# Liv_Flo_Sign_LED_V1_0.net
KiCad netlist of a schematic drawn in Altium Designer
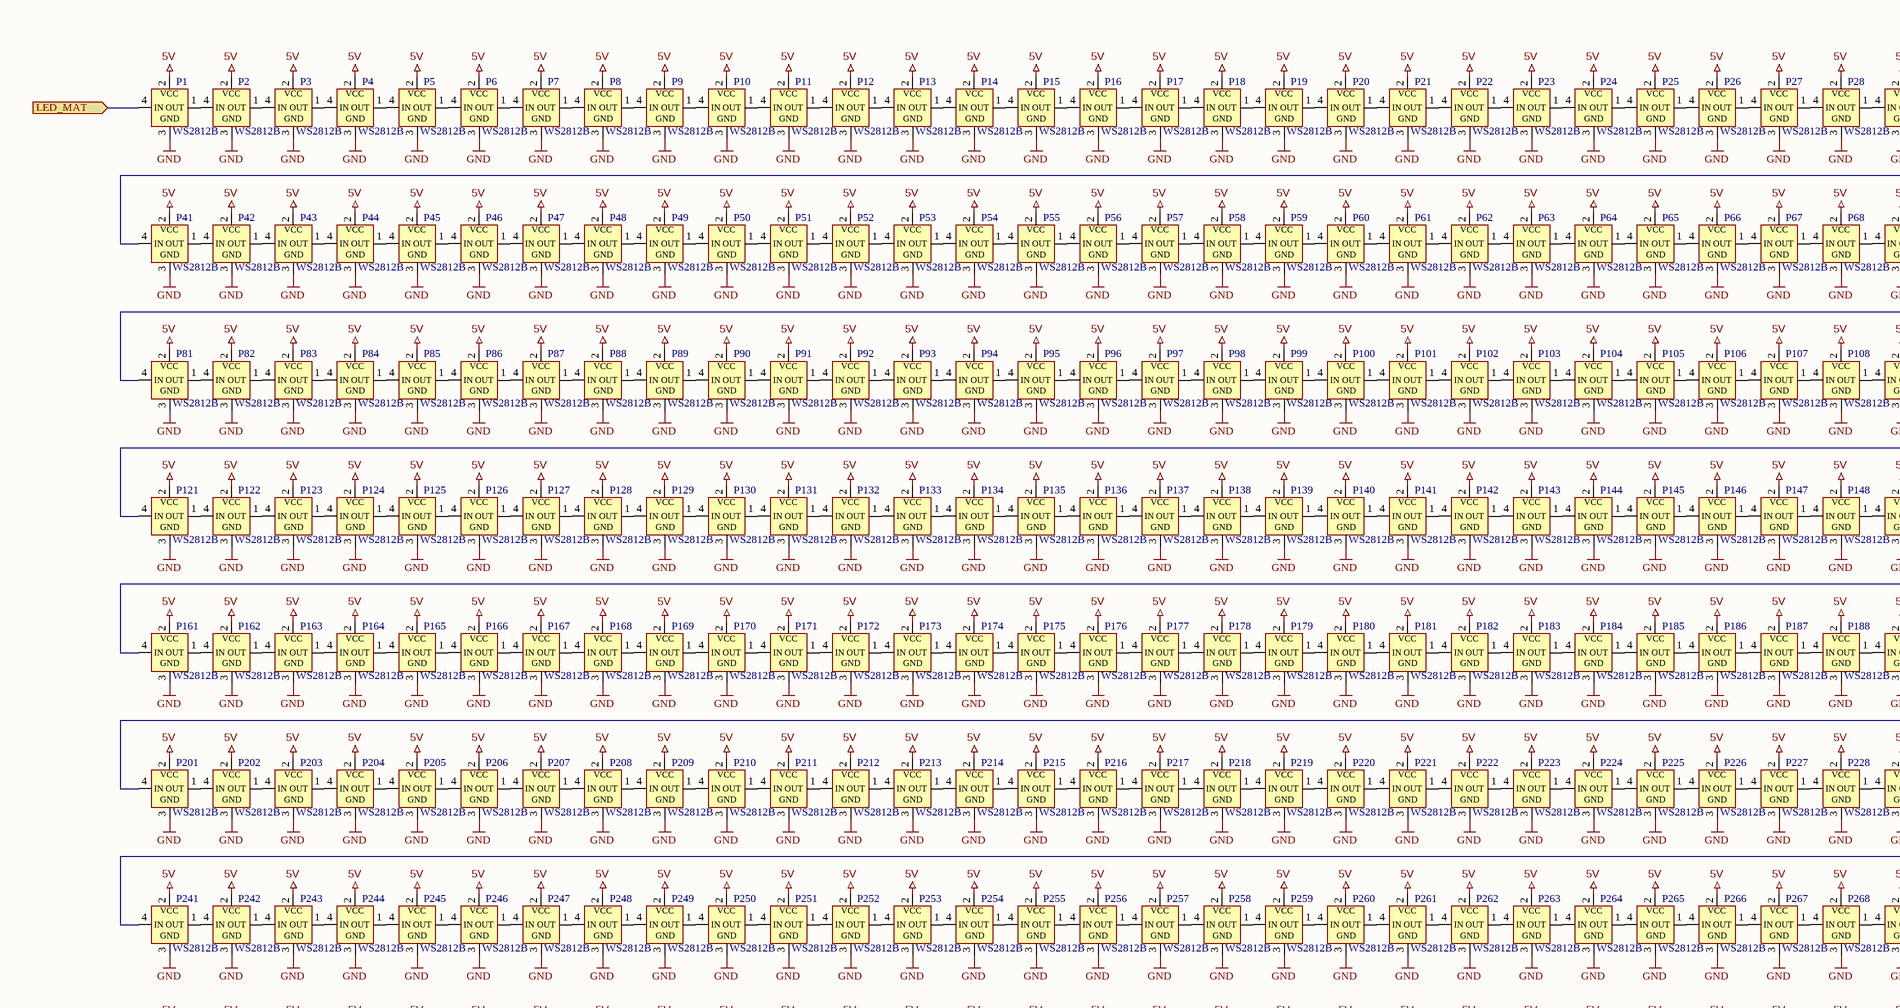
[diagram p0: Liv_Flo_Sign_LED_V1.0.SchDoc, top left]
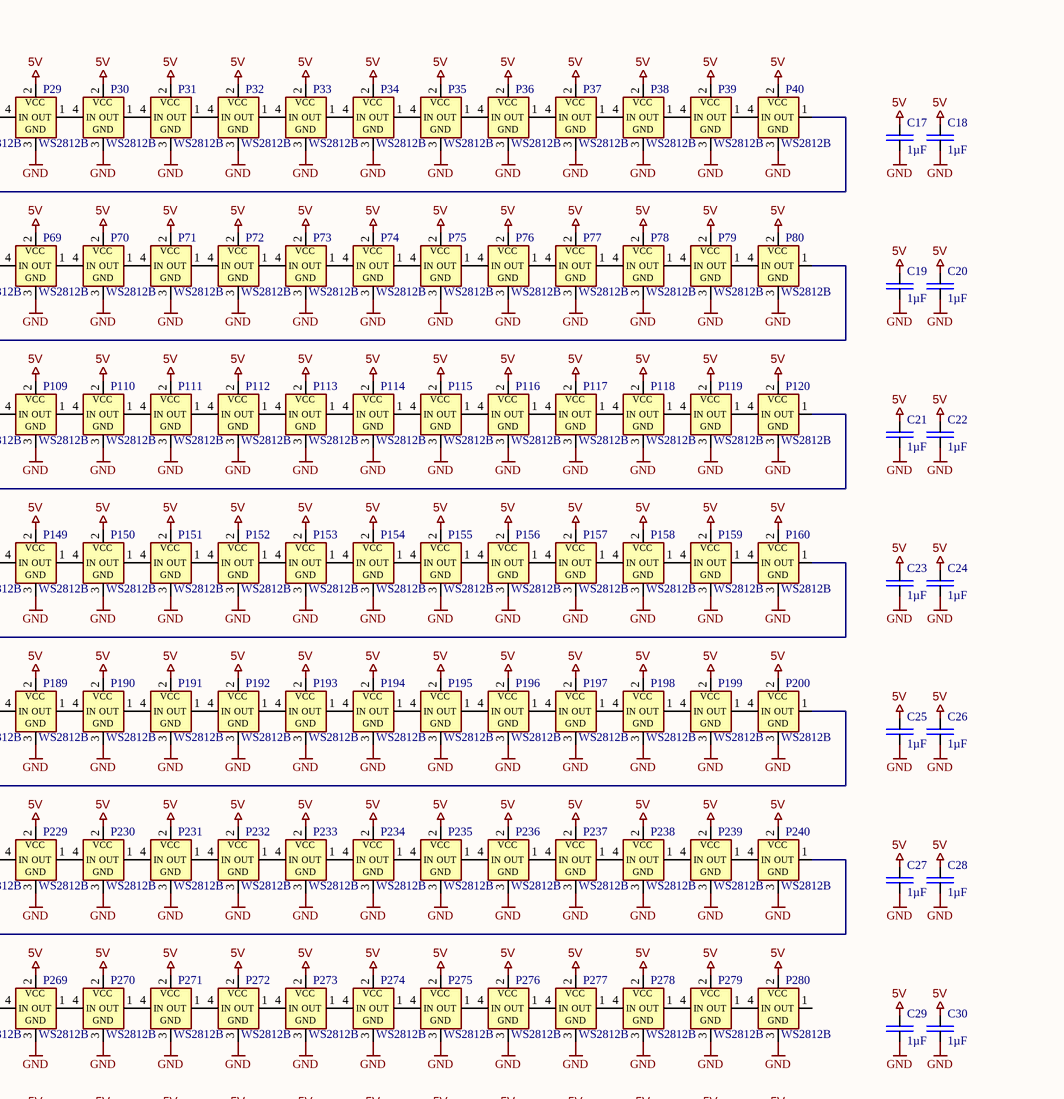
[diagram p1: Liv_Flo_Sign_LED_V1.0.SchDoc, top right]
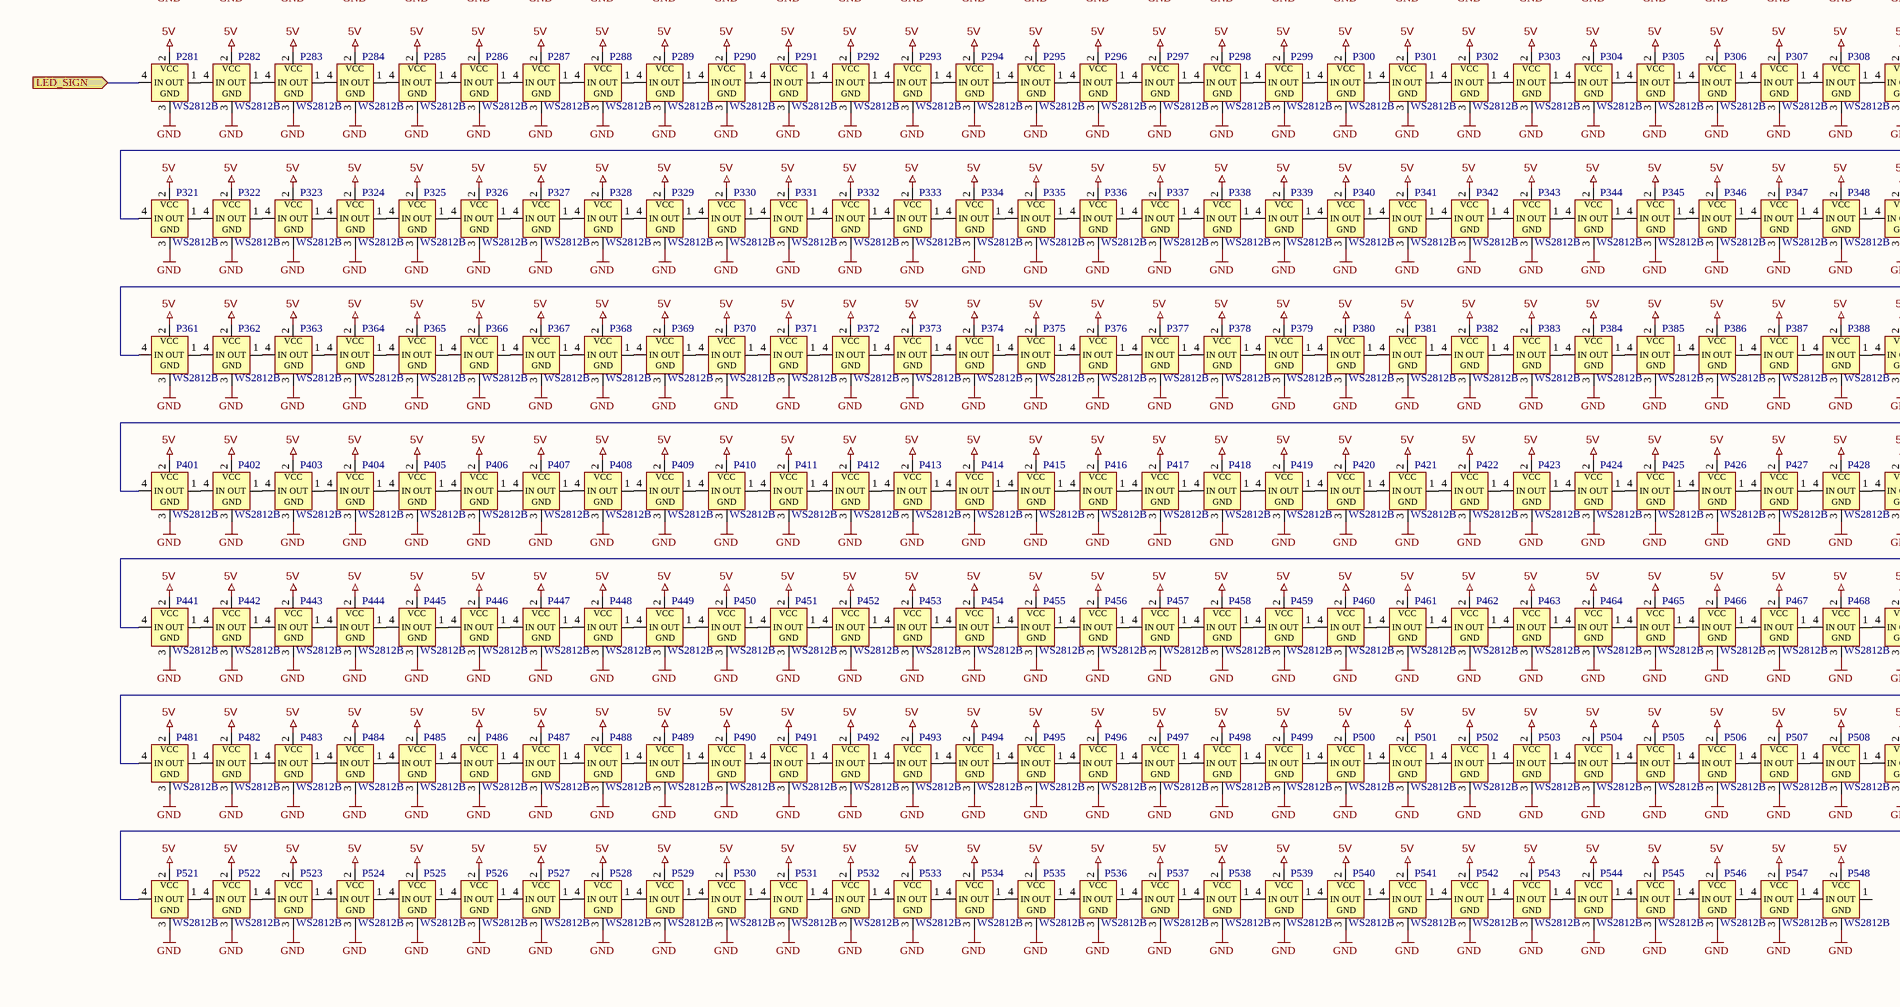
[diagram p2: Liv_Flo_Sign_LED_V1.0.SchDoc, bottom left]
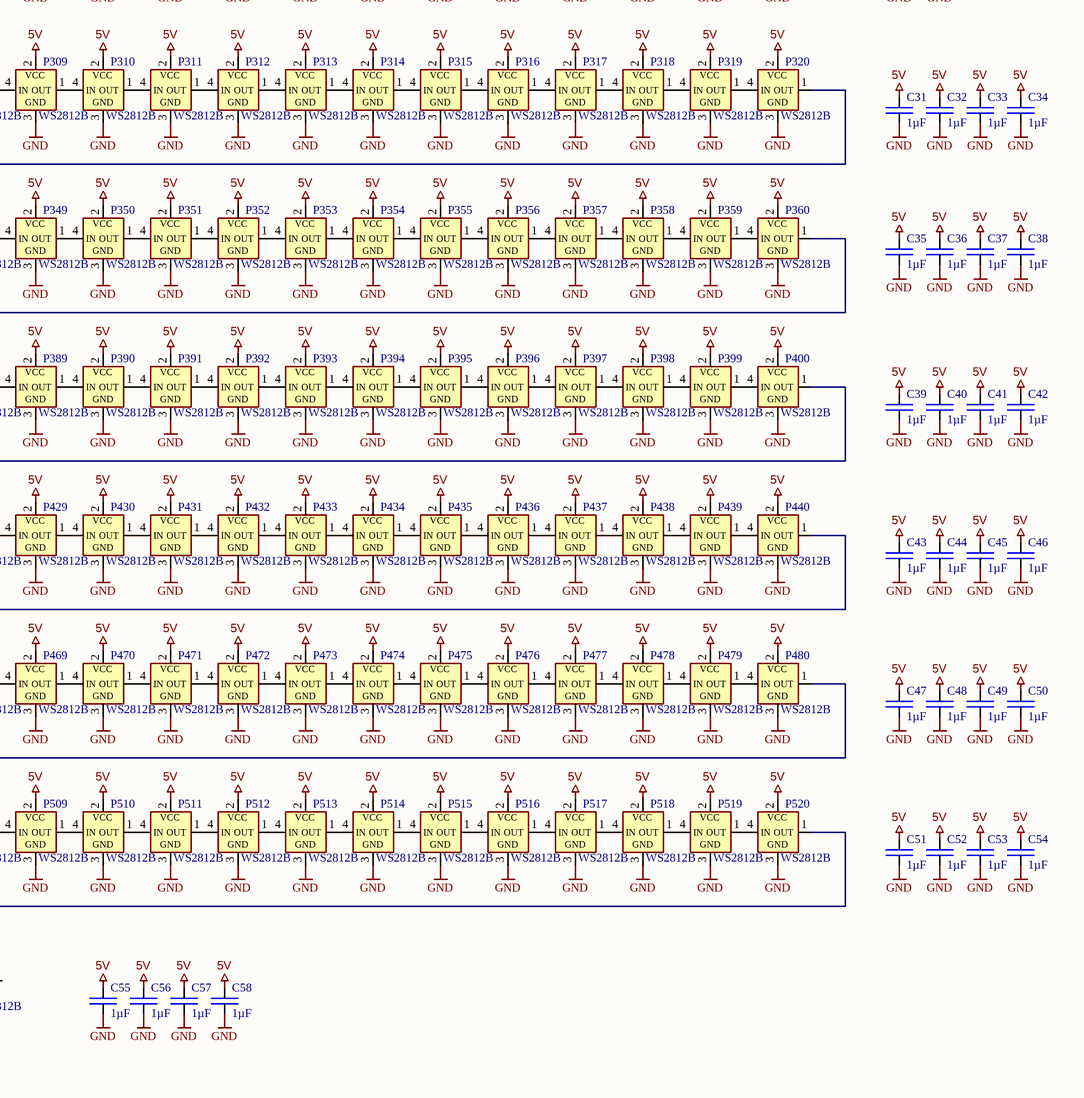
[diagram p3: Liv_Flo_Sign_LED_V1.0.SchDoc, bottom right]

(export (version "E")
  (design (tool "Eeschema 10.0.6"))
  (components
    (comp (ref "C17")
      (value "1µF")
      (footprint "SMD Keramikkondensator 0402")
      (description "SMD Ceramic Capacitor E6")
      (libsource (lib "Ceramic Capacitors-E6") (part "E6 - 4.7uF"))
    )
    (comp (ref "C18")
      (value "1µF")
      (footprint "SMD Keramikkondensator 0402")
      (description "SMD Ceramic Capacitor E6")
      (libsource (lib "Ceramic Capacitors-E6") (part "E6 - 4.7uF"))
    )
    (comp (ref "C19")
      (value "1µF")
      (footprint "SMD Keramikkondensator 0402")
      (description "SMD Ceramic Capacitor E6")
      (libsource (lib "Ceramic Capacitors-E6") (part "E6 - 4.7uF"))
    )
    (comp (ref "C20")
      (value "1µF")
      (footprint "SMD Keramikkondensator 0402")
      (description "SMD Ceramic Capacitor E6")
      (libsource (lib "Ceramic Capacitors-E6") (part "E6 - 4.7uF"))
    )
    (comp (ref "C21")
      (value "1µF")
      (footprint "SMD Keramikkondensator 0402")
      (description "SMD Ceramic Capacitor E6")
      (libsource (lib "Ceramic Capacitors-E6") (part "E6 - 4.7uF"))
    )
    (comp (ref "C22")
      (value "1µF")
      (footprint "SMD Keramikkondensator 0402")
      (description "SMD Ceramic Capacitor E6")
      (libsource (lib "Ceramic Capacitors-E6") (part "E6 - 4.7uF"))
    )
    (comp (ref "C23")
      (value "1µF")
      (footprint "SMD Keramikkondensator 0402")
      (description "SMD Ceramic Capacitor E6")
      (libsource (lib "Ceramic Capacitors-E6") (part "E6 - 4.7uF"))
    )
    (comp (ref "C24")
      (value "1µF")
      (footprint "SMD Keramikkondensator 0402")
      (description "SMD Ceramic Capacitor E6")
      (libsource (lib "Ceramic Capacitors-E6") (part "E6 - 4.7uF"))
    )
    (comp (ref "C25")
      (value "1µF")
      (footprint "SMD Keramikkondensator 0402")
      (description "SMD Ceramic Capacitor E6")
      (libsource (lib "Ceramic Capacitors-E6") (part "E6 - 4.7uF"))
    )
    (comp (ref "C26")
      (value "1µF")
      (footprint "SMD Keramikkondensator 0402")
      (description "SMD Ceramic Capacitor E6")
      (libsource (lib "Ceramic Capacitors-E6") (part "E6 - 4.7uF"))
    )
    (comp (ref "C27")
      (value "1µF")
      (footprint "SMD Keramikkondensator 0402")
      (description "SMD Ceramic Capacitor E6")
      (libsource (lib "Ceramic Capacitors-E6") (part "E6 - 4.7uF"))
    )
    (comp (ref "C28")
      (value "1µF")
      (footprint "SMD Keramikkondensator 0402")
      (description "SMD Ceramic Capacitor E6")
      (libsource (lib "Ceramic Capacitors-E6") (part "E6 - 4.7uF"))
    )
    (comp (ref "C29")
      (value "1µF")
      (footprint "SMD Keramikkondensator 0402")
      (description "SMD Ceramic Capacitor E6")
      (libsource (lib "Ceramic Capacitors-E6") (part "E6 - 4.7uF"))
    )
    (comp (ref "C30")
      (value "1µF")
      (footprint "SMD Keramikkondensator 0402")
      (description "SMD Ceramic Capacitor E6")
      (libsource (lib "Ceramic Capacitors-E6") (part "E6 - 4.7uF"))
    )
    (comp (ref "C31")
      (value "1µF")
      (footprint "SMD Keramikkondensator 0402")
      (description "SMD Ceramic Capacitor E6")
      (libsource (lib "Ceramic Capacitors-E6") (part "E6 - 4.7uF"))
    )
    (comp (ref "C32")
      (value "1µF")
      (footprint "SMD Keramikkondensator 0402")
      (description "SMD Ceramic Capacitor E6")
      (libsource (lib "Ceramic Capacitors-E6") (part "E6 - 4.7uF"))
    )
    (comp (ref "C33")
      (value "1µF")
      (footprint "SMD Keramikkondensator 0402")
      (description "SMD Ceramic Capacitor E6")
      (libsource (lib "Ceramic Capacitors-E6") (part "E6 - 4.7uF"))
    )
    (comp (ref "C34")
      (value "1µF")
      (footprint "SMD Keramikkondensator 0402")
      (description "SMD Ceramic Capacitor E6")
      (libsource (lib "Ceramic Capacitors-E6") (part "E6 - 4.7uF"))
    )
    (comp (ref "C35")
      (value "1µF")
      (footprint "SMD Keramikkondensator 0402")
      (description "SMD Ceramic Capacitor E6")
      (libsource (lib "Ceramic Capacitors-E6") (part "E6 - 4.7uF"))
    )
    (comp (ref "C36")
      (value "1µF")
      (footprint "SMD Keramikkondensator 0402")
      (description "SMD Ceramic Capacitor E6")
      (libsource (lib "Ceramic Capacitors-E6") (part "E6 - 4.7uF"))
    )
    (comp (ref "C37")
      (value "1µF")
      (footprint "SMD Keramikkondensator 0402")
      (description "SMD Ceramic Capacitor E6")
      (libsource (lib "Ceramic Capacitors-E6") (part "E6 - 4.7uF"))
    )
    (comp (ref "C38")
      (value "1µF")
      (footprint "SMD Keramikkondensator 0402")
      (description "SMD Ceramic Capacitor E6")
      (libsource (lib "Ceramic Capacitors-E6") (part "E6 - 4.7uF"))
    )
    (comp (ref "C39")
      (value "1µF")
      (footprint "SMD Keramikkondensator 0402")
      (description "SMD Ceramic Capacitor E6")
      (libsource (lib "Ceramic Capacitors-E6") (part "E6 - 4.7uF"))
    )
    (comp (ref "C40")
      (value "1µF")
      (footprint "SMD Keramikkondensator 0402")
      (description "SMD Ceramic Capacitor E6")
      (libsource (lib "Ceramic Capacitors-E6") (part "E6 - 4.7uF"))
    )
    (comp (ref "C41")
      (value "1µF")
      (footprint "SMD Keramikkondensator 0402")
      (description "SMD Ceramic Capacitor E6")
      (libsource (lib "Ceramic Capacitors-E6") (part "E6 - 4.7uF"))
    )
    (comp (ref "C42")
      (value "1µF")
      (footprint "SMD Keramikkondensator 0402")
      (description "SMD Ceramic Capacitor E6")
      (libsource (lib "Ceramic Capacitors-E6") (part "E6 - 4.7uF"))
    )
    (comp (ref "C43")
      (value "1µF")
      (footprint "SMD Keramikkondensator 0402")
      (description "SMD Ceramic Capacitor E6")
      (libsource (lib "Ceramic Capacitors-E6") (part "E6 - 4.7uF"))
    )
    (comp (ref "C44")
      (value "1µF")
      (footprint "SMD Keramikkondensator 0402")
      (description "SMD Ceramic Capacitor E6")
      (libsource (lib "Ceramic Capacitors-E6") (part "E6 - 4.7uF"))
    )
    (comp (ref "C45")
      (value "1µF")
      (footprint "SMD Keramikkondensator 0402")
      (description "SMD Ceramic Capacitor E6")
      (libsource (lib "Ceramic Capacitors-E6") (part "E6 - 4.7uF"))
    )
    (comp (ref "C46")
      (value "1µF")
      (footprint "SMD Keramikkondensator 0402")
      (description "SMD Ceramic Capacitor E6")
      (libsource (lib "Ceramic Capacitors-E6") (part "E6 - 4.7uF"))
    )
    (comp (ref "C47")
      (value "1µF")
      (footprint "SMD Keramikkondensator 0402")
      (description "SMD Ceramic Capacitor E6")
      (libsource (lib "Ceramic Capacitors-E6") (part "E6 - 4.7uF"))
    )
    (comp (ref "C48")
      (value "1µF")
      (footprint "SMD Keramikkondensator 0402")
      (description "SMD Ceramic Capacitor E6")
      (libsource (lib "Ceramic Capacitors-E6") (part "E6 - 4.7uF"))
    )
    (comp (ref "C49")
      (value "1µF")
      (footprint "SMD Keramikkondensator 0402")
      (description "SMD Ceramic Capacitor E6")
      (libsource (lib "Ceramic Capacitors-E6") (part "E6 - 4.7uF"))
    )
    (comp (ref "C50")
      (value "1µF")
      (footprint "SMD Keramikkondensator 0402")
      (description "SMD Ceramic Capacitor E6")
      (libsource (lib "Ceramic Capacitors-E6") (part "E6 - 4.7uF"))
    )
    (comp (ref "C51")
      (value "1µF")
      (footprint "SMD Keramikkondensator 0402")
      (description "SMD Ceramic Capacitor E6")
      (libsource (lib "Ceramic Capacitors-E6") (part "E6 - 4.7uF"))
    )
    (comp (ref "C52")
      (value "1µF")
      (footprint "SMD Keramikkondensator 0402")
      (description "SMD Ceramic Capacitor E6")
      (libsource (lib "Ceramic Capacitors-E6") (part "E6 - 4.7uF"))
    )
    (comp (ref "C53")
      (value "1µF")
      (footprint "SMD Keramikkondensator 0402")
      (description "SMD Ceramic Capacitor E6")
      (libsource (lib "Ceramic Capacitors-E6") (part "E6 - 4.7uF"))
    )
    (comp (ref "C54")
      (value "1µF")
      (footprint "SMD Keramikkondensator 0402")
      (description "SMD Ceramic Capacitor E6")
      (libsource (lib "Ceramic Capacitors-E6") (part "E6 - 4.7uF"))
    )
    (comp (ref "C55")
      (value "1µF")
      (footprint "SMD Keramikkondensator 0402")
      (description "SMD Ceramic Capacitor E6")
      (libsource (lib "Ceramic Capacitors-E6") (part "E6 - 4.7uF"))
    )
    (comp (ref "C56")
      (value "1µF")
      (footprint "SMD Keramikkondensator 0402")
      (description "SMD Ceramic Capacitor E6")
      (libsource (lib "Ceramic Capacitors-E6") (part "E6 - 4.7uF"))
    )
    (comp (ref "C57")
      (value "1µF")
      (footprint "SMD Keramikkondensator 0402")
      (description "SMD Ceramic Capacitor E6")
      (libsource (lib "Ceramic Capacitors-E6") (part "E6 - 4.7uF"))
    )
    (comp (ref "C58")
      (value "1µF")
      (footprint "SMD Keramikkondensator 0402")
      (description "SMD Ceramic Capacitor E6")
      (libsource (lib "Ceramic Capacitors-E6") (part "E6 - 4.7uF"))
    )
    (comp (ref "P1")
      (value "WS2812B")
      (footprint "SMD LED WS2812B-1010RGBC")
      (description "Smart RGB-LED")
      (libsource (lib "Liv_Flo_Sign") (part "P-XL-1010RGBC-WS2812B"))
    )
    (comp (ref "P2")
      (value "WS2812B")
      (footprint "SMD LED WS2812B-1010RGBC")
      (description "Smart RGB-LED")
      (libsource (lib "Liv_Flo_Sign") (part "P-XL-1010RGBC-WS2812B"))
    )
    (comp (ref "P3")
      (value "WS2812B")
      (footprint "SMD LED WS2812B-1010RGBC")
      (description "Smart RGB-LED")
      (libsource (lib "Liv_Flo_Sign") (part "P-XL-1010RGBC-WS2812B"))
    )
    (comp (ref "P4")
      (value "WS2812B")
      (footprint "SMD LED WS2812B-1010RGBC")
      (description "Smart RGB-LED")
      (libsource (lib "Liv_Flo_Sign") (part "P-XL-1010RGBC-WS2812B"))
    )
    (comp (ref "P5")
      (value "WS2812B")
      (footprint "SMD LED WS2812B-1010RGBC")
      (description "Smart RGB-LED")
      (libsource (lib "Liv_Flo_Sign") (part "P-XL-1010RGBC-WS2812B"))
    )
    (comp (ref "P6")
      (value "WS2812B")
      (footprint "SMD LED WS2812B-1010RGBC")
      (description "Smart RGB-LED")
      (libsource (lib "Liv_Flo_Sign") (part "P-XL-1010RGBC-WS2812B"))
    )
    (comp (ref "P7")
      (value "WS2812B")
      (footprint "SMD LED WS2812B-1010RGBC")
      (description "Smart RGB-LED")
      (libsource (lib "Liv_Flo_Sign") (part "P-XL-1010RGBC-WS2812B"))
    )
    (comp (ref "P8")
      (value "WS2812B")
      (footprint "SMD LED WS2812B-1010RGBC")
      (description "Smart RGB-LED")
      (libsource (lib "Liv_Flo_Sign") (part "P-XL-1010RGBC-WS2812B"))
    )
    (comp (ref "P9")
      (value "WS2812B")
      (footprint "SMD LED WS2812B-1010RGBC")
      (description "Smart RGB-LED")
      (libsource (lib "Liv_Flo_Sign") (part "P-XL-1010RGBC-WS2812B"))
    )
    (comp (ref "P10")
      (value "WS2812B")
      (footprint "SMD LED WS2812B-1010RGBC")
      (description "Smart RGB-LED")
      (libsource (lib "Liv_Flo_Sign") (part "P-XL-1010RGBC-WS2812B"))
    )
    (comp (ref "P11")
      (value "WS2812B")
      (footprint "SMD LED WS2812B-1010RGBC")
      (description "Smart RGB-LED")
      (libsource (lib "Liv_Flo_Sign") (part "P-XL-1010RGBC-WS2812B"))
    )
    (comp (ref "P12")
      (value "WS2812B")
      (footprint "SMD LED WS2812B-1010RGBC")
      (description "Smart RGB-LED")
      (libsource (lib "Liv_Flo_Sign") (part "P-XL-1010RGBC-WS2812B"))
    )
    (comp (ref "P13")
      (value "WS2812B")
      (footprint "SMD LED WS2812B-1010RGBC")
      (description "Smart RGB-LED")
      (libsource (lib "Liv_Flo_Sign") (part "P-XL-1010RGBC-WS2812B"))
    )
    (comp (ref "P14")
      (value "WS2812B")
      (footprint "SMD LED WS2812B-1010RGBC")
      (description "Smart RGB-LED")
      (libsource (lib "Liv_Flo_Sign") (part "P-XL-1010RGBC-WS2812B"))
    )
    (comp (ref "P15")
      (value "WS2812B")
      (footprint "SMD LED WS2812B-1010RGBC")
      (description "Smart RGB-LED")
      (libsource (lib "Liv_Flo_Sign") (part "P-XL-1010RGBC-WS2812B"))
    )
    (comp (ref "P16")
      (value "WS2812B")
      (footprint "SMD LED WS2812B-1010RGBC")
      (description "Smart RGB-LED")
      (libsource (lib "Liv_Flo_Sign") (part "P-XL-1010RGBC-WS2812B"))
    )
    (comp (ref "P17")
      (value "WS2812B")
      (footprint "SMD LED WS2812B-1010RGBC")
      (description "Smart RGB-LED")
      (libsource (lib "Liv_Flo_Sign") (part "P-XL-1010RGBC-WS2812B"))
    )
    (comp (ref "P18")
      (value "WS2812B")
      (footprint "SMD LED WS2812B-1010RGBC")
      (description "Smart RGB-LED")
      (libsource (lib "Liv_Flo_Sign") (part "P-XL-1010RGBC-WS2812B"))
    )
    (comp (ref "P19")
      (value "WS2812B")
      (footprint "SMD LED WS2812B-1010RGBC")
      (description "Smart RGB-LED")
      (libsource (lib "Liv_Flo_Sign") (part "P-XL-1010RGBC-WS2812B"))
    )
    (comp (ref "P20")
      (value "WS2812B")
      (footprint "SMD LED WS2812B-1010RGBC")
      (description "Smart RGB-LED")
      (libsource (lib "Liv_Flo_Sign") (part "P-XL-1010RGBC-WS2812B"))
    )
    (comp (ref "P21")
      (value "WS2812B")
      (footprint "SMD LED WS2812B-1010RGBC")
      (description "Smart RGB-LED")
      (libsource (lib "Liv_Flo_Sign") (part "P-XL-1010RGBC-WS2812B"))
    )
    (comp (ref "P22")
      (value "WS2812B")
      (footprint "SMD LED WS2812B-1010RGBC")
      (description "Smart RGB-LED")
      (libsource (lib "Liv_Flo_Sign") (part "P-XL-1010RGBC-WS2812B"))
    )
    (comp (ref "P23")
      (value "WS2812B")
      (footprint "SMD LED WS2812B-1010RGBC")
      (description "Smart RGB-LED")
      (libsource (lib "Liv_Flo_Sign") (part "P-XL-1010RGBC-WS2812B"))
    )
    (comp (ref "P24")
      (value "WS2812B")
      (footprint "SMD LED WS2812B-1010RGBC")
      (description "Smart RGB-LED")
      (libsource (lib "Liv_Flo_Sign") (part "P-XL-1010RGBC-WS2812B"))
    )
    (comp (ref "P25")
      (value "WS2812B")
      (footprint "SMD LED WS2812B-1010RGBC")
      (description "Smart RGB-LED")
      (libsource (lib "Liv_Flo_Sign") (part "P-XL-1010RGBC-WS2812B"))
    )
    (comp (ref "P26")
      (value "WS2812B")
      (footprint "SMD LED WS2812B-1010RGBC")
      (description "Smart RGB-LED")
      (libsource (lib "Liv_Flo_Sign") (part "P-XL-1010RGBC-WS2812B"))
    )
    (comp (ref "P27")
      (value "WS2812B")
      (footprint "SMD LED WS2812B-1010RGBC")
      (description "Smart RGB-LED")
      (libsource (lib "Liv_Flo_Sign") (part "P-XL-1010RGBC-WS2812B"))
    )
    (comp (ref "P28")
      (value "WS2812B")
      (footprint "SMD LED WS2812B-1010RGBC")
      (description "Smart RGB-LED")
      (libsource (lib "Liv_Flo_Sign") (part "P-XL-1010RGBC-WS2812B"))
    )
    (comp (ref "P29")
      (value "WS2812B")
      (footprint "SMD LED WS2812B-1010RGBC")
      (description "Smart RGB-LED")
      (libsource (lib "Liv_Flo_Sign") (part "P-XL-1010RGBC-WS2812B"))
    )
    (comp (ref "P30")
      (value "WS2812B")
      (footprint "SMD LED WS2812B-1010RGBC")
      (description "Smart RGB-LED")
      (libsource (lib "Liv_Flo_Sign") (part "P-XL-1010RGBC-WS2812B"))
    )
    (comp (ref "P31")
      (value "WS2812B")
      (footprint "SMD LED WS2812B-1010RGBC")
      (description "Smart RGB-LED")
      (libsource (lib "Liv_Flo_Sign") (part "P-XL-1010RGBC-WS2812B"))
    )
    (comp (ref "P32")
      (value "WS2812B")
      (footprint "SMD LED WS2812B-1010RGBC")
      (description "Smart RGB-LED")
      (libsource (lib "Liv_Flo_Sign") (part "P-XL-1010RGBC-WS2812B"))
    )
    (comp (ref "P33")
      (value "WS2812B")
      (footprint "SMD LED WS2812B-1010RGBC")
      (description "Smart RGB-LED")
      (libsource (lib "Liv_Flo_Sign") (part "P-XL-1010RGBC-WS2812B"))
    )
    (comp (ref "P34")
      (value "WS2812B")
      (footprint "SMD LED WS2812B-1010RGBC")
      (description "Smart RGB-LED")
      (libsource (lib "Liv_Flo_Sign") (part "P-XL-1010RGBC-WS2812B"))
    )
    (comp (ref "P35")
      (value "WS2812B")
      (footprint "SMD LED WS2812B-1010RGBC")
      (description "Smart RGB-LED")
      (libsource (lib "Liv_Flo_Sign") (part "P-XL-1010RGBC-WS2812B"))
    )
    (comp (ref "P36")
      (value "WS2812B")
      (footprint "SMD LED WS2812B-1010RGBC")
      (description "Smart RGB-LED")
      (libsource (lib "Liv_Flo_Sign") (part "P-XL-1010RGBC-WS2812B"))
    )
    (comp (ref "P37")
      (value "WS2812B")
      (footprint "SMD LED WS2812B-1010RGBC")
      (description "Smart RGB-LED")
      (libsource (lib "Liv_Flo_Sign") (part "P-XL-1010RGBC-WS2812B"))
    )
    (comp (ref "P38")
      (value "WS2812B")
      (footprint "SMD LED WS2812B-1010RGBC")
      (description "Smart RGB-LED")
      (libsource (lib "Liv_Flo_Sign") (part "P-XL-1010RGBC-WS2812B"))
    )
    (comp (ref "P39")
      (value "WS2812B")
      (footprint "SMD LED WS2812B-1010RGBC")
      (description "Smart RGB-LED")
      (libsource (lib "Liv_Flo_Sign") (part "P-XL-1010RGBC-WS2812B"))
    )
    (comp (ref "P40")
      (value "WS2812B")
      (footprint "SMD LED WS2812B-1010RGBC")
      (description "Smart RGB-LED")
      (libsource (lib "Liv_Flo_Sign") (part "P-XL-1010RGBC-WS2812B"))
    )
    (comp (ref "P41")
      (value "WS2812B")
      (footprint "SMD LED WS2812B-1010RGBC")
      (description "Smart RGB-LED")
      (libsource (lib "Liv_Flo_Sign") (part "P-XL-1010RGBC-WS2812B"))
    )
    (comp (ref "P42")
      (value "WS2812B")
      (footprint "SMD LED WS2812B-1010RGBC")
      (description "Smart RGB-LED")
      (libsource (lib "Liv_Flo_Sign") (part "P-XL-1010RGBC-WS2812B"))
    )
    (comp (ref "P43")
      (value "WS2812B")
      (footprint "SMD LED WS2812B-1010RGBC")
      (description "Smart RGB-LED")
      (libsource (lib "Liv_Flo_Sign") (part "P-XL-1010RGBC-WS2812B"))
    )
    (comp (ref "P44")
      (value "WS2812B")
      (footprint "SMD LED WS2812B-1010RGBC")
      (description "Smart RGB-LED")
      (libsource (lib "Liv_Flo_Sign") (part "P-XL-1010RGBC-WS2812B"))
    )
    (comp (ref "P45")
      (value "WS2812B")
      (footprint "SMD LED WS2812B-1010RGBC")
      (description "Smart RGB-LED")
      (libsource (lib "Liv_Flo_Sign") (part "P-XL-1010RGBC-WS2812B"))
    )
    (comp (ref "P46")
      (value "WS2812B")
      (footprint "SMD LED WS2812B-1010RGBC")
      (description "Smart RGB-LED")
      (libsource (lib "Liv_Flo_Sign") (part "P-XL-1010RGBC-WS2812B"))
    )
    (comp (ref "P47")
      (value "WS2812B")
      (footprint "SMD LED WS2812B-1010RGBC")
      (description "Smart RGB-LED")
      (libsource (lib "Liv_Flo_Sign") (part "P-XL-1010RGBC-WS2812B"))
    )
    (comp (ref "P48")
      (value "WS2812B")
      (footprint "SMD LED WS2812B-1010RGBC")
      (description "Smart RGB-LED")
      (libsource (lib "Liv_Flo_Sign") (part "P-XL-1010RGBC-WS2812B"))
    )
    (comp (ref "P49")
      (value "WS2812B")
      (footprint "SMD LED WS2812B-1010RGBC")
      (description "Smart RGB-LED")
      (libsource (lib "Liv_Flo_Sign") (part "P-XL-1010RGBC-WS2812B"))
    )
    (comp (ref "P50")
      (value "WS2812B")
      (footprint "SMD LED WS2812B-1010RGBC")
      (description "Smart RGB-LED")
      (libsource (lib "Liv_Flo_Sign") (part "P-XL-1010RGBC-WS2812B"))
    )
    (comp (ref "P51")
      (value "WS2812B")
      (footprint "SMD LED WS2812B-1010RGBC")
      (description "Smart RGB-LED")
      (libsource (lib "Liv_Flo_Sign") (part "P-XL-1010RGBC-WS2812B"))
    )
    (comp (ref "P52")
      (value "WS2812B")
      (footprint "SMD LED WS2812B-1010RGBC")
      (description "Smart RGB-LED")
      (libsource (lib "Liv_Flo_Sign") (part "P-XL-1010RGBC-WS2812B"))
    )
    (comp (ref "P53")
      (value "WS2812B")
      (footprint "SMD LED WS2812B-1010RGBC")
      (description "Smart RGB-LED")
      (libsource (lib "Liv_Flo_Sign") (part "P-XL-1010RGBC-WS2812B"))
    )
    (comp (ref "P54")
      (value "WS2812B")
      (footprint "SMD LED WS2812B-1010RGBC")
      (description "Smart RGB-LED")
      (libsource (lib "Liv_Flo_Sign") (part "P-XL-1010RGBC-WS2812B"))
    )
    (comp (ref "P55")
      (value "WS2812B")
      (footprint "SMD LED WS2812B-1010RGBC")
      (description "Smart RGB-LED")
      (libsource (lib "Liv_Flo_Sign") (part "P-XL-1010RGBC-WS2812B"))
    )
    (comp (ref "P56")
      (value "WS2812B")
      (footprint "SMD LED WS2812B-1010RGBC")
      (description "Smart RGB-LED")
      (libsource (lib "Liv_Flo_Sign") (part "P-XL-1010RGBC-WS2812B"))
    )
    (comp (ref "P57")
      (value "WS2812B")
      (footprint "SMD LED WS2812B-1010RGBC")
      (description "Smart RGB-LED")
      (libsource (lib "Liv_Flo_Sign") (part "P-XL-1010RGBC-WS2812B"))
    )
    (comp (ref "P58")
      (value "WS2812B")
      (footprint "SMD LED WS2812B-1010RGBC")
      (description "Smart RGB-LED")
      (libsource (lib "Liv_Flo_Sign") (part "P-XL-1010RGBC-WS2812B"))
    )
    (comp (ref "P59")
      (value "WS2812B")
      (footprint "SMD LED WS2812B-1010RGBC")
      (description "Smart RGB-LED")
      (libsource (lib "Liv_Flo_Sign") (part "P-XL-1010RGBC-WS2812B"))
    )
    (comp (ref "P60")
      (value "WS2812B")
      (footprint "SMD LED WS2812B-1010RGBC")
      (description "Smart RGB-LED")
      (libsource (lib "Liv_Flo_Sign") (part "P-XL-1010RGBC-WS2812B"))
    )
    (comp (ref "P61")
      (value "WS2812B")
      (footprint "SMD LED WS2812B-1010RGBC")
      (description "Smart RGB-LED")
      (libsource (lib "Liv_Flo_Sign") (part "P-XL-1010RGBC-WS2812B"))
    )
    (comp (ref "P62")
      (value "WS2812B")
      (footprint "SMD LED WS2812B-1010RGBC")
      (description "Smart RGB-LED")
      (libsource (lib "Liv_Flo_Sign") (part "P-XL-1010RGBC-WS2812B"))
    )
    (comp (ref "P63")
      (value "WS2812B")
      (footprint "SMD LED WS2812B-1010RGBC")
      (description "Smart RGB-LED")
      (libsource (lib "Liv_Flo_Sign") (part "P-XL-1010RGBC-WS2812B"))
    )
    (comp (ref "P64")
      (value "WS2812B")
      (footprint "SMD LED WS2812B-1010RGBC")
      (description "Smart RGB-LED")
      (libsource (lib "Liv_Flo_Sign") (part "P-XL-1010RGBC-WS2812B"))
    )
    (comp (ref "P65")
      (value "WS2812B")
      (footprint "SMD LED WS2812B-1010RGBC")
      (description "Smart RGB-LED")
      (libsource (lib "Liv_Flo_Sign") (part "P-XL-1010RGBC-WS2812B"))
    )
    (comp (ref "P66")
      (value "WS2812B")
      (footprint "SMD LED WS2812B-1010RGBC")
      (description "Smart RGB-LED")
      (libsource (lib "Liv_Flo_Sign") (part "P-XL-1010RGBC-WS2812B"))
    )
    (comp (ref "P67")
      (value "WS2812B")
      (footprint "SMD LED WS2812B-1010RGBC")
      (description "Smart RGB-LED")
      (libsource (lib "Liv_Flo_Sign") (part "P-XL-1010RGBC-WS2812B"))
    )
    (comp (ref "P68")
      (value "WS2812B")
      (footprint "SMD LED WS2812B-1010RGBC")
      (description "Smart RGB-LED")
      (libsource (lib "Liv_Flo_Sign") (part "P-XL-1010RGBC-WS2812B"))
    )
    (comp (ref "P69")
      (value "WS2812B")
      (footprint "SMD LED WS2812B-1010RGBC")
      (description "Smart RGB-LED")
      (libsource (lib "Liv_Flo_Sign") (part "P-XL-1010RGBC-WS2812B"))
    )
    (comp (ref "P70")
      (value "WS2812B")
      (footprint "SMD LED WS2812B-1010RGBC")
      (description "Smart RGB-LED")
      (libsource (lib "Liv_Flo_Sign") (part "P-XL-1010RGBC-WS2812B"))
    )
    (comp (ref "P71")
      (value "WS2812B")
      (footprint "SMD LED WS2812B-1010RGBC")
      (description "Smart RGB-LED")
      (libsource (lib "Liv_Flo_Sign") (part "P-XL-1010RGBC-WS2812B"))
    )
    (comp (ref "P72")
      (value "WS2812B")
      (footprint "SMD LED WS2812B-1010RGBC")
      (description "Smart RGB-LED")
      (libsource (lib "Liv_Flo_Sign") (part "P-XL-1010RGBC-WS2812B"))
    )
    (comp (ref "P73")
      (value "WS2812B")
      (footprint "SMD LED WS2812B-1010RGBC")
      (description "Smart RGB-LED")
      (libsource (lib "Liv_Flo_Sign") (part "P-XL-1010RGBC-WS2812B"))
    )
    (comp (ref "P74")
      (value "WS2812B")
      (footprint "SMD LED WS2812B-1010RGBC")
      (description "Smart RGB-LED")
      (libsource (lib "Liv_Flo_Sign") (part "P-XL-1010RGBC-WS2812B"))
    )
    (comp (ref "P75")
      (value "WS2812B")
      (footprint "SMD LED WS2812B-1010RGBC")
      (description "Smart RGB-LED")
      (libsource (lib "Liv_Flo_Sign") (part "P-XL-1010RGBC-WS2812B"))
    )
    (comp (ref "P76")
      (value "WS2812B")
      (footprint "SMD LED WS2812B-1010RGBC")
      (description "Smart RGB-LED")
      (libsource (lib "Liv_Flo_Sign") (part "P-XL-1010RGBC-WS2812B"))
    )
    (comp (ref "P77")
      (value "WS2812B")
      (footprint "SMD LED WS2812B-1010RGBC")
      (description "Smart RGB-LED")
      (libsource (lib "Liv_Flo_Sign") (part "P-XL-1010RGBC-WS2812B"))
    )
    (comp (ref "P78")
      (value "WS2812B")
      (footprint "SMD LED WS2812B-1010RGBC")
      (description "Smart RGB-LED")
      (libsource (lib "Liv_Flo_Sign") (part "P-XL-1010RGBC-WS2812B"))
    )
    (comp (ref "P79")
      (value "WS2812B")
      (footprint "SMD LED WS2812B-1010RGBC")
      (description "Smart RGB-LED")
      (libsource (lib "Liv_Flo_Sign") (part "P-XL-1010RGBC-WS2812B"))
    )
    (comp (ref "P80")
      (value "WS2812B")
      (footprint "SMD LED WS2812B-1010RGBC")
      (description "Smart RGB-LED")
      (libsource (lib "Liv_Flo_Sign") (part "P-XL-1010RGBC-WS2812B"))
    )
    (comp (ref "P81")
      (value "WS2812B")
      (footprint "SMD LED WS2812B-1010RGBC")
      (description "Smart RGB-LED")
      (libsource (lib "Liv_Flo_Sign") (part "P-XL-1010RGBC-WS2812B"))
    )
    (comp (ref "P82")
      (value "WS2812B")
      (footprint "SMD LED WS2812B-1010RGBC")
      (description "Smart RGB-LED")
      (libsource (lib "Liv_Flo_Sign") (part "P-XL-1010RGBC-WS2812B"))
    )
    (comp (ref "P83")
      (value "WS2812B")
      (footprint "SMD LED WS2812B-1010RGBC")
      (description "Smart RGB-LED")
      (libsource (lib "Liv_Flo_Sign") (part "P-XL-1010RGBC-WS2812B"))
    )
    (comp (ref "P84")
      (value "WS2812B")
      (footprint "SMD LED WS2812B-1010RGBC")
      (description "Smart RGB-LED")
      (libsource (lib "Liv_Flo_Sign") (part "P-XL-1010RGBC-WS2812B"))
    )
    (comp (ref "P85")
      (value "WS2812B")
      (footprint "SMD LED WS2812B-1010RGBC")
      (description "Smart RGB-LED")
      (libsource (lib "Liv_Flo_Sign") (part "P-XL-1010RGBC-WS2812B"))
    )
    (comp (ref "P86")
      (value "WS2812B")
      (footprint "SMD LED WS2812B-1010RGBC")
      (description "Smart RGB-LED")
      (libsource (lib "Liv_Flo_Sign") (part "P-XL-1010RGBC-WS2812B"))
    )
    (comp (ref "P87")
      (value "WS2812B")
      (footprint "SMD LED WS2812B-1010RGBC")
      (description "Smart RGB-LED")
      (libsource (lib "Liv_Flo_Sign") (part "P-XL-1010RGBC-WS2812B"))
    )
    (comp (ref "P88")
      (value "WS2812B")
      (footprint "SMD LED WS2812B-1010RGBC")
      (description "Smart RGB-LED")
      (libsource (lib "Liv_Flo_Sign") (part "P-XL-1010RGBC-WS2812B"))
    )
    (comp (ref "P89")
      (value "WS2812B")
      (footprint "SMD LED WS2812B-1010RGBC")
      (description "Smart RGB-LED")
      (libsource (lib "Liv_Flo_Sign") (part "P-XL-1010RGBC-WS2812B"))
    )
    (comp (ref "P90")
      (value "WS2812B")
      (footprint "SMD LED WS2812B-1010RGBC")
      (description "Smart RGB-LED")
      (libsource (lib "Liv_Flo_Sign") (part "P-XL-1010RGBC-WS2812B"))
    )
    (comp (ref "P91")
      (value "WS2812B")
      (footprint "SMD LED WS2812B-1010RGBC")
      (description "Smart RGB-LED")
      (libsource (lib "Liv_Flo_Sign") (part "P-XL-1010RGBC-WS2812B"))
    )
    (comp (ref "P92")
      (value "WS2812B")
      (footprint "SMD LED WS2812B-1010RGBC")
      (description "Smart RGB-LED")
      (libsource (lib "Liv_Flo_Sign") (part "P-XL-1010RGBC-WS2812B"))
    )
    (comp (ref "P93")
      (value "WS2812B")
      (footprint "SMD LED WS2812B-1010RGBC")
      (description "Smart RGB-LED")
      (libsource (lib "Liv_Flo_Sign") (part "P-XL-1010RGBC-WS2812B"))
    )
    (comp (ref "P94")
      (value "WS2812B")
      (footprint "SMD LED WS2812B-1010RGBC")
      (description "Smart RGB-LED")
      (libsource (lib "Liv_Flo_Sign") (part "P-XL-1010RGBC-WS2812B"))
    )
    (comp (ref "P95")
      (value "WS2812B")
      (footprint "SMD LED WS2812B-1010RGBC")
      (description "Smart RGB-LED")
      (libsource (lib "Liv_Flo_Sign") (part "P-XL-1010RGBC-WS2812B"))
    )
    (comp (ref "P96")
      (value "WS2812B")
      (footprint "SMD LED WS2812B-1010RGBC")
      (description "Smart RGB-LED")
      (libsource (lib "Liv_Flo_Sign") (part "P-XL-1010RGBC-WS2812B"))
    )
    (comp (ref "P97")
      (value "WS2812B")
      (footprint "SMD LED WS2812B-1010RGBC")
      (description "Smart RGB-LED")
      (libsource (lib "Liv_Flo_Sign") (part "P-XL-1010RGBC-WS2812B"))
    )
    (comp (ref "P98")
      (value "WS2812B")
      (footprint "SMD LED WS2812B-1010RGBC")
      (description "Smart RGB-LED")
      (libsource (lib "Liv_Flo_Sign") (part "P-XL-1010RGBC-WS2812B"))
    )
    (comp (ref "P99")
      (value "WS2812B")
      (footprint "SMD LED WS2812B-1010RGBC")
      (description "Smart RGB-LED")
      (libsource (lib "Liv_Flo_Sign") (part "P-XL-1010RGBC-WS2812B"))
    )
    (comp (ref "P100")
      (value "WS2812B")
      (footprint "SMD LED WS2812B-1010RGBC")
      (description "Smart RGB-LED")
      (libsource (lib "Liv_Flo_Sign") (part "P-XL-1010RGBC-WS2812B"))
    )
    (comp (ref "P101")
      (value "WS2812B")
      (footprint "SMD LED WS2812B-1010RGBC")
      (description "Smart RGB-LED")
      (libsource (lib "Liv_Flo_Sign") (part "P-XL-1010RGBC-WS2812B"))
    )
    (comp (ref "P102")
      (value "WS2812B")
      (footprint "SMD LED WS2812B-1010RGBC")
      (description "Smart RGB-LED")
      (libsource (lib "Liv_Flo_Sign") (part "P-XL-1010RGBC-WS2812B"))
    )
    (comp (ref "P103")
      (value "WS2812B")
      (footprint "SMD LED WS2812B-1010RGBC")
      (description "Smart RGB-LED")
      (libsource (lib "Liv_Flo_Sign") (part "P-XL-1010RGBC-WS2812B"))
    )
    (comp (ref "P104")
      (value "WS2812B")
      (footprint "SMD LED WS2812B-1010RGBC")
      (description "Smart RGB-LED")
      (libsource (lib "Liv_Flo_Sign") (part "P-XL-1010RGBC-WS2812B"))
    )
    (comp (ref "P105")
      (value "WS2812B")
      (footprint "SMD LED WS2812B-1010RGBC")
      (description "Smart RGB-LED")
      (libsource (lib "Liv_Flo_Sign") (part "P-XL-1010RGBC-WS2812B"))
    )
    (comp (ref "P106")
      (value "WS2812B")
      (footprint "SMD LED WS2812B-1010RGBC")
      (description "Smart RGB-LED")
      (libsource (lib "Liv_Flo_Sign") (part "P-XL-1010RGBC-WS2812B"))
    )
    (comp (ref "P107")
      (value "WS2812B")
      (footprint "SMD LED WS2812B-1010RGBC")
      (description "Smart RGB-LED")
      (libsource (lib "Liv_Flo_Sign") (part "P-XL-1010RGBC-WS2812B"))
    )
    (comp (ref "P108")
      (value "WS2812B")
      (footprint "SMD LED WS2812B-1010RGBC")
      (description "Smart RGB-LED")
      (libsource (lib "Liv_Flo_Sign") (part "P-XL-1010RGBC-WS2812B"))
    )
    (comp (ref "P109")
      (value "WS2812B")
      (footprint "SMD LED WS2812B-1010RGBC")
      (description "Smart RGB-LED")
      (libsource (lib "Liv_Flo_Sign") (part "P-XL-1010RGBC-WS2812B"))
    )
    (comp (ref "P110")
      (value "WS2812B")
      (footprint "SMD LED WS2812B-1010RGBC")
      (description "Smart RGB-LED")
      (libsource (lib "Liv_Flo_Sign") (part "P-XL-1010RGBC-WS2812B"))
    )
    (comp (ref "P111")
      (value "WS2812B")
      (footprint "SMD LED WS2812B-1010RGBC")
      (description "Smart RGB-LED")
      (libsource (lib "Liv_Flo_Sign") (part "P-XL-1010RGBC-WS2812B"))
    )
    (comp (ref "P112")
      (value "WS2812B")
      (footprint "SMD LED WS2812B-1010RGBC")
      (description "Smart RGB-LED")
      (libsource (lib "Liv_Flo_Sign") (part "P-XL-1010RGBC-WS2812B"))
    )
    (comp (ref "P113")
      (value "WS2812B")
      (footprint "SMD LED WS2812B-1010RGBC")
      (description "Smart RGB-LED")
      (libsource (lib "Liv_Flo_Sign") (part "P-XL-1010RGBC-WS2812B"))
    )
    (comp (ref "P114")
      (value "WS2812B")
      (footprint "SMD LED WS2812B-1010RGBC")
      (description "Smart RGB-LED")
      (libsource (lib "Liv_Flo_Sign") (part "P-XL-1010RGBC-WS2812B"))
    )
    (comp (ref "P115")
      (value "WS2812B")
      (footprint "SMD LED WS2812B-1010RGBC")
      (description "Smart RGB-LED")
      (libsource (lib "Liv_Flo_Sign") (part "P-XL-1010RGBC-WS2812B"))
    )
    (comp (ref "P116")
      (value "WS2812B")
      (footprint "SMD LED WS2812B-1010RGBC")
      (description "Smart RGB-LED")
      (libsource (lib "Liv_Flo_Sign") (part "P-XL-1010RGBC-WS2812B"))
    )
    (comp (ref "P117")
      (value "WS2812B")
      (footprint "SMD LED WS2812B-1010RGBC")
      (description "Smart RGB-LED")
      (libsource (lib "Liv_Flo_Sign") (part "P-XL-1010RGBC-WS2812B"))
    )
    (comp (ref "P118")
      (value "WS2812B")
      (footprint "SMD LED WS2812B-1010RGBC")
      (description "Smart RGB-LED")
      (libsource (lib "Liv_Flo_Sign") (part "P-XL-1010RGBC-WS2812B"))
    )
    (comp (ref "P119")
      (value "WS2812B")
      (footprint "SMD LED WS2812B-1010RGBC")
      (description "Smart RGB-LED")
      (libsource (lib "Liv_Flo_Sign") (part "P-XL-1010RGBC-WS2812B"))
    )
    (comp (ref "P120")
      (value "WS2812B")
      (footprint "SMD LED WS2812B-1010RGBC")
      (description "Smart RGB-LED")
      (libsource (lib "Liv_Flo_Sign") (part "P-XL-1010RGBC-WS2812B"))
    )
    (comp (ref "P121")
      (value "WS2812B")
      (footprint "SMD LED WS2812B-1010RGBC")
      (description "Smart RGB-LED")
      (libsource (lib "Liv_Flo_Sign") (part "P-XL-1010RGBC-WS2812B"))
    )
    (comp (ref "P122")
      (value "WS2812B")
      (footprint "SMD LED WS2812B-1010RGBC")
      (description "Smart RGB-LED")
      (libsource (lib "Liv_Flo_Sign") (part "P-XL-1010RGBC-WS2812B"))
    )
    (comp (ref "P123")
      (value "WS2812B")
      (footprint "SMD LED WS2812B-1010RGBC")
      (description "Smart RGB-LED")
      (libsource (lib "Liv_Flo_Sign") (part "P-XL-1010RGBC-WS2812B"))
    )
    (comp (ref "P124")
      (value "WS2812B")
      (footprint "SMD LED WS2812B-1010RGBC")
      (description "Smart RGB-LED")
      (libsource (lib "Liv_Flo_Sign") (part "P-XL-1010RGBC-WS2812B"))
    )
    (comp (ref "P125")
      (value "WS2812B")
      (footprint "SMD LED WS2812B-1010RGBC")
      (description "Smart RGB-LED")
      (libsource (lib "Liv_Flo_Sign") (part "P-XL-1010RGBC-WS2812B"))
    )
    (comp (ref "P126")
      (value "WS2812B")
      (footprint "SMD LED WS2812B-1010RGBC")
      (description "Smart RGB-LED")
      (libsource (lib "Liv_Flo_Sign") (part "P-XL-1010RGBC-WS2812B"))
    )
    (comp (ref "P127")
      (value "WS2812B")
      (footprint "SMD LED WS2812B-1010RGBC")
      (description "Smart RGB-LED")
      (libsource (lib "Liv_Flo_Sign") (part "P-XL-1010RGBC-WS2812B"))
    )
    (comp (ref "P128")
      (value "WS2812B")
      (footprint "SMD LED WS2812B-1010RGBC")
      (description "Smart RGB-LED")
      (libsource (lib "Liv_Flo_Sign") (part "P-XL-1010RGBC-WS2812B"))
    )
    (comp (ref "P129")
      (value "WS2812B")
      (footprint "SMD LED WS2812B-1010RGBC")
      (description "Smart RGB-LED")
      (libsource (lib "Liv_Flo_Sign") (part "P-XL-1010RGBC-WS2812B"))
    )
    (comp (ref "P130")
      (value "WS2812B")
      (footprint "SMD LED WS2812B-1010RGBC")
      (description "Smart RGB-LED")
      (libsource (lib "Liv_Flo_Sign") (part "P-XL-1010RGBC-WS2812B"))
    )
    (comp (ref "P131")
      (value "WS2812B")
      (footprint "SMD LED WS2812B-1010RGBC")
      (description "Smart RGB-LED")
      (libsource (lib "Liv_Flo_Sign") (part "P-XL-1010RGBC-WS2812B"))
    )
    (comp (ref "P132")
      (value "WS2812B")
      (footprint "SMD LED WS2812B-1010RGBC")
      (description "Smart RGB-LED")
      (libsource (lib "Liv_Flo_Sign") (part "P-XL-1010RGBC-WS2812B"))
    )
    (comp (ref "P133")
      (value "WS2812B")
      (footprint "SMD LED WS2812B-1010RGBC")
      (description "Smart RGB-LED")
      (libsource (lib "Liv_Flo_Sign") (part "P-XL-1010RGBC-WS2812B"))
    )
    (comp (ref "P134")
      (value "WS2812B")
      (footprint "SMD LED WS2812B-1010RGBC")
      (description "Smart RGB-LED")
      (libsource (lib "Liv_Flo_Sign") (part "P-XL-1010RGBC-WS2812B"))
    )
    (comp (ref "P135")
      (value "WS2812B")
      (footprint "SMD LED WS2812B-1010RGBC")
      (description "Smart RGB-LED")
      (libsource (lib "Liv_Flo_Sign") (part "P-XL-1010RGBC-WS2812B"))
    )
    (comp (ref "P136")
      (value "WS2812B")
      (footprint "SMD LED WS2812B-1010RGBC")
      (description "Smart RGB-LED")
      (libsource (lib "Liv_Flo_Sign") (part "P-XL-1010RGBC-WS2812B"))
    )
    (comp (ref "P137")
      (value "WS2812B")
      (footprint "SMD LED WS2812B-1010RGBC")
      (description "Smart RGB-LED")
      (libsource (lib "Liv_Flo_Sign") (part "P-XL-1010RGBC-WS2812B"))
    )
    (comp (ref "P138")
      (value "WS2812B")
      (footprint "SMD LED WS2812B-1010RGBC")
      (description "Smart RGB-LED")
      (libsource (lib "Liv_Flo_Sign") (part "P-XL-1010RGBC-WS2812B"))
    )
    (comp (ref "P139")
      (value "WS2812B")
      (footprint "SMD LED WS2812B-1010RGBC")
      (description "Smart RGB-LED")
      (libsource (lib "Liv_Flo_Sign") (part "P-XL-1010RGBC-WS2812B"))
    )
    (comp (ref "P140")
      (value "WS2812B")
      (footprint "SMD LED WS2812B-1010RGBC")
      (description "Smart RGB-LED")
      (libsource (lib "Liv_Flo_Sign") (part "P-XL-1010RGBC-WS2812B"))
    )
    (comp (ref "P141")
      (value "WS2812B")
      (footprint "SMD LED WS2812B-1010RGBC")
      (description "Smart RGB-LED")
      (libsource (lib "Liv_Flo_Sign") (part "P-XL-1010RGBC-WS2812B"))
    )
    (comp (ref "P142")
      (value "WS2812B")
      (footprint "SMD LED WS2812B-1010RGBC")
      (description "Smart RGB-LED")
      (libsource (lib "Liv_Flo_Sign") (part "P-XL-1010RGBC-WS2812B"))
    )
    (comp (ref "P143")
      (value "WS2812B")
      (footprint "SMD LED WS2812B-1010RGBC")
      (description "Smart RGB-LED")
      (libsource (lib "Liv_Flo_Sign") (part "P-XL-1010RGBC-WS2812B"))
    )
    (comp (ref "P144")
      (value "WS2812B")
      (footprint "SMD LED WS2812B-1010RGBC")
      (description "Smart RGB-LED")
      (libsource (lib "Liv_Flo_Sign") (part "P-XL-1010RGBC-WS2812B"))
    )
    (comp (ref "P145")
      (value "WS2812B")
      (footprint "SMD LED WS2812B-1010RGBC")
      (description "Smart RGB-LED")
      (libsource (lib "Liv_Flo_Sign") (part "P-XL-1010RGBC-WS2812B"))
    )
    (comp (ref "P146")
      (value "WS2812B")
      (footprint "SMD LED WS2812B-1010RGBC")
      (description "Smart RGB-LED")
      (libsource (lib "Liv_Flo_Sign") (part "P-XL-1010RGBC-WS2812B"))
    )
    (comp (ref "P147")
      (value "WS2812B")
      (footprint "SMD LED WS2812B-1010RGBC")
      (description "Smart RGB-LED")
      (libsource (lib "Liv_Flo_Sign") (part "P-XL-1010RGBC-WS2812B"))
    )
    (comp (ref "P148")
      (value "WS2812B")
      (footprint "SMD LED WS2812B-1010RGBC")
      (description "Smart RGB-LED")
      (libsource (lib "Liv_Flo_Sign") (part "P-XL-1010RGBC-WS2812B"))
    )
    (comp (ref "P149")
      (value "WS2812B")
      (footprint "SMD LED WS2812B-1010RGBC")
      (description "Smart RGB-LED")
      (libsource (lib "Liv_Flo_Sign") (part "P-XL-1010RGBC-WS2812B"))
    )
    (comp (ref "P150")
      (value "WS2812B")
      (footprint "SMD LED WS2812B-1010RGBC")
      (description "Smart RGB-LED")
      (libsource (lib "Liv_Flo_Sign") (part "P-XL-1010RGBC-WS2812B"))
    )
    (comp (ref "P151")
      (value "WS2812B")
      (footprint "SMD LED WS2812B-1010RGBC")
      (description "Smart RGB-LED")
      (libsource (lib "Liv_Flo_Sign") (part "P-XL-1010RGBC-WS2812B"))
    )
    (comp (ref "P152")
      (value "WS2812B")
      (footprint "SMD LED WS2812B-1010RGBC")
      (description "Smart RGB-LED")
      (libsource (lib "Liv_Flo_Sign") (part "P-XL-1010RGBC-WS2812B"))
    )
    (comp (ref "P153")
      (value "WS2812B")
      (footprint "SMD LED WS2812B-1010RGBC")
      (description "Smart RGB-LED")
      (libsource (lib "Liv_Flo_Sign") (part "P-XL-1010RGBC-WS2812B"))
    )
    (comp (ref "P154")
      (value "WS2812B")
      (footprint "SMD LED WS2812B-1010RGBC")
      (description "Smart RGB-LED")
      (libsource (lib "Liv_Flo_Sign") (part "P-XL-1010RGBC-WS2812B"))
    )
    (comp (ref "P155")
      (value "WS2812B")
      (footprint "SMD LED WS2812B-1010RGBC")
      (description "Smart RGB-LED")
      (libsource (lib "Liv_Flo_Sign") (part "P-XL-1010RGBC-WS2812B"))
    )
    (comp (ref "P156")
      (value "WS2812B")
      (footprint "SMD LED WS2812B-1010RGBC")
      (description "Smart RGB-LED")
      (libsource (lib "Liv_Flo_Sign") (part "P-XL-1010RGBC-WS2812B"))
    )
    (comp (ref "P157")
      (value "WS2812B")
      (footprint "SMD LED WS2812B-1010RGBC")
      (description "Smart RGB-LED")
      (libsource (lib "Liv_Flo_Sign") (part "P-XL-1010RGBC-WS2812B"))
    )
    (comp (ref "P158")
      (value "WS2812B")
      (footprint "SMD LED WS2812B-1010RGBC")
      (description "Smart RGB-LED")
      (libsource (lib "Liv_Flo_Sign") (part "P-XL-1010RGBC-WS2812B"))
    )
    (comp (ref "P159")
      (value "WS2812B")
      (footprint "SMD LED WS2812B-1010RGBC")
      (description "Smart RGB-LED")
      (libsource (lib "Liv_Flo_Sign") (part "P-XL-1010RGBC-WS2812B"))
    )
    (comp (ref "P160")
      (value "WS2812B")
      (footprint "SMD LED WS2812B-1010RGBC")
      (description "Smart RGB-LED")
      (libsource (lib "Liv_Flo_Sign") (part "P-XL-1010RGBC-WS2812B"))
    )
    (comp (ref "P161")
      (value "WS2812B")
      (footprint "SMD LED WS2812B-1010RGBC")
      (description "Smart RGB-LED")
      (libsource (lib "Liv_Flo_Sign") (part "P-XL-1010RGBC-WS2812B"))
    )
    (comp (ref "P162")
      (value "WS2812B")
      (footprint "SMD LED WS2812B-1010RGBC")
      (description "Smart RGB-LED")
      (libsource (lib "Liv_Flo_Sign") (part "P-XL-1010RGBC-WS2812B"))
    )
    (comp (ref "P163")
      (value "WS2812B")
      (footprint "SMD LED WS2812B-1010RGBC")
      (description "Smart RGB-LED")
      (libsource (lib "Liv_Flo_Sign") (part "P-XL-1010RGBC-WS2812B"))
    )
    (comp (ref "P164")
      (value "WS2812B")
      (footprint "SMD LED WS2812B-1010RGBC")
      (description "Smart RGB-LED")
      (libsource (lib "Liv_Flo_Sign") (part "P-XL-1010RGBC-WS2812B"))
    )
    (comp (ref "P165")
      (value "WS2812B")
      (footprint "SMD LED WS2812B-1010RGBC")
      (description "Smart RGB-LED")
      (libsource (lib "Liv_Flo_Sign") (part "P-XL-1010RGBC-WS2812B"))
    )
    (comp (ref "P166")
      (value "WS2812B")
      (footprint "SMD LED WS2812B-1010RGBC")
      (description "Smart RGB-LED")
      (libsource (lib "Liv_Flo_Sign") (part "P-XL-1010RGBC-WS2812B"))
    )
    (comp (ref "P167")
      (value "WS2812B")
      (footprint "SMD LED WS2812B-1010RGBC")
      (description "Smart RGB-LED")
      (libsource (lib "Liv_Flo_Sign") (part "P-XL-1010RGBC-WS2812B"))
    )
    (comp (ref "P168")
      (value "WS2812B")
      (footprint "SMD LED WS2812B-1010RGBC")
      (description "Smart RGB-LED")
      (libsource (lib "Liv_Flo_Sign") (part "P-XL-1010RGBC-WS2812B"))
    )
    (comp (ref "P169")
      (value "WS2812B")
      (footprint "SMD LED WS2812B-1010RGBC")
      (description "Smart RGB-LED")
      (libsource (lib "Liv_Flo_Sign") (part "P-XL-1010RGBC-WS2812B"))
    )
    (comp (ref "P170")
      (value "WS2812B")
      (footprint "SMD LED WS2812B-1010RGBC")
      (description "Smart RGB-LED")
      (libsource (lib "Liv_Flo_Sign") (part "P-XL-1010RGBC-WS2812B"))
    )
    (comp (ref "P171")
      (value "WS2812B")
      (footprint "SMD LED WS2812B-1010RGBC")
      (description "Smart RGB-LED")
      (libsource (lib "Liv_Flo_Sign") (part "P-XL-1010RGBC-WS2812B"))
    )
    (comp (ref "P172")
      (value "WS2812B")
      (footprint "SMD LED WS2812B-1010RGBC")
      (description "Smart RGB-LED")
      (libsource (lib "Liv_Flo_Sign") (part "P-XL-1010RGBC-WS2812B"))
    )
    (comp (ref "P173")
      (value "WS2812B")
      (footprint "SMD LED WS2812B-1010RGBC")
      (description "Smart RGB-LED")
      (libsource (lib "Liv_Flo_Sign") (part "P-XL-1010RGBC-WS2812B"))
    )
    (comp (ref "P174")
      (value "WS2812B")
      (footprint "SMD LED WS2812B-1010RGBC")
      (description "Smart RGB-LED")
      (libsource (lib "Liv_Flo_Sign") (part "P-XL-1010RGBC-WS2812B"))
    )
    (comp (ref "P175")
      (value "WS2812B")
      (footprint "SMD LED WS2812B-1010RGBC")
      (description "Smart RGB-LED")
      (libsource (lib "Liv_Flo_Sign") (part "P-XL-1010RGBC-WS2812B"))
    )
    (comp (ref "P176")
      (value "WS2812B")
      (footprint "SMD LED WS2812B-1010RGBC")
      (description "Smart RGB-LED")
      (libsource (lib "Liv_Flo_Sign") (part "P-XL-1010RGBC-WS2812B"))
    )
    (comp (ref "P177")
      (value "WS2812B")
      (footprint "SMD LED WS2812B-1010RGBC")
      (description "Smart RGB-LED")
      (libsource (lib "Liv_Flo_Sign") (part "P-XL-1010RGBC-WS2812B"))
    )
    (comp (ref "P178")
      (value "WS2812B")
      (footprint "SMD LED WS2812B-1010RGBC")
      (description "Smart RGB-LED")
      (libsource (lib "Liv_Flo_Sign") (part "P-XL-1010RGBC-WS2812B"))
    )
    (comp (ref "P179")
      (value "WS2812B")
      (footprint "SMD LED WS2812B-1010RGBC")
      (description "Smart RGB-LED")
      (libsource (lib "Liv_Flo_Sign") (part "P-XL-1010RGBC-WS2812B"))
    )
    (comp (ref "P180")
      (value "WS2812B")
      (footprint "SMD LED WS2812B-1010RGBC")
      (description "Smart RGB-LED")
      (libsource (lib "Liv_Flo_Sign") (part "P-XL-1010RGBC-WS2812B"))
    )
    (comp (ref "P181")
      (value "WS2812B")
      (footprint "SMD LED WS2812B-1010RGBC")
      (description "Smart RGB-LED")
      (libsource (lib "Liv_Flo_Sign") (part "P-XL-1010RGBC-WS2812B"))
    )
    (comp (ref "P182")
      (value "WS2812B")
      (footprint "SMD LED WS2812B-1010RGBC")
      (description "Smart RGB-LED")
      (libsource (lib "Liv_Flo_Sign") (part "P-XL-1010RGBC-WS2812B"))
    )
    (comp (ref "P183")
      (value "WS2812B")
      (footprint "SMD LED WS2812B-1010RGBC")
      (description "Smart RGB-LED")
      (libsource (lib "Liv_Flo_Sign") (part "P-XL-1010RGBC-WS2812B"))
    )
    (comp (ref "P184")
      (value "WS2812B")
      (footprint "SMD LED WS2812B-1010RGBC")
      (description "Smart RGB-LED")
      (libsource (lib "Liv_Flo_Sign") (part "P-XL-1010RGBC-WS2812B"))
    )
    (comp (ref "P185")
      (value "WS2812B")
      (footprint "SMD LED WS2812B-1010RGBC")
      (description "Smart RGB-LED")
      (libsource (lib "Liv_Flo_Sign") (part "P-XL-1010RGBC-WS2812B"))
    )
    (comp (ref "P186")
      (value "WS2812B")
      (footprint "SMD LED WS2812B-1010RGBC")
      (description "Smart RGB-LED")
      (libsource (lib "Liv_Flo_Sign") (part "P-XL-1010RGBC-WS2812B"))
    )
    (comp (ref "P187")
      (value "WS2812B")
      (footprint "SMD LED WS2812B-1010RGBC")
      (description "Smart RGB-LED")
      (libsource (lib "Liv_Flo_Sign") (part "P-XL-1010RGBC-WS2812B"))
    )
    (comp (ref "P188")
      (value "WS2812B")
      (footprint "SMD LED WS2812B-1010RGBC")
      (description "Smart RGB-LED")
      (libsource (lib "Liv_Flo_Sign") (part "P-XL-1010RGBC-WS2812B"))
    )
    (comp (ref "P189")
      (value "WS2812B")
      (footprint "SMD LED WS2812B-1010RGBC")
      (description "Smart RGB-LED")
      (libsource (lib "Liv_Flo_Sign") (part "P-XL-1010RGBC-WS2812B"))
    )
    (comp (ref "P190")
      (value "WS2812B")
      (footprint "SMD LED WS2812B-1010RGBC")
      (description "Smart RGB-LED")
      (libsource (lib "Liv_Flo_Sign") (part "P-XL-1010RGBC-WS2812B"))
    )
    (comp (ref "P191")
      (value "WS2812B")
      (footprint "SMD LED WS2812B-1010RGBC")
      (description "Smart RGB-LED")
      (libsource (lib "Liv_Flo_Sign") (part "P-XL-1010RGBC-WS2812B"))
    )
    (comp (ref "P192")
      (value "WS2812B")
      (footprint "SMD LED WS2812B-1010RGBC")
      (description "Smart RGB-LED")
      (libsource (lib "Liv_Flo_Sign") (part "P-XL-1010RGBC-WS2812B"))
    )
    (comp (ref "P193")
      (value "WS2812B")
      (footprint "SMD LED WS2812B-1010RGBC")
      (description "Smart RGB-LED")
      (libsource (lib "Liv_Flo_Sign") (part "P-XL-1010RGBC-WS2812B"))
    )
    (comp (ref "P194")
      (value "WS2812B")
      (footprint "SMD LED WS2812B-1010RGBC")
      (description "Smart RGB-LED")
      (libsource (lib "Liv_Flo_Sign") (part "P-XL-1010RGBC-WS2812B"))
    )
    (comp (ref "P195")
      (value "WS2812B")
      (footprint "SMD LED WS2812B-1010RGBC")
      (description "Smart RGB-LED")
      (libsource (lib "Liv_Flo_Sign") (part "P-XL-1010RGBC-WS2812B"))
    )
    (comp (ref "P196")
      (value "WS2812B")
      (footprint "SMD LED WS2812B-1010RGBC")
      (description "Smart RGB-LED")
      (libsource (lib "Liv_Flo_Sign") (part "P-XL-1010RGBC-WS2812B"))
    )
    (comp (ref "P197")
      (value "WS2812B")
      (footprint "SMD LED WS2812B-1010RGBC")
      (description "Smart RGB-LED")
      (libsource (lib "Liv_Flo_Sign") (part "P-XL-1010RGBC-WS2812B"))
    )
    (comp (ref "P198")
      (value "WS2812B")
      (footprint "SMD LED WS2812B-1010RGBC")
      (description "Smart RGB-LED")
      (libsource (lib "Liv_Flo_Sign") (part "P-XL-1010RGBC-WS2812B"))
    )
    (comp (ref "P199")
      (value "WS2812B")
      (footprint "SMD LED WS2812B-1010RGBC")
      (description "Smart RGB-LED")
      (libsource (lib "Liv_Flo_Sign") (part "P-XL-1010RGBC-WS2812B"))
    )
    (comp (ref "P200")
      (value "WS2812B")
      (footprint "SMD LED WS2812B-1010RGBC")
      (description "Smart RGB-LED")
      (libsource (lib "Liv_Flo_Sign") (part "P-XL-1010RGBC-WS2812B"))
    )
    (comp (ref "P201")
      (value "WS2812B")
      (footprint "SMD LED WS2812B-1010RGBC")
      (description "Smart RGB-LED")
      (libsource (lib "Liv_Flo_Sign") (part "P-XL-1010RGBC-WS2812B"))
    )
    (comp (ref "P202")
      (value "WS2812B")
      (footprint "SMD LED WS2812B-1010RGBC")
      (description "Smart RGB-LED")
      (libsource (lib "Liv_Flo_Sign") (part "P-XL-1010RGBC-WS2812B"))
    )
    (comp (ref "P203")
      (value "WS2812B")
      (footprint "SMD LED WS2812B-1010RGBC")
      (description "Smart RGB-LED")
      (libsource (lib "Liv_Flo_Sign") (part "P-XL-1010RGBC-WS2812B"))
    )
    (comp (ref "P204")
      (value "WS2812B")
      (footprint "SMD LED WS2812B-1010RGBC")
      (description "Smart RGB-LED")
      (libsource (lib "Liv_Flo_Sign") (part "P-XL-1010RGBC-WS2812B"))
    )
    (comp (ref "P205")
      (value "WS2812B")
      (footprint "SMD LED WS2812B-1010RGBC")
      (description "Smart RGB-LED")
      (libsource (lib "Liv_Flo_Sign") (part "P-XL-1010RGBC-WS2812B"))
    )
    (comp (ref "P206")
      (value "WS2812B")
      (footprint "SMD LED WS2812B-1010RGBC")
      (description "Smart RGB-LED")
      (libsource (lib "Liv_Flo_Sign") (part "P-XL-1010RGBC-WS2812B"))
    )
    (comp (ref "P207")
      (value "WS2812B")
      (footprint "SMD LED WS2812B-1010RGBC")
      (description "Smart RGB-LED")
      (libsource (lib "Liv_Flo_Sign") (part "P-XL-1010RGBC-WS2812B"))
    )
    (comp (ref "P208")
      (value "WS2812B")
      (footprint "SMD LED WS2812B-1010RGBC")
      (description "Smart RGB-LED")
      (libsource (lib "Liv_Flo_Sign") (part "P-XL-1010RGBC-WS2812B"))
    )
    (comp (ref "P209")
      (value "WS2812B")
      (footprint "SMD LED WS2812B-1010RGBC")
      (description "Smart RGB-LED")
      (libsource (lib "Liv_Flo_Sign") (part "P-XL-1010RGBC-WS2812B"))
    )
    (comp (ref "P210")
      (value "WS2812B")
      (footprint "SMD LED WS2812B-1010RGBC")
      (description "Smart RGB-LED")
      (libsource (lib "Liv_Flo_Sign") (part "P-XL-1010RGBC-WS2812B"))
    )
    (comp (ref "P211")
      (value "WS2812B")
      (footprint "SMD LED WS2812B-1010RGBC")
      (description "Smart RGB-LED")
      (libsource (lib "Liv_Flo_Sign") (part "P-XL-1010RGBC-WS2812B"))
    )
    (comp (ref "P212")
      (value "WS2812B")
      (footprint "SMD LED WS2812B-1010RGBC")
      (description "Smart RGB-LED")
      (libsource (lib "Liv_Flo_Sign") (part "P-XL-1010RGBC-WS2812B"))
    )
    (comp (ref "P213")
      (value "WS2812B")
      (footprint "SMD LED WS2812B-1010RGBC")
      (description "Smart RGB-LED")
      (libsource (lib "Liv_Flo_Sign") (part "P-XL-1010RGBC-WS2812B"))
    )
    (comp (ref "P214")
      (value "WS2812B")
      (footprint "SMD LED WS2812B-1010RGBC")
      (description "Smart RGB-LED")
      (libsource (lib "Liv_Flo_Sign") (part "P-XL-1010RGBC-WS2812B"))
    )
    (comp (ref "P215")
      (value "WS2812B")
      (footprint "SMD LED WS2812B-1010RGBC")
      (description "Smart RGB-LED")
      (libsource (lib "Liv_Flo_Sign") (part "P-XL-1010RGBC-WS2812B"))
    )
    (comp (ref "P216")
      (value "WS2812B")
      (footprint "SMD LED WS2812B-1010RGBC")
      (description "Smart RGB-LED")
      (libsource (lib "Liv_Flo_Sign") (part "P-XL-1010RGBC-WS2812B"))
    )
    (comp (ref "P217")
      (value "WS2812B")
      (footprint "SMD LED WS2812B-1010RGBC")
      (description "Smart RGB-LED")
      (libsource (lib "Liv_Flo_Sign") (part "P-XL-1010RGBC-WS2812B"))
    )
    (comp (ref "P218")
      (value "WS2812B")
      (footprint "SMD LED WS2812B-1010RGBC")
      (description "Smart RGB-LED")
      (libsource (lib "Liv_Flo_Sign") (part "P-XL-1010RGBC-WS2812B"))
    )
    (comp (ref "P219")
      (value "WS2812B")
      (footprint "SMD LED WS2812B-1010RGBC")
      (description "Smart RGB-LED")
      (libsource (lib "Liv_Flo_Sign") (part "P-XL-1010RGBC-WS2812B"))
    )
    (comp (ref "P220")
      (value "WS2812B")
      (footprint "SMD LED WS2812B-1010RGBC")
      (description "Smart RGB-LED")
      (libsource (lib "Liv_Flo_Sign") (part "P-XL-1010RGBC-WS2812B"))
    )
    (comp (ref "P221")
      (value "WS2812B")
      (footprint "SMD LED WS2812B-1010RGBC")
      (description "Smart RGB-LED")
      (libsource (lib "Liv_Flo_Sign") (part "P-XL-1010RGBC-WS2812B"))
    )
    (comp (ref "P222")
      (value "WS2812B")
      (footprint "SMD LED WS2812B-1010RGBC")
      (description "Smart RGB-LED")
      (libsource (lib "Liv_Flo_Sign") (part "P-XL-1010RGBC-WS2812B"))
    )
    (comp (ref "P223")
      (value "WS2812B")
      (footprint "SMD LED WS2812B-1010RGBC")
      (description "Smart RGB-LED")
      (libsource (lib "Liv_Flo_Sign") (part "P-XL-1010RGBC-WS2812B"))
    )
    (comp (ref "P224")
      (value "WS2812B")
      (footprint "SMD LED WS2812B-1010RGBC")
      (description "Smart RGB-LED")
      (libsource (lib "Liv_Flo_Sign") (part "P-XL-1010RGBC-WS2812B"))
    )
    (comp (ref "P225")
      (value "WS2812B")
      (footprint "SMD LED WS2812B-1010RGBC")
      (description "Smart RGB-LED")
      (libsource (lib "Liv_Flo_Sign") (part "P-XL-1010RGBC-WS2812B"))
    )
    (comp (ref "P226")
      (value "WS2812B")
      (footprint "SMD LED WS2812B-1010RGBC")
      (description "Smart RGB-LED")
      (libsource (lib "Liv_Flo_Sign") (part "P-XL-1010RGBC-WS2812B"))
    )
    (comp (ref "P227")
      (value "WS2812B")
      (footprint "SMD LED WS2812B-1010RGBC")
      (description "Smart RGB-LED")
      (libsource (lib "Liv_Flo_Sign") (part "P-XL-1010RGBC-WS2812B"))
    )
    (comp (ref "P228")
      (value "WS2812B")
      (footprint "SMD LED WS2812B-1010RGBC")
      (description "Smart RGB-LED")
      (libsource (lib "Liv_Flo_Sign") (part "P-XL-1010RGBC-WS2812B"))
    )
    (comp (ref "P229")
      (value "WS2812B")
      (footprint "SMD LED WS2812B-1010RGBC")
      (description "Smart RGB-LED")
      (libsource (lib "Liv_Flo_Sign") (part "P-XL-1010RGBC-WS2812B"))
    )
    (comp (ref "P230")
      (value "WS2812B")
      (footprint "SMD LED WS2812B-1010RGBC")
      (description "Smart RGB-LED")
      (libsource (lib "Liv_Flo_Sign") (part "P-XL-1010RGBC-WS2812B"))
    )
    (comp (ref "P231")
      (value "WS2812B")
      (footprint "SMD LED WS2812B-1010RGBC")
      (description "Smart RGB-LED")
      (libsource (lib "Liv_Flo_Sign") (part "P-XL-1010RGBC-WS2812B"))
    )
    (comp (ref "P232")
      (value "WS2812B")
      (footprint "SMD LED WS2812B-1010RGBC")
      (description "Smart RGB-LED")
      (libsource (lib "Liv_Flo_Sign") (part "P-XL-1010RGBC-WS2812B"))
    )
    (comp (ref "P233")
      (value "WS2812B")
      (footprint "SMD LED WS2812B-1010RGBC")
      (description "Smart RGB-LED")
      (libsource (lib "Liv_Flo_Sign") (part "P-XL-1010RGBC-WS2812B"))
    )
    (comp (ref "P234")
      (value "WS2812B")
      (footprint "SMD LED WS2812B-1010RGBC")
      (description "Smart RGB-LED")
      (libsource (lib "Liv_Flo_Sign") (part "P-XL-1010RGBC-WS2812B"))
    )
    (comp (ref "P235")
      (value "WS2812B")
      (footprint "SMD LED WS2812B-1010RGBC")
      (description "Smart RGB-LED")
      (libsource (lib "Liv_Flo_Sign") (part "P-XL-1010RGBC-WS2812B"))
    )
    (comp (ref "P236")
      (value "WS2812B")
      (footprint "SMD LED WS2812B-1010RGBC")
      (description "Smart RGB-LED")
      (libsource (lib "Liv_Flo_Sign") (part "P-XL-1010RGBC-WS2812B"))
    )
    (comp (ref "P237")
      (value "WS2812B")
      (footprint "SMD LED WS2812B-1010RGBC")
      (description "Smart RGB-LED")
      (libsource (lib "Liv_Flo_Sign") (part "P-XL-1010RGBC-WS2812B"))
    )
    (comp (ref "P238")
      (value "WS2812B")
      (footprint "SMD LED WS2812B-1010RGBC")
      (description "Smart RGB-LED")
      (libsource (lib "Liv_Flo_Sign") (part "P-XL-1010RGBC-WS2812B"))
    )
    (comp (ref "P239")
      (value "WS2812B")
      (footprint "SMD LED WS2812B-1010RGBC")
      (description "Smart RGB-LED")
      (libsource (lib "Liv_Flo_Sign") (part "P-XL-1010RGBC-WS2812B"))
    )
    (comp (ref "P240")
      (value "WS2812B")
      (footprint "SMD LED WS2812B-1010RGBC")
      (description "Smart RGB-LED")
      (libsource (lib "Liv_Flo_Sign") (part "P-XL-1010RGBC-WS2812B"))
    )
    (comp (ref "P241")
      (value "WS2812B")
      (footprint "SMD LED WS2812B-1010RGBC")
      (description "Smart RGB-LED")
      (libsource (lib "Liv_Flo_Sign") (part "P-XL-1010RGBC-WS2812B"))
    )
    (comp (ref "P242")
      (value "WS2812B")
      (footprint "SMD LED WS2812B-1010RGBC")
      (description "Smart RGB-LED")
      (libsource (lib "Liv_Flo_Sign") (part "P-XL-1010RGBC-WS2812B"))
    )
    (comp (ref "P243")
      (value "WS2812B")
      (footprint "SMD LED WS2812B-1010RGBC")
      (description "Smart RGB-LED")
      (libsource (lib "Liv_Flo_Sign") (part "P-XL-1010RGBC-WS2812B"))
    )
    (comp (ref "P244")
      (value "WS2812B")
      (footprint "SMD LED WS2812B-1010RGBC")
      (description "Smart RGB-LED")
      (libsource (lib "Liv_Flo_Sign") (part "P-XL-1010RGBC-WS2812B"))
    )
    (comp (ref "P245")
      (value "WS2812B")
      (footprint "SMD LED WS2812B-1010RGBC")
      (description "Smart RGB-LED")
      (libsource (lib "Liv_Flo_Sign") (part "P-XL-1010RGBC-WS2812B"))
    )
    (comp (ref "P246")
      (value "WS2812B")
      (footprint "SMD LED WS2812B-1010RGBC")
      (description "Smart RGB-LED")
      (libsource (lib "Liv_Flo_Sign") (part "P-XL-1010RGBC-WS2812B"))
    )
    (comp (ref "P247")
      (value "WS2812B")
      (footprint "SMD LED WS2812B-1010RGBC")
      (description "Smart RGB-LED")
      (libsource (lib "Liv_Flo_Sign") (part "P-XL-1010RGBC-WS2812B"))
    )
    (comp (ref "P248")
      (value "WS2812B")
      (footprint "SMD LED WS2812B-1010RGBC")
      (description "Smart RGB-LED")
      (libsource (lib "Liv_Flo_Sign") (part "P-XL-1010RGBC-WS2812B"))
    )
    (comp (ref "P249")
      (value "WS2812B")
      (footprint "SMD LED WS2812B-1010RGBC")
      (description "Smart RGB-LED")
      (libsource (lib "Liv_Flo_Sign") (part "P-XL-1010RGBC-WS2812B"))
    )
    (comp (ref "P250")
      (value "WS2812B")
      (footprint "SMD LED WS2812B-1010RGBC")
      (description "Smart RGB-LED")
      (libsource (lib "Liv_Flo_Sign") (part "P-XL-1010RGBC-WS2812B"))
    )
    (comp (ref "P251")
      (value "WS2812B")
      (footprint "SMD LED WS2812B-1010RGBC")
      (description "Smart RGB-LED")
      (libsource (lib "Liv_Flo_Sign") (part "P-XL-1010RGBC-WS2812B"))
    )
    (comp (ref "P252")
      (value "WS2812B")
      (footprint "SMD LED WS2812B-1010RGBC")
      (description "Smart RGB-LED")
      (libsource (lib "Liv_Flo_Sign") (part "P-XL-1010RGBC-WS2812B"))
    )
    (comp (ref "P253")
      (value "WS2812B")
      (footprint "SMD LED WS2812B-1010RGBC")
      (description "Smart RGB-LED")
      (libsource (lib "Liv_Flo_Sign") (part "P-XL-1010RGBC-WS2812B"))
    )
    (comp (ref "P254")
      (value "WS2812B")
      (footprint "SMD LED WS2812B-1010RGBC")
      (description "Smart RGB-LED")
      (libsource (lib "Liv_Flo_Sign") (part "P-XL-1010RGBC-WS2812B"))
    )
    (comp (ref "P255")
      (value "WS2812B")
      (footprint "SMD LED WS2812B-1010RGBC")
      (description "Smart RGB-LED")
      (libsource (lib "Liv_Flo_Sign") (part "P-XL-1010RGBC-WS2812B"))
    )
    (comp (ref "P256")
      (value "WS2812B")
      (footprint "SMD LED WS2812B-1010RGBC")
      (description "Smart RGB-LED")
      (libsource (lib "Liv_Flo_Sign") (part "P-XL-1010RGBC-WS2812B"))
    )
    (comp (ref "P257")
      (value "WS2812B")
      (footprint "SMD LED WS2812B-1010RGBC")
      (description "Smart RGB-LED")
      (libsource (lib "Liv_Flo_Sign") (part "P-XL-1010RGBC-WS2812B"))
    )
    (comp (ref "P258")
      (value "WS2812B")
      (footprint "SMD LED WS2812B-1010RGBC")
      (description "Smart RGB-LED")
      (libsource (lib "Liv_Flo_Sign") (part "P-XL-1010RGBC-WS2812B"))
    )
    (comp (ref "P259")
      (value "WS2812B")
      (footprint "SMD LED WS2812B-1010RGBC")
      (description "Smart RGB-LED")
      (libsource (lib "Liv_Flo_Sign") (part "P-XL-1010RGBC-WS2812B"))
    )
    (comp (ref "P260")
      (value "WS2812B")
      (footprint "SMD LED WS2812B-1010RGBC")
      (description "Smart RGB-LED")
      (libsource (lib "Liv_Flo_Sign") (part "P-XL-1010RGBC-WS2812B"))
    )
    (comp (ref "P261")
      (value "WS2812B")
      (footprint "SMD LED WS2812B-1010RGBC")
      (description "Smart RGB-LED")
      (libsource (lib "Liv_Flo_Sign") (part "P-XL-1010RGBC-WS2812B"))
    )
    (comp (ref "P262")
      (value "WS2812B")
      (footprint "SMD LED WS2812B-1010RGBC")
      (description "Smart RGB-LED")
      (libsource (lib "Liv_Flo_Sign") (part "P-XL-1010RGBC-WS2812B"))
    )
    (comp (ref "P263")
      (value "WS2812B")
      (footprint "SMD LED WS2812B-1010RGBC")
      (description "Smart RGB-LED")
      (libsource (lib "Liv_Flo_Sign") (part "P-XL-1010RGBC-WS2812B"))
    )
    (comp (ref "P264")
      (value "WS2812B")
      (footprint "SMD LED WS2812B-1010RGBC")
      (description "Smart RGB-LED")
      (libsource (lib "Liv_Flo_Sign") (part "P-XL-1010RGBC-WS2812B"))
    )
    (comp (ref "P265")
      (value "WS2812B")
      (footprint "SMD LED WS2812B-1010RGBC")
      (description "Smart RGB-LED")
      (libsource (lib "Liv_Flo_Sign") (part "P-XL-1010RGBC-WS2812B"))
    )
    (comp (ref "P266")
      (value "WS2812B")
      (footprint "SMD LED WS2812B-1010RGBC")
      (description "Smart RGB-LED")
      (libsource (lib "Liv_Flo_Sign") (part "P-XL-1010RGBC-WS2812B"))
    )
    (comp (ref "P267")
      (value "WS2812B")
      (footprint "SMD LED WS2812B-1010RGBC")
      (description "Smart RGB-LED")
      (libsource (lib "Liv_Flo_Sign") (part "P-XL-1010RGBC-WS2812B"))
    )
    (comp (ref "P268")
      (value "WS2812B")
      (footprint "SMD LED WS2812B-1010RGBC")
      (description "Smart RGB-LED")
      (libsource (lib "Liv_Flo_Sign") (part "P-XL-1010RGBC-WS2812B"))
    )
    (comp (ref "P269")
      (value "WS2812B")
      (footprint "SMD LED WS2812B-1010RGBC")
      (description "Smart RGB-LED")
      (libsource (lib "Liv_Flo_Sign") (part "P-XL-1010RGBC-WS2812B"))
    )
    (comp (ref "P270")
      (value "WS2812B")
      (footprint "SMD LED WS2812B-1010RGBC")
      (description "Smart RGB-LED")
      (libsource (lib "Liv_Flo_Sign") (part "P-XL-1010RGBC-WS2812B"))
    )
    (comp (ref "P271")
      (value "WS2812B")
      (footprint "SMD LED WS2812B-1010RGBC")
      (description "Smart RGB-LED")
      (libsource (lib "Liv_Flo_Sign") (part "P-XL-1010RGBC-WS2812B"))
    )
    (comp (ref "P272")
      (value "WS2812B")
      (footprint "SMD LED WS2812B-1010RGBC")
      (description "Smart RGB-LED")
      (libsource (lib "Liv_Flo_Sign") (part "P-XL-1010RGBC-WS2812B"))
    )
    (comp (ref "P273")
      (value "WS2812B")
      (footprint "SMD LED WS2812B-1010RGBC")
      (description "Smart RGB-LED")
      (libsource (lib "Liv_Flo_Sign") (part "P-XL-1010RGBC-WS2812B"))
    )
    (comp (ref "P274")
      (value "WS2812B")
      (footprint "SMD LED WS2812B-1010RGBC")
      (description "Smart RGB-LED")
      (libsource (lib "Liv_Flo_Sign") (part "P-XL-1010RGBC-WS2812B"))
    )
    (comp (ref "P275")
      (value "WS2812B")
      (footprint "SMD LED WS2812B-1010RGBC")
      (description "Smart RGB-LED")
      (libsource (lib "Liv_Flo_Sign") (part "P-XL-1010RGBC-WS2812B"))
    )
    (comp (ref "P276")
      (value "WS2812B")
      (footprint "SMD LED WS2812B-1010RGBC")
      (description "Smart RGB-LED")
      (libsource (lib "Liv_Flo_Sign") (part "P-XL-1010RGBC-WS2812B"))
    )
    (comp (ref "P277")
      (value "WS2812B")
      (footprint "SMD LED WS2812B-1010RGBC")
      (description "Smart RGB-LED")
      (libsource (lib "Liv_Flo_Sign") (part "P-XL-1010RGBC-WS2812B"))
    )
    (comp (ref "P278")
      (value "WS2812B")
      (footprint "SMD LED WS2812B-1010RGBC")
      (description "Smart RGB-LED")
      (libsource (lib "Liv_Flo_Sign") (part "P-XL-1010RGBC-WS2812B"))
    )
    (comp (ref "P279")
      (value "WS2812B")
      (footprint "SMD LED WS2812B-1010RGBC")
      (description "Smart RGB-LED")
      (libsource (lib "Liv_Flo_Sign") (part "P-XL-1010RGBC-WS2812B"))
    )
    (comp (ref "P280")
      (value "WS2812B")
      (footprint "SMD LED WS2812B-1010RGBC")
      (description "Smart RGB-LED")
      (libsource (lib "Liv_Flo_Sign") (part "P-XL-1010RGBC-WS2812B"))
    )
    (comp (ref "P281")
      (value "WS2812B")
      (footprint "SMD LED WS2812B-1010RGBC")
      (description "Smart RGB-LED")
      (libsource (lib "Liv_Flo_Sign") (part "P-XL-1010RGBC-WS2812B"))
    )
    (comp (ref "P282")
      (value "WS2812B")
      (footprint "SMD LED WS2812B-1010RGBC")
      (description "Smart RGB-LED")
      (libsource (lib "Liv_Flo_Sign") (part "P-XL-1010RGBC-WS2812B"))
    )
    (comp (ref "P283")
      (value "WS2812B")
      (footprint "SMD LED WS2812B-1010RGBC")
      (description "Smart RGB-LED")
      (libsource (lib "Liv_Flo_Sign") (part "P-XL-1010RGBC-WS2812B"))
    )
    (comp (ref "P284")
      (value "WS2812B")
      (footprint "SMD LED WS2812B-1010RGBC")
      (description "Smart RGB-LED")
      (libsource (lib "Liv_Flo_Sign") (part "P-XL-1010RGBC-WS2812B"))
    )
    (comp (ref "P285")
      (value "WS2812B")
      (footprint "SMD LED WS2812B-1010RGBC")
      (description "Smart RGB-LED")
      (libsource (lib "Liv_Flo_Sign") (part "P-XL-1010RGBC-WS2812B"))
    )
    (comp (ref "P286")
      (value "WS2812B")
      (footprint "SMD LED WS2812B-1010RGBC")
      (description "Smart RGB-LED")
      (libsource (lib "Liv_Flo_Sign") (part "P-XL-1010RGBC-WS2812B"))
    )
    (comp (ref "P287")
      (value "WS2812B")
      (footprint "SMD LED WS2812B-1010RGBC")
      (description "Smart RGB-LED")
      (libsource (lib "Liv_Flo_Sign") (part "P-XL-1010RGBC-WS2812B"))
    )
    (comp (ref "P288")
      (value "WS2812B")
      (footprint "SMD LED WS2812B-1010RGBC")
      (description "Smart RGB-LED")
      (libsource (lib "Liv_Flo_Sign") (part "P-XL-1010RGBC-WS2812B"))
    )
    (comp (ref "P289")
      (value "WS2812B")
      (footprint "SMD LED WS2812B-1010RGBC")
      (description "Smart RGB-LED")
      (libsource (lib "Liv_Flo_Sign") (part "P-XL-1010RGBC-WS2812B"))
    )
    (comp (ref "P290")
      (value "WS2812B")
      (footprint "SMD LED WS2812B-1010RGBC")
      (description "Smart RGB-LED")
      (libsource (lib "Liv_Flo_Sign") (part "P-XL-1010RGBC-WS2812B"))
    )
    (comp (ref "P291")
      (value "WS2812B")
      (footprint "SMD LED WS2812B-1010RGBC")
      (description "Smart RGB-LED")
      (libsource (lib "Liv_Flo_Sign") (part "P-XL-1010RGBC-WS2812B"))
    )
    (comp (ref "P292")
      (value "WS2812B")
      (footprint "SMD LED WS2812B-1010RGBC")
      (description "Smart RGB-LED")
      (libsource (lib "Liv_Flo_Sign") (part "P-XL-1010RGBC-WS2812B"))
    )
    (comp (ref "P293")
      (value "WS2812B")
      (footprint "SMD LED WS2812B-1010RGBC")
      (description "Smart RGB-LED")
      (libsource (lib "Liv_Flo_Sign") (part "P-XL-1010RGBC-WS2812B"))
    )
    (comp (ref "P294")
      (value "WS2812B")
      (footprint "SMD LED WS2812B-1010RGBC")
      (description "Smart RGB-LED")
      (libsource (lib "Liv_Flo_Sign") (part "P-XL-1010RGBC-WS2812B"))
    )
    (comp (ref "P295")
      (value "WS2812B")
      (footprint "SMD LED WS2812B-1010RGBC")
      (description "Smart RGB-LED")
      (libsource (lib "Liv_Flo_Sign") (part "P-XL-1010RGBC-WS2812B"))
    )
    (comp (ref "P296")
      (value "WS2812B")
      (footprint "SMD LED WS2812B-1010RGBC")
      (description "Smart RGB-LED")
      (libsource (lib "Liv_Flo_Sign") (part "P-XL-1010RGBC-WS2812B"))
    )
    (comp (ref "P297")
      (value "WS2812B")
      (footprint "SMD LED WS2812B-1010RGBC")
      (description "Smart RGB-LED")
      (libsource (lib "Liv_Flo_Sign") (part "P-XL-1010RGBC-WS2812B"))
    )
    (comp (ref "P298")
      (value "WS2812B")
      (footprint "SMD LED WS2812B-1010RGBC")
      (description "Smart RGB-LED")
      (libsource (lib "Liv_Flo_Sign") (part "P-XL-1010RGBC-WS2812B"))
    )
    (comp (ref "P299")
      (value "WS2812B")
      (footprint "SMD LED WS2812B-1010RGBC")
      (description "Smart RGB-LED")
      (libsource (lib "Liv_Flo_Sign") (part "P-XL-1010RGBC-WS2812B"))
    )
    (comp (ref "P300")
      (value "WS2812B")
      (footprint "SMD LED WS2812B-1010RGBC")
      (description "Smart RGB-LED")
      (libsource (lib "Liv_Flo_Sign") (part "P-XL-1010RGBC-WS2812B"))
    )
    (comp (ref "P301")
      (value "WS2812B")
      (footprint "SMD LED WS2812B-1010RGBC")
      (description "Smart RGB-LED")
      (libsource (lib "Liv_Flo_Sign") (part "P-XL-1010RGBC-WS2812B"))
    )
    (comp (ref "P302")
      (value "WS2812B")
      (footprint "SMD LED WS2812B-1010RGBC")
      (description "Smart RGB-LED")
      (libsource (lib "Liv_Flo_Sign") (part "P-XL-1010RGBC-WS2812B"))
    )
    (comp (ref "P303")
      (value "WS2812B")
      (footprint "SMD LED WS2812B-1010RGBC")
      (description "Smart RGB-LED")
      (libsource (lib "Liv_Flo_Sign") (part "P-XL-1010RGBC-WS2812B"))
    )
    (comp (ref "P304")
      (value "WS2812B")
      (footprint "SMD LED WS2812B-1010RGBC")
      (description "Smart RGB-LED")
      (libsource (lib "Liv_Flo_Sign") (part "P-XL-1010RGBC-WS2812B"))
    )
    (comp (ref "P305")
      (value "WS2812B")
      (footprint "SMD LED WS2812B-1010RGBC")
      (description "Smart RGB-LED")
      (libsource (lib "Liv_Flo_Sign") (part "P-XL-1010RGBC-WS2812B"))
    )
    (comp (ref "P306")
      (value "WS2812B")
      (footprint "SMD LED WS2812B-1010RGBC")
      (description "Smart RGB-LED")
      (libsource (lib "Liv_Flo_Sign") (part "P-XL-1010RGBC-WS2812B"))
    )
    (comp (ref "P307")
      (value "WS2812B")
      (footprint "SMD LED WS2812B-1010RGBC")
      (description "Smart RGB-LED")
      (libsource (lib "Liv_Flo_Sign") (part "P-XL-1010RGBC-WS2812B"))
    )
    (comp (ref "P308")
      (value "WS2812B")
      (footprint "SMD LED WS2812B-1010RGBC")
      (description "Smart RGB-LED")
      (libsource (lib "Liv_Flo_Sign") (part "P-XL-1010RGBC-WS2812B"))
    )
    (comp (ref "P309")
      (value "WS2812B")
      (footprint "SMD LED WS2812B-1010RGBC")
      (description "Smart RGB-LED")
      (libsource (lib "Liv_Flo_Sign") (part "P-XL-1010RGBC-WS2812B"))
    )
    (comp (ref "P310")
      (value "WS2812B")
      (footprint "SMD LED WS2812B-1010RGBC")
      (description "Smart RGB-LED")
      (libsource (lib "Liv_Flo_Sign") (part "P-XL-1010RGBC-WS2812B"))
    )
    (comp (ref "P311")
      (value "WS2812B")
      (footprint "SMD LED WS2812B-1010RGBC")
      (description "Smart RGB-LED")
      (libsource (lib "Liv_Flo_Sign") (part "P-XL-1010RGBC-WS2812B"))
    )
    (comp (ref "P312")
      (value "WS2812B")
      (footprint "SMD LED WS2812B-1010RGBC")
      (description "Smart RGB-LED")
      (libsource (lib "Liv_Flo_Sign") (part "P-XL-1010RGBC-WS2812B"))
    )
    (comp (ref "P313")
      (value "WS2812B")
      (footprint "SMD LED WS2812B-1010RGBC")
      (description "Smart RGB-LED")
      (libsource (lib "Liv_Flo_Sign") (part "P-XL-1010RGBC-WS2812B"))
    )
    (comp (ref "P314")
      (value "WS2812B")
      (footprint "SMD LED WS2812B-1010RGBC")
      (description "Smart RGB-LED")
      (libsource (lib "Liv_Flo_Sign") (part "P-XL-1010RGBC-WS2812B"))
    )
    (comp (ref "P315")
      (value "WS2812B")
      (footprint "SMD LED WS2812B-1010RGBC")
      (description "Smart RGB-LED")
      (libsource (lib "Liv_Flo_Sign") (part "P-XL-1010RGBC-WS2812B"))
    )
    (comp (ref "P316")
      (value "WS2812B")
      (footprint "SMD LED WS2812B-1010RGBC")
      (description "Smart RGB-LED")
      (libsource (lib "Liv_Flo_Sign") (part "P-XL-1010RGBC-WS2812B"))
    )
    (comp (ref "P317")
      (value "WS2812B")
      (footprint "SMD LED WS2812B-1010RGBC")
      (description "Smart RGB-LED")
      (libsource (lib "Liv_Flo_Sign") (part "P-XL-1010RGBC-WS2812B"))
    )
    (comp (ref "P318")
      (value "WS2812B")
      (footprint "SMD LED WS2812B-1010RGBC")
      (description "Smart RGB-LED")
      (libsource (lib "Liv_Flo_Sign") (part "P-XL-1010RGBC-WS2812B"))
    )
    (comp (ref "P319")
      (value "WS2812B")
      (footprint "SMD LED WS2812B-1010RGBC")
      (description "Smart RGB-LED")
      (libsource (lib "Liv_Flo_Sign") (part "P-XL-1010RGBC-WS2812B"))
    )
    (comp (ref "P320")
      (value "WS2812B")
      (footprint "SMD LED WS2812B-1010RGBC")
      (description "Smart RGB-LED")
      (libsource (lib "Liv_Flo_Sign") (part "P-XL-1010RGBC-WS2812B"))
    )
    (comp (ref "P321")
      (value "WS2812B")
      (footprint "SMD LED WS2812B-1010RGBC")
      (description "Smart RGB-LED")
      (libsource (lib "Liv_Flo_Sign") (part "P-XL-1010RGBC-WS2812B"))
    )
    (comp (ref "P322")
      (value "WS2812B")
      (footprint "SMD LED WS2812B-1010RGBC")
      (description "Smart RGB-LED")
      (libsource (lib "Liv_Flo_Sign") (part "P-XL-1010RGBC-WS2812B"))
    )
    (comp (ref "P323")
      (value "WS2812B")
      (footprint "SMD LED WS2812B-1010RGBC")
      (description "Smart RGB-LED")
      (libsource (lib "Liv_Flo_Sign") (part "P-XL-1010RGBC-WS2812B"))
    )
    (comp (ref "P324")
      (value "WS2812B")
      (footprint "SMD LED WS2812B-1010RGBC")
      (description "Smart RGB-LED")
      (libsource (lib "Liv_Flo_Sign") (part "P-XL-1010RGBC-WS2812B"))
    )
    (comp (ref "P325")
      (value "WS2812B")
      (footprint "SMD LED WS2812B-1010RGBC")
      (description "Smart RGB-LED")
      (libsource (lib "Liv_Flo_Sign") (part "P-XL-1010RGBC-WS2812B"))
    )
    (comp (ref "P326")
      (value "WS2812B")
      (footprint "SMD LED WS2812B-1010RGBC")
      (description "Smart RGB-LED")
      (libsource (lib "Liv_Flo_Sign") (part "P-XL-1010RGBC-WS2812B"))
    )
    (comp (ref "P327")
      (value "WS2812B")
      (footprint "SMD LED WS2812B-1010RGBC")
      (description "Smart RGB-LED")
      (libsource (lib "Liv_Flo_Sign") (part "P-XL-1010RGBC-WS2812B"))
    )
    (comp (ref "P328")
      (value "WS2812B")
      (footprint "SMD LED WS2812B-1010RGBC")
      (description "Smart RGB-LED")
      (libsource (lib "Liv_Flo_Sign") (part "P-XL-1010RGBC-WS2812B"))
    )
    (comp (ref "P329")
      (value "WS2812B")
      (footprint "SMD LED WS2812B-1010RGBC")
      (description "Smart RGB-LED")
      (libsource (lib "Liv_Flo_Sign") (part "P-XL-1010RGBC-WS2812B"))
    )
    (comp (ref "P330")
      (value "WS2812B")
      (footprint "SMD LED WS2812B-1010RGBC")
      (description "Smart RGB-LED")
      (libsource (lib "Liv_Flo_Sign") (part "P-XL-1010RGBC-WS2812B"))
    )
    (comp (ref "P331")
      (value "WS2812B")
      (footprint "SMD LED WS2812B-1010RGBC")
      (description "Smart RGB-LED")
      (libsource (lib "Liv_Flo_Sign") (part "P-XL-1010RGBC-WS2812B"))
    )
    (comp (ref "P332")
      (value "WS2812B")
      (footprint "SMD LED WS2812B-1010RGBC")
      (description "Smart RGB-LED")
      (libsource (lib "Liv_Flo_Sign") (part "P-XL-1010RGBC-WS2812B"))
    )
    (comp (ref "P333")
      (value "WS2812B")
      (footprint "SMD LED WS2812B-1010RGBC")
      (description "Smart RGB-LED")
      (libsource (lib "Liv_Flo_Sign") (part "P-XL-1010RGBC-WS2812B"))
    )
    (comp (ref "P334")
      (value "WS2812B")
      (footprint "SMD LED WS2812B-1010RGBC")
      (description "Smart RGB-LED")
      (libsource (lib "Liv_Flo_Sign") (part "P-XL-1010RGBC-WS2812B"))
    )
    (comp (ref "P335")
      (value "WS2812B")
      (footprint "SMD LED WS2812B-1010RGBC")
      (description "Smart RGB-LED")
      (libsource (lib "Liv_Flo_Sign") (part "P-XL-1010RGBC-WS2812B"))
    )
    (comp (ref "P336")
      (value "WS2812B")
      (footprint "SMD LED WS2812B-1010RGBC")
      (description "Smart RGB-LED")
      (libsource (lib "Liv_Flo_Sign") (part "P-XL-1010RGBC-WS2812B"))
    )
    (comp (ref "P337")
      (value "WS2812B")
      (footprint "SMD LED WS2812B-1010RGBC")
      (description "Smart RGB-LED")
      (libsource (lib "Liv_Flo_Sign") (part "P-XL-1010RGBC-WS2812B"))
    )
    (comp (ref "P338")
      (value "WS2812B")
      (footprint "SMD LED WS2812B-1010RGBC")
      (description "Smart RGB-LED")
      (libsource (lib "Liv_Flo_Sign") (part "P-XL-1010RGBC-WS2812B"))
    )
    (comp (ref "P339")
      (value "WS2812B")
      (footprint "SMD LED WS2812B-1010RGBC")
      (description "Smart RGB-LED")
      (libsource (lib "Liv_Flo_Sign") (part "P-XL-1010RGBC-WS2812B"))
    )
    (comp (ref "P340")
      (value "WS2812B")
      (footprint "SMD LED WS2812B-1010RGBC")
      (description "Smart RGB-LED")
      (libsource (lib "Liv_Flo_Sign") (part "P-XL-1010RGBC-WS2812B"))
    )
    (comp (ref "P341")
      (value "WS2812B")
      (footprint "SMD LED WS2812B-1010RGBC")
      (description "Smart RGB-LED")
      (libsource (lib "Liv_Flo_Sign") (part "P-XL-1010RGBC-WS2812B"))
    )
    (comp (ref "P342")
      (value "WS2812B")
      (footprint "SMD LED WS2812B-1010RGBC")
      (description "Smart RGB-LED")
      (libsource (lib "Liv_Flo_Sign") (part "P-XL-1010RGBC-WS2812B"))
    )
    (comp (ref "P343")
      (value "WS2812B")
      (footprint "SMD LED WS2812B-1010RGBC")
      (description "Smart RGB-LED")
      (libsource (lib "Liv_Flo_Sign") (part "P-XL-1010RGBC-WS2812B"))
    )
    (comp (ref "P344")
      (value "WS2812B")
      (footprint "SMD LED WS2812B-1010RGBC")
      (description "Smart RGB-LED")
      (libsource (lib "Liv_Flo_Sign") (part "P-XL-1010RGBC-WS2812B"))
    )
    (comp (ref "P345")
      (value "WS2812B")
      (footprint "SMD LED WS2812B-1010RGBC")
      (description "Smart RGB-LED")
      (libsource (lib "Liv_Flo_Sign") (part "P-XL-1010RGBC-WS2812B"))
    )
    (comp (ref "P346")
      (value "WS2812B")
      (footprint "SMD LED WS2812B-1010RGBC")
      (description "Smart RGB-LED")
      (libsource (lib "Liv_Flo_Sign") (part "P-XL-1010RGBC-WS2812B"))
    )
    (comp (ref "P347")
      (value "WS2812B")
      (footprint "SMD LED WS2812B-1010RGBC")
      (description "Smart RGB-LED")
      (libsource (lib "Liv_Flo_Sign") (part "P-XL-1010RGBC-WS2812B"))
    )
    (comp (ref "P348")
      (value "WS2812B")
      (footprint "SMD LED WS2812B-1010RGBC")
      (description "Smart RGB-LED")
      (libsource (lib "Liv_Flo_Sign") (part "P-XL-1010RGBC-WS2812B"))
    )
    (comp (ref "P349")
      (value "WS2812B")
      (footprint "SMD LED WS2812B-1010RGBC")
      (description "Smart RGB-LED")
      (libsource (lib "Liv_Flo_Sign") (part "P-XL-1010RGBC-WS2812B"))
    )
    (comp (ref "P350")
      (value "WS2812B")
      (footprint "SMD LED WS2812B-1010RGBC")
      (description "Smart RGB-LED")
      (libsource (lib "Liv_Flo_Sign") (part "P-XL-1010RGBC-WS2812B"))
    )
    (comp (ref "P351")
      (value "WS2812B")
      (footprint "SMD LED WS2812B-1010RGBC")
      (description "Smart RGB-LED")
      (libsource (lib "Liv_Flo_Sign") (part "P-XL-1010RGBC-WS2812B"))
    )
    (comp (ref "P352")
      (value "WS2812B")
      (footprint "SMD LED WS2812B-1010RGBC")
      (description "Smart RGB-LED")
      (libsource (lib "Liv_Flo_Sign") (part "P-XL-1010RGBC-WS2812B"))
    )
    (comp (ref "P353")
      (value "WS2812B")
      (footprint "SMD LED WS2812B-1010RGBC")
      (description "Smart RGB-LED")
      (libsource (lib "Liv_Flo_Sign") (part "P-XL-1010RGBC-WS2812B"))
    )
    (comp (ref "P354")
      (value "WS2812B")
      (footprint "SMD LED WS2812B-1010RGBC")
      (description "Smart RGB-LED")
      (libsource (lib "Liv_Flo_Sign") (part "P-XL-1010RGBC-WS2812B"))
    )
    (comp (ref "P355")
      (value "WS2812B")
      (footprint "SMD LED WS2812B-1010RGBC")
      (description "Smart RGB-LED")
      (libsource (lib "Liv_Flo_Sign") (part "P-XL-1010RGBC-WS2812B"))
    )
    (comp (ref "P356")
      (value "WS2812B")
      (footprint "SMD LED WS2812B-1010RGBC")
      (description "Smart RGB-LED")
      (libsource (lib "Liv_Flo_Sign") (part "P-XL-1010RGBC-WS2812B"))
    )
    (comp (ref "P357")
      (value "WS2812B")
      (footprint "SMD LED WS2812B-1010RGBC")
      (description "Smart RGB-LED")
      (libsource (lib "Liv_Flo_Sign") (part "P-XL-1010RGBC-WS2812B"))
    )
    (comp (ref "P358")
      (value "WS2812B")
      (footprint "SMD LED WS2812B-1010RGBC")
      (description "Smart RGB-LED")
      (libsource (lib "Liv_Flo_Sign") (part "P-XL-1010RGBC-WS2812B"))
    )
    (comp (ref "P359")
      (value "WS2812B")
      (footprint "SMD LED WS2812B-1010RGBC")
      (description "Smart RGB-LED")
      (libsource (lib "Liv_Flo_Sign") (part "P-XL-1010RGBC-WS2812B"))
    )
    (comp (ref "P360")
      (value "WS2812B")
      (footprint "SMD LED WS2812B-1010RGBC")
      (description "Smart RGB-LED")
      (libsource (lib "Liv_Flo_Sign") (part "P-XL-1010RGBC-WS2812B"))
    )
    (comp (ref "P361")
      (value "WS2812B")
      (footprint "SMD LED WS2812B-1010RGBC")
      (description "Smart RGB-LED")
      (libsource (lib "Liv_Flo_Sign") (part "P-XL-1010RGBC-WS2812B"))
    )
    (comp (ref "P362")
      (value "WS2812B")
      (footprint "SMD LED WS2812B-1010RGBC")
      (description "Smart RGB-LED")
      (libsource (lib "Liv_Flo_Sign") (part "P-XL-1010RGBC-WS2812B"))
    )
    (comp (ref "P363")
      (value "WS2812B")
      (footprint "SMD LED WS2812B-1010RGBC")
      (description "Smart RGB-LED")
      (libsource (lib "Liv_Flo_Sign") (part "P-XL-1010RGBC-WS2812B"))
    )
    (comp (ref "P364")
      (value "WS2812B")
      (footprint "SMD LED WS2812B-1010RGBC")
      (description "Smart RGB-LED")
      (libsource (lib "Liv_Flo_Sign") (part "P-XL-1010RGBC-WS2812B"))
    )
    (comp (ref "P365")
      (value "WS2812B")
      (footprint "SMD LED WS2812B-1010RGBC")
      (description "Smart RGB-LED")
      (libsource (lib "Liv_Flo_Sign") (part "P-XL-1010RGBC-WS2812B"))
    )
    (comp (ref "P366")
      (value "WS2812B")
      (footprint "SMD LED WS2812B-1010RGBC")
      (description "Smart RGB-LED")
      (libsource (lib "Liv_Flo_Sign") (part "P-XL-1010RGBC-WS2812B"))
    )
    (comp (ref "P367")
      (value "WS2812B")
      (footprint "SMD LED WS2812B-1010RGBC")
      (description "Smart RGB-LED")
      (libsource (lib "Liv_Flo_Sign") (part "P-XL-1010RGBC-WS2812B"))
    )
    (comp (ref "P368")
      (value "WS2812B")
      (footprint "SMD LED WS2812B-1010RGBC")
      (description "Smart RGB-LED")
      (libsource (lib "Liv_Flo_Sign") (part "P-XL-1010RGBC-WS2812B"))
    )
    (comp (ref "P369")
      (value "WS2812B")
      (footprint "SMD LED WS2812B-1010RGBC")
      (description "Smart RGB-LED")
      (libsource (lib "Liv_Flo_Sign") (part "P-XL-1010RGBC-WS2812B"))
    )
    (comp (ref "P370")
      (value "WS2812B")
      (footprint "SMD LED WS2812B-1010RGBC")
      (description "Smart RGB-LED")
      (libsource (lib "Liv_Flo_Sign") (part "P-XL-1010RGBC-WS2812B"))
    )
    (comp (ref "P371")
      (value "WS2812B")
      (footprint "SMD LED WS2812B-1010RGBC")
      (description "Smart RGB-LED")
      (libsource (lib "Liv_Flo_Sign") (part "P-XL-1010RGBC-WS2812B"))
    )
    (comp (ref "P372")
      (value "WS2812B")
      (footprint "SMD LED WS2812B-1010RGBC")
      (description "Smart RGB-LED")
      (libsource (lib "Liv_Flo_Sign") (part "P-XL-1010RGBC-WS2812B"))
    )
    (comp (ref "P373")
      (value "WS2812B")
      (footprint "SMD LED WS2812B-1010RGBC")
      (description "Smart RGB-LED")
      (libsource (lib "Liv_Flo_Sign") (part "P-XL-1010RGBC-WS2812B"))
    )
    (comp (ref "P374")
      (value "WS2812B")
      (footprint "SMD LED WS2812B-1010RGBC")
      (description "Smart RGB-LED")
      (libsource (lib "Liv_Flo_Sign") (part "P-XL-1010RGBC-WS2812B"))
    )
    (comp (ref "P375")
      (value "WS2812B")
      (footprint "SMD LED WS2812B-1010RGBC")
      (description "Smart RGB-LED")
      (libsource (lib "Liv_Flo_Sign") (part "P-XL-1010RGBC-WS2812B"))
    )
    (comp (ref "P376")
      (value "WS2812B")
      (footprint "SMD LED WS2812B-1010RGBC")
      (description "Smart RGB-LED")
      (libsource (lib "Liv_Flo_Sign") (part "P-XL-1010RGBC-WS2812B"))
    )
    (comp (ref "P377")
      (value "WS2812B")
      (footprint "SMD LED WS2812B-1010RGBC")
      (description "Smart RGB-LED")
      (libsource (lib "Liv_Flo_Sign") (part "P-XL-1010RGBC-WS2812B"))
    )
    (comp (ref "P378")
      (value "WS2812B")
      (footprint "SMD LED WS2812B-1010RGBC")
      (description "Smart RGB-LED")
      (libsource (lib "Liv_Flo_Sign") (part "P-XL-1010RGBC-WS2812B"))
    )
    (comp (ref "P379")
      (value "WS2812B")
      (footprint "SMD LED WS2812B-1010RGBC")
      (description "Smart RGB-LED")
      (libsource (lib "Liv_Flo_Sign") (part "P-XL-1010RGBC-WS2812B"))
    )
    (comp (ref "P380")
      (value "WS2812B")
      (footprint "SMD LED WS2812B-1010RGBC")
      (description "Smart RGB-LED")
      (libsource (lib "Liv_Flo_Sign") (part "P-XL-1010RGBC-WS2812B"))
    )
    (comp (ref "P381")
      (value "WS2812B")
      (footprint "SMD LED WS2812B-1010RGBC")
      (description "Smart RGB-LED")
      (libsource (lib "Liv_Flo_Sign") (part "P-XL-1010RGBC-WS2812B"))
    )
    (comp (ref "P382")
      (value "WS2812B")
      (footprint "SMD LED WS2812B-1010RGBC")
      (description "Smart RGB-LED")
      (libsource (lib "Liv_Flo_Sign") (part "P-XL-1010RGBC-WS2812B"))
    )
    (comp (ref "P383")
      (value "WS2812B")
      (footprint "SMD LED WS2812B-1010RGBC")
      (description "Smart RGB-LED")
      (libsource (lib "Liv_Flo_Sign") (part "P-XL-1010RGBC-WS2812B"))
    )
    (comp (ref "P384")
      (value "WS2812B")
      (footprint "SMD LED WS2812B-1010RGBC")
      (description "Smart RGB-LED")
      (libsource (lib "Liv_Flo_Sign") (part "P-XL-1010RGBC-WS2812B"))
    )
    (comp (ref "P385")
      (value "WS2812B")
      (footprint "SMD LED WS2812B-1010RGBC")
      (description "Smart RGB-LED")
      (libsource (lib "Liv_Flo_Sign") (part "P-XL-1010RGBC-WS2812B"))
    )
    (comp (ref "P386")
      (value "WS2812B")
      (footprint "SMD LED WS2812B-1010RGBC")
      (description "Smart RGB-LED")
      (libsource (lib "Liv_Flo_Sign") (part "P-XL-1010RGBC-WS2812B"))
    )
    (comp (ref "P387")
      (value "WS2812B")
      (footprint "SMD LED WS2812B-1010RGBC")
      (description "Smart RGB-LED")
      (libsource (lib "Liv_Flo_Sign") (part "P-XL-1010RGBC-WS2812B"))
    )
    (comp (ref "P388")
      (value "WS2812B")
      (footprint "SMD LED WS2812B-1010RGBC")
      (description "Smart RGB-LED")
      (libsource (lib "Liv_Flo_Sign") (part "P-XL-1010RGBC-WS2812B"))
    )
    (comp (ref "P389")
      (value "WS2812B")
      (footprint "SMD LED WS2812B-1010RGBC")
      (description "Smart RGB-LED")
      (libsource (lib "Liv_Flo_Sign") (part "P-XL-1010RGBC-WS2812B"))
    )
    (comp (ref "P390")
      (value "WS2812B")
      (footprint "SMD LED WS2812B-1010RGBC")
      (description "Smart RGB-LED")
      (libsource (lib "Liv_Flo_Sign") (part "P-XL-1010RGBC-WS2812B"))
    )
    (comp (ref "P391")
      (value "WS2812B")
      (footprint "SMD LED WS2812B-1010RGBC")
      (description "Smart RGB-LED")
      (libsource (lib "Liv_Flo_Sign") (part "P-XL-1010RGBC-WS2812B"))
    )
    (comp (ref "P392")
      (value "WS2812B")
      (footprint "SMD LED WS2812B-1010RGBC")
      (description "Smart RGB-LED")
      (libsource (lib "Liv_Flo_Sign") (part "P-XL-1010RGBC-WS2812B"))
    )
    (comp (ref "P393")
      (value "WS2812B")
      (footprint "SMD LED WS2812B-1010RGBC")
      (description "Smart RGB-LED")
      (libsource (lib "Liv_Flo_Sign") (part "P-XL-1010RGBC-WS2812B"))
    )
    (comp (ref "P394")
      (value "WS2812B")
      (footprint "SMD LED WS2812B-1010RGBC")
      (description "Smart RGB-LED")
      (libsource (lib "Liv_Flo_Sign") (part "P-XL-1010RGBC-WS2812B"))
    )
    (comp (ref "P395")
      (value "WS2812B")
      (footprint "SMD LED WS2812B-1010RGBC")
      (description "Smart RGB-LED")
      (libsource (lib "Liv_Flo_Sign") (part "P-XL-1010RGBC-WS2812B"))
    )
    (comp (ref "P396")
      (value "WS2812B")
      (footprint "SMD LED WS2812B-1010RGBC")
      (description "Smart RGB-LED")
      (libsource (lib "Liv_Flo_Sign") (part "P-XL-1010RGBC-WS2812B"))
    )
    (comp (ref "P397")
      (value "WS2812B")
      (footprint "SMD LED WS2812B-1010RGBC")
      (description "Smart RGB-LED")
      (libsource (lib "Liv_Flo_Sign") (part "P-XL-1010RGBC-WS2812B"))
    )
    (comp (ref "P398")
      (value "WS2812B")
      (footprint "SMD LED WS2812B-1010RGBC")
      (description "Smart RGB-LED")
      (libsource (lib "Liv_Flo_Sign") (part "P-XL-1010RGBC-WS2812B"))
    )
    (comp (ref "P399")
      (value "WS2812B")
      (footprint "SMD LED WS2812B-1010RGBC")
      (description "Smart RGB-LED")
      (libsource (lib "Liv_Flo_Sign") (part "P-XL-1010RGBC-WS2812B"))
    )
    (comp (ref "P400")
      (value "WS2812B")
      (footprint "SMD LED WS2812B-1010RGBC")
      (description "Smart RGB-LED")
      (libsource (lib "Liv_Flo_Sign") (part "P-XL-1010RGBC-WS2812B"))
    )
    (comp (ref "P401")
      (value "WS2812B")
      (footprint "SMD LED WS2812B-1010RGBC")
      (description "Smart RGB-LED")
      (libsource (lib "Liv_Flo_Sign") (part "P-XL-1010RGBC-WS2812B"))
    )
    (comp (ref "P402")
      (value "WS2812B")
      (footprint "SMD LED WS2812B-1010RGBC")
      (description "Smart RGB-LED")
      (libsource (lib "Liv_Flo_Sign") (part "P-XL-1010RGBC-WS2812B"))
    )
    (comp (ref "P403")
      (value "WS2812B")
      (footprint "SMD LED WS2812B-1010RGBC")
      (description "Smart RGB-LED")
      (libsource (lib "Liv_Flo_Sign") (part "P-XL-1010RGBC-WS2812B"))
    )
    (comp (ref "P404")
      (value "WS2812B")
      (footprint "SMD LED WS2812B-1010RGBC")
      (description "Smart RGB-LED")
      (libsource (lib "Liv_Flo_Sign") (part "P-XL-1010RGBC-WS2812B"))
    )
    (comp (ref "P405")
      (value "WS2812B")
      (footprint "SMD LED WS2812B-1010RGBC")
      (description "Smart RGB-LED")
      (libsource (lib "Liv_Flo_Sign") (part "P-XL-1010RGBC-WS2812B"))
    )
    (comp (ref "P406")
      (value "WS2812B")
      (footprint "SMD LED WS2812B-1010RGBC")
      (description "Smart RGB-LED")
      (libsource (lib "Liv_Flo_Sign") (part "P-XL-1010RGBC-WS2812B"))
    )
    (comp (ref "P407")
      (value "WS2812B")
      (footprint "SMD LED WS2812B-1010RGBC")
      (description "Smart RGB-LED")
      (libsource (lib "Liv_Flo_Sign") (part "P-XL-1010RGBC-WS2812B"))
    )
    (comp (ref "P408")
      (value "WS2812B")
      (footprint "SMD LED WS2812B-1010RGBC")
      (description "Smart RGB-LED")
      (libsource (lib "Liv_Flo_Sign") (part "P-XL-1010RGBC-WS2812B"))
    )
    (comp (ref "P409")
      (value "WS2812B")
      (footprint "SMD LED WS2812B-1010RGBC")
      (description "Smart RGB-LED")
      (libsource (lib "Liv_Flo_Sign") (part "P-XL-1010RGBC-WS2812B"))
    )
    (comp (ref "P410")
      (value "WS2812B")
      (footprint "SMD LED WS2812B-1010RGBC")
      (description "Smart RGB-LED")
      (libsource (lib "Liv_Flo_Sign") (part "P-XL-1010RGBC-WS2812B"))
    )
    (comp (ref "P411")
      (value "WS2812B")
      (footprint "SMD LED WS2812B-1010RGBC")
      (description "Smart RGB-LED")
      (libsource (lib "Liv_Flo_Sign") (part "P-XL-1010RGBC-WS2812B"))
    )
    (comp (ref "P412")
      (value "WS2812B")
      (footprint "SMD LED WS2812B-1010RGBC")
      (description "Smart RGB-LED")
      (libsource (lib "Liv_Flo_Sign") (part "P-XL-1010RGBC-WS2812B"))
    )
    (comp (ref "P413")
      (value "WS2812B")
      (footprint "SMD LED WS2812B-1010RGBC")
      (description "Smart RGB-LED")
      (libsource (lib "Liv_Flo_Sign") (part "P-XL-1010RGBC-WS2812B"))
    )
    (comp (ref "P414")
      (value "WS2812B")
      (footprint "SMD LED WS2812B-1010RGBC")
      (description "Smart RGB-LED")
      (libsource (lib "Liv_Flo_Sign") (part "P-XL-1010RGBC-WS2812B"))
    )
    (comp (ref "P415")
      (value "WS2812B")
      (footprint "SMD LED WS2812B-1010RGBC")
      (description "Smart RGB-LED")
      (libsource (lib "Liv_Flo_Sign") (part "P-XL-1010RGBC-WS2812B"))
    )
    (comp (ref "P416")
      (value "WS2812B")
      (footprint "SMD LED WS2812B-1010RGBC")
      (description "Smart RGB-LED")
      (libsource (lib "Liv_Flo_Sign") (part "P-XL-1010RGBC-WS2812B"))
    )
    (comp (ref "P417")
      (value "WS2812B")
      (footprint "SMD LED WS2812B-1010RGBC")
      (description "Smart RGB-LED")
      (libsource (lib "Liv_Flo_Sign") (part "P-XL-1010RGBC-WS2812B"))
    )
    (comp (ref "P418")
      (value "WS2812B")
      (footprint "SMD LED WS2812B-1010RGBC")
      (description "Smart RGB-LED")
      (libsource (lib "Liv_Flo_Sign") (part "P-XL-1010RGBC-WS2812B"))
    )
    (comp (ref "P419")
      (value "WS2812B")
      (footprint "SMD LED WS2812B-1010RGBC")
      (description "Smart RGB-LED")
      (libsource (lib "Liv_Flo_Sign") (part "P-XL-1010RGBC-WS2812B"))
    )
    (comp (ref "P420")
      (value "WS2812B")
      (footprint "SMD LED WS2812B-1010RGBC")
      (description "Smart RGB-LED")
      (libsource (lib "Liv_Flo_Sign") (part "P-XL-1010RGBC-WS2812B"))
    )
    (comp (ref "P421")
      (value "WS2812B")
      (footprint "SMD LED WS2812B-1010RGBC")
      (description "Smart RGB-LED")
      (libsource (lib "Liv_Flo_Sign") (part "P-XL-1010RGBC-WS2812B"))
    )
    (comp (ref "P422")
      (value "WS2812B")
      (footprint "SMD LED WS2812B-1010RGBC")
      (description "Smart RGB-LED")
      (libsource (lib "Liv_Flo_Sign") (part "P-XL-1010RGBC-WS2812B"))
    )
    (comp (ref "P423")
      (value "WS2812B")
      (footprint "SMD LED WS2812B-1010RGBC")
      (description "Smart RGB-LED")
      (libsource (lib "Liv_Flo_Sign") (part "P-XL-1010RGBC-WS2812B"))
    )
    (comp (ref "P424")
      (value "WS2812B")
      (footprint "SMD LED WS2812B-1010RGBC")
      (description "Smart RGB-LED")
      (libsource (lib "Liv_Flo_Sign") (part "P-XL-1010RGBC-WS2812B"))
    )
    (comp (ref "P425")
      (value "WS2812B")
      (footprint "SMD LED WS2812B-1010RGBC")
      (description "Smart RGB-LED")
      (libsource (lib "Liv_Flo_Sign") (part "P-XL-1010RGBC-WS2812B"))
    )
    (comp (ref "P426")
      (value "WS2812B")
      (footprint "SMD LED WS2812B-1010RGBC")
      (description "Smart RGB-LED")
      (libsource (lib "Liv_Flo_Sign") (part "P-XL-1010RGBC-WS2812B"))
    )
    (comp (ref "P427")
      (value "WS2812B")
      (footprint "SMD LED WS2812B-1010RGBC")
      (description "Smart RGB-LED")
      (libsource (lib "Liv_Flo_Sign") (part "P-XL-1010RGBC-WS2812B"))
    )
    (comp (ref "P428")
      (value "WS2812B")
      (footprint "SMD LED WS2812B-1010RGBC")
      (description "Smart RGB-LED")
      (libsource (lib "Liv_Flo_Sign") (part "P-XL-1010RGBC-WS2812B"))
    )
    (comp (ref "P429")
      (value "WS2812B")
      (footprint "SMD LED WS2812B-1010RGBC")
      (description "Smart RGB-LED")
      (libsource (lib "Liv_Flo_Sign") (part "P-XL-1010RGBC-WS2812B"))
    )
    (comp (ref "P430")
      (value "WS2812B")
      (footprint "SMD LED WS2812B-1010RGBC")
      (description "Smart RGB-LED")
      (libsource (lib "Liv_Flo_Sign") (part "P-XL-1010RGBC-WS2812B"))
    )
    (comp (ref "P431")
      (value "WS2812B")
      (footprint "SMD LED WS2812B-1010RGBC")
      (description "Smart RGB-LED")
      (libsource (lib "Liv_Flo_Sign") (part "P-XL-1010RGBC-WS2812B"))
    )
    (comp (ref "P432")
      (value "WS2812B")
      (footprint "SMD LED WS2812B-1010RGBC")
      (description "Smart RGB-LED")
      (libsource (lib "Liv_Flo_Sign") (part "P-XL-1010RGBC-WS2812B"))
    )
    (comp (ref "P433")
      (value "WS2812B")
      (footprint "SMD LED WS2812B-1010RGBC")
      (description "Smart RGB-LED")
      (libsource (lib "Liv_Flo_Sign") (part "P-XL-1010RGBC-WS2812B"))
    )
    (comp (ref "P434")
      (value "WS2812B")
      (footprint "SMD LED WS2812B-1010RGBC")
      (description "Smart RGB-LED")
      (libsource (lib "Liv_Flo_Sign") (part "P-XL-1010RGBC-WS2812B"))
    )
    (comp (ref "P435")
      (value "WS2812B")
      (footprint "SMD LED WS2812B-1010RGBC")
      (description "Smart RGB-LED")
      (libsource (lib "Liv_Flo_Sign") (part "P-XL-1010RGBC-WS2812B"))
    )
    (comp (ref "P436")
      (value "WS2812B")
      (footprint "SMD LED WS2812B-1010RGBC")
      (description "Smart RGB-LED")
      (libsource (lib "Liv_Flo_Sign") (part "P-XL-1010RGBC-WS2812B"))
    )
    (comp (ref "P437")
      (value "WS2812B")
      (footprint "SMD LED WS2812B-1010RGBC")
      (description "Smart RGB-LED")
      (libsource (lib "Liv_Flo_Sign") (part "P-XL-1010RGBC-WS2812B"))
    )
    (comp (ref "P438")
      (value "WS2812B")
      (footprint "SMD LED WS2812B-1010RGBC")
      (description "Smart RGB-LED")
      (libsource (lib "Liv_Flo_Sign") (part "P-XL-1010RGBC-WS2812B"))
    )
    (comp (ref "P439")
      (value "WS2812B")
      (footprint "SMD LED WS2812B-1010RGBC")
      (description "Smart RGB-LED")
      (libsource (lib "Liv_Flo_Sign") (part "P-XL-1010RGBC-WS2812B"))
    )
    (comp (ref "P440")
      (value "WS2812B")
      (footprint "SMD LED WS2812B-1010RGBC")
      (description "Smart RGB-LED")
      (libsource (lib "Liv_Flo_Sign") (part "P-XL-1010RGBC-WS2812B"))
    )
    (comp (ref "P441")
      (value "WS2812B")
      (footprint "SMD LED WS2812B-1010RGBC")
      (description "Smart RGB-LED")
      (libsource (lib "Liv_Flo_Sign") (part "P-XL-1010RGBC-WS2812B"))
    )
    (comp (ref "P442")
      (value "WS2812B")
      (footprint "SMD LED WS2812B-1010RGBC")
      (description "Smart RGB-LED")
      (libsource (lib "Liv_Flo_Sign") (part "P-XL-1010RGBC-WS2812B"))
    )
    (comp (ref "P443")
      (value "WS2812B")
      (footprint "SMD LED WS2812B-1010RGBC")
      (description "Smart RGB-LED")
      (libsource (lib "Liv_Flo_Sign") (part "P-XL-1010RGBC-WS2812B"))
    )
    (comp (ref "P444")
      (value "WS2812B")
      (footprint "SMD LED WS2812B-1010RGBC")
      (description "Smart RGB-LED")
      (libsource (lib "Liv_Flo_Sign") (part "P-XL-1010RGBC-WS2812B"))
    )
    (comp (ref "P445")
      (value "WS2812B")
      (footprint "SMD LED WS2812B-1010RGBC")
      (description "Smart RGB-LED")
      (libsource (lib "Liv_Flo_Sign") (part "P-XL-1010RGBC-WS2812B"))
    )
    (comp (ref "P446")
      (value "WS2812B")
      (footprint "SMD LED WS2812B-1010RGBC")
      (description "Smart RGB-LED")
      (libsource (lib "Liv_Flo_Sign") (part "P-XL-1010RGBC-WS2812B"))
    )
    (comp (ref "P447")
      (value "WS2812B")
      (footprint "SMD LED WS2812B-1010RGBC")
      (description "Smart RGB-LED")
      (libsource (lib "Liv_Flo_Sign") (part "P-XL-1010RGBC-WS2812B"))
    )
    (comp (ref "P448")
      (value "WS2812B")
      (footprint "SMD LED WS2812B-1010RGBC")
      (description "Smart RGB-LED")
      (libsource (lib "Liv_Flo_Sign") (part "P-XL-1010RGBC-WS2812B"))
    )
    (comp (ref "P449")
      (value "WS2812B")
      (footprint "SMD LED WS2812B-1010RGBC")
      (description "Smart RGB-LED")
      (libsource (lib "Liv_Flo_Sign") (part "P-XL-1010RGBC-WS2812B"))
    )
    (comp (ref "P450")
      (value "WS2812B")
      (footprint "SMD LED WS2812B-1010RGBC")
      (description "Smart RGB-LED")
      (libsource (lib "Liv_Flo_Sign") (part "P-XL-1010RGBC-WS2812B"))
    )
    (comp (ref "P451")
      (value "WS2812B")
      (footprint "SMD LED WS2812B-1010RGBC")
      (description "Smart RGB-LED")
      (libsource (lib "Liv_Flo_Sign") (part "P-XL-1010RGBC-WS2812B"))
    )
    (comp (ref "P452")
      (value "WS2812B")
      (footprint "SMD LED WS2812B-1010RGBC")
      (description "Smart RGB-LED")
      (libsource (lib "Liv_Flo_Sign") (part "P-XL-1010RGBC-WS2812B"))
    )
    (comp (ref "P453")
      (value "WS2812B")
      (footprint "SMD LED WS2812B-1010RGBC")
      (description "Smart RGB-LED")
      (libsource (lib "Liv_Flo_Sign") (part "P-XL-1010RGBC-WS2812B"))
    )
    (comp (ref "P454")
      (value "WS2812B")
      (footprint "SMD LED WS2812B-1010RGBC")
      (description "Smart RGB-LED")
      (libsource (lib "Liv_Flo_Sign") (part "P-XL-1010RGBC-WS2812B"))
    )
    (comp (ref "P455")
      (value "WS2812B")
      (footprint "SMD LED WS2812B-1010RGBC")
      (description "Smart RGB-LED")
      (libsource (lib "Liv_Flo_Sign") (part "P-XL-1010RGBC-WS2812B"))
    )
    (comp (ref "P456")
      (value "WS2812B")
      (footprint "SMD LED WS2812B-1010RGBC")
      (description "Smart RGB-LED")
      (libsource (lib "Liv_Flo_Sign") (part "P-XL-1010RGBC-WS2812B"))
    )
    (comp (ref "P457")
      (value "WS2812B")
      (footprint "SMD LED WS2812B-1010RGBC")
      (description "Smart RGB-LED")
      (libsource (lib "Liv_Flo_Sign") (part "P-XL-1010RGBC-WS2812B"))
    )
    (comp (ref "P458")
      (value "WS2812B")
      (footprint "SMD LED WS2812B-1010RGBC")
      (description "Smart RGB-LED")
      (libsource (lib "Liv_Flo_Sign") (part "P-XL-1010RGBC-WS2812B"))
    )
    (comp (ref "P459")
      (value "WS2812B")
      (footprint "SMD LED WS2812B-1010RGBC")
      (description "Smart RGB-LED")
      (libsource (lib "Liv_Flo_Sign") (part "P-XL-1010RGBC-WS2812B"))
    )
    (comp (ref "P460")
      (value "WS2812B")
      (footprint "SMD LED WS2812B-1010RGBC")
      (description "Smart RGB-LED")
      (libsource (lib "Liv_Flo_Sign") (part "P-XL-1010RGBC-WS2812B"))
    )
    (comp (ref "P461")
      (value "WS2812B")
      (footprint "SMD LED WS2812B-1010RGBC")
      (description "Smart RGB-LED")
      (libsource (lib "Liv_Flo_Sign") (part "P-XL-1010RGBC-WS2812B"))
    )
    (comp (ref "P462")
      (value "WS2812B")
      (footprint "SMD LED WS2812B-1010RGBC")
      (description "Smart RGB-LED")
      (libsource (lib "Liv_Flo_Sign") (part "P-XL-1010RGBC-WS2812B"))
    )
    (comp (ref "P463")
      (value "WS2812B")
      (footprint "SMD LED WS2812B-1010RGBC")
      (description "Smart RGB-LED")
      (libsource (lib "Liv_Flo_Sign") (part "P-XL-1010RGBC-WS2812B"))
    )
    (comp (ref "P464")
      (value "WS2812B")
      (footprint "SMD LED WS2812B-1010RGBC")
      (description "Smart RGB-LED")
      (libsource (lib "Liv_Flo_Sign") (part "P-XL-1010RGBC-WS2812B"))
    )
    (comp (ref "P465")
      (value "WS2812B")
      (footprint "SMD LED WS2812B-1010RGBC")
      (description "Smart RGB-LED")
      (libsource (lib "Liv_Flo_Sign") (part "P-XL-1010RGBC-WS2812B"))
    )
    (comp (ref "P466")
      (value "WS2812B")
      (footprint "SMD LED WS2812B-1010RGBC")
      (description "Smart RGB-LED")
      (libsource (lib "Liv_Flo_Sign") (part "P-XL-1010RGBC-WS2812B"))
    )
    (comp (ref "P467")
      (value "WS2812B")
      (footprint "SMD LED WS2812B-1010RGBC")
      (description "Smart RGB-LED")
      (libsource (lib "Liv_Flo_Sign") (part "P-XL-1010RGBC-WS2812B"))
    )
    (comp (ref "P468")
      (value "WS2812B")
      (footprint "SMD LED WS2812B-1010RGBC")
      (description "Smart RGB-LED")
      (libsource (lib "Liv_Flo_Sign") (part "P-XL-1010RGBC-WS2812B"))
    )
    (comp (ref "P469")
      (value "WS2812B")
      (footprint "SMD LED WS2812B-1010RGBC")
      (description "Smart RGB-LED")
      (libsource (lib "Liv_Flo_Sign") (part "P-XL-1010RGBC-WS2812B"))
    )
    (comp (ref "P470")
      (value "WS2812B")
      (footprint "SMD LED WS2812B-1010RGBC")
      (description "Smart RGB-LED")
      (libsource (lib "Liv_Flo_Sign") (part "P-XL-1010RGBC-WS2812B"))
    )
    (comp (ref "P471")
      (value "WS2812B")
      (footprint "SMD LED WS2812B-1010RGBC")
      (description "Smart RGB-LED")
      (libsource (lib "Liv_Flo_Sign") (part "P-XL-1010RGBC-WS2812B"))
    )
    (comp (ref "P472")
      (value "WS2812B")
      (footprint "SMD LED WS2812B-1010RGBC")
      (description "Smart RGB-LED")
      (libsource (lib "Liv_Flo_Sign") (part "P-XL-1010RGBC-WS2812B"))
    )
    (comp (ref "P473")
      (value "WS2812B")
      (footprint "SMD LED WS2812B-1010RGBC")
      (description "Smart RGB-LED")
      (libsource (lib "Liv_Flo_Sign") (part "P-XL-1010RGBC-WS2812B"))
    )
    (comp (ref "P474")
      (value "WS2812B")
      (footprint "SMD LED WS2812B-1010RGBC")
      (description "Smart RGB-LED")
      (libsource (lib "Liv_Flo_Sign") (part "P-XL-1010RGBC-WS2812B"))
    )
    (comp (ref "P475")
      (value "WS2812B")
      (footprint "SMD LED WS2812B-1010RGBC")
      (description "Smart RGB-LED")
      (libsource (lib "Liv_Flo_Sign") (part "P-XL-1010RGBC-WS2812B"))
    )
    (comp (ref "P476")
      (value "WS2812B")
      (footprint "SMD LED WS2812B-1010RGBC")
      (description "Smart RGB-LED")
      (libsource (lib "Liv_Flo_Sign") (part "P-XL-1010RGBC-WS2812B"))
    )
    (comp (ref "P477")
      (value "WS2812B")
      (footprint "SMD LED WS2812B-1010RGBC")
      (description "Smart RGB-LED")
      (libsource (lib "Liv_Flo_Sign") (part "P-XL-1010RGBC-WS2812B"))
    )
    (comp (ref "P478")
      (value "WS2812B")
      (footprint "SMD LED WS2812B-1010RGBC")
      (description "Smart RGB-LED")
      (libsource (lib "Liv_Flo_Sign") (part "P-XL-1010RGBC-WS2812B"))
    )
    (comp (ref "P479")
      (value "WS2812B")
      (footprint "SMD LED WS2812B-1010RGBC")
      (description "Smart RGB-LED")
      (libsource (lib "Liv_Flo_Sign") (part "P-XL-1010RGBC-WS2812B"))
    )
    (comp (ref "P480")
      (value "WS2812B")
      (footprint "SMD LED WS2812B-1010RGBC")
      (description "Smart RGB-LED")
      (libsource (lib "Liv_Flo_Sign") (part "P-XL-1010RGBC-WS2812B"))
    )
    (comp (ref "P481")
      (value "WS2812B")
      (footprint "SMD LED WS2812B-1010RGBC")
      (description "Smart RGB-LED")
      (libsource (lib "Liv_Flo_Sign") (part "P-XL-1010RGBC-WS2812B"))
    )
    (comp (ref "P482")
      (value "WS2812B")
      (footprint "SMD LED WS2812B-1010RGBC")
      (description "Smart RGB-LED")
      (libsource (lib "Liv_Flo_Sign") (part "P-XL-1010RGBC-WS2812B"))
    )
    (comp (ref "P483")
      (value "WS2812B")
      (footprint "SMD LED WS2812B-1010RGBC")
      (description "Smart RGB-LED")
      (libsource (lib "Liv_Flo_Sign") (part "P-XL-1010RGBC-WS2812B"))
    )
    (comp (ref "P484")
      (value "WS2812B")
      (footprint "SMD LED WS2812B-1010RGBC")
      (description "Smart RGB-LED")
      (libsource (lib "Liv_Flo_Sign") (part "P-XL-1010RGBC-WS2812B"))
    )
    (comp (ref "P485")
      (value "WS2812B")
      (footprint "SMD LED WS2812B-1010RGBC")
      (description "Smart RGB-LED")
      (libsource (lib "Liv_Flo_Sign") (part "P-XL-1010RGBC-WS2812B"))
    )
    (comp (ref "P486")
      (value "WS2812B")
      (footprint "SMD LED WS2812B-1010RGBC")
      (description "Smart RGB-LED")
      (libsource (lib "Liv_Flo_Sign") (part "P-XL-1010RGBC-WS2812B"))
    )
    (comp (ref "P487")
      (value "WS2812B")
      (footprint "SMD LED WS2812B-1010RGBC")
      (description "Smart RGB-LED")
      (libsource (lib "Liv_Flo_Sign") (part "P-XL-1010RGBC-WS2812B"))
    )
    (comp (ref "P488")
      (value "WS2812B")
      (footprint "SMD LED WS2812B-1010RGBC")
      (description "Smart RGB-LED")
      (libsource (lib "Liv_Flo_Sign") (part "P-XL-1010RGBC-WS2812B"))
    )
    (comp (ref "P489")
      (value "WS2812B")
      (footprint "SMD LED WS2812B-1010RGBC")
      (description "Smart RGB-LED")
      (libsource (lib "Liv_Flo_Sign") (part "P-XL-1010RGBC-WS2812B"))
    )
    (comp (ref "P490")
      (value "WS2812B")
      (footprint "SMD LED WS2812B-1010RGBC")
      (description "Smart RGB-LED")
      (libsource (lib "Liv_Flo_Sign") (part "P-XL-1010RGBC-WS2812B"))
    )
    (comp (ref "P491")
      (value "WS2812B")
      (footprint "SMD LED WS2812B-1010RGBC")
      (description "Smart RGB-LED")
      (libsource (lib "Liv_Flo_Sign") (part "P-XL-1010RGBC-WS2812B"))
    )
    (comp (ref "P492")
      (value "WS2812B")
      (footprint "SMD LED WS2812B-1010RGBC")
      (description "Smart RGB-LED")
      (libsource (lib "Liv_Flo_Sign") (part "P-XL-1010RGBC-WS2812B"))
    )
    (comp (ref "P493")
      (value "WS2812B")
      (footprint "SMD LED WS2812B-1010RGBC")
      (description "Smart RGB-LED")
      (libsource (lib "Liv_Flo_Sign") (part "P-XL-1010RGBC-WS2812B"))
    )
    (comp (ref "P494")
      (value "WS2812B")
      (footprint "SMD LED WS2812B-1010RGBC")
      (description "Smart RGB-LED")
      (libsource (lib "Liv_Flo_Sign") (part "P-XL-1010RGBC-WS2812B"))
    )
    (comp (ref "P495")
      (value "WS2812B")
      (footprint "SMD LED WS2812B-1010RGBC")
      (description "Smart RGB-LED")
      (libsource (lib "Liv_Flo_Sign") (part "P-XL-1010RGBC-WS2812B"))
    )
    (comp (ref "P496")
      (value "WS2812B")
      (footprint "SMD LED WS2812B-1010RGBC")
      (description "Smart RGB-LED")
      (libsource (lib "Liv_Flo_Sign") (part "P-XL-1010RGBC-WS2812B"))
    )
    (comp (ref "P497")
      (value "WS2812B")
      (footprint "SMD LED WS2812B-1010RGBC")
      (description "Smart RGB-LED")
      (libsource (lib "Liv_Flo_Sign") (part "P-XL-1010RGBC-WS2812B"))
    )
    (comp (ref "P498")
      (value "WS2812B")
      (footprint "SMD LED WS2812B-1010RGBC")
      (description "Smart RGB-LED")
      (libsource (lib "Liv_Flo_Sign") (part "P-XL-1010RGBC-WS2812B"))
    )
    (comp (ref "P499")
      (value "WS2812B")
      (footprint "SMD LED WS2812B-1010RGBC")
      (description "Smart RGB-LED")
      (libsource (lib "Liv_Flo_Sign") (part "P-XL-1010RGBC-WS2812B"))
    )
    (comp (ref "P500")
      (value "WS2812B")
      (footprint "SMD LED WS2812B-1010RGBC")
      (description "Smart RGB-LED")
      (libsource (lib "Liv_Flo_Sign") (part "P-XL-1010RGBC-WS2812B"))
    )
    (comp (ref "P501")
      (value "WS2812B")
      (footprint "SMD LED WS2812B-1010RGBC")
      (description "Smart RGB-LED")
      (libsource (lib "Liv_Flo_Sign") (part "P-XL-1010RGBC-WS2812B"))
    )
    (comp (ref "P502")
      (value "WS2812B")
      (footprint "SMD LED WS2812B-1010RGBC")
      (description "Smart RGB-LED")
      (libsource (lib "Liv_Flo_Sign") (part "P-XL-1010RGBC-WS2812B"))
    )
    (comp (ref "P503")
      (value "WS2812B")
      (footprint "SMD LED WS2812B-1010RGBC")
      (description "Smart RGB-LED")
      (libsource (lib "Liv_Flo_Sign") (part "P-XL-1010RGBC-WS2812B"))
    )
    (comp (ref "P504")
      (value "WS2812B")
      (footprint "SMD LED WS2812B-1010RGBC")
      (description "Smart RGB-LED")
      (libsource (lib "Liv_Flo_Sign") (part "P-XL-1010RGBC-WS2812B"))
    )
    (comp (ref "P505")
      (value "WS2812B")
      (footprint "SMD LED WS2812B-1010RGBC")
      (description "Smart RGB-LED")
      (libsource (lib "Liv_Flo_Sign") (part "P-XL-1010RGBC-WS2812B"))
    )
    (comp (ref "P506")
      (value "WS2812B")
      (footprint "SMD LED WS2812B-1010RGBC")
      (description "Smart RGB-LED")
      (libsource (lib "Liv_Flo_Sign") (part "P-XL-1010RGBC-WS2812B"))
    )
    (comp (ref "P507")
      (value "WS2812B")
      (footprint "SMD LED WS2812B-1010RGBC")
      (description "Smart RGB-LED")
      (libsource (lib "Liv_Flo_Sign") (part "P-XL-1010RGBC-WS2812B"))
    )
    (comp (ref "P508")
      (value "WS2812B")
      (footprint "SMD LED WS2812B-1010RGBC")
      (description "Smart RGB-LED")
      (libsource (lib "Liv_Flo_Sign") (part "P-XL-1010RGBC-WS2812B"))
    )
    (comp (ref "P509")
      (value "WS2812B")
      (footprint "SMD LED WS2812B-1010RGBC")
      (description "Smart RGB-LED")
      (libsource (lib "Liv_Flo_Sign") (part "P-XL-1010RGBC-WS2812B"))
    )
    (comp (ref "P510")
      (value "WS2812B")
      (footprint "SMD LED WS2812B-1010RGBC")
      (description "Smart RGB-LED")
      (libsource (lib "Liv_Flo_Sign") (part "P-XL-1010RGBC-WS2812B"))
    )
    (comp (ref "P511")
      (value "WS2812B")
      (footprint "SMD LED WS2812B-1010RGBC")
      (description "Smart RGB-LED")
      (libsource (lib "Liv_Flo_Sign") (part "P-XL-1010RGBC-WS2812B"))
    )
    (comp (ref "P512")
      (value "WS2812B")
      (footprint "SMD LED WS2812B-1010RGBC")
      (description "Smart RGB-LED")
      (libsource (lib "Liv_Flo_Sign") (part "P-XL-1010RGBC-WS2812B"))
    )
    (comp (ref "P513")
      (value "WS2812B")
      (footprint "SMD LED WS2812B-1010RGBC")
      (description "Smart RGB-LED")
      (libsource (lib "Liv_Flo_Sign") (part "P-XL-1010RGBC-WS2812B"))
    )
    (comp (ref "P514")
      (value "WS2812B")
      (footprint "SMD LED WS2812B-1010RGBC")
      (description "Smart RGB-LED")
      (libsource (lib "Liv_Flo_Sign") (part "P-XL-1010RGBC-WS2812B"))
    )
    (comp (ref "P515")
      (value "WS2812B")
      (footprint "SMD LED WS2812B-1010RGBC")
      (description "Smart RGB-LED")
      (libsource (lib "Liv_Flo_Sign") (part "P-XL-1010RGBC-WS2812B"))
    )
    (comp (ref "P516")
      (value "WS2812B")
      (footprint "SMD LED WS2812B-1010RGBC")
      (description "Smart RGB-LED")
      (libsource (lib "Liv_Flo_Sign") (part "P-XL-1010RGBC-WS2812B"))
    )
    (comp (ref "P517")
      (value "WS2812B")
      (footprint "SMD LED WS2812B-1010RGBC")
      (description "Smart RGB-LED")
      (libsource (lib "Liv_Flo_Sign") (part "P-XL-1010RGBC-WS2812B"))
    )
    (comp (ref "P518")
      (value "WS2812B")
      (footprint "SMD LED WS2812B-1010RGBC")
      (description "Smart RGB-LED")
      (libsource (lib "Liv_Flo_Sign") (part "P-XL-1010RGBC-WS2812B"))
    )
    (comp (ref "P519")
      (value "WS2812B")
      (footprint "SMD LED WS2812B-1010RGBC")
      (description "Smart RGB-LED")
      (libsource (lib "Liv_Flo_Sign") (part "P-XL-1010RGBC-WS2812B"))
    )
    (comp (ref "P520")
      (value "WS2812B")
      (footprint "SMD LED WS2812B-1010RGBC")
      (description "Smart RGB-LED")
      (libsource (lib "Liv_Flo_Sign") (part "P-XL-1010RGBC-WS2812B"))
    )
    (comp (ref "P521")
      (value "WS2812B")
      (footprint "SMD LED WS2812B-1010RGBC")
      (description "Smart RGB-LED")
      (libsource (lib "Liv_Flo_Sign") (part "P-XL-1010RGBC-WS2812B"))
    )
    (comp (ref "P522")
      (value "WS2812B")
      (footprint "SMD LED WS2812B-1010RGBC")
      (description "Smart RGB-LED")
      (libsource (lib "Liv_Flo_Sign") (part "P-XL-1010RGBC-WS2812B"))
    )
    (comp (ref "P523")
      (value "WS2812B")
      (footprint "SMD LED WS2812B-1010RGBC")
      (description "Smart RGB-LED")
      (libsource (lib "Liv_Flo_Sign") (part "P-XL-1010RGBC-WS2812B"))
    )
    (comp (ref "P524")
      (value "WS2812B")
      (footprint "SMD LED WS2812B-1010RGBC")
      (description "Smart RGB-LED")
      (libsource (lib "Liv_Flo_Sign") (part "P-XL-1010RGBC-WS2812B"))
    )
    (comp (ref "P525")
      (value "WS2812B")
      (footprint "SMD LED WS2812B-1010RGBC")
      (description "Smart RGB-LED")
      (libsource (lib "Liv_Flo_Sign") (part "P-XL-1010RGBC-WS2812B"))
    )
    (comp (ref "P526")
      (value "WS2812B")
      (footprint "SMD LED WS2812B-1010RGBC")
      (description "Smart RGB-LED")
      (libsource (lib "Liv_Flo_Sign") (part "P-XL-1010RGBC-WS2812B"))
    )
    (comp (ref "P527")
      (value "WS2812B")
      (footprint "SMD LED WS2812B-1010RGBC")
      (description "Smart RGB-LED")
      (libsource (lib "Liv_Flo_Sign") (part "P-XL-1010RGBC-WS2812B"))
    )
    (comp (ref "P528")
      (value "WS2812B")
      (footprint "SMD LED WS2812B-1010RGBC")
      (description "Smart RGB-LED")
      (libsource (lib "Liv_Flo_Sign") (part "P-XL-1010RGBC-WS2812B"))
    )
    (comp (ref "P529")
      (value "WS2812B")
      (footprint "SMD LED WS2812B-1010RGBC")
      (description "Smart RGB-LED")
      (libsource (lib "Liv_Flo_Sign") (part "P-XL-1010RGBC-WS2812B"))
    )
    (comp (ref "P530")
      (value "WS2812B")
      (footprint "SMD LED WS2812B-1010RGBC")
      (description "Smart RGB-LED")
      (libsource (lib "Liv_Flo_Sign") (part "P-XL-1010RGBC-WS2812B"))
    )
    (comp (ref "P531")
      (value "WS2812B")
      (footprint "SMD LED WS2812B-1010RGBC")
      (description "Smart RGB-LED")
      (libsource (lib "Liv_Flo_Sign") (part "P-XL-1010RGBC-WS2812B"))
    )
    (comp (ref "P532")
      (value "WS2812B")
      (footprint "SMD LED WS2812B-1010RGBC")
      (description "Smart RGB-LED")
      (libsource (lib "Liv_Flo_Sign") (part "P-XL-1010RGBC-WS2812B"))
    )
    (comp (ref "P533")
      (value "WS2812B")
      (footprint "SMD LED WS2812B-1010RGBC")
      (description "Smart RGB-LED")
      (libsource (lib "Liv_Flo_Sign") (part "P-XL-1010RGBC-WS2812B"))
    )
    (comp (ref "P534")
      (value "WS2812B")
      (footprint "SMD LED WS2812B-1010RGBC")
      (description "Smart RGB-LED")
      (libsource (lib "Liv_Flo_Sign") (part "P-XL-1010RGBC-WS2812B"))
    )
    (comp (ref "P535")
      (value "WS2812B")
      (footprint "SMD LED WS2812B-1010RGBC")
      (description "Smart RGB-LED")
      (libsource (lib "Liv_Flo_Sign") (part "P-XL-1010RGBC-WS2812B"))
    )
    (comp (ref "P536")
      (value "WS2812B")
      (footprint "SMD LED WS2812B-1010RGBC")
      (description "Smart RGB-LED")
      (libsource (lib "Liv_Flo_Sign") (part "P-XL-1010RGBC-WS2812B"))
    )
    (comp (ref "P537")
      (value "WS2812B")
      (footprint "SMD LED WS2812B-1010RGBC")
      (description "Smart RGB-LED")
      (libsource (lib "Liv_Flo_Sign") (part "P-XL-1010RGBC-WS2812B"))
    )
    (comp (ref "P538")
      (value "WS2812B")
      (footprint "SMD LED WS2812B-1010RGBC")
      (description "Smart RGB-LED")
      (libsource (lib "Liv_Flo_Sign") (part "P-XL-1010RGBC-WS2812B"))
    )
    (comp (ref "P539")
      (value "WS2812B")
      (footprint "SMD LED WS2812B-1010RGBC")
      (description "Smart RGB-LED")
      (libsource (lib "Liv_Flo_Sign") (part "P-XL-1010RGBC-WS2812B"))
    )
    (comp (ref "P540")
      (value "WS2812B")
      (footprint "SMD LED WS2812B-1010RGBC")
      (description "Smart RGB-LED")
      (libsource (lib "Liv_Flo_Sign") (part "P-XL-1010RGBC-WS2812B"))
    )
    (comp (ref "P541")
      (value "WS2812B")
      (footprint "SMD LED WS2812B-1010RGBC")
      (description "Smart RGB-LED")
      (libsource (lib "Liv_Flo_Sign") (part "P-XL-1010RGBC-WS2812B"))
    )
    (comp (ref "P542")
      (value "WS2812B")
      (footprint "SMD LED WS2812B-1010RGBC")
      (description "Smart RGB-LED")
      (libsource (lib "Liv_Flo_Sign") (part "P-XL-1010RGBC-WS2812B"))
    )
    (comp (ref "P543")
      (value "WS2812B")
      (footprint "SMD LED WS2812B-1010RGBC")
      (description "Smart RGB-LED")
      (libsource (lib "Liv_Flo_Sign") (part "P-XL-1010RGBC-WS2812B"))
    )
    (comp (ref "P544")
      (value "WS2812B")
      (footprint "SMD LED WS2812B-1010RGBC")
      (description "Smart RGB-LED")
      (libsource (lib "Liv_Flo_Sign") (part "P-XL-1010RGBC-WS2812B"))
    )
    (comp (ref "P545")
      (value "WS2812B")
      (footprint "SMD LED WS2812B-1010RGBC")
      (description "Smart RGB-LED")
      (libsource (lib "Liv_Flo_Sign") (part "P-XL-1010RGBC-WS2812B"))
    )
    (comp (ref "P546")
      (value "WS2812B")
      (footprint "SMD LED WS2812B-1010RGBC")
      (description "Smart RGB-LED")
      (libsource (lib "Liv_Flo_Sign") (part "P-XL-1010RGBC-WS2812B"))
    )
    (comp (ref "P547")
      (value "WS2812B")
      (footprint "SMD LED WS2812B-1010RGBC")
      (description "Smart RGB-LED")
      (libsource (lib "Liv_Flo_Sign") (part "P-XL-1010RGBC-WS2812B"))
    )
    (comp (ref "P548")
      (value "WS2812B")
      (footprint "SMD LED WS2812B-1010RGBC")
      (description "Smart RGB-LED")
      (libsource (lib "Liv_Flo_Sign") (part "P-XL-1010RGBC-WS2812B"))
    )
  )
  (nets
    (net (code "1") (name "/LED_MAT") (class "Default")
      (node (ref "P1") (pin "4") (pinfunction "IN_4") (pintype "passive"))
    )
    (net (code "2") (name "/LED_SIGN") (class "Default")
      (node (ref "P281") (pin "4") (pinfunction "IN_4") (pintype "passive"))
    )
    (net (code "3") (name "5V") (class "Default")
      (node (ref "C17") (pin "2") (pinfunction "2_2") (pintype "passive"))
      (node (ref "C18") (pin "2") (pinfunction "2_2") (pintype "passive"))
      (node (ref "C19") (pin "2") (pinfunction "2_2") (pintype "passive"))
      (node (ref "C20") (pin "2") (pinfunction "2_2") (pintype "passive"))
      (node (ref "C21") (pin "2") (pinfunction "2_2") (pintype "passive"))
      (node (ref "C22") (pin "2") (pinfunction "2_2") (pintype "passive"))
      (node (ref "C23") (pin "2") (pinfunction "2_2") (pintype "passive"))
      (node (ref "C24") (pin "2") (pinfunction "2_2") (pintype "passive"))
      (node (ref "C25") (pin "2") (pinfunction "2_2") (pintype "passive"))
      (node (ref "C26") (pin "2") (pinfunction "2_2") (pintype "passive"))
      (node (ref "C27") (pin "2") (pinfunction "2_2") (pintype "passive"))
      (node (ref "C28") (pin "2") (pinfunction "2_2") (pintype "passive"))
      (node (ref "C29") (pin "2") (pinfunction "2_2") (pintype "passive"))
      (node (ref "C30") (pin "2") (pinfunction "2_2") (pintype "passive"))
      (node (ref "C31") (pin "2") (pinfunction "2_2") (pintype "passive"))
      (node (ref "C32") (pin "2") (pinfunction "2_2") (pintype "passive"))
      (node (ref "C33") (pin "2") (pinfunction "2_2") (pintype "passive"))
      (node (ref "C34") (pin "2") (pinfunction "2_2") (pintype "passive"))
      (node (ref "C35") (pin "2") (pinfunction "2_2") (pintype "passive"))
      (node (ref "C36") (pin "2") (pinfunction "2_2") (pintype "passive"))
      (node (ref "C37") (pin "2") (pinfunction "2_2") (pintype "passive"))
      (node (ref "C38") (pin "2") (pinfunction "2_2") (pintype "passive"))
      (node (ref "C39") (pin "2") (pinfunction "2_2") (pintype "passive"))
      (node (ref "C40") (pin "2") (pinfunction "2_2") (pintype "passive"))
      (node (ref "C41") (pin "2") (pinfunction "2_2") (pintype "passive"))
      (node (ref "C42") (pin "2") (pinfunction "2_2") (pintype "passive"))
      (node (ref "C43") (pin "2") (pinfunction "2_2") (pintype "passive"))
      (node (ref "C44") (pin "2") (pinfunction "2_2") (pintype "passive"))
      (node (ref "C45") (pin "2") (pinfunction "2_2") (pintype "passive"))
      (node (ref "C46") (pin "2") (pinfunction "2_2") (pintype "passive"))
      (node (ref "C47") (pin "2") (pinfunction "2_2") (pintype "passive"))
      (node (ref "C48") (pin "2") (pinfunction "2_2") (pintype "passive"))
      (node (ref "C49") (pin "2") (pinfunction "2_2") (pintype "passive"))
      (node (ref "C50") (pin "2") (pinfunction "2_2") (pintype "passive"))
      (node (ref "C51") (pin "2") (pinfunction "2_2") (pintype "passive"))
      (node (ref "C52") (pin "2") (pinfunction "2_2") (pintype "passive"))
      (node (ref "C53") (pin "2") (pinfunction "2_2") (pintype "passive"))
      (node (ref "C54") (pin "2") (pinfunction "2_2") (pintype "passive"))
      (node (ref "C55") (pin "2") (pinfunction "2_2") (pintype "passive"))
      (node (ref "C56") (pin "2") (pinfunction "2_2") (pintype "passive"))
      (node (ref "C57") (pin "2") (pinfunction "2_2") (pintype "passive"))
      (node (ref "C58") (pin "2") (pinfunction "2_2") (pintype "passive"))
      (node (ref "P1") (pin "2") (pinfunction "VCC_2") (pintype "power_in"))
      (node (ref "P10") (pin "2") (pinfunction "VCC_2") (pintype "power_in"))
      (node (ref "P100") (pin "2") (pinfunction "VCC_2") (pintype "power_in"))
      (node (ref "P101") (pin "2") (pinfunction "VCC_2") (pintype "power_in"))
      (node (ref "P102") (pin "2") (pinfunction "VCC_2") (pintype "power_in"))
      (node (ref "P103") (pin "2") (pinfunction "VCC_2") (pintype "power_in"))
      (node (ref "P104") (pin "2") (pinfunction "VCC_2") (pintype "power_in"))
      (node (ref "P105") (pin "2") (pinfunction "VCC_2") (pintype "power_in"))
      (node (ref "P106") (pin "2") (pinfunction "VCC_2") (pintype "power_in"))
      (node (ref "P107") (pin "2") (pinfunction "VCC_2") (pintype "power_in"))
      (node (ref "P108") (pin "2") (pinfunction "VCC_2") (pintype "power_in"))
      (node (ref "P109") (pin "2") (pinfunction "VCC_2") (pintype "power_in"))
      (node (ref "P11") (pin "2") (pinfunction "VCC_2") (pintype "power_in"))
      (node (ref "P110") (pin "2") (pinfunction "VCC_2") (pintype "power_in"))
      (node (ref "P111") (pin "2") (pinfunction "VCC_2") (pintype "power_in"))
      (node (ref "P112") (pin "2") (pinfunction "VCC_2") (pintype "power_in"))
      (node (ref "P113") (pin "2") (pinfunction "VCC_2") (pintype "power_in"))
      (node (ref "P114") (pin "2") (pinfunction "VCC_2") (pintype "power_in"))
      (node (ref "P115") (pin "2") (pinfunction "VCC_2") (pintype "power_in"))
      (node (ref "P116") (pin "2") (pinfunction "VCC_2") (pintype "power_in"))
      (node (ref "P117") (pin "2") (pinfunction "VCC_2") (pintype "power_in"))
      (node (ref "P118") (pin "2") (pinfunction "VCC_2") (pintype "power_in"))
      (node (ref "P119") (pin "2") (pinfunction "VCC_2") (pintype "power_in"))
      (node (ref "P12") (pin "2") (pinfunction "VCC_2") (pintype "power_in"))
      (node (ref "P120") (pin "2") (pinfunction "VCC_2") (pintype "power_in"))
      (node (ref "P121") (pin "2") (pinfunction "VCC_2") (pintype "power_in"))
      (node (ref "P122") (pin "2") (pinfunction "VCC_2") (pintype "power_in"))
      (node (ref "P123") (pin "2") (pinfunction "VCC_2") (pintype "power_in"))
      (node (ref "P124") (pin "2") (pinfunction "VCC_2") (pintype "power_in"))
      (node (ref "P125") (pin "2") (pinfunction "VCC_2") (pintype "power_in"))
      (node (ref "P126") (pin "2") (pinfunction "VCC_2") (pintype "power_in"))
      (node (ref "P127") (pin "2") (pinfunction "VCC_2") (pintype "power_in"))
      (node (ref "P128") (pin "2") (pinfunction "VCC_2") (pintype "power_in"))
      (node (ref "P129") (pin "2") (pinfunction "VCC_2") (pintype "power_in"))
      (node (ref "P13") (pin "2") (pinfunction "VCC_2") (pintype "power_in"))
      (node (ref "P130") (pin "2") (pinfunction "VCC_2") (pintype "power_in"))
      (node (ref "P131") (pin "2") (pinfunction "VCC_2") (pintype "power_in"))
      (node (ref "P132") (pin "2") (pinfunction "VCC_2") (pintype "power_in"))
      (node (ref "P133") (pin "2") (pinfunction "VCC_2") (pintype "power_in"))
      (node (ref "P134") (pin "2") (pinfunction "VCC_2") (pintype "power_in"))
      (node (ref "P135") (pin "2") (pinfunction "VCC_2") (pintype "power_in"))
      (node (ref "P136") (pin "2") (pinfunction "VCC_2") (pintype "power_in"))
      (node (ref "P137") (pin "2") (pinfunction "VCC_2") (pintype "power_in"))
      (node (ref "P138") (pin "2") (pinfunction "VCC_2") (pintype "power_in"))
      (node (ref "P139") (pin "2") (pinfunction "VCC_2") (pintype "power_in"))
      (node (ref "P14") (pin "2") (pinfunction "VCC_2") (pintype "power_in"))
      (node (ref "P140") (pin "2") (pinfunction "VCC_2") (pintype "power_in"))
      (node (ref "P141") (pin "2") (pinfunction "VCC_2") (pintype "power_in"))
      (node (ref "P142") (pin "2") (pinfunction "VCC_2") (pintype "power_in"))
      (node (ref "P143") (pin "2") (pinfunction "VCC_2") (pintype "power_in"))
      (node (ref "P144") (pin "2") (pinfunction "VCC_2") (pintype "power_in"))
      (node (ref "P145") (pin "2") (pinfunction "VCC_2") (pintype "power_in"))
      (node (ref "P146") (pin "2") (pinfunction "VCC_2") (pintype "power_in"))
      (node (ref "P147") (pin "2") (pinfunction "VCC_2") (pintype "power_in"))
      (node (ref "P148") (pin "2") (pinfunction "VCC_2") (pintype "power_in"))
      (node (ref "P149") (pin "2") (pinfunction "VCC_2") (pintype "power_in"))
      (node (ref "P15") (pin "2") (pinfunction "VCC_2") (pintype "power_in"))
      (node (ref "P150") (pin "2") (pinfunction "VCC_2") (pintype "power_in"))
      (node (ref "P151") (pin "2") (pinfunction "VCC_2") (pintype "power_in"))
      (node (ref "P152") (pin "2") (pinfunction "VCC_2") (pintype "power_in"))
      (node (ref "P153") (pin "2") (pinfunction "VCC_2") (pintype "power_in"))
      (node (ref "P154") (pin "2") (pinfunction "VCC_2") (pintype "power_in"))
      (node (ref "P155") (pin "2") (pinfunction "VCC_2") (pintype "power_in"))
      (node (ref "P156") (pin "2") (pinfunction "VCC_2") (pintype "power_in"))
      (node (ref "P157") (pin "2") (pinfunction "VCC_2") (pintype "power_in"))
      (node (ref "P158") (pin "2") (pinfunction "VCC_2") (pintype "power_in"))
      (node (ref "P159") (pin "2") (pinfunction "VCC_2") (pintype "power_in"))
      (node (ref "P16") (pin "2") (pinfunction "VCC_2") (pintype "power_in"))
      (node (ref "P160") (pin "2") (pinfunction "VCC_2") (pintype "power_in"))
      (node (ref "P161") (pin "2") (pinfunction "VCC_2") (pintype "power_in"))
      (node (ref "P162") (pin "2") (pinfunction "VCC_2") (pintype "power_in"))
      (node (ref "P163") (pin "2") (pinfunction "VCC_2") (pintype "power_in"))
      (node (ref "P164") (pin "2") (pinfunction "VCC_2") (pintype "power_in"))
      (node (ref "P165") (pin "2") (pinfunction "VCC_2") (pintype "power_in"))
      (node (ref "P166") (pin "2") (pinfunction "VCC_2") (pintype "power_in"))
      (node (ref "P167") (pin "2") (pinfunction "VCC_2") (pintype "power_in"))
      (node (ref "P168") (pin "2") (pinfunction "VCC_2") (pintype "power_in"))
      (node (ref "P169") (pin "2") (pinfunction "VCC_2") (pintype "power_in"))
      (node (ref "P17") (pin "2") (pinfunction "VCC_2") (pintype "power_in"))
      (node (ref "P170") (pin "2") (pinfunction "VCC_2") (pintype "power_in"))
      (node (ref "P171") (pin "2") (pinfunction "VCC_2") (pintype "power_in"))
      (node (ref "P172") (pin "2") (pinfunction "VCC_2") (pintype "power_in"))
      (node (ref "P173") (pin "2") (pinfunction "VCC_2") (pintype "power_in"))
      (node (ref "P174") (pin "2") (pinfunction "VCC_2") (pintype "power_in"))
      (node (ref "P175") (pin "2") (pinfunction "VCC_2") (pintype "power_in"))
      (node (ref "P176") (pin "2") (pinfunction "VCC_2") (pintype "power_in"))
      (node (ref "P177") (pin "2") (pinfunction "VCC_2") (pintype "power_in"))
      (node (ref "P178") (pin "2") (pinfunction "VCC_2") (pintype "power_in"))
      (node (ref "P179") (pin "2") (pinfunction "VCC_2") (pintype "power_in"))
      (node (ref "P18") (pin "2") (pinfunction "VCC_2") (pintype "power_in"))
      (node (ref "P180") (pin "2") (pinfunction "VCC_2") (pintype "power_in"))
      (node (ref "P181") (pin "2") (pinfunction "VCC_2") (pintype "power_in"))
      (node (ref "P182") (pin "2") (pinfunction "VCC_2") (pintype "power_in"))
      (node (ref "P183") (pin "2") (pinfunction "VCC_2") (pintype "power_in"))
      (node (ref "P184") (pin "2") (pinfunction "VCC_2") (pintype "power_in"))
      (node (ref "P185") (pin "2") (pinfunction "VCC_2") (pintype "power_in"))
      (node (ref "P186") (pin "2") (pinfunction "VCC_2") (pintype "power_in"))
      (node (ref "P187") (pin "2") (pinfunction "VCC_2") (pintype "power_in"))
      (node (ref "P188") (pin "2") (pinfunction "VCC_2") (pintype "power_in"))
      (node (ref "P189") (pin "2") (pinfunction "VCC_2") (pintype "power_in"))
      (node (ref "P19") (pin "2") (pinfunction "VCC_2") (pintype "power_in"))
      (node (ref "P190") (pin "2") (pinfunction "VCC_2") (pintype "power_in"))
      (node (ref "P191") (pin "2") (pinfunction "VCC_2") (pintype "power_in"))
      (node (ref "P192") (pin "2") (pinfunction "VCC_2") (pintype "power_in"))
      (node (ref "P193") (pin "2") (pinfunction "VCC_2") (pintype "power_in"))
      (node (ref "P194") (pin "2") (pinfunction "VCC_2") (pintype "power_in"))
      (node (ref "P195") (pin "2") (pinfunction "VCC_2") (pintype "power_in"))
      (node (ref "P196") (pin "2") (pinfunction "VCC_2") (pintype "power_in"))
      (node (ref "P197") (pin "2") (pinfunction "VCC_2") (pintype "power_in"))
      (node (ref "P198") (pin "2") (pinfunction "VCC_2") (pintype "power_in"))
      (node (ref "P199") (pin "2") (pinfunction "VCC_2") (pintype "power_in"))
      (node (ref "P2") (pin "2") (pinfunction "VCC_2") (pintype "power_in"))
      (node (ref "P20") (pin "2") (pinfunction "VCC_2") (pintype "power_in"))
      (node (ref "P200") (pin "2") (pinfunction "VCC_2") (pintype "power_in"))
      (node (ref "P201") (pin "2") (pinfunction "VCC_2") (pintype "power_in"))
      (node (ref "P202") (pin "2") (pinfunction "VCC_2") (pintype "power_in"))
      (node (ref "P203") (pin "2") (pinfunction "VCC_2") (pintype "power_in"))
      (node (ref "P204") (pin "2") (pinfunction "VCC_2") (pintype "power_in"))
      (node (ref "P205") (pin "2") (pinfunction "VCC_2") (pintype "power_in"))
      (node (ref "P206") (pin "2") (pinfunction "VCC_2") (pintype "power_in"))
      (node (ref "P207") (pin "2") (pinfunction "VCC_2") (pintype "power_in"))
      (node (ref "P208") (pin "2") (pinfunction "VCC_2") (pintype "power_in"))
      (node (ref "P209") (pin "2") (pinfunction "VCC_2") (pintype "power_in"))
      (node (ref "P21") (pin "2") (pinfunction "VCC_2") (pintype "power_in"))
      (node (ref "P210") (pin "2") (pinfunction "VCC_2") (pintype "power_in"))
      (node (ref "P211") (pin "2") (pinfunction "VCC_2") (pintype "power_in"))
      (node (ref "P212") (pin "2") (pinfunction "VCC_2") (pintype "power_in"))
      (node (ref "P213") (pin "2") (pinfunction "VCC_2") (pintype "power_in"))
      (node (ref "P214") (pin "2") (pinfunction "VCC_2") (pintype "power_in"))
      (node (ref "P215") (pin "2") (pinfunction "VCC_2") (pintype "power_in"))
      (node (ref "P216") (pin "2") (pinfunction "VCC_2") (pintype "power_in"))
      (node (ref "P217") (pin "2") (pinfunction "VCC_2") (pintype "power_in"))
      (node (ref "P218") (pin "2") (pinfunction "VCC_2") (pintype "power_in"))
      (node (ref "P219") (pin "2") (pinfunction "VCC_2") (pintype "power_in"))
      (node (ref "P22") (pin "2") (pinfunction "VCC_2") (pintype "power_in"))
      (node (ref "P220") (pin "2") (pinfunction "VCC_2") (pintype "power_in"))
      (node (ref "P221") (pin "2") (pinfunction "VCC_2") (pintype "power_in"))
      (node (ref "P222") (pin "2") (pinfunction "VCC_2") (pintype "power_in"))
      (node (ref "P223") (pin "2") (pinfunction "VCC_2") (pintype "power_in"))
      (node (ref "P224") (pin "2") (pinfunction "VCC_2") (pintype "power_in"))
      (node (ref "P225") (pin "2") (pinfunction "VCC_2") (pintype "power_in"))
      (node (ref "P226") (pin "2") (pinfunction "VCC_2") (pintype "power_in"))
      (node (ref "P227") (pin "2") (pinfunction "VCC_2") (pintype "power_in"))
      (node (ref "P228") (pin "2") (pinfunction "VCC_2") (pintype "power_in"))
      (node (ref "P229") (pin "2") (pinfunction "VCC_2") (pintype "power_in"))
      (node (ref "P23") (pin "2") (pinfunction "VCC_2") (pintype "power_in"))
      (node (ref "P230") (pin "2") (pinfunction "VCC_2") (pintype "power_in"))
      (node (ref "P231") (pin "2") (pinfunction "VCC_2") (pintype "power_in"))
      (node (ref "P232") (pin "2") (pinfunction "VCC_2") (pintype "power_in"))
      (node (ref "P233") (pin "2") (pinfunction "VCC_2") (pintype "power_in"))
      (node (ref "P234") (pin "2") (pinfunction "VCC_2") (pintype "power_in"))
      (node (ref "P235") (pin "2") (pinfunction "VCC_2") (pintype "power_in"))
      (node (ref "P236") (pin "2") (pinfunction "VCC_2") (pintype "power_in"))
      (node (ref "P237") (pin "2") (pinfunction "VCC_2") (pintype "power_in"))
      (node (ref "P238") (pin "2") (pinfunction "VCC_2") (pintype "power_in"))
      (node (ref "P239") (pin "2") (pinfunction "VCC_2") (pintype "power_in"))
      (node (ref "P24") (pin "2") (pinfunction "VCC_2") (pintype "power_in"))
      (node (ref "P240") (pin "2") (pinfunction "VCC_2") (pintype "power_in"))
      (node (ref "P241") (pin "2") (pinfunction "VCC_2") (pintype "power_in"))
      (node (ref "P242") (pin "2") (pinfunction "VCC_2") (pintype "power_in"))
      (node (ref "P243") (pin "2") (pinfunction "VCC_2") (pintype "power_in"))
      (node (ref "P244") (pin "2") (pinfunction "VCC_2") (pintype "power_in"))
      (node (ref "P245") (pin "2") (pinfunction "VCC_2") (pintype "power_in"))
      (node (ref "P246") (pin "2") (pinfunction "VCC_2") (pintype "power_in"))
      (node (ref "P247") (pin "2") (pinfunction "VCC_2") (pintype "power_in"))
      (node (ref "P248") (pin "2") (pinfunction "VCC_2") (pintype "power_in"))
      (node (ref "P249") (pin "2") (pinfunction "VCC_2") (pintype "power_in"))
      (node (ref "P25") (pin "2") (pinfunction "VCC_2") (pintype "power_in"))
      (node (ref "P250") (pin "2") (pinfunction "VCC_2") (pintype "power_in"))
      (node (ref "P251") (pin "2") (pinfunction "VCC_2") (pintype "power_in"))
      (node (ref "P252") (pin "2") (pinfunction "VCC_2") (pintype "power_in"))
      (node (ref "P253") (pin "2") (pinfunction "VCC_2") (pintype "power_in"))
      (node (ref "P254") (pin "2") (pinfunction "VCC_2") (pintype "power_in"))
      (node (ref "P255") (pin "2") (pinfunction "VCC_2") (pintype "power_in"))
      (node (ref "P256") (pin "2") (pinfunction "VCC_2") (pintype "power_in"))
      (node (ref "P257") (pin "2") (pinfunction "VCC_2") (pintype "power_in"))
      (node (ref "P258") (pin "2") (pinfunction "VCC_2") (pintype "power_in"))
      (node (ref "P259") (pin "2") (pinfunction "VCC_2") (pintype "power_in"))
      (node (ref "P26") (pin "2") (pinfunction "VCC_2") (pintype "power_in"))
      (node (ref "P260") (pin "2") (pinfunction "VCC_2") (pintype "power_in"))
      (node (ref "P261") (pin "2") (pinfunction "VCC_2") (pintype "power_in"))
      (node (ref "P262") (pin "2") (pinfunction "VCC_2") (pintype "power_in"))
      (node (ref "P263") (pin "2") (pinfunction "VCC_2") (pintype "power_in"))
      (node (ref "P264") (pin "2") (pinfunction "VCC_2") (pintype "power_in"))
      (node (ref "P265") (pin "2") (pinfunction "VCC_2") (pintype "power_in"))
      (node (ref "P266") (pin "2") (pinfunction "VCC_2") (pintype "power_in"))
      (node (ref "P267") (pin "2") (pinfunction "VCC_2") (pintype "power_in"))
      (node (ref "P268") (pin "2") (pinfunction "VCC_2") (pintype "power_in"))
      (node (ref "P269") (pin "2") (pinfunction "VCC_2") (pintype "power_in"))
      (node (ref "P27") (pin "2") (pinfunction "VCC_2") (pintype "power_in"))
      (node (ref "P270") (pin "2") (pinfunction "VCC_2") (pintype "power_in"))
      (node (ref "P271") (pin "2") (pinfunction "VCC_2") (pintype "power_in"))
      (node (ref "P272") (pin "2") (pinfunction "VCC_2") (pintype "power_in"))
      (node (ref "P273") (pin "2") (pinfunction "VCC_2") (pintype "power_in"))
      (node (ref "P274") (pin "2") (pinfunction "VCC_2") (pintype "power_in"))
      (node (ref "P275") (pin "2") (pinfunction "VCC_2") (pintype "power_in"))
      (node (ref "P276") (pin "2") (pinfunction "VCC_2") (pintype "power_in"))
      (node (ref "P277") (pin "2") (pinfunction "VCC_2") (pintype "power_in"))
      (node (ref "P278") (pin "2") (pinfunction "VCC_2") (pintype "power_in"))
      (node (ref "P279") (pin "2") (pinfunction "VCC_2") (pintype "power_in"))
      (node (ref "P28") (pin "2") (pinfunction "VCC_2") (pintype "power_in"))
      (node (ref "P280") (pin "2") (pinfunction "VCC_2") (pintype "power_in"))
      (node (ref "P281") (pin "2") (pinfunction "VCC_2") (pintype "power_in"))
      (node (ref "P282") (pin "2") (pinfunction "VCC_2") (pintype "power_in"))
      (node (ref "P283") (pin "2") (pinfunction "VCC_2") (pintype "power_in"))
      (node (ref "P284") (pin "2") (pinfunction "VCC_2") (pintype "power_in"))
      (node (ref "P285") (pin "2") (pinfunction "VCC_2") (pintype "power_in"))
      (node (ref "P286") (pin "2") (pinfunction "VCC_2") (pintype "power_in"))
      (node (ref "P287") (pin "2") (pinfunction "VCC_2") (pintype "power_in"))
      (node (ref "P288") (pin "2") (pinfunction "VCC_2") (pintype "power_in"))
      (node (ref "P289") (pin "2") (pinfunction "VCC_2") (pintype "power_in"))
      (node (ref "P29") (pin "2") (pinfunction "VCC_2") (pintype "power_in"))
      (node (ref "P290") (pin "2") (pinfunction "VCC_2") (pintype "power_in"))
      (node (ref "P291") (pin "2") (pinfunction "VCC_2") (pintype "power_in"))
      (node (ref "P292") (pin "2") (pinfunction "VCC_2") (pintype "power_in"))
      (node (ref "P293") (pin "2") (pinfunction "VCC_2") (pintype "power_in"))
      (node (ref "P294") (pin "2") (pinfunction "VCC_2") (pintype "power_in"))
      (node (ref "P295") (pin "2") (pinfunction "VCC_2") (pintype "power_in"))
      (node (ref "P296") (pin "2") (pinfunction "VCC_2") (pintype "power_in"))
      (node (ref "P297") (pin "2") (pinfunction "VCC_2") (pintype "power_in"))
      (node (ref "P298") (pin "2") (pinfunction "VCC_2") (pintype "power_in"))
      (node (ref "P299") (pin "2") (pinfunction "VCC_2") (pintype "power_in"))
      (node (ref "P3") (pin "2") (pinfunction "VCC_2") (pintype "power_in"))
      (node (ref "P30") (pin "2") (pinfunction "VCC_2") (pintype "power_in"))
      (node (ref "P300") (pin "2") (pinfunction "VCC_2") (pintype "power_in"))
      (node (ref "P301") (pin "2") (pinfunction "VCC_2") (pintype "power_in"))
      (node (ref "P302") (pin "2") (pinfunction "VCC_2") (pintype "power_in"))
      (node (ref "P303") (pin "2") (pinfunction "VCC_2") (pintype "power_in"))
      (node (ref "P304") (pin "2") (pinfunction "VCC_2") (pintype "power_in"))
      (node (ref "P305") (pin "2") (pinfunction "VCC_2") (pintype "power_in"))
      (node (ref "P306") (pin "2") (pinfunction "VCC_2") (pintype "power_in"))
      (node (ref "P307") (pin "2") (pinfunction "VCC_2") (pintype "power_in"))
      (node (ref "P308") (pin "2") (pinfunction "VCC_2") (pintype "power_in"))
      (node (ref "P309") (pin "2") (pinfunction "VCC_2") (pintype "power_in"))
      (node (ref "P31") (pin "2") (pinfunction "VCC_2") (pintype "power_in"))
      (node (ref "P310") (pin "2") (pinfunction "VCC_2") (pintype "power_in"))
      (node (ref "P311") (pin "2") (pinfunction "VCC_2") (pintype "power_in"))
      (node (ref "P312") (pin "2") (pinfunction "VCC_2") (pintype "power_in"))
      (node (ref "P313") (pin "2") (pinfunction "VCC_2") (pintype "power_in"))
      (node (ref "P314") (pin "2") (pinfunction "VCC_2") (pintype "power_in"))
      (node (ref "P315") (pin "2") (pinfunction "VCC_2") (pintype "power_in"))
      (node (ref "P316") (pin "2") (pinfunction "VCC_2") (pintype "power_in"))
      (node (ref "P317") (pin "2") (pinfunction "VCC_2") (pintype "power_in"))
      (node (ref "P318") (pin "2") (pinfunction "VCC_2") (pintype "power_in"))
      (node (ref "P319") (pin "2") (pinfunction "VCC_2") (pintype "power_in"))
      (node (ref "P32") (pin "2") (pinfunction "VCC_2") (pintype "power_in"))
      (node (ref "P320") (pin "2") (pinfunction "VCC_2") (pintype "power_in"))
      (node (ref "P321") (pin "2") (pinfunction "VCC_2") (pintype "power_in"))
      (node (ref "P322") (pin "2") (pinfunction "VCC_2") (pintype "power_in"))
      (node (ref "P323") (pin "2") (pinfunction "VCC_2") (pintype "power_in"))
      (node (ref "P324") (pin "2") (pinfunction "VCC_2") (pintype "power_in"))
      (node (ref "P325") (pin "2") (pinfunction "VCC_2") (pintype "power_in"))
      (node (ref "P326") (pin "2") (pinfunction "VCC_2") (pintype "power_in"))
      (node (ref "P327") (pin "2") (pinfunction "VCC_2") (pintype "power_in"))
      (node (ref "P328") (pin "2") (pinfunction "VCC_2") (pintype "power_in"))
      (node (ref "P329") (pin "2") (pinfunction "VCC_2") (pintype "power_in"))
      (node (ref "P33") (pin "2") (pinfunction "VCC_2") (pintype "power_in"))
      (node (ref "P330") (pin "2") (pinfunction "VCC_2") (pintype "power_in"))
      (node (ref "P331") (pin "2") (pinfunction "VCC_2") (pintype "power_in"))
      (node (ref "P332") (pin "2") (pinfunction "VCC_2") (pintype "power_in"))
      (node (ref "P333") (pin "2") (pinfunction "VCC_2") (pintype "power_in"))
      (node (ref "P334") (pin "2") (pinfunction "VCC_2") (pintype "power_in"))
      (node (ref "P335") (pin "2") (pinfunction "VCC_2") (pintype "power_in"))
      (node (ref "P336") (pin "2") (pinfunction "VCC_2") (pintype "power_in"))
      (node (ref "P337") (pin "2") (pinfunction "VCC_2") (pintype "power_in"))
      (node (ref "P338") (pin "2") (pinfunction "VCC_2") (pintype "power_in"))
      (node (ref "P339") (pin "2") (pinfunction "VCC_2") (pintype "power_in"))
      (node (ref "P34") (pin "2") (pinfunction "VCC_2") (pintype "power_in"))
      (node (ref "P340") (pin "2") (pinfunction "VCC_2") (pintype "power_in"))
      (node (ref "P341") (pin "2") (pinfunction "VCC_2") (pintype "power_in"))
      (node (ref "P342") (pin "2") (pinfunction "VCC_2") (pintype "power_in"))
      (node (ref "P343") (pin "2") (pinfunction "VCC_2") (pintype "power_in"))
      (node (ref "P344") (pin "2") (pinfunction "VCC_2") (pintype "power_in"))
      (node (ref "P345") (pin "2") (pinfunction "VCC_2") (pintype "power_in"))
      (node (ref "P346") (pin "2") (pinfunction "VCC_2") (pintype "power_in"))
      (node (ref "P347") (pin "2") (pinfunction "VCC_2") (pintype "power_in"))
      (node (ref "P348") (pin "2") (pinfunction "VCC_2") (pintype "power_in"))
      (node (ref "P349") (pin "2") (pinfunction "VCC_2") (pintype "power_in"))
      (node (ref "P35") (pin "2") (pinfunction "VCC_2") (pintype "power_in"))
      (node (ref "P350") (pin "2") (pinfunction "VCC_2") (pintype "power_in"))
      (node (ref "P351") (pin "2") (pinfunction "VCC_2") (pintype "power_in"))
      (node (ref "P352") (pin "2") (pinfunction "VCC_2") (pintype "power_in"))
      (node (ref "P353") (pin "2") (pinfunction "VCC_2") (pintype "power_in"))
      (node (ref "P354") (pin "2") (pinfunction "VCC_2") (pintype "power_in"))
      (node (ref "P355") (pin "2") (pinfunction "VCC_2") (pintype "power_in"))
      (node (ref "P356") (pin "2") (pinfunction "VCC_2") (pintype "power_in"))
      (node (ref "P357") (pin "2") (pinfunction "VCC_2") (pintype "power_in"))
      (node (ref "P358") (pin "2") (pinfunction "VCC_2") (pintype "power_in"))
      (node (ref "P359") (pin "2") (pinfunction "VCC_2") (pintype "power_in"))
      (node (ref "P36") (pin "2") (pinfunction "VCC_2") (pintype "power_in"))
      (node (ref "P360") (pin "2") (pinfunction "VCC_2") (pintype "power_in"))
      (node (ref "P361") (pin "2") (pinfunction "VCC_2") (pintype "power_in"))
      (node (ref "P362") (pin "2") (pinfunction "VCC_2") (pintype "power_in"))
      (node (ref "P363") (pin "2") (pinfunction "VCC_2") (pintype "power_in"))
      (node (ref "P364") (pin "2") (pinfunction "VCC_2") (pintype "power_in"))
      (node (ref "P365") (pin "2") (pinfunction "VCC_2") (pintype "power_in"))
      (node (ref "P366") (pin "2") (pinfunction "VCC_2") (pintype "power_in"))
      (node (ref "P367") (pin "2") (pinfunction "VCC_2") (pintype "power_in"))
      (node (ref "P368") (pin "2") (pinfunction "VCC_2") (pintype "power_in"))
      (node (ref "P369") (pin "2") (pinfunction "VCC_2") (pintype "power_in"))
      (node (ref "P37") (pin "2") (pinfunction "VCC_2") (pintype "power_in"))
      (node (ref "P370") (pin "2") (pinfunction "VCC_2") (pintype "power_in"))
      (node (ref "P371") (pin "2") (pinfunction "VCC_2") (pintype "power_in"))
      (node (ref "P372") (pin "2") (pinfunction "VCC_2") (pintype "power_in"))
      (node (ref "P373") (pin "2") (pinfunction "VCC_2") (pintype "power_in"))
      (node (ref "P374") (pin "2") (pinfunction "VCC_2") (pintype "power_in"))
      (node (ref "P375") (pin "2") (pinfunction "VCC_2") (pintype "power_in"))
      (node (ref "P376") (pin "2") (pinfunction "VCC_2") (pintype "power_in"))
      (node (ref "P377") (pin "2") (pinfunction "VCC_2") (pintype "power_in"))
      (node (ref "P378") (pin "2") (pinfunction "VCC_2") (pintype "power_in"))
      (node (ref "P379") (pin "2") (pinfunction "VCC_2") (pintype "power_in"))
      (node (ref "P38") (pin "2") (pinfunction "VCC_2") (pintype "power_in"))
      (node (ref "P380") (pin "2") (pinfunction "VCC_2") (pintype "power_in"))
      (node (ref "P381") (pin "2") (pinfunction "VCC_2") (pintype "power_in"))
      (node (ref "P382") (pin "2") (pinfunction "VCC_2") (pintype "power_in"))
      (node (ref "P383") (pin "2") (pinfunction "VCC_2") (pintype "power_in"))
      (node (ref "P384") (pin "2") (pinfunction "VCC_2") (pintype "power_in"))
      (node (ref "P385") (pin "2") (pinfunction "VCC_2") (pintype "power_in"))
      (node (ref "P386") (pin "2") (pinfunction "VCC_2") (pintype "power_in"))
      (node (ref "P387") (pin "2") (pinfunction "VCC_2") (pintype "power_in"))
      (node (ref "P388") (pin "2") (pinfunction "VCC_2") (pintype "power_in"))
      (node (ref "P389") (pin "2") (pinfunction "VCC_2") (pintype "power_in"))
      (node (ref "P39") (pin "2") (pinfunction "VCC_2") (pintype "power_in"))
      (node (ref "P390") (pin "2") (pinfunction "VCC_2") (pintype "power_in"))
      (node (ref "P391") (pin "2") (pinfunction "VCC_2") (pintype "power_in"))
      (node (ref "P392") (pin "2") (pinfunction "VCC_2") (pintype "power_in"))
      (node (ref "P393") (pin "2") (pinfunction "VCC_2") (pintype "power_in"))
      (node (ref "P394") (pin "2") (pinfunction "VCC_2") (pintype "power_in"))
      (node (ref "P395") (pin "2") (pinfunction "VCC_2") (pintype "power_in"))
      (node (ref "P396") (pin "2") (pinfunction "VCC_2") (pintype "power_in"))
      (node (ref "P397") (pin "2") (pinfunction "VCC_2") (pintype "power_in"))
      (node (ref "P398") (pin "2") (pinfunction "VCC_2") (pintype "power_in"))
      (node (ref "P399") (pin "2") (pinfunction "VCC_2") (pintype "power_in"))
      (node (ref "P4") (pin "2") (pinfunction "VCC_2") (pintype "power_in"))
      (node (ref "P40") (pin "2") (pinfunction "VCC_2") (pintype "power_in"))
      (node (ref "P400") (pin "2") (pinfunction "VCC_2") (pintype "power_in"))
      (node (ref "P401") (pin "2") (pinfunction "VCC_2") (pintype "power_in"))
      (node (ref "P402") (pin "2") (pinfunction "VCC_2") (pintype "power_in"))
      (node (ref "P403") (pin "2") (pinfunction "VCC_2") (pintype "power_in"))
      (node (ref "P404") (pin "2") (pinfunction "VCC_2") (pintype "power_in"))
      (node (ref "P405") (pin "2") (pinfunction "VCC_2") (pintype "power_in"))
      (node (ref "P406") (pin "2") (pinfunction "VCC_2") (pintype "power_in"))
      (node (ref "P407") (pin "2") (pinfunction "VCC_2") (pintype "power_in"))
      (node (ref "P408") (pin "2") (pinfunction "VCC_2") (pintype "power_in"))
      (node (ref "P409") (pin "2") (pinfunction "VCC_2") (pintype "power_in"))
      (node (ref "P41") (pin "2") (pinfunction "VCC_2") (pintype "power_in"))
      (node (ref "P410") (pin "2") (pinfunction "VCC_2") (pintype "power_in"))
      (node (ref "P411") (pin "2") (pinfunction "VCC_2") (pintype "power_in"))
      (node (ref "P412") (pin "2") (pinfunction "VCC_2") (pintype "power_in"))
      (node (ref "P413") (pin "2") (pinfunction "VCC_2") (pintype "power_in"))
      (node (ref "P414") (pin "2") (pinfunction "VCC_2") (pintype "power_in"))
      (node (ref "P415") (pin "2") (pinfunction "VCC_2") (pintype "power_in"))
      (node (ref "P416") (pin "2") (pinfunction "VCC_2") (pintype "power_in"))
      (node (ref "P417") (pin "2") (pinfunction "VCC_2") (pintype "power_in"))
      (node (ref "P418") (pin "2") (pinfunction "VCC_2") (pintype "power_in"))
      (node (ref "P419") (pin "2") (pinfunction "VCC_2") (pintype "power_in"))
      (node (ref "P42") (pin "2") (pinfunction "VCC_2") (pintype "power_in"))
      (node (ref "P420") (pin "2") (pinfunction "VCC_2") (pintype "power_in"))
      (node (ref "P421") (pin "2") (pinfunction "VCC_2") (pintype "power_in"))
      (node (ref "P422") (pin "2") (pinfunction "VCC_2") (pintype "power_in"))
      (node (ref "P423") (pin "2") (pinfunction "VCC_2") (pintype "power_in"))
      (node (ref "P424") (pin "2") (pinfunction "VCC_2") (pintype "power_in"))
      (node (ref "P425") (pin "2") (pinfunction "VCC_2") (pintype "power_in"))
      (node (ref "P426") (pin "2") (pinfunction "VCC_2") (pintype "power_in"))
      (node (ref "P427") (pin "2") (pinfunction "VCC_2") (pintype "power_in"))
      (node (ref "P428") (pin "2") (pinfunction "VCC_2") (pintype "power_in"))
      (node (ref "P429") (pin "2") (pinfunction "VCC_2") (pintype "power_in"))
      (node (ref "P43") (pin "2") (pinfunction "VCC_2") (pintype "power_in"))
      (node (ref "P430") (pin "2") (pinfunction "VCC_2") (pintype "power_in"))
      (node (ref "P431") (pin "2") (pinfunction "VCC_2") (pintype "power_in"))
      (node (ref "P432") (pin "2") (pinfunction "VCC_2") (pintype "power_in"))
      (node (ref "P433") (pin "2") (pinfunction "VCC_2") (pintype "power_in"))
      (node (ref "P434") (pin "2") (pinfunction "VCC_2") (pintype "power_in"))
      (node (ref "P435") (pin "2") (pinfunction "VCC_2") (pintype "power_in"))
      (node (ref "P436") (pin "2") (pinfunction "VCC_2") (pintype "power_in"))
      (node (ref "P437") (pin "2") (pinfunction "VCC_2") (pintype "power_in"))
      (node (ref "P438") (pin "2") (pinfunction "VCC_2") (pintype "power_in"))
      (node (ref "P439") (pin "2") (pinfunction "VCC_2") (pintype "power_in"))
      (node (ref "P44") (pin "2") (pinfunction "VCC_2") (pintype "power_in"))
      (node (ref "P440") (pin "2") (pinfunction "VCC_2") (pintype "power_in"))
      (node (ref "P441") (pin "2") (pinfunction "VCC_2") (pintype "power_in"))
      (node (ref "P442") (pin "2") (pinfunction "VCC_2") (pintype "power_in"))
      (node (ref "P443") (pin "2") (pinfunction "VCC_2") (pintype "power_in"))
      (node (ref "P444") (pin "2") (pinfunction "VCC_2") (pintype "power_in"))
      (node (ref "P445") (pin "2") (pinfunction "VCC_2") (pintype "power_in"))
      (node (ref "P446") (pin "2") (pinfunction "VCC_2") (pintype "power_in"))
      (node (ref "P447") (pin "2") (pinfunction "VCC_2") (pintype "power_in"))
      (node (ref "P448") (pin "2") (pinfunction "VCC_2") (pintype "power_in"))
      (node (ref "P449") (pin "2") (pinfunction "VCC_2") (pintype "power_in"))
      (node (ref "P45") (pin "2") (pinfunction "VCC_2") (pintype "power_in"))
      (node (ref "P450") (pin "2") (pinfunction "VCC_2") (pintype "power_in"))
      (node (ref "P451") (pin "2") (pinfunction "VCC_2") (pintype "power_in"))
      (node (ref "P452") (pin "2") (pinfunction "VCC_2") (pintype "power_in"))
      (node (ref "P453") (pin "2") (pinfunction "VCC_2") (pintype "power_in"))
      (node (ref "P454") (pin "2") (pinfunction "VCC_2") (pintype "power_in"))
      (node (ref "P455") (pin "2") (pinfunction "VCC_2") (pintype "power_in"))
      (node (ref "P456") (pin "2") (pinfunction "VCC_2") (pintype "power_in"))
      (node (ref "P457") (pin "2") (pinfunction "VCC_2") (pintype "power_in"))
      (node (ref "P458") (pin "2") (pinfunction "VCC_2") (pintype "power_in"))
      (node (ref "P459") (pin "2") (pinfunction "VCC_2") (pintype "power_in"))
      (node (ref "P46") (pin "2") (pinfunction "VCC_2") (pintype "power_in"))
      (node (ref "P460") (pin "2") (pinfunction "VCC_2") (pintype "power_in"))
      (node (ref "P461") (pin "2") (pinfunction "VCC_2") (pintype "power_in"))
      (node (ref "P462") (pin "2") (pinfunction "VCC_2") (pintype "power_in"))
      (node (ref "P463") (pin "2") (pinfunction "VCC_2") (pintype "power_in"))
      (node (ref "P464") (pin "2") (pinfunction "VCC_2") (pintype "power_in"))
      (node (ref "P465") (pin "2") (pinfunction "VCC_2") (pintype "power_in"))
      (node (ref "P466") (pin "2") (pinfunction "VCC_2") (pintype "power_in"))
      (node (ref "P467") (pin "2") (pinfunction "VCC_2") (pintype "power_in"))
      (node (ref "P468") (pin "2") (pinfunction "VCC_2") (pintype "power_in"))
      (node (ref "P469") (pin "2") (pinfunction "VCC_2") (pintype "power_in"))
      (node (ref "P47") (pin "2") (pinfunction "VCC_2") (pintype "power_in"))
      (node (ref "P470") (pin "2") (pinfunction "VCC_2") (pintype "power_in"))
      (node (ref "P471") (pin "2") (pinfunction "VCC_2") (pintype "power_in"))
      (node (ref "P472") (pin "2") (pinfunction "VCC_2") (pintype "power_in"))
      (node (ref "P473") (pin "2") (pinfunction "VCC_2") (pintype "power_in"))
      (node (ref "P474") (pin "2") (pinfunction "VCC_2") (pintype "power_in"))
      (node (ref "P475") (pin "2") (pinfunction "VCC_2") (pintype "power_in"))
      (node (ref "P476") (pin "2") (pinfunction "VCC_2") (pintype "power_in"))
      (node (ref "P477") (pin "2") (pinfunction "VCC_2") (pintype "power_in"))
      (node (ref "P478") (pin "2") (pinfunction "VCC_2") (pintype "power_in"))
      (node (ref "P479") (pin "2") (pinfunction "VCC_2") (pintype "power_in"))
      (node (ref "P48") (pin "2") (pinfunction "VCC_2") (pintype "power_in"))
      (node (ref "P480") (pin "2") (pinfunction "VCC_2") (pintype "power_in"))
      (node (ref "P481") (pin "2") (pinfunction "VCC_2") (pintype "power_in"))
      (node (ref "P482") (pin "2") (pinfunction "VCC_2") (pintype "power_in"))
      (node (ref "P483") (pin "2") (pinfunction "VCC_2") (pintype "power_in"))
      (node (ref "P484") (pin "2") (pinfunction "VCC_2") (pintype "power_in"))
      (node (ref "P485") (pin "2") (pinfunction "VCC_2") (pintype "power_in"))
      (node (ref "P486") (pin "2") (pinfunction "VCC_2") (pintype "power_in"))
      (node (ref "P487") (pin "2") (pinfunction "VCC_2") (pintype "power_in"))
      (node (ref "P488") (pin "2") (pinfunction "VCC_2") (pintype "power_in"))
      (node (ref "P489") (pin "2") (pinfunction "VCC_2") (pintype "power_in"))
      (node (ref "P49") (pin "2") (pinfunction "VCC_2") (pintype "power_in"))
      (node (ref "P490") (pin "2") (pinfunction "VCC_2") (pintype "power_in"))
      (node (ref "P491") (pin "2") (pinfunction "VCC_2") (pintype "power_in"))
      (node (ref "P492") (pin "2") (pinfunction "VCC_2") (pintype "power_in"))
      (node (ref "P493") (pin "2") (pinfunction "VCC_2") (pintype "power_in"))
      (node (ref "P494") (pin "2") (pinfunction "VCC_2") (pintype "power_in"))
      (node (ref "P495") (pin "2") (pinfunction "VCC_2") (pintype "power_in"))
      (node (ref "P496") (pin "2") (pinfunction "VCC_2") (pintype "power_in"))
      (node (ref "P497") (pin "2") (pinfunction "VCC_2") (pintype "power_in"))
      (node (ref "P498") (pin "2") (pinfunction "VCC_2") (pintype "power_in"))
      (node (ref "P499") (pin "2") (pinfunction "VCC_2") (pintype "power_in"))
      (node (ref "P5") (pin "2") (pinfunction "VCC_2") (pintype "power_in"))
      (node (ref "P50") (pin "2") (pinfunction "VCC_2") (pintype "power_in"))
      (node (ref "P500") (pin "2") (pinfunction "VCC_2") (pintype "power_in"))
      (node (ref "P501") (pin "2") (pinfunction "VCC_2") (pintype "power_in"))
      (node (ref "P502") (pin "2") (pinfunction "VCC_2") (pintype "power_in"))
      (node (ref "P503") (pin "2") (pinfunction "VCC_2") (pintype "power_in"))
      (node (ref "P504") (pin "2") (pinfunction "VCC_2") (pintype "power_in"))
      (node (ref "P505") (pin "2") (pinfunction "VCC_2") (pintype "power_in"))
      (node (ref "P506") (pin "2") (pinfunction "VCC_2") (pintype "power_in"))
      (node (ref "P507") (pin "2") (pinfunction "VCC_2") (pintype "power_in"))
      (node (ref "P508") (pin "2") (pinfunction "VCC_2") (pintype "power_in"))
      (node (ref "P509") (pin "2") (pinfunction "VCC_2") (pintype "power_in"))
      (node (ref "P51") (pin "2") (pinfunction "VCC_2") (pintype "power_in"))
      (node (ref "P510") (pin "2") (pinfunction "VCC_2") (pintype "power_in"))
      (node (ref "P511") (pin "2") (pinfunction "VCC_2") (pintype "power_in"))
      (node (ref "P512") (pin "2") (pinfunction "VCC_2") (pintype "power_in"))
      (node (ref "P513") (pin "2") (pinfunction "VCC_2") (pintype "power_in"))
      (node (ref "P514") (pin "2") (pinfunction "VCC_2") (pintype "power_in"))
      (node (ref "P515") (pin "2") (pinfunction "VCC_2") (pintype "power_in"))
      (node (ref "P516") (pin "2") (pinfunction "VCC_2") (pintype "power_in"))
      (node (ref "P517") (pin "2") (pinfunction "VCC_2") (pintype "power_in"))
      (node (ref "P518") (pin "2") (pinfunction "VCC_2") (pintype "power_in"))
      (node (ref "P519") (pin "2") (pinfunction "VCC_2") (pintype "power_in"))
      (node (ref "P52") (pin "2") (pinfunction "VCC_2") (pintype "power_in"))
      (node (ref "P520") (pin "2") (pinfunction "VCC_2") (pintype "power_in"))
      (node (ref "P521") (pin "2") (pinfunction "VCC_2") (pintype "power_in"))
      (node (ref "P522") (pin "2") (pinfunction "VCC_2") (pintype "power_in"))
      (node (ref "P523") (pin "2") (pinfunction "VCC_2") (pintype "power_in"))
      (node (ref "P524") (pin "2") (pinfunction "VCC_2") (pintype "power_in"))
      (node (ref "P525") (pin "2") (pinfunction "VCC_2") (pintype "power_in"))
      (node (ref "P526") (pin "2") (pinfunction "VCC_2") (pintype "power_in"))
      (node (ref "P527") (pin "2") (pinfunction "VCC_2") (pintype "power_in"))
      (node (ref "P528") (pin "2") (pinfunction "VCC_2") (pintype "power_in"))
      (node (ref "P529") (pin "2") (pinfunction "VCC_2") (pintype "power_in"))
      (node (ref "P53") (pin "2") (pinfunction "VCC_2") (pintype "power_in"))
      (node (ref "P530") (pin "2") (pinfunction "VCC_2") (pintype "power_in"))
      (node (ref "P531") (pin "2") (pinfunction "VCC_2") (pintype "power_in"))
      (node (ref "P532") (pin "2") (pinfunction "VCC_2") (pintype "power_in"))
      (node (ref "P533") (pin "2") (pinfunction "VCC_2") (pintype "power_in"))
      (node (ref "P534") (pin "2") (pinfunction "VCC_2") (pintype "power_in"))
      (node (ref "P535") (pin "2") (pinfunction "VCC_2") (pintype "power_in"))
      (node (ref "P536") (pin "2") (pinfunction "VCC_2") (pintype "power_in"))
      (node (ref "P537") (pin "2") (pinfunction "VCC_2") (pintype "power_in"))
      (node (ref "P538") (pin "2") (pinfunction "VCC_2") (pintype "power_in"))
      (node (ref "P539") (pin "2") (pinfunction "VCC_2") (pintype "power_in"))
      (node (ref "P54") (pin "2") (pinfunction "VCC_2") (pintype "power_in"))
      (node (ref "P540") (pin "2") (pinfunction "VCC_2") (pintype "power_in"))
      (node (ref "P541") (pin "2") (pinfunction "VCC_2") (pintype "power_in"))
      (node (ref "P542") (pin "2") (pinfunction "VCC_2") (pintype "power_in"))
      (node (ref "P543") (pin "2") (pinfunction "VCC_2") (pintype "power_in"))
      (node (ref "P544") (pin "2") (pinfunction "VCC_2") (pintype "power_in"))
      (node (ref "P545") (pin "2") (pinfunction "VCC_2") (pintype "power_in"))
      (node (ref "P546") (pin "2") (pinfunction "VCC_2") (pintype "power_in"))
      (node (ref "P547") (pin "2") (pinfunction "VCC_2") (pintype "power_in"))
      (node (ref "P548") (pin "2") (pinfunction "VCC_2") (pintype "power_in"))
      (node (ref "P55") (pin "2") (pinfunction "VCC_2") (pintype "power_in"))
      (node (ref "P56") (pin "2") (pinfunction "VCC_2") (pintype "power_in"))
      (node (ref "P57") (pin "2") (pinfunction "VCC_2") (pintype "power_in"))
      (node (ref "P58") (pin "2") (pinfunction "VCC_2") (pintype "power_in"))
      (node (ref "P59") (pin "2") (pinfunction "VCC_2") (pintype "power_in"))
      (node (ref "P6") (pin "2") (pinfunction "VCC_2") (pintype "power_in"))
      (node (ref "P60") (pin "2") (pinfunction "VCC_2") (pintype "power_in"))
      (node (ref "P61") (pin "2") (pinfunction "VCC_2") (pintype "power_in"))
      (node (ref "P62") (pin "2") (pinfunction "VCC_2") (pintype "power_in"))
      (node (ref "P63") (pin "2") (pinfunction "VCC_2") (pintype "power_in"))
      (node (ref "P64") (pin "2") (pinfunction "VCC_2") (pintype "power_in"))
      (node (ref "P65") (pin "2") (pinfunction "VCC_2") (pintype "power_in"))
      (node (ref "P66") (pin "2") (pinfunction "VCC_2") (pintype "power_in"))
      (node (ref "P67") (pin "2") (pinfunction "VCC_2") (pintype "power_in"))
      (node (ref "P68") (pin "2") (pinfunction "VCC_2") (pintype "power_in"))
      (node (ref "P69") (pin "2") (pinfunction "VCC_2") (pintype "power_in"))
      (node (ref "P7") (pin "2") (pinfunction "VCC_2") (pintype "power_in"))
      (node (ref "P70") (pin "2") (pinfunction "VCC_2") (pintype "power_in"))
      (node (ref "P71") (pin "2") (pinfunction "VCC_2") (pintype "power_in"))
      (node (ref "P72") (pin "2") (pinfunction "VCC_2") (pintype "power_in"))
      (node (ref "P73") (pin "2") (pinfunction "VCC_2") (pintype "power_in"))
      (node (ref "P74") (pin "2") (pinfunction "VCC_2") (pintype "power_in"))
      (node (ref "P75") (pin "2") (pinfunction "VCC_2") (pintype "power_in"))
      (node (ref "P76") (pin "2") (pinfunction "VCC_2") (pintype "power_in"))
      (node (ref "P77") (pin "2") (pinfunction "VCC_2") (pintype "power_in"))
      (node (ref "P78") (pin "2") (pinfunction "VCC_2") (pintype "power_in"))
      (node (ref "P79") (pin "2") (pinfunction "VCC_2") (pintype "power_in"))
      (node (ref "P8") (pin "2") (pinfunction "VCC_2") (pintype "power_in"))
      (node (ref "P80") (pin "2") (pinfunction "VCC_2") (pintype "power_in"))
      (node (ref "P81") (pin "2") (pinfunction "VCC_2") (pintype "power_in"))
      (node (ref "P82") (pin "2") (pinfunction "VCC_2") (pintype "power_in"))
      (node (ref "P83") (pin "2") (pinfunction "VCC_2") (pintype "power_in"))
      (node (ref "P84") (pin "2") (pinfunction "VCC_2") (pintype "power_in"))
      (node (ref "P85") (pin "2") (pinfunction "VCC_2") (pintype "power_in"))
      (node (ref "P86") (pin "2") (pinfunction "VCC_2") (pintype "power_in"))
      (node (ref "P87") (pin "2") (pinfunction "VCC_2") (pintype "power_in"))
      (node (ref "P88") (pin "2") (pinfunction "VCC_2") (pintype "power_in"))
      (node (ref "P89") (pin "2") (pinfunction "VCC_2") (pintype "power_in"))
      (node (ref "P9") (pin "2") (pinfunction "VCC_2") (pintype "power_in"))
      (node (ref "P90") (pin "2") (pinfunction "VCC_2") (pintype "power_in"))
      (node (ref "P91") (pin "2") (pinfunction "VCC_2") (pintype "power_in"))
      (node (ref "P92") (pin "2") (pinfunction "VCC_2") (pintype "power_in"))
      (node (ref "P93") (pin "2") (pinfunction "VCC_2") (pintype "power_in"))
      (node (ref "P94") (pin "2") (pinfunction "VCC_2") (pintype "power_in"))
      (node (ref "P95") (pin "2") (pinfunction "VCC_2") (pintype "power_in"))
      (node (ref "P96") (pin "2") (pinfunction "VCC_2") (pintype "power_in"))
      (node (ref "P97") (pin "2") (pinfunction "VCC_2") (pintype "power_in"))
      (node (ref "P98") (pin "2") (pinfunction "VCC_2") (pintype "power_in"))
      (node (ref "P99") (pin "2") (pinfunction "VCC_2") (pintype "power_in"))
    )
    (net (code "4") (name "GND") (class "Default")
      (node (ref "C17") (pin "1") (pinfunction "1_1") (pintype "passive"))
      (node (ref "C18") (pin "1") (pinfunction "1_1") (pintype "passive"))
      (node (ref "C19") (pin "1") (pinfunction "1_1") (pintype "passive"))
      (node (ref "C20") (pin "1") (pinfunction "1_1") (pintype "passive"))
      (node (ref "C21") (pin "1") (pinfunction "1_1") (pintype "passive"))
      (node (ref "C22") (pin "1") (pinfunction "1_1") (pintype "passive"))
      (node (ref "C23") (pin "1") (pinfunction "1_1") (pintype "passive"))
      (node (ref "C24") (pin "1") (pinfunction "1_1") (pintype "passive"))
      (node (ref "C25") (pin "1") (pinfunction "1_1") (pintype "passive"))
      (node (ref "C26") (pin "1") (pinfunction "1_1") (pintype "passive"))
      (node (ref "C27") (pin "1") (pinfunction "1_1") (pintype "passive"))
      (node (ref "C28") (pin "1") (pinfunction "1_1") (pintype "passive"))
      (node (ref "C29") (pin "1") (pinfunction "1_1") (pintype "passive"))
      (node (ref "C30") (pin "1") (pinfunction "1_1") (pintype "passive"))
      (node (ref "C31") (pin "1") (pinfunction "1_1") (pintype "passive"))
      (node (ref "C32") (pin "1") (pinfunction "1_1") (pintype "passive"))
      (node (ref "C33") (pin "1") (pinfunction "1_1") (pintype "passive"))
      (node (ref "C34") (pin "1") (pinfunction "1_1") (pintype "passive"))
      (node (ref "C35") (pin "1") (pinfunction "1_1") (pintype "passive"))
      (node (ref "C36") (pin "1") (pinfunction "1_1") (pintype "passive"))
      (node (ref "C37") (pin "1") (pinfunction "1_1") (pintype "passive"))
      (node (ref "C38") (pin "1") (pinfunction "1_1") (pintype "passive"))
      (node (ref "C39") (pin "1") (pinfunction "1_1") (pintype "passive"))
      (node (ref "C40") (pin "1") (pinfunction "1_1") (pintype "passive"))
      (node (ref "C41") (pin "1") (pinfunction "1_1") (pintype "passive"))
      (node (ref "C42") (pin "1") (pinfunction "1_1") (pintype "passive"))
      (node (ref "C43") (pin "1") (pinfunction "1_1") (pintype "passive"))
      (node (ref "C44") (pin "1") (pinfunction "1_1") (pintype "passive"))
      (node (ref "C45") (pin "1") (pinfunction "1_1") (pintype "passive"))
      (node (ref "C46") (pin "1") (pinfunction "1_1") (pintype "passive"))
      (node (ref "C47") (pin "1") (pinfunction "1_1") (pintype "passive"))
      (node (ref "C48") (pin "1") (pinfunction "1_1") (pintype "passive"))
      (node (ref "C49") (pin "1") (pinfunction "1_1") (pintype "passive"))
      (node (ref "C50") (pin "1") (pinfunction "1_1") (pintype "passive"))
      (node (ref "C51") (pin "1") (pinfunction "1_1") (pintype "passive"))
      (node (ref "C52") (pin "1") (pinfunction "1_1") (pintype "passive"))
      (node (ref "C53") (pin "1") (pinfunction "1_1") (pintype "passive"))
      (node (ref "C54") (pin "1") (pinfunction "1_1") (pintype "passive"))
      (node (ref "C55") (pin "1") (pinfunction "1_1") (pintype "passive"))
      (node (ref "C56") (pin "1") (pinfunction "1_1") (pintype "passive"))
      (node (ref "C57") (pin "1") (pinfunction "1_1") (pintype "passive"))
      (node (ref "C58") (pin "1") (pinfunction "1_1") (pintype "passive"))
      (node (ref "P1") (pin "3") (pinfunction "GND_3") (pintype "power_in"))
      (node (ref "P10") (pin "3") (pinfunction "GND_3") (pintype "power_in"))
      (node (ref "P100") (pin "3") (pinfunction "GND_3") (pintype "power_in"))
      (node (ref "P101") (pin "3") (pinfunction "GND_3") (pintype "power_in"))
      (node (ref "P102") (pin "3") (pinfunction "GND_3") (pintype "power_in"))
      (node (ref "P103") (pin "3") (pinfunction "GND_3") (pintype "power_in"))
      (node (ref "P104") (pin "3") (pinfunction "GND_3") (pintype "power_in"))
      (node (ref "P105") (pin "3") (pinfunction "GND_3") (pintype "power_in"))
      (node (ref "P106") (pin "3") (pinfunction "GND_3") (pintype "power_in"))
      (node (ref "P107") (pin "3") (pinfunction "GND_3") (pintype "power_in"))
      (node (ref "P108") (pin "3") (pinfunction "GND_3") (pintype "power_in"))
      (node (ref "P109") (pin "3") (pinfunction "GND_3") (pintype "power_in"))
      (node (ref "P11") (pin "3") (pinfunction "GND_3") (pintype "power_in"))
      (node (ref "P110") (pin "3") (pinfunction "GND_3") (pintype "power_in"))
      (node (ref "P111") (pin "3") (pinfunction "GND_3") (pintype "power_in"))
      (node (ref "P112") (pin "3") (pinfunction "GND_3") (pintype "power_in"))
      (node (ref "P113") (pin "3") (pinfunction "GND_3") (pintype "power_in"))
      (node (ref "P114") (pin "3") (pinfunction "GND_3") (pintype "power_in"))
      (node (ref "P115") (pin "3") (pinfunction "GND_3") (pintype "power_in"))
      (node (ref "P116") (pin "3") (pinfunction "GND_3") (pintype "power_in"))
      (node (ref "P117") (pin "3") (pinfunction "GND_3") (pintype "power_in"))
      (node (ref "P118") (pin "3") (pinfunction "GND_3") (pintype "power_in"))
      (node (ref "P119") (pin "3") (pinfunction "GND_3") (pintype "power_in"))
      (node (ref "P12") (pin "3") (pinfunction "GND_3") (pintype "power_in"))
      (node (ref "P120") (pin "3") (pinfunction "GND_3") (pintype "power_in"))
      (node (ref "P121") (pin "3") (pinfunction "GND_3") (pintype "power_in"))
      (node (ref "P122") (pin "3") (pinfunction "GND_3") (pintype "power_in"))
      (node (ref "P123") (pin "3") (pinfunction "GND_3") (pintype "power_in"))
      (node (ref "P124") (pin "3") (pinfunction "GND_3") (pintype "power_in"))
      (node (ref "P125") (pin "3") (pinfunction "GND_3") (pintype "power_in"))
      (node (ref "P126") (pin "3") (pinfunction "GND_3") (pintype "power_in"))
      (node (ref "P127") (pin "3") (pinfunction "GND_3") (pintype "power_in"))
      (node (ref "P128") (pin "3") (pinfunction "GND_3") (pintype "power_in"))
      (node (ref "P129") (pin "3") (pinfunction "GND_3") (pintype "power_in"))
      (node (ref "P13") (pin "3") (pinfunction "GND_3") (pintype "power_in"))
      (node (ref "P130") (pin "3") (pinfunction "GND_3") (pintype "power_in"))
      (node (ref "P131") (pin "3") (pinfunction "GND_3") (pintype "power_in"))
      (node (ref "P132") (pin "3") (pinfunction "GND_3") (pintype "power_in"))
      (node (ref "P133") (pin "3") (pinfunction "GND_3") (pintype "power_in"))
      (node (ref "P134") (pin "3") (pinfunction "GND_3") (pintype "power_in"))
      (node (ref "P135") (pin "3") (pinfunction "GND_3") (pintype "power_in"))
      (node (ref "P136") (pin "3") (pinfunction "GND_3") (pintype "power_in"))
      (node (ref "P137") (pin "3") (pinfunction "GND_3") (pintype "power_in"))
      (node (ref "P138") (pin "3") (pinfunction "GND_3") (pintype "power_in"))
      (node (ref "P139") (pin "3") (pinfunction "GND_3") (pintype "power_in"))
      (node (ref "P14") (pin "3") (pinfunction "GND_3") (pintype "power_in"))
      (node (ref "P140") (pin "3") (pinfunction "GND_3") (pintype "power_in"))
      (node (ref "P141") (pin "3") (pinfunction "GND_3") (pintype "power_in"))
      (node (ref "P142") (pin "3") (pinfunction "GND_3") (pintype "power_in"))
      (node (ref "P143") (pin "3") (pinfunction "GND_3") (pintype "power_in"))
      (node (ref "P144") (pin "3") (pinfunction "GND_3") (pintype "power_in"))
      (node (ref "P145") (pin "3") (pinfunction "GND_3") (pintype "power_in"))
      (node (ref "P146") (pin "3") (pinfunction "GND_3") (pintype "power_in"))
      (node (ref "P147") (pin "3") (pinfunction "GND_3") (pintype "power_in"))
      (node (ref "P148") (pin "3") (pinfunction "GND_3") (pintype "power_in"))
      (node (ref "P149") (pin "3") (pinfunction "GND_3") (pintype "power_in"))
      (node (ref "P15") (pin "3") (pinfunction "GND_3") (pintype "power_in"))
      (node (ref "P150") (pin "3") (pinfunction "GND_3") (pintype "power_in"))
      (node (ref "P151") (pin "3") (pinfunction "GND_3") (pintype "power_in"))
      (node (ref "P152") (pin "3") (pinfunction "GND_3") (pintype "power_in"))
      (node (ref "P153") (pin "3") (pinfunction "GND_3") (pintype "power_in"))
      (node (ref "P154") (pin "3") (pinfunction "GND_3") (pintype "power_in"))
      (node (ref "P155") (pin "3") (pinfunction "GND_3") (pintype "power_in"))
      (node (ref "P156") (pin "3") (pinfunction "GND_3") (pintype "power_in"))
      (node (ref "P157") (pin "3") (pinfunction "GND_3") (pintype "power_in"))
      (node (ref "P158") (pin "3") (pinfunction "GND_3") (pintype "power_in"))
      (node (ref "P159") (pin "3") (pinfunction "GND_3") (pintype "power_in"))
      (node (ref "P16") (pin "3") (pinfunction "GND_3") (pintype "power_in"))
      (node (ref "P160") (pin "3") (pinfunction "GND_3") (pintype "power_in"))
      (node (ref "P161") (pin "3") (pinfunction "GND_3") (pintype "power_in"))
      (node (ref "P162") (pin "3") (pinfunction "GND_3") (pintype "power_in"))
      (node (ref "P163") (pin "3") (pinfunction "GND_3") (pintype "power_in"))
      (node (ref "P164") (pin "3") (pinfunction "GND_3") (pintype "power_in"))
      (node (ref "P165") (pin "3") (pinfunction "GND_3") (pintype "power_in"))
      (node (ref "P166") (pin "3") (pinfunction "GND_3") (pintype "power_in"))
      (node (ref "P167") (pin "3") (pinfunction "GND_3") (pintype "power_in"))
      (node (ref "P168") (pin "3") (pinfunction "GND_3") (pintype "power_in"))
      (node (ref "P169") (pin "3") (pinfunction "GND_3") (pintype "power_in"))
      (node (ref "P17") (pin "3") (pinfunction "GND_3") (pintype "power_in"))
      (node (ref "P170") (pin "3") (pinfunction "GND_3") (pintype "power_in"))
      (node (ref "P171") (pin "3") (pinfunction "GND_3") (pintype "power_in"))
      (node (ref "P172") (pin "3") (pinfunction "GND_3") (pintype "power_in"))
      (node (ref "P173") (pin "3") (pinfunction "GND_3") (pintype "power_in"))
      (node (ref "P174") (pin "3") (pinfunction "GND_3") (pintype "power_in"))
      (node (ref "P175") (pin "3") (pinfunction "GND_3") (pintype "power_in"))
      (node (ref "P176") (pin "3") (pinfunction "GND_3") (pintype "power_in"))
      (node (ref "P177") (pin "3") (pinfunction "GND_3") (pintype "power_in"))
      (node (ref "P178") (pin "3") (pinfunction "GND_3") (pintype "power_in"))
      (node (ref "P179") (pin "3") (pinfunction "GND_3") (pintype "power_in"))
      (node (ref "P18") (pin "3") (pinfunction "GND_3") (pintype "power_in"))
      (node (ref "P180") (pin "3") (pinfunction "GND_3") (pintype "power_in"))
      (node (ref "P181") (pin "3") (pinfunction "GND_3") (pintype "power_in"))
      (node (ref "P182") (pin "3") (pinfunction "GND_3") (pintype "power_in"))
      (node (ref "P183") (pin "3") (pinfunction "GND_3") (pintype "power_in"))
      (node (ref "P184") (pin "3") (pinfunction "GND_3") (pintype "power_in"))
      (node (ref "P185") (pin "3") (pinfunction "GND_3") (pintype "power_in"))
      (node (ref "P186") (pin "3") (pinfunction "GND_3") (pintype "power_in"))
      (node (ref "P187") (pin "3") (pinfunction "GND_3") (pintype "power_in"))
      (node (ref "P188") (pin "3") (pinfunction "GND_3") (pintype "power_in"))
      (node (ref "P189") (pin "3") (pinfunction "GND_3") (pintype "power_in"))
      (node (ref "P19") (pin "3") (pinfunction "GND_3") (pintype "power_in"))
      (node (ref "P190") (pin "3") (pinfunction "GND_3") (pintype "power_in"))
      (node (ref "P191") (pin "3") (pinfunction "GND_3") (pintype "power_in"))
      (node (ref "P192") (pin "3") (pinfunction "GND_3") (pintype "power_in"))
      (node (ref "P193") (pin "3") (pinfunction "GND_3") (pintype "power_in"))
      (node (ref "P194") (pin "3") (pinfunction "GND_3") (pintype "power_in"))
      (node (ref "P195") (pin "3") (pinfunction "GND_3") (pintype "power_in"))
      (node (ref "P196") (pin "3") (pinfunction "GND_3") (pintype "power_in"))
      (node (ref "P197") (pin "3") (pinfunction "GND_3") (pintype "power_in"))
      (node (ref "P198") (pin "3") (pinfunction "GND_3") (pintype "power_in"))
      (node (ref "P199") (pin "3") (pinfunction "GND_3") (pintype "power_in"))
      (node (ref "P2") (pin "3") (pinfunction "GND_3") (pintype "power_in"))
      (node (ref "P20") (pin "3") (pinfunction "GND_3") (pintype "power_in"))
      (node (ref "P200") (pin "3") (pinfunction "GND_3") (pintype "power_in"))
      (node (ref "P201") (pin "3") (pinfunction "GND_3") (pintype "power_in"))
      (node (ref "P202") (pin "3") (pinfunction "GND_3") (pintype "power_in"))
      (node (ref "P203") (pin "3") (pinfunction "GND_3") (pintype "power_in"))
      (node (ref "P204") (pin "3") (pinfunction "GND_3") (pintype "power_in"))
      (node (ref "P205") (pin "3") (pinfunction "GND_3") (pintype "power_in"))
      (node (ref "P206") (pin "3") (pinfunction "GND_3") (pintype "power_in"))
      (node (ref "P207") (pin "3") (pinfunction "GND_3") (pintype "power_in"))
      (node (ref "P208") (pin "3") (pinfunction "GND_3") (pintype "power_in"))
      (node (ref "P209") (pin "3") (pinfunction "GND_3") (pintype "power_in"))
      (node (ref "P21") (pin "3") (pinfunction "GND_3") (pintype "power_in"))
      (node (ref "P210") (pin "3") (pinfunction "GND_3") (pintype "power_in"))
      (node (ref "P211") (pin "3") (pinfunction "GND_3") (pintype "power_in"))
      (node (ref "P212") (pin "3") (pinfunction "GND_3") (pintype "power_in"))
      (node (ref "P213") (pin "3") (pinfunction "GND_3") (pintype "power_in"))
      (node (ref "P214") (pin "3") (pinfunction "GND_3") (pintype "power_in"))
      (node (ref "P215") (pin "3") (pinfunction "GND_3") (pintype "power_in"))
      (node (ref "P216") (pin "3") (pinfunction "GND_3") (pintype "power_in"))
      (node (ref "P217") (pin "3") (pinfunction "GND_3") (pintype "power_in"))
      (node (ref "P218") (pin "3") (pinfunction "GND_3") (pintype "power_in"))
      (node (ref "P219") (pin "3") (pinfunction "GND_3") (pintype "power_in"))
      (node (ref "P22") (pin "3") (pinfunction "GND_3") (pintype "power_in"))
      (node (ref "P220") (pin "3") (pinfunction "GND_3") (pintype "power_in"))
      (node (ref "P221") (pin "3") (pinfunction "GND_3") (pintype "power_in"))
      (node (ref "P222") (pin "3") (pinfunction "GND_3") (pintype "power_in"))
      (node (ref "P223") (pin "3") (pinfunction "GND_3") (pintype "power_in"))
      (node (ref "P224") (pin "3") (pinfunction "GND_3") (pintype "power_in"))
      (node (ref "P225") (pin "3") (pinfunction "GND_3") (pintype "power_in"))
      (node (ref "P226") (pin "3") (pinfunction "GND_3") (pintype "power_in"))
      (node (ref "P227") (pin "3") (pinfunction "GND_3") (pintype "power_in"))
      (node (ref "P228") (pin "3") (pinfunction "GND_3") (pintype "power_in"))
      (node (ref "P229") (pin "3") (pinfunction "GND_3") (pintype "power_in"))
      (node (ref "P23") (pin "3") (pinfunction "GND_3") (pintype "power_in"))
      (node (ref "P230") (pin "3") (pinfunction "GND_3") (pintype "power_in"))
      (node (ref "P231") (pin "3") (pinfunction "GND_3") (pintype "power_in"))
      (node (ref "P232") (pin "3") (pinfunction "GND_3") (pintype "power_in"))
      (node (ref "P233") (pin "3") (pinfunction "GND_3") (pintype "power_in"))
      (node (ref "P234") (pin "3") (pinfunction "GND_3") (pintype "power_in"))
      (node (ref "P235") (pin "3") (pinfunction "GND_3") (pintype "power_in"))
      (node (ref "P236") (pin "3") (pinfunction "GND_3") (pintype "power_in"))
      (node (ref "P237") (pin "3") (pinfunction "GND_3") (pintype "power_in"))
      (node (ref "P238") (pin "3") (pinfunction "GND_3") (pintype "power_in"))
      (node (ref "P239") (pin "3") (pinfunction "GND_3") (pintype "power_in"))
      (node (ref "P24") (pin "3") (pinfunction "GND_3") (pintype "power_in"))
      (node (ref "P240") (pin "3") (pinfunction "GND_3") (pintype "power_in"))
      (node (ref "P241") (pin "3") (pinfunction "GND_3") (pintype "power_in"))
      (node (ref "P242") (pin "3") (pinfunction "GND_3") (pintype "power_in"))
      (node (ref "P243") (pin "3") (pinfunction "GND_3") (pintype "power_in"))
      (node (ref "P244") (pin "3") (pinfunction "GND_3") (pintype "power_in"))
      (node (ref "P245") (pin "3") (pinfunction "GND_3") (pintype "power_in"))
      (node (ref "P246") (pin "3") (pinfunction "GND_3") (pintype "power_in"))
      (node (ref "P247") (pin "3") (pinfunction "GND_3") (pintype "power_in"))
      (node (ref "P248") (pin "3") (pinfunction "GND_3") (pintype "power_in"))
      (node (ref "P249") (pin "3") (pinfunction "GND_3") (pintype "power_in"))
      (node (ref "P25") (pin "3") (pinfunction "GND_3") (pintype "power_in"))
      (node (ref "P250") (pin "3") (pinfunction "GND_3") (pintype "power_in"))
      (node (ref "P251") (pin "3") (pinfunction "GND_3") (pintype "power_in"))
      (node (ref "P252") (pin "3") (pinfunction "GND_3") (pintype "power_in"))
      (node (ref "P253") (pin "3") (pinfunction "GND_3") (pintype "power_in"))
      (node (ref "P254") (pin "3") (pinfunction "GND_3") (pintype "power_in"))
      (node (ref "P255") (pin "3") (pinfunction "GND_3") (pintype "power_in"))
      (node (ref "P256") (pin "3") (pinfunction "GND_3") (pintype "power_in"))
      (node (ref "P257") (pin "3") (pinfunction "GND_3") (pintype "power_in"))
      (node (ref "P258") (pin "3") (pinfunction "GND_3") (pintype "power_in"))
      (node (ref "P259") (pin "3") (pinfunction "GND_3") (pintype "power_in"))
      (node (ref "P26") (pin "3") (pinfunction "GND_3") (pintype "power_in"))
      (node (ref "P260") (pin "3") (pinfunction "GND_3") (pintype "power_in"))
      (node (ref "P261") (pin "3") (pinfunction "GND_3") (pintype "power_in"))
      (node (ref "P262") (pin "3") (pinfunction "GND_3") (pintype "power_in"))
      (node (ref "P263") (pin "3") (pinfunction "GND_3") (pintype "power_in"))
      (node (ref "P264") (pin "3") (pinfunction "GND_3") (pintype "power_in"))
      (node (ref "P265") (pin "3") (pinfunction "GND_3") (pintype "power_in"))
      (node (ref "P266") (pin "3") (pinfunction "GND_3") (pintype "power_in"))
      (node (ref "P267") (pin "3") (pinfunction "GND_3") (pintype "power_in"))
      (node (ref "P268") (pin "3") (pinfunction "GND_3") (pintype "power_in"))
      (node (ref "P269") (pin "3") (pinfunction "GND_3") (pintype "power_in"))
      (node (ref "P27") (pin "3") (pinfunction "GND_3") (pintype "power_in"))
      (node (ref "P270") (pin "3") (pinfunction "GND_3") (pintype "power_in"))
      (node (ref "P271") (pin "3") (pinfunction "GND_3") (pintype "power_in"))
      (node (ref "P272") (pin "3") (pinfunction "GND_3") (pintype "power_in"))
      (node (ref "P273") (pin "3") (pinfunction "GND_3") (pintype "power_in"))
      (node (ref "P274") (pin "3") (pinfunction "GND_3") (pintype "power_in"))
      (node (ref "P275") (pin "3") (pinfunction "GND_3") (pintype "power_in"))
      (node (ref "P276") (pin "3") (pinfunction "GND_3") (pintype "power_in"))
      (node (ref "P277") (pin "3") (pinfunction "GND_3") (pintype "power_in"))
      (node (ref "P278") (pin "3") (pinfunction "GND_3") (pintype "power_in"))
      (node (ref "P279") (pin "3") (pinfunction "GND_3") (pintype "power_in"))
      (node (ref "P28") (pin "3") (pinfunction "GND_3") (pintype "power_in"))
      (node (ref "P280") (pin "3") (pinfunction "GND_3") (pintype "power_in"))
      (node (ref "P281") (pin "3") (pinfunction "GND_3") (pintype "power_in"))
      (node (ref "P282") (pin "3") (pinfunction "GND_3") (pintype "power_in"))
      (node (ref "P283") (pin "3") (pinfunction "GND_3") (pintype "power_in"))
      (node (ref "P284") (pin "3") (pinfunction "GND_3") (pintype "power_in"))
      (node (ref "P285") (pin "3") (pinfunction "GND_3") (pintype "power_in"))
      (node (ref "P286") (pin "3") (pinfunction "GND_3") (pintype "power_in"))
      (node (ref "P287") (pin "3") (pinfunction "GND_3") (pintype "power_in"))
      (node (ref "P288") (pin "3") (pinfunction "GND_3") (pintype "power_in"))
      (node (ref "P289") (pin "3") (pinfunction "GND_3") (pintype "power_in"))
      (node (ref "P29") (pin "3") (pinfunction "GND_3") (pintype "power_in"))
      (node (ref "P290") (pin "3") (pinfunction "GND_3") (pintype "power_in"))
      (node (ref "P291") (pin "3") (pinfunction "GND_3") (pintype "power_in"))
      (node (ref "P292") (pin "3") (pinfunction "GND_3") (pintype "power_in"))
      (node (ref "P293") (pin "3") (pinfunction "GND_3") (pintype "power_in"))
      (node (ref "P294") (pin "3") (pinfunction "GND_3") (pintype "power_in"))
      (node (ref "P295") (pin "3") (pinfunction "GND_3") (pintype "power_in"))
      (node (ref "P296") (pin "3") (pinfunction "GND_3") (pintype "power_in"))
      (node (ref "P297") (pin "3") (pinfunction "GND_3") (pintype "power_in"))
      (node (ref "P298") (pin "3") (pinfunction "GND_3") (pintype "power_in"))
      (node (ref "P299") (pin "3") (pinfunction "GND_3") (pintype "power_in"))
      (node (ref "P3") (pin "3") (pinfunction "GND_3") (pintype "power_in"))
      (node (ref "P30") (pin "3") (pinfunction "GND_3") (pintype "power_in"))
      (node (ref "P300") (pin "3") (pinfunction "GND_3") (pintype "power_in"))
      (node (ref "P301") (pin "3") (pinfunction "GND_3") (pintype "power_in"))
      (node (ref "P302") (pin "3") (pinfunction "GND_3") (pintype "power_in"))
      (node (ref "P303") (pin "3") (pinfunction "GND_3") (pintype "power_in"))
      (node (ref "P304") (pin "3") (pinfunction "GND_3") (pintype "power_in"))
      (node (ref "P305") (pin "3") (pinfunction "GND_3") (pintype "power_in"))
      (node (ref "P306") (pin "3") (pinfunction "GND_3") (pintype "power_in"))
      (node (ref "P307") (pin "3") (pinfunction "GND_3") (pintype "power_in"))
      (node (ref "P308") (pin "3") (pinfunction "GND_3") (pintype "power_in"))
      (node (ref "P309") (pin "3") (pinfunction "GND_3") (pintype "power_in"))
      (node (ref "P31") (pin "3") (pinfunction "GND_3") (pintype "power_in"))
      (node (ref "P310") (pin "3") (pinfunction "GND_3") (pintype "power_in"))
      (node (ref "P311") (pin "3") (pinfunction "GND_3") (pintype "power_in"))
      (node (ref "P312") (pin "3") (pinfunction "GND_3") (pintype "power_in"))
      (node (ref "P313") (pin "3") (pinfunction "GND_3") (pintype "power_in"))
      (node (ref "P314") (pin "3") (pinfunction "GND_3") (pintype "power_in"))
      (node (ref "P315") (pin "3") (pinfunction "GND_3") (pintype "power_in"))
      (node (ref "P316") (pin "3") (pinfunction "GND_3") (pintype "power_in"))
      (node (ref "P317") (pin "3") (pinfunction "GND_3") (pintype "power_in"))
      (node (ref "P318") (pin "3") (pinfunction "GND_3") (pintype "power_in"))
      (node (ref "P319") (pin "3") (pinfunction "GND_3") (pintype "power_in"))
      (node (ref "P32") (pin "3") (pinfunction "GND_3") (pintype "power_in"))
      (node (ref "P320") (pin "3") (pinfunction "GND_3") (pintype "power_in"))
      (node (ref "P321") (pin "3") (pinfunction "GND_3") (pintype "power_in"))
      (node (ref "P322") (pin "3") (pinfunction "GND_3") (pintype "power_in"))
      (node (ref "P323") (pin "3") (pinfunction "GND_3") (pintype "power_in"))
      (node (ref "P324") (pin "3") (pinfunction "GND_3") (pintype "power_in"))
      (node (ref "P325") (pin "3") (pinfunction "GND_3") (pintype "power_in"))
      (node (ref "P326") (pin "3") (pinfunction "GND_3") (pintype "power_in"))
      (node (ref "P327") (pin "3") (pinfunction "GND_3") (pintype "power_in"))
      (node (ref "P328") (pin "3") (pinfunction "GND_3") (pintype "power_in"))
      (node (ref "P329") (pin "3") (pinfunction "GND_3") (pintype "power_in"))
      (node (ref "P33") (pin "3") (pinfunction "GND_3") (pintype "power_in"))
      (node (ref "P330") (pin "3") (pinfunction "GND_3") (pintype "power_in"))
      (node (ref "P331") (pin "3") (pinfunction "GND_3") (pintype "power_in"))
      (node (ref "P332") (pin "3") (pinfunction "GND_3") (pintype "power_in"))
      (node (ref "P333") (pin "3") (pinfunction "GND_3") (pintype "power_in"))
      (node (ref "P334") (pin "3") (pinfunction "GND_3") (pintype "power_in"))
      (node (ref "P335") (pin "3") (pinfunction "GND_3") (pintype "power_in"))
      (node (ref "P336") (pin "3") (pinfunction "GND_3") (pintype "power_in"))
      (node (ref "P337") (pin "3") (pinfunction "GND_3") (pintype "power_in"))
      (node (ref "P338") (pin "3") (pinfunction "GND_3") (pintype "power_in"))
      (node (ref "P339") (pin "3") (pinfunction "GND_3") (pintype "power_in"))
      (node (ref "P34") (pin "3") (pinfunction "GND_3") (pintype "power_in"))
      (node (ref "P340") (pin "3") (pinfunction "GND_3") (pintype "power_in"))
      (node (ref "P341") (pin "3") (pinfunction "GND_3") (pintype "power_in"))
      (node (ref "P342") (pin "3") (pinfunction "GND_3") (pintype "power_in"))
      (node (ref "P343") (pin "3") (pinfunction "GND_3") (pintype "power_in"))
      (node (ref "P344") (pin "3") (pinfunction "GND_3") (pintype "power_in"))
      (node (ref "P345") (pin "3") (pinfunction "GND_3") (pintype "power_in"))
      (node (ref "P346") (pin "3") (pinfunction "GND_3") (pintype "power_in"))
      (node (ref "P347") (pin "3") (pinfunction "GND_3") (pintype "power_in"))
      (node (ref "P348") (pin "3") (pinfunction "GND_3") (pintype "power_in"))
      (node (ref "P349") (pin "3") (pinfunction "GND_3") (pintype "power_in"))
      (node (ref "P35") (pin "3") (pinfunction "GND_3") (pintype "power_in"))
      (node (ref "P350") (pin "3") (pinfunction "GND_3") (pintype "power_in"))
      (node (ref "P351") (pin "3") (pinfunction "GND_3") (pintype "power_in"))
      (node (ref "P352") (pin "3") (pinfunction "GND_3") (pintype "power_in"))
      (node (ref "P353") (pin "3") (pinfunction "GND_3") (pintype "power_in"))
      (node (ref "P354") (pin "3") (pinfunction "GND_3") (pintype "power_in"))
      (node (ref "P355") (pin "3") (pinfunction "GND_3") (pintype "power_in"))
      (node (ref "P356") (pin "3") (pinfunction "GND_3") (pintype "power_in"))
      (node (ref "P357") (pin "3") (pinfunction "GND_3") (pintype "power_in"))
      (node (ref "P358") (pin "3") (pinfunction "GND_3") (pintype "power_in"))
      (node (ref "P359") (pin "3") (pinfunction "GND_3") (pintype "power_in"))
      (node (ref "P36") (pin "3") (pinfunction "GND_3") (pintype "power_in"))
      (node (ref "P360") (pin "3") (pinfunction "GND_3") (pintype "power_in"))
      (node (ref "P361") (pin "3") (pinfunction "GND_3") (pintype "power_in"))
      (node (ref "P362") (pin "3") (pinfunction "GND_3") (pintype "power_in"))
      (node (ref "P363") (pin "3") (pinfunction "GND_3") (pintype "power_in"))
      (node (ref "P364") (pin "3") (pinfunction "GND_3") (pintype "power_in"))
      (node (ref "P365") (pin "3") (pinfunction "GND_3") (pintype "power_in"))
      (node (ref "P366") (pin "3") (pinfunction "GND_3") (pintype "power_in"))
      (node (ref "P367") (pin "3") (pinfunction "GND_3") (pintype "power_in"))
      (node (ref "P368") (pin "3") (pinfunction "GND_3") (pintype "power_in"))
      (node (ref "P369") (pin "3") (pinfunction "GND_3") (pintype "power_in"))
      (node (ref "P37") (pin "3") (pinfunction "GND_3") (pintype "power_in"))
      (node (ref "P370") (pin "3") (pinfunction "GND_3") (pintype "power_in"))
      (node (ref "P371") (pin "3") (pinfunction "GND_3") (pintype "power_in"))
      (node (ref "P372") (pin "3") (pinfunction "GND_3") (pintype "power_in"))
      (node (ref "P373") (pin "3") (pinfunction "GND_3") (pintype "power_in"))
      (node (ref "P374") (pin "3") (pinfunction "GND_3") (pintype "power_in"))
      (node (ref "P375") (pin "3") (pinfunction "GND_3") (pintype "power_in"))
      (node (ref "P376") (pin "3") (pinfunction "GND_3") (pintype "power_in"))
      (node (ref "P377") (pin "3") (pinfunction "GND_3") (pintype "power_in"))
      (node (ref "P378") (pin "3") (pinfunction "GND_3") (pintype "power_in"))
      (node (ref "P379") (pin "3") (pinfunction "GND_3") (pintype "power_in"))
      (node (ref "P38") (pin "3") (pinfunction "GND_3") (pintype "power_in"))
      (node (ref "P380") (pin "3") (pinfunction "GND_3") (pintype "power_in"))
      (node (ref "P381") (pin "3") (pinfunction "GND_3") (pintype "power_in"))
      (node (ref "P382") (pin "3") (pinfunction "GND_3") (pintype "power_in"))
      (node (ref "P383") (pin "3") (pinfunction "GND_3") (pintype "power_in"))
      (node (ref "P384") (pin "3") (pinfunction "GND_3") (pintype "power_in"))
      (node (ref "P385") (pin "3") (pinfunction "GND_3") (pintype "power_in"))
      (node (ref "P386") (pin "3") (pinfunction "GND_3") (pintype "power_in"))
      (node (ref "P387") (pin "3") (pinfunction "GND_3") (pintype "power_in"))
      (node (ref "P388") (pin "3") (pinfunction "GND_3") (pintype "power_in"))
      (node (ref "P389") (pin "3") (pinfunction "GND_3") (pintype "power_in"))
      (node (ref "P39") (pin "3") (pinfunction "GND_3") (pintype "power_in"))
      (node (ref "P390") (pin "3") (pinfunction "GND_3") (pintype "power_in"))
      (node (ref "P391") (pin "3") (pinfunction "GND_3") (pintype "power_in"))
      (node (ref "P392") (pin "3") (pinfunction "GND_3") (pintype "power_in"))
      (node (ref "P393") (pin "3") (pinfunction "GND_3") (pintype "power_in"))
      (node (ref "P394") (pin "3") (pinfunction "GND_3") (pintype "power_in"))
      (node (ref "P395") (pin "3") (pinfunction "GND_3") (pintype "power_in"))
      (node (ref "P396") (pin "3") (pinfunction "GND_3") (pintype "power_in"))
      (node (ref "P397") (pin "3") (pinfunction "GND_3") (pintype "power_in"))
      (node (ref "P398") (pin "3") (pinfunction "GND_3") (pintype "power_in"))
      (node (ref "P399") (pin "3") (pinfunction "GND_3") (pintype "power_in"))
      (node (ref "P4") (pin "3") (pinfunction "GND_3") (pintype "power_in"))
      (node (ref "P40") (pin "3") (pinfunction "GND_3") (pintype "power_in"))
      (node (ref "P400") (pin "3") (pinfunction "GND_3") (pintype "power_in"))
      (node (ref "P401") (pin "3") (pinfunction "GND_3") (pintype "power_in"))
      (node (ref "P402") (pin "3") (pinfunction "GND_3") (pintype "power_in"))
      (node (ref "P403") (pin "3") (pinfunction "GND_3") (pintype "power_in"))
      (node (ref "P404") (pin "3") (pinfunction "GND_3") (pintype "power_in"))
      (node (ref "P405") (pin "3") (pinfunction "GND_3") (pintype "power_in"))
      (node (ref "P406") (pin "3") (pinfunction "GND_3") (pintype "power_in"))
      (node (ref "P407") (pin "3") (pinfunction "GND_3") (pintype "power_in"))
      (node (ref "P408") (pin "3") (pinfunction "GND_3") (pintype "power_in"))
      (node (ref "P409") (pin "3") (pinfunction "GND_3") (pintype "power_in"))
      (node (ref "P41") (pin "3") (pinfunction "GND_3") (pintype "power_in"))
      (node (ref "P410") (pin "3") (pinfunction "GND_3") (pintype "power_in"))
      (node (ref "P411") (pin "3") (pinfunction "GND_3") (pintype "power_in"))
      (node (ref "P412") (pin "3") (pinfunction "GND_3") (pintype "power_in"))
      (node (ref "P413") (pin "3") (pinfunction "GND_3") (pintype "power_in"))
      (node (ref "P414") (pin "3") (pinfunction "GND_3") (pintype "power_in"))
      (node (ref "P415") (pin "3") (pinfunction "GND_3") (pintype "power_in"))
      (node (ref "P416") (pin "3") (pinfunction "GND_3") (pintype "power_in"))
      (node (ref "P417") (pin "3") (pinfunction "GND_3") (pintype "power_in"))
      (node (ref "P418") (pin "3") (pinfunction "GND_3") (pintype "power_in"))
      (node (ref "P419") (pin "3") (pinfunction "GND_3") (pintype "power_in"))
      (node (ref "P42") (pin "3") (pinfunction "GND_3") (pintype "power_in"))
      (node (ref "P420") (pin "3") (pinfunction "GND_3") (pintype "power_in"))
      (node (ref "P421") (pin "3") (pinfunction "GND_3") (pintype "power_in"))
      (node (ref "P422") (pin "3") (pinfunction "GND_3") (pintype "power_in"))
      (node (ref "P423") (pin "3") (pinfunction "GND_3") (pintype "power_in"))
      (node (ref "P424") (pin "3") (pinfunction "GND_3") (pintype "power_in"))
      (node (ref "P425") (pin "3") (pinfunction "GND_3") (pintype "power_in"))
      (node (ref "P426") (pin "3") (pinfunction "GND_3") (pintype "power_in"))
      (node (ref "P427") (pin "3") (pinfunction "GND_3") (pintype "power_in"))
      (node (ref "P428") (pin "3") (pinfunction "GND_3") (pintype "power_in"))
      (node (ref "P429") (pin "3") (pinfunction "GND_3") (pintype "power_in"))
      (node (ref "P43") (pin "3") (pinfunction "GND_3") (pintype "power_in"))
      (node (ref "P430") (pin "3") (pinfunction "GND_3") (pintype "power_in"))
      (node (ref "P431") (pin "3") (pinfunction "GND_3") (pintype "power_in"))
      (node (ref "P432") (pin "3") (pinfunction "GND_3") (pintype "power_in"))
      (node (ref "P433") (pin "3") (pinfunction "GND_3") (pintype "power_in"))
      (node (ref "P434") (pin "3") (pinfunction "GND_3") (pintype "power_in"))
      (node (ref "P435") (pin "3") (pinfunction "GND_3") (pintype "power_in"))
      (node (ref "P436") (pin "3") (pinfunction "GND_3") (pintype "power_in"))
      (node (ref "P437") (pin "3") (pinfunction "GND_3") (pintype "power_in"))
      (node (ref "P438") (pin "3") (pinfunction "GND_3") (pintype "power_in"))
      (node (ref "P439") (pin "3") (pinfunction "GND_3") (pintype "power_in"))
      (node (ref "P44") (pin "3") (pinfunction "GND_3") (pintype "power_in"))
      (node (ref "P440") (pin "3") (pinfunction "GND_3") (pintype "power_in"))
      (node (ref "P441") (pin "3") (pinfunction "GND_3") (pintype "power_in"))
      (node (ref "P442") (pin "3") (pinfunction "GND_3") (pintype "power_in"))
      (node (ref "P443") (pin "3") (pinfunction "GND_3") (pintype "power_in"))
      (node (ref "P444") (pin "3") (pinfunction "GND_3") (pintype "power_in"))
      (node (ref "P445") (pin "3") (pinfunction "GND_3") (pintype "power_in"))
      (node (ref "P446") (pin "3") (pinfunction "GND_3") (pintype "power_in"))
      (node (ref "P447") (pin "3") (pinfunction "GND_3") (pintype "power_in"))
      (node (ref "P448") (pin "3") (pinfunction "GND_3") (pintype "power_in"))
      (node (ref "P449") (pin "3") (pinfunction "GND_3") (pintype "power_in"))
      (node (ref "P45") (pin "3") (pinfunction "GND_3") (pintype "power_in"))
      (node (ref "P450") (pin "3") (pinfunction "GND_3") (pintype "power_in"))
      (node (ref "P451") (pin "3") (pinfunction "GND_3") (pintype "power_in"))
      (node (ref "P452") (pin "3") (pinfunction "GND_3") (pintype "power_in"))
      (node (ref "P453") (pin "3") (pinfunction "GND_3") (pintype "power_in"))
      (node (ref "P454") (pin "3") (pinfunction "GND_3") (pintype "power_in"))
      (node (ref "P455") (pin "3") (pinfunction "GND_3") (pintype "power_in"))
      (node (ref "P456") (pin "3") (pinfunction "GND_3") (pintype "power_in"))
      (node (ref "P457") (pin "3") (pinfunction "GND_3") (pintype "power_in"))
      (node (ref "P458") (pin "3") (pinfunction "GND_3") (pintype "power_in"))
      (node (ref "P459") (pin "3") (pinfunction "GND_3") (pintype "power_in"))
      (node (ref "P46") (pin "3") (pinfunction "GND_3") (pintype "power_in"))
      (node (ref "P460") (pin "3") (pinfunction "GND_3") (pintype "power_in"))
      (node (ref "P461") (pin "3") (pinfunction "GND_3") (pintype "power_in"))
      (node (ref "P462") (pin "3") (pinfunction "GND_3") (pintype "power_in"))
      (node (ref "P463") (pin "3") (pinfunction "GND_3") (pintype "power_in"))
      (node (ref "P464") (pin "3") (pinfunction "GND_3") (pintype "power_in"))
      (node (ref "P465") (pin "3") (pinfunction "GND_3") (pintype "power_in"))
      (node (ref "P466") (pin "3") (pinfunction "GND_3") (pintype "power_in"))
      (node (ref "P467") (pin "3") (pinfunction "GND_3") (pintype "power_in"))
      (node (ref "P468") (pin "3") (pinfunction "GND_3") (pintype "power_in"))
      (node (ref "P469") (pin "3") (pinfunction "GND_3") (pintype "power_in"))
      (node (ref "P47") (pin "3") (pinfunction "GND_3") (pintype "power_in"))
      (node (ref "P470") (pin "3") (pinfunction "GND_3") (pintype "power_in"))
      (node (ref "P471") (pin "3") (pinfunction "GND_3") (pintype "power_in"))
      (node (ref "P472") (pin "3") (pinfunction "GND_3") (pintype "power_in"))
      (node (ref "P473") (pin "3") (pinfunction "GND_3") (pintype "power_in"))
      (node (ref "P474") (pin "3") (pinfunction "GND_3") (pintype "power_in"))
      (node (ref "P475") (pin "3") (pinfunction "GND_3") (pintype "power_in"))
      (node (ref "P476") (pin "3") (pinfunction "GND_3") (pintype "power_in"))
      (node (ref "P477") (pin "3") (pinfunction "GND_3") (pintype "power_in"))
      (node (ref "P478") (pin "3") (pinfunction "GND_3") (pintype "power_in"))
      (node (ref "P479") (pin "3") (pinfunction "GND_3") (pintype "power_in"))
      (node (ref "P48") (pin "3") (pinfunction "GND_3") (pintype "power_in"))
      (node (ref "P480") (pin "3") (pinfunction "GND_3") (pintype "power_in"))
      (node (ref "P481") (pin "3") (pinfunction "GND_3") (pintype "power_in"))
      (node (ref "P482") (pin "3") (pinfunction "GND_3") (pintype "power_in"))
      (node (ref "P483") (pin "3") (pinfunction "GND_3") (pintype "power_in"))
      (node (ref "P484") (pin "3") (pinfunction "GND_3") (pintype "power_in"))
      (node (ref "P485") (pin "3") (pinfunction "GND_3") (pintype "power_in"))
      (node (ref "P486") (pin "3") (pinfunction "GND_3") (pintype "power_in"))
      (node (ref "P487") (pin "3") (pinfunction "GND_3") (pintype "power_in"))
      (node (ref "P488") (pin "3") (pinfunction "GND_3") (pintype "power_in"))
      (node (ref "P489") (pin "3") (pinfunction "GND_3") (pintype "power_in"))
      (node (ref "P49") (pin "3") (pinfunction "GND_3") (pintype "power_in"))
      (node (ref "P490") (pin "3") (pinfunction "GND_3") (pintype "power_in"))
      (node (ref "P491") (pin "3") (pinfunction "GND_3") (pintype "power_in"))
      (node (ref "P492") (pin "3") (pinfunction "GND_3") (pintype "power_in"))
      (node (ref "P493") (pin "3") (pinfunction "GND_3") (pintype "power_in"))
      (node (ref "P494") (pin "3") (pinfunction "GND_3") (pintype "power_in"))
      (node (ref "P495") (pin "3") (pinfunction "GND_3") (pintype "power_in"))
      (node (ref "P496") (pin "3") (pinfunction "GND_3") (pintype "power_in"))
      (node (ref "P497") (pin "3") (pinfunction "GND_3") (pintype "power_in"))
      (node (ref "P498") (pin "3") (pinfunction "GND_3") (pintype "power_in"))
      (node (ref "P499") (pin "3") (pinfunction "GND_3") (pintype "power_in"))
      (node (ref "P5") (pin "3") (pinfunction "GND_3") (pintype "power_in"))
      (node (ref "P50") (pin "3") (pinfunction "GND_3") (pintype "power_in"))
      (node (ref "P500") (pin "3") (pinfunction "GND_3") (pintype "power_in"))
      (node (ref "P501") (pin "3") (pinfunction "GND_3") (pintype "power_in"))
      (node (ref "P502") (pin "3") (pinfunction "GND_3") (pintype "power_in"))
      (node (ref "P503") (pin "3") (pinfunction "GND_3") (pintype "power_in"))
      (node (ref "P504") (pin "3") (pinfunction "GND_3") (pintype "power_in"))
      (node (ref "P505") (pin "3") (pinfunction "GND_3") (pintype "power_in"))
      (node (ref "P506") (pin "3") (pinfunction "GND_3") (pintype "power_in"))
      (node (ref "P507") (pin "3") (pinfunction "GND_3") (pintype "power_in"))
      (node (ref "P508") (pin "3") (pinfunction "GND_3") (pintype "power_in"))
      (node (ref "P509") (pin "3") (pinfunction "GND_3") (pintype "power_in"))
      (node (ref "P51") (pin "3") (pinfunction "GND_3") (pintype "power_in"))
      (node (ref "P510") (pin "3") (pinfunction "GND_3") (pintype "power_in"))
      (node (ref "P511") (pin "3") (pinfunction "GND_3") (pintype "power_in"))
      (node (ref "P512") (pin "3") (pinfunction "GND_3") (pintype "power_in"))
      (node (ref "P513") (pin "3") (pinfunction "GND_3") (pintype "power_in"))
      (node (ref "P514") (pin "3") (pinfunction "GND_3") (pintype "power_in"))
      (node (ref "P515") (pin "3") (pinfunction "GND_3") (pintype "power_in"))
      (node (ref "P516") (pin "3") (pinfunction "GND_3") (pintype "power_in"))
      (node (ref "P517") (pin "3") (pinfunction "GND_3") (pintype "power_in"))
      (node (ref "P518") (pin "3") (pinfunction "GND_3") (pintype "power_in"))
      (node (ref "P519") (pin "3") (pinfunction "GND_3") (pintype "power_in"))
      (node (ref "P52") (pin "3") (pinfunction "GND_3") (pintype "power_in"))
      (node (ref "P520") (pin "3") (pinfunction "GND_3") (pintype "power_in"))
      (node (ref "P521") (pin "3") (pinfunction "GND_3") (pintype "power_in"))
      (node (ref "P522") (pin "3") (pinfunction "GND_3") (pintype "power_in"))
      (node (ref "P523") (pin "3") (pinfunction "GND_3") (pintype "power_in"))
      (node (ref "P524") (pin "3") (pinfunction "GND_3") (pintype "power_in"))
      (node (ref "P525") (pin "3") (pinfunction "GND_3") (pintype "power_in"))
      (node (ref "P526") (pin "3") (pinfunction "GND_3") (pintype "power_in"))
      (node (ref "P527") (pin "3") (pinfunction "GND_3") (pintype "power_in"))
      (node (ref "P528") (pin "3") (pinfunction "GND_3") (pintype "power_in"))
      (node (ref "P529") (pin "3") (pinfunction "GND_3") (pintype "power_in"))
      (node (ref "P53") (pin "3") (pinfunction "GND_3") (pintype "power_in"))
      (node (ref "P530") (pin "3") (pinfunction "GND_3") (pintype "power_in"))
      (node (ref "P531") (pin "3") (pinfunction "GND_3") (pintype "power_in"))
      (node (ref "P532") (pin "3") (pinfunction "GND_3") (pintype "power_in"))
      (node (ref "P533") (pin "3") (pinfunction "GND_3") (pintype "power_in"))
      (node (ref "P534") (pin "3") (pinfunction "GND_3") (pintype "power_in"))
      (node (ref "P535") (pin "3") (pinfunction "GND_3") (pintype "power_in"))
      (node (ref "P536") (pin "3") (pinfunction "GND_3") (pintype "power_in"))
      (node (ref "P537") (pin "3") (pinfunction "GND_3") (pintype "power_in"))
      (node (ref "P538") (pin "3") (pinfunction "GND_3") (pintype "power_in"))
      (node (ref "P539") (pin "3") (pinfunction "GND_3") (pintype "power_in"))
      (node (ref "P54") (pin "3") (pinfunction "GND_3") (pintype "power_in"))
      (node (ref "P540") (pin "3") (pinfunction "GND_3") (pintype "power_in"))
      (node (ref "P541") (pin "3") (pinfunction "GND_3") (pintype "power_in"))
      (node (ref "P542") (pin "3") (pinfunction "GND_3") (pintype "power_in"))
      (node (ref "P543") (pin "3") (pinfunction "GND_3") (pintype "power_in"))
      (node (ref "P544") (pin "3") (pinfunction "GND_3") (pintype "power_in"))
      (node (ref "P545") (pin "3") (pinfunction "GND_3") (pintype "power_in"))
      (node (ref "P546") (pin "3") (pinfunction "GND_3") (pintype "power_in"))
      (node (ref "P547") (pin "3") (pinfunction "GND_3") (pintype "power_in"))
      (node (ref "P548") (pin "3") (pinfunction "GND_3") (pintype "power_in"))
      (node (ref "P55") (pin "3") (pinfunction "GND_3") (pintype "power_in"))
      (node (ref "P56") (pin "3") (pinfunction "GND_3") (pintype "power_in"))
      (node (ref "P57") (pin "3") (pinfunction "GND_3") (pintype "power_in"))
      (node (ref "P58") (pin "3") (pinfunction "GND_3") (pintype "power_in"))
      (node (ref "P59") (pin "3") (pinfunction "GND_3") (pintype "power_in"))
      (node (ref "P6") (pin "3") (pinfunction "GND_3") (pintype "power_in"))
      (node (ref "P60") (pin "3") (pinfunction "GND_3") (pintype "power_in"))
      (node (ref "P61") (pin "3") (pinfunction "GND_3") (pintype "power_in"))
      (node (ref "P62") (pin "3") (pinfunction "GND_3") (pintype "power_in"))
      (node (ref "P63") (pin "3") (pinfunction "GND_3") (pintype "power_in"))
      (node (ref "P64") (pin "3") (pinfunction "GND_3") (pintype "power_in"))
      (node (ref "P65") (pin "3") (pinfunction "GND_3") (pintype "power_in"))
      (node (ref "P66") (pin "3") (pinfunction "GND_3") (pintype "power_in"))
      (node (ref "P67") (pin "3") (pinfunction "GND_3") (pintype "power_in"))
      (node (ref "P68") (pin "3") (pinfunction "GND_3") (pintype "power_in"))
      (node (ref "P69") (pin "3") (pinfunction "GND_3") (pintype "power_in"))
      (node (ref "P7") (pin "3") (pinfunction "GND_3") (pintype "power_in"))
      (node (ref "P70") (pin "3") (pinfunction "GND_3") (pintype "power_in"))
      (node (ref "P71") (pin "3") (pinfunction "GND_3") (pintype "power_in"))
      (node (ref "P72") (pin "3") (pinfunction "GND_3") (pintype "power_in"))
      (node (ref "P73") (pin "3") (pinfunction "GND_3") (pintype "power_in"))
      (node (ref "P74") (pin "3") (pinfunction "GND_3") (pintype "power_in"))
      (node (ref "P75") (pin "3") (pinfunction "GND_3") (pintype "power_in"))
      (node (ref "P76") (pin "3") (pinfunction "GND_3") (pintype "power_in"))
      (node (ref "P77") (pin "3") (pinfunction "GND_3") (pintype "power_in"))
      (node (ref "P78") (pin "3") (pinfunction "GND_3") (pintype "power_in"))
      (node (ref "P79") (pin "3") (pinfunction "GND_3") (pintype "power_in"))
      (node (ref "P8") (pin "3") (pinfunction "GND_3") (pintype "power_in"))
      (node (ref "P80") (pin "3") (pinfunction "GND_3") (pintype "power_in"))
      (node (ref "P81") (pin "3") (pinfunction "GND_3") (pintype "power_in"))
      (node (ref "P82") (pin "3") (pinfunction "GND_3") (pintype "power_in"))
      (node (ref "P83") (pin "3") (pinfunction "GND_3") (pintype "power_in"))
      (node (ref "P84") (pin "3") (pinfunction "GND_3") (pintype "power_in"))
      (node (ref "P85") (pin "3") (pinfunction "GND_3") (pintype "power_in"))
      (node (ref "P86") (pin "3") (pinfunction "GND_3") (pintype "power_in"))
      (node (ref "P87") (pin "3") (pinfunction "GND_3") (pintype "power_in"))
      (node (ref "P88") (pin "3") (pinfunction "GND_3") (pintype "power_in"))
      (node (ref "P89") (pin "3") (pinfunction "GND_3") (pintype "power_in"))
      (node (ref "P9") (pin "3") (pinfunction "GND_3") (pintype "power_in"))
      (node (ref "P90") (pin "3") (pinfunction "GND_3") (pintype "power_in"))
      (node (ref "P91") (pin "3") (pinfunction "GND_3") (pintype "power_in"))
      (node (ref "P92") (pin "3") (pinfunction "GND_3") (pintype "power_in"))
      (node (ref "P93") (pin "3") (pinfunction "GND_3") (pintype "power_in"))
      (node (ref "P94") (pin "3") (pinfunction "GND_3") (pintype "power_in"))
      (node (ref "P95") (pin "3") (pinfunction "GND_3") (pintype "power_in"))
      (node (ref "P96") (pin "3") (pinfunction "GND_3") (pintype "power_in"))
      (node (ref "P97") (pin "3") (pinfunction "GND_3") (pintype "power_in"))
      (node (ref "P98") (pin "3") (pinfunction "GND_3") (pintype "power_in"))
      (node (ref "P99") (pin "3") (pinfunction "GND_3") (pintype "power_in"))
    )
    (net (code "5") (name "Net-(P1-OUT)") (class "Default")
      (node (ref "P1") (pin "1") (pinfunction "OUT_1") (pintype "passive"))
      (node (ref "P2") (pin "4") (pinfunction "IN_4") (pintype "passive"))
    )
    (net (code "6") (name "Net-(P2-OUT)") (class "Default")
      (node (ref "P2") (pin "1") (pinfunction "OUT_1") (pintype "passive"))
      (node (ref "P3") (pin "4") (pinfunction "IN_4") (pintype "passive"))
    )
    (net (code "7") (name "Net-(P3-OUT)") (class "Default")
      (node (ref "P3") (pin "1") (pinfunction "OUT_1") (pintype "passive"))
      (node (ref "P4") (pin "4") (pinfunction "IN_4") (pintype "passive"))
    )
    (net (code "8") (name "Net-(P4-OUT)") (class "Default")
      (node (ref "P4") (pin "1") (pinfunction "OUT_1") (pintype "passive"))
      (node (ref "P5") (pin "4") (pinfunction "IN_4") (pintype "passive"))
    )
    (net (code "9") (name "Net-(P5-OUT)") (class "Default")
      (node (ref "P5") (pin "1") (pinfunction "OUT_1") (pintype "passive"))
      (node (ref "P6") (pin "4") (pinfunction "IN_4") (pintype "passive"))
    )
    (net (code "10") (name "Net-(P6-OUT)") (class "Default")
      (node (ref "P6") (pin "1") (pinfunction "OUT_1") (pintype "passive"))
      (node (ref "P7") (pin "4") (pinfunction "IN_4") (pintype "passive"))
    )
    (net (code "11") (name "Net-(P7-OUT)") (class "Default")
      (node (ref "P7") (pin "1") (pinfunction "OUT_1") (pintype "passive"))
      (node (ref "P8") (pin "4") (pinfunction "IN_4") (pintype "passive"))
    )
    (net (code "12") (name "Net-(P8-OUT)") (class "Default")
      (node (ref "P8") (pin "1") (pinfunction "OUT_1") (pintype "passive"))
      (node (ref "P9") (pin "4") (pinfunction "IN_4") (pintype "passive"))
    )
    (net (code "13") (name "Net-(P10-IN)") (class "Default")
      (node (ref "P10") (pin "4") (pinfunction "IN_4") (pintype "passive"))
      (node (ref "P9") (pin "1") (pinfunction "OUT_1") (pintype "passive"))
    )
    (net (code "14") (name "Net-(P10-OUT)") (class "Default")
      (node (ref "P10") (pin "1") (pinfunction "OUT_1") (pintype "passive"))
      (node (ref "P11") (pin "4") (pinfunction "IN_4") (pintype "passive"))
    )
    (net (code "15") (name "Net-(P11-OUT)") (class "Default")
      (node (ref "P11") (pin "1") (pinfunction "OUT_1") (pintype "passive"))
      (node (ref "P12") (pin "4") (pinfunction "IN_4") (pintype "passive"))
    )
    (net (code "16") (name "Net-(P12-OUT)") (class "Default")
      (node (ref "P12") (pin "1") (pinfunction "OUT_1") (pintype "passive"))
      (node (ref "P13") (pin "4") (pinfunction "IN_4") (pintype "passive"))
    )
    (net (code "17") (name "Net-(P13-OUT)") (class "Default")
      (node (ref "P13") (pin "1") (pinfunction "OUT_1") (pintype "passive"))
      (node (ref "P14") (pin "4") (pinfunction "IN_4") (pintype "passive"))
    )
    (net (code "18") (name "Net-(P14-OUT)") (class "Default")
      (node (ref "P14") (pin "1") (pinfunction "OUT_1") (pintype "passive"))
      (node (ref "P15") (pin "4") (pinfunction "IN_4") (pintype "passive"))
    )
    (net (code "19") (name "Net-(P15-OUT)") (class "Default")
      (node (ref "P15") (pin "1") (pinfunction "OUT_1") (pintype "passive"))
      (node (ref "P16") (pin "4") (pinfunction "IN_4") (pintype "passive"))
    )
    (net (code "20") (name "Net-(P16-OUT)") (class "Default")
      (node (ref "P16") (pin "1") (pinfunction "OUT_1") (pintype "passive"))
      (node (ref "P17") (pin "4") (pinfunction "IN_4") (pintype "passive"))
    )
    (net (code "21") (name "Net-(P17-OUT)") (class "Default")
      (node (ref "P17") (pin "1") (pinfunction "OUT_1") (pintype "passive"))
      (node (ref "P18") (pin "4") (pinfunction "IN_4") (pintype "passive"))
    )
    (net (code "22") (name "Net-(P18-OUT)") (class "Default")
      (node (ref "P18") (pin "1") (pinfunction "OUT_1") (pintype "passive"))
      (node (ref "P19") (pin "4") (pinfunction "IN_4") (pintype "passive"))
    )
    (net (code "23") (name "Net-(P19-OUT)") (class "Default")
      (node (ref "P19") (pin "1") (pinfunction "OUT_1") (pintype "passive"))
      (node (ref "P20") (pin "4") (pinfunction "IN_4") (pintype "passive"))
    )
    (net (code "24") (name "Net-(P20-OUT)") (class "Default")
      (node (ref "P20") (pin "1") (pinfunction "OUT_1") (pintype "passive"))
      (node (ref "P21") (pin "4") (pinfunction "IN_4") (pintype "passive"))
    )
    (net (code "25") (name "Net-(P21-OUT)") (class "Default")
      (node (ref "P21") (pin "1") (pinfunction "OUT_1") (pintype "passive"))
      (node (ref "P22") (pin "4") (pinfunction "IN_4") (pintype "passive"))
    )
    (net (code "26") (name "Net-(P22-OUT)") (class "Default")
      (node (ref "P22") (pin "1") (pinfunction "OUT_1") (pintype "passive"))
      (node (ref "P23") (pin "4") (pinfunction "IN_4") (pintype "passive"))
    )
    (net (code "27") (name "Net-(P23-OUT)") (class "Default")
      (node (ref "P23") (pin "1") (pinfunction "OUT_1") (pintype "passive"))
      (node (ref "P24") (pin "4") (pinfunction "IN_4") (pintype "passive"))
    )
    (net (code "28") (name "Net-(P24-OUT)") (class "Default")
      (node (ref "P24") (pin "1") (pinfunction "OUT_1") (pintype "passive"))
      (node (ref "P25") (pin "4") (pinfunction "IN_4") (pintype "passive"))
    )
    (net (code "29") (name "Net-(P25-OUT)") (class "Default")
      (node (ref "P25") (pin "1") (pinfunction "OUT_1") (pintype "passive"))
      (node (ref "P26") (pin "4") (pinfunction "IN_4") (pintype "passive"))
    )
    (net (code "30") (name "Net-(P26-OUT)") (class "Default")
      (node (ref "P26") (pin "1") (pinfunction "OUT_1") (pintype "passive"))
      (node (ref "P27") (pin "4") (pinfunction "IN_4") (pintype "passive"))
    )
    (net (code "31") (name "Net-(P27-OUT)") (class "Default")
      (node (ref "P27") (pin "1") (pinfunction "OUT_1") (pintype "passive"))
      (node (ref "P28") (pin "4") (pinfunction "IN_4") (pintype "passive"))
    )
    (net (code "32") (name "Net-(P28-OUT)") (class "Default")
      (node (ref "P28") (pin "1") (pinfunction "OUT_1") (pintype "passive"))
      (node (ref "P29") (pin "4") (pinfunction "IN_4") (pintype "passive"))
    )
    (net (code "33") (name "Net-(P29-OUT)") (class "Default")
      (node (ref "P29") (pin "1") (pinfunction "OUT_1") (pintype "passive"))
      (node (ref "P30") (pin "4") (pinfunction "IN_4") (pintype "passive"))
    )
    (net (code "34") (name "Net-(P30-OUT)") (class "Default")
      (node (ref "P30") (pin "1") (pinfunction "OUT_1") (pintype "passive"))
      (node (ref "P31") (pin "4") (pinfunction "IN_4") (pintype "passive"))
    )
    (net (code "35") (name "Net-(P31-OUT)") (class "Default")
      (node (ref "P31") (pin "1") (pinfunction "OUT_1") (pintype "passive"))
      (node (ref "P32") (pin "4") (pinfunction "IN_4") (pintype "passive"))
    )
    (net (code "36") (name "Net-(P32-OUT)") (class "Default")
      (node (ref "P32") (pin "1") (pinfunction "OUT_1") (pintype "passive"))
      (node (ref "P33") (pin "4") (pinfunction "IN_4") (pintype "passive"))
    )
    (net (code "37") (name "Net-(P33-OUT)") (class "Default")
      (node (ref "P33") (pin "1") (pinfunction "OUT_1") (pintype "passive"))
      (node (ref "P34") (pin "4") (pinfunction "IN_4") (pintype "passive"))
    )
    (net (code "38") (name "Net-(P34-OUT)") (class "Default")
      (node (ref "P34") (pin "1") (pinfunction "OUT_1") (pintype "passive"))
      (node (ref "P35") (pin "4") (pinfunction "IN_4") (pintype "passive"))
    )
    (net (code "39") (name "Net-(P35-OUT)") (class "Default")
      (node (ref "P35") (pin "1") (pinfunction "OUT_1") (pintype "passive"))
      (node (ref "P36") (pin "4") (pinfunction "IN_4") (pintype "passive"))
    )
    (net (code "40") (name "Net-(P36-OUT)") (class "Default")
      (node (ref "P36") (pin "1") (pinfunction "OUT_1") (pintype "passive"))
      (node (ref "P37") (pin "4") (pinfunction "IN_4") (pintype "passive"))
    )
    (net (code "41") (name "Net-(P37-OUT)") (class "Default")
      (node (ref "P37") (pin "1") (pinfunction "OUT_1") (pintype "passive"))
      (node (ref "P38") (pin "4") (pinfunction "IN_4") (pintype "passive"))
    )
    (net (code "42") (name "Net-(P38-OUT)") (class "Default")
      (node (ref "P38") (pin "1") (pinfunction "OUT_1") (pintype "passive"))
      (node (ref "P39") (pin "4") (pinfunction "IN_4") (pintype "passive"))
    )
    (net (code "43") (name "Net-(P39-OUT)") (class "Default")
      (node (ref "P39") (pin "1") (pinfunction "OUT_1") (pintype "passive"))
      (node (ref "P40") (pin "4") (pinfunction "IN_4") (pintype "passive"))
    )
    (net (code "44") (name "Net-(P40-OUT)") (class "Default")
      (node (ref "P40") (pin "1") (pinfunction "OUT_1") (pintype "passive"))
      (node (ref "P41") (pin "4") (pinfunction "IN_4") (pintype "passive"))
    )
    (net (code "45") (name "Net-(P41-OUT)") (class "Default")
      (node (ref "P41") (pin "1") (pinfunction "OUT_1") (pintype "passive"))
      (node (ref "P42") (pin "4") (pinfunction "IN_4") (pintype "passive"))
    )
    (net (code "46") (name "Net-(P42-OUT)") (class "Default")
      (node (ref "P42") (pin "1") (pinfunction "OUT_1") (pintype "passive"))
      (node (ref "P43") (pin "4") (pinfunction "IN_4") (pintype "passive"))
    )
    (net (code "47") (name "Net-(P43-OUT)") (class "Default")
      (node (ref "P43") (pin "1") (pinfunction "OUT_1") (pintype "passive"))
      (node (ref "P44") (pin "4") (pinfunction "IN_4") (pintype "passive"))
    )
    (net (code "48") (name "Net-(P44-OUT)") (class "Default")
      (node (ref "P44") (pin "1") (pinfunction "OUT_1") (pintype "passive"))
      (node (ref "P45") (pin "4") (pinfunction "IN_4") (pintype "passive"))
    )
    (net (code "49") (name "Net-(P45-OUT)") (class "Default")
      (node (ref "P45") (pin "1") (pinfunction "OUT_1") (pintype "passive"))
      (node (ref "P46") (pin "4") (pinfunction "IN_4") (pintype "passive"))
    )
    (net (code "50") (name "Net-(P46-OUT)") (class "Default")
      (node (ref "P46") (pin "1") (pinfunction "OUT_1") (pintype "passive"))
      (node (ref "P47") (pin "4") (pinfunction "IN_4") (pintype "passive"))
    )
    (net (code "51") (name "Net-(P47-OUT)") (class "Default")
      (node (ref "P47") (pin "1") (pinfunction "OUT_1") (pintype "passive"))
      (node (ref "P48") (pin "4") (pinfunction "IN_4") (pintype "passive"))
    )
    (net (code "52") (name "Net-(P48-OUT)") (class "Default")
      (node (ref "P48") (pin "1") (pinfunction "OUT_1") (pintype "passive"))
      (node (ref "P49") (pin "4") (pinfunction "IN_4") (pintype "passive"))
    )
    (net (code "53") (name "Net-(P49-OUT)") (class "Default")
      (node (ref "P49") (pin "1") (pinfunction "OUT_1") (pintype "passive"))
      (node (ref "P50") (pin "4") (pinfunction "IN_4") (pintype "passive"))
    )
    (net (code "54") (name "Net-(P50-OUT)") (class "Default")
      (node (ref "P50") (pin "1") (pinfunction "OUT_1") (pintype "passive"))
      (node (ref "P51") (pin "4") (pinfunction "IN_4") (pintype "passive"))
    )
    (net (code "55") (name "Net-(P51-OUT)") (class "Default")
      (node (ref "P51") (pin "1") (pinfunction "OUT_1") (pintype "passive"))
      (node (ref "P52") (pin "4") (pinfunction "IN_4") (pintype "passive"))
    )
    (net (code "56") (name "Net-(P52-OUT)") (class "Default")
      (node (ref "P52") (pin "1") (pinfunction "OUT_1") (pintype "passive"))
      (node (ref "P53") (pin "4") (pinfunction "IN_4") (pintype "passive"))
    )
    (net (code "57") (name "Net-(P53-OUT)") (class "Default")
      (node (ref "P53") (pin "1") (pinfunction "OUT_1") (pintype "passive"))
      (node (ref "P54") (pin "4") (pinfunction "IN_4") (pintype "passive"))
    )
    (net (code "58") (name "Net-(P54-OUT)") (class "Default")
      (node (ref "P54") (pin "1") (pinfunction "OUT_1") (pintype "passive"))
      (node (ref "P55") (pin "4") (pinfunction "IN_4") (pintype "passive"))
    )
    (net (code "59") (name "Net-(P55-OUT)") (class "Default")
      (node (ref "P55") (pin "1") (pinfunction "OUT_1") (pintype "passive"))
      (node (ref "P56") (pin "4") (pinfunction "IN_4") (pintype "passive"))
    )
    (net (code "60") (name "Net-(P56-OUT)") (class "Default")
      (node (ref "P56") (pin "1") (pinfunction "OUT_1") (pintype "passive"))
      (node (ref "P57") (pin "4") (pinfunction "IN_4") (pintype "passive"))
    )
    (net (code "61") (name "Net-(P57-OUT)") (class "Default")
      (node (ref "P57") (pin "1") (pinfunction "OUT_1") (pintype "passive"))
      (node (ref "P58") (pin "4") (pinfunction "IN_4") (pintype "passive"))
    )
    (net (code "62") (name "Net-(P58-OUT)") (class "Default")
      (node (ref "P58") (pin "1") (pinfunction "OUT_1") (pintype "passive"))
      (node (ref "P59") (pin "4") (pinfunction "IN_4") (pintype "passive"))
    )
    (net (code "63") (name "Net-(P59-OUT)") (class "Default")
      (node (ref "P59") (pin "1") (pinfunction "OUT_1") (pintype "passive"))
      (node (ref "P60") (pin "4") (pinfunction "IN_4") (pintype "passive"))
    )
    (net (code "64") (name "Net-(P60-OUT)") (class "Default")
      (node (ref "P60") (pin "1") (pinfunction "OUT_1") (pintype "passive"))
      (node (ref "P61") (pin "4") (pinfunction "IN_4") (pintype "passive"))
    )
    (net (code "65") (name "Net-(P61-OUT)") (class "Default")
      (node (ref "P61") (pin "1") (pinfunction "OUT_1") (pintype "passive"))
      (node (ref "P62") (pin "4") (pinfunction "IN_4") (pintype "passive"))
    )
    (net (code "66") (name "Net-(P62-OUT)") (class "Default")
      (node (ref "P62") (pin "1") (pinfunction "OUT_1") (pintype "passive"))
      (node (ref "P63") (pin "4") (pinfunction "IN_4") (pintype "passive"))
    )
    (net (code "67") (name "Net-(P63-OUT)") (class "Default")
      (node (ref "P63") (pin "1") (pinfunction "OUT_1") (pintype "passive"))
      (node (ref "P64") (pin "4") (pinfunction "IN_4") (pintype "passive"))
    )
    (net (code "68") (name "Net-(P64-OUT)") (class "Default")
      (node (ref "P64") (pin "1") (pinfunction "OUT_1") (pintype "passive"))
      (node (ref "P65") (pin "4") (pinfunction "IN_4") (pintype "passive"))
    )
    (net (code "69") (name "Net-(P65-OUT)") (class "Default")
      (node (ref "P65") (pin "1") (pinfunction "OUT_1") (pintype "passive"))
      (node (ref "P66") (pin "4") (pinfunction "IN_4") (pintype "passive"))
    )
    (net (code "70") (name "Net-(P66-OUT)") (class "Default")
      (node (ref "P66") (pin "1") (pinfunction "OUT_1") (pintype "passive"))
      (node (ref "P67") (pin "4") (pinfunction "IN_4") (pintype "passive"))
    )
    (net (code "71") (name "Net-(P67-OUT)") (class "Default")
      (node (ref "P67") (pin "1") (pinfunction "OUT_1") (pintype "passive"))
      (node (ref "P68") (pin "4") (pinfunction "IN_4") (pintype "passive"))
    )
    (net (code "72") (name "Net-(P68-OUT)") (class "Default")
      (node (ref "P68") (pin "1") (pinfunction "OUT_1") (pintype "passive"))
      (node (ref "P69") (pin "4") (pinfunction "IN_4") (pintype "passive"))
    )
    (net (code "73") (name "Net-(P69-OUT)") (class "Default")
      (node (ref "P69") (pin "1") (pinfunction "OUT_1") (pintype "passive"))
      (node (ref "P70") (pin "4") (pinfunction "IN_4") (pintype "passive"))
    )
    (net (code "74") (name "Net-(P70-OUT)") (class "Default")
      (node (ref "P70") (pin "1") (pinfunction "OUT_1") (pintype "passive"))
      (node (ref "P71") (pin "4") (pinfunction "IN_4") (pintype "passive"))
    )
    (net (code "75") (name "Net-(P71-OUT)") (class "Default")
      (node (ref "P71") (pin "1") (pinfunction "OUT_1") (pintype "passive"))
      (node (ref "P72") (pin "4") (pinfunction "IN_4") (pintype "passive"))
    )
    (net (code "76") (name "Net-(P72-OUT)") (class "Default")
      (node (ref "P72") (pin "1") (pinfunction "OUT_1") (pintype "passive"))
      (node (ref "P73") (pin "4") (pinfunction "IN_4") (pintype "passive"))
    )
    (net (code "77") (name "Net-(P73-OUT)") (class "Default")
      (node (ref "P73") (pin "1") (pinfunction "OUT_1") (pintype "passive"))
      (node (ref "P74") (pin "4") (pinfunction "IN_4") (pintype "passive"))
    )
    (net (code "78") (name "Net-(P74-OUT)") (class "Default")
      (node (ref "P74") (pin "1") (pinfunction "OUT_1") (pintype "passive"))
      (node (ref "P75") (pin "4") (pinfunction "IN_4") (pintype "passive"))
    )
    (net (code "79") (name "Net-(P75-OUT)") (class "Default")
      (node (ref "P75") (pin "1") (pinfunction "OUT_1") (pintype "passive"))
      (node (ref "P76") (pin "4") (pinfunction "IN_4") (pintype "passive"))
    )
    (net (code "80") (name "Net-(P76-OUT)") (class "Default")
      (node (ref "P76") (pin "1") (pinfunction "OUT_1") (pintype "passive"))
      (node (ref "P77") (pin "4") (pinfunction "IN_4") (pintype "passive"))
    )
    (net (code "81") (name "Net-(P77-OUT)") (class "Default")
      (node (ref "P77") (pin "1") (pinfunction "OUT_1") (pintype "passive"))
      (node (ref "P78") (pin "4") (pinfunction "IN_4") (pintype "passive"))
    )
    (net (code "82") (name "Net-(P78-OUT)") (class "Default")
      (node (ref "P78") (pin "1") (pinfunction "OUT_1") (pintype "passive"))
      (node (ref "P79") (pin "4") (pinfunction "IN_4") (pintype "passive"))
    )
    (net (code "83") (name "Net-(P79-OUT)") (class "Default")
      (node (ref "P79") (pin "1") (pinfunction "OUT_1") (pintype "passive"))
      (node (ref "P80") (pin "4") (pinfunction "IN_4") (pintype "passive"))
    )
    (net (code "84") (name "Net-(P80-OUT)") (class "Default")
      (node (ref "P80") (pin "1") (pinfunction "OUT_1") (pintype "passive"))
      (node (ref "P81") (pin "4") (pinfunction "IN_4") (pintype "passive"))
    )
    (net (code "85") (name "Net-(P81-OUT)") (class "Default")
      (node (ref "P81") (pin "1") (pinfunction "OUT_1") (pintype "passive"))
      (node (ref "P82") (pin "4") (pinfunction "IN_4") (pintype "passive"))
    )
    (net (code "86") (name "Net-(P82-OUT)") (class "Default")
      (node (ref "P82") (pin "1") (pinfunction "OUT_1") (pintype "passive"))
      (node (ref "P83") (pin "4") (pinfunction "IN_4") (pintype "passive"))
    )
    (net (code "87") (name "Net-(P83-OUT)") (class "Default")
      (node (ref "P83") (pin "1") (pinfunction "OUT_1") (pintype "passive"))
      (node (ref "P84") (pin "4") (pinfunction "IN_4") (pintype "passive"))
    )
    (net (code "88") (name "Net-(P84-OUT)") (class "Default")
      (node (ref "P84") (pin "1") (pinfunction "OUT_1") (pintype "passive"))
      (node (ref "P85") (pin "4") (pinfunction "IN_4") (pintype "passive"))
    )
    (net (code "89") (name "Net-(P85-OUT)") (class "Default")
      (node (ref "P85") (pin "1") (pinfunction "OUT_1") (pintype "passive"))
      (node (ref "P86") (pin "4") (pinfunction "IN_4") (pintype "passive"))
    )
    (net (code "90") (name "Net-(P86-OUT)") (class "Default")
      (node (ref "P86") (pin "1") (pinfunction "OUT_1") (pintype "passive"))
      (node (ref "P87") (pin "4") (pinfunction "IN_4") (pintype "passive"))
    )
    (net (code "91") (name "Net-(P87-OUT)") (class "Default")
      (node (ref "P87") (pin "1") (pinfunction "OUT_1") (pintype "passive"))
      (node (ref "P88") (pin "4") (pinfunction "IN_4") (pintype "passive"))
    )
    (net (code "92") (name "Net-(P88-OUT)") (class "Default")
      (node (ref "P88") (pin "1") (pinfunction "OUT_1") (pintype "passive"))
      (node (ref "P89") (pin "4") (pinfunction "IN_4") (pintype "passive"))
    )
    (net (code "93") (name "Net-(P89-OUT)") (class "Default")
      (node (ref "P89") (pin "1") (pinfunction "OUT_1") (pintype "passive"))
      (node (ref "P90") (pin "4") (pinfunction "IN_4") (pintype "passive"))
    )
    (net (code "94") (name "Net-(P90-OUT)") (class "Default")
      (node (ref "P90") (pin "1") (pinfunction "OUT_1") (pintype "passive"))
      (node (ref "P91") (pin "4") (pinfunction "IN_4") (pintype "passive"))
    )
    (net (code "95") (name "Net-(P91-OUT)") (class "Default")
      (node (ref "P91") (pin "1") (pinfunction "OUT_1") (pintype "passive"))
      (node (ref "P92") (pin "4") (pinfunction "IN_4") (pintype "passive"))
    )
    (net (code "96") (name "Net-(P92-OUT)") (class "Default")
      (node (ref "P92") (pin "1") (pinfunction "OUT_1") (pintype "passive"))
      (node (ref "P93") (pin "4") (pinfunction "IN_4") (pintype "passive"))
    )
    (net (code "97") (name "Net-(P93-OUT)") (class "Default")
      (node (ref "P93") (pin "1") (pinfunction "OUT_1") (pintype "passive"))
      (node (ref "P94") (pin "4") (pinfunction "IN_4") (pintype "passive"))
    )
    (net (code "98") (name "Net-(P94-OUT)") (class "Default")
      (node (ref "P94") (pin "1") (pinfunction "OUT_1") (pintype "passive"))
      (node (ref "P95") (pin "4") (pinfunction "IN_4") (pintype "passive"))
    )
    (net (code "99") (name "Net-(P95-OUT)") (class "Default")
      (node (ref "P95") (pin "1") (pinfunction "OUT_1") (pintype "passive"))
      (node (ref "P96") (pin "4") (pinfunction "IN_4") (pintype "passive"))
    )
    (net (code "100") (name "Net-(P96-OUT)") (class "Default")
      (node (ref "P96") (pin "1") (pinfunction "OUT_1") (pintype "passive"))
      (node (ref "P97") (pin "4") (pinfunction "IN_4") (pintype "passive"))
    )
    (net (code "101") (name "Net-(P97-OUT)") (class "Default")
      (node (ref "P97") (pin "1") (pinfunction "OUT_1") (pintype "passive"))
      (node (ref "P98") (pin "4") (pinfunction "IN_4") (pintype "passive"))
    )
    (net (code "102") (name "Net-(P98-OUT)") (class "Default")
      (node (ref "P98") (pin "1") (pinfunction "OUT_1") (pintype "passive"))
      (node (ref "P99") (pin "4") (pinfunction "IN_4") (pintype "passive"))
    )
    (net (code "103") (name "Net-(P100-IN)") (class "Default")
      (node (ref "P100") (pin "4") (pinfunction "IN_4") (pintype "passive"))
      (node (ref "P99") (pin "1") (pinfunction "OUT_1") (pintype "passive"))
    )
    (net (code "104") (name "Net-(P100-OUT)") (class "Default")
      (node (ref "P100") (pin "1") (pinfunction "OUT_1") (pintype "passive"))
      (node (ref "P101") (pin "4") (pinfunction "IN_4") (pintype "passive"))
    )
    (net (code "105") (name "Net-(P101-OUT)") (class "Default")
      (node (ref "P101") (pin "1") (pinfunction "OUT_1") (pintype "passive"))
      (node (ref "P102") (pin "4") (pinfunction "IN_4") (pintype "passive"))
    )
    (net (code "106") (name "Net-(P102-OUT)") (class "Default")
      (node (ref "P102") (pin "1") (pinfunction "OUT_1") (pintype "passive"))
      (node (ref "P103") (pin "4") (pinfunction "IN_4") (pintype "passive"))
    )
    (net (code "107") (name "Net-(P103-OUT)") (class "Default")
      (node (ref "P103") (pin "1") (pinfunction "OUT_1") (pintype "passive"))
      (node (ref "P104") (pin "4") (pinfunction "IN_4") (pintype "passive"))
    )
    (net (code "108") (name "Net-(P104-OUT)") (class "Default")
      (node (ref "P104") (pin "1") (pinfunction "OUT_1") (pintype "passive"))
      (node (ref "P105") (pin "4") (pinfunction "IN_4") (pintype "passive"))
    )
    (net (code "109") (name "Net-(P105-OUT)") (class "Default")
      (node (ref "P105") (pin "1") (pinfunction "OUT_1") (pintype "passive"))
      (node (ref "P106") (pin "4") (pinfunction "IN_4") (pintype "passive"))
    )
    (net (code "110") (name "Net-(P106-OUT)") (class "Default")
      (node (ref "P106") (pin "1") (pinfunction "OUT_1") (pintype "passive"))
      (node (ref "P107") (pin "4") (pinfunction "IN_4") (pintype "passive"))
    )
    (net (code "111") (name "Net-(P107-OUT)") (class "Default")
      (node (ref "P107") (pin "1") (pinfunction "OUT_1") (pintype "passive"))
      (node (ref "P108") (pin "4") (pinfunction "IN_4") (pintype "passive"))
    )
    (net (code "112") (name "Net-(P108-OUT)") (class "Default")
      (node (ref "P108") (pin "1") (pinfunction "OUT_1") (pintype "passive"))
      (node (ref "P109") (pin "4") (pinfunction "IN_4") (pintype "passive"))
    )
    (net (code "113") (name "Net-(P109-OUT)") (class "Default")
      (node (ref "P109") (pin "1") (pinfunction "OUT_1") (pintype "passive"))
      (node (ref "P110") (pin "4") (pinfunction "IN_4") (pintype "passive"))
    )
    (net (code "114") (name "Net-(P110-OUT)") (class "Default")
      (node (ref "P110") (pin "1") (pinfunction "OUT_1") (pintype "passive"))
      (node (ref "P111") (pin "4") (pinfunction "IN_4") (pintype "passive"))
    )
    (net (code "115") (name "Net-(P111-OUT)") (class "Default")
      (node (ref "P111") (pin "1") (pinfunction "OUT_1") (pintype "passive"))
      (node (ref "P112") (pin "4") (pinfunction "IN_4") (pintype "passive"))
    )
    (net (code "116") (name "Net-(P112-OUT)") (class "Default")
      (node (ref "P112") (pin "1") (pinfunction "OUT_1") (pintype "passive"))
      (node (ref "P113") (pin "4") (pinfunction "IN_4") (pintype "passive"))
    )
    (net (code "117") (name "Net-(P113-OUT)") (class "Default")
      (node (ref "P113") (pin "1") (pinfunction "OUT_1") (pintype "passive"))
      (node (ref "P114") (pin "4") (pinfunction "IN_4") (pintype "passive"))
    )
    (net (code "118") (name "Net-(P114-OUT)") (class "Default")
      (node (ref "P114") (pin "1") (pinfunction "OUT_1") (pintype "passive"))
      (node (ref "P115") (pin "4") (pinfunction "IN_4") (pintype "passive"))
    )
    (net (code "119") (name "Net-(P115-OUT)") (class "Default")
      (node (ref "P115") (pin "1") (pinfunction "OUT_1") (pintype "passive"))
      (node (ref "P116") (pin "4") (pinfunction "IN_4") (pintype "passive"))
    )
    (net (code "120") (name "Net-(P116-OUT)") (class "Default")
      (node (ref "P116") (pin "1") (pinfunction "OUT_1") (pintype "passive"))
      (node (ref "P117") (pin "4") (pinfunction "IN_4") (pintype "passive"))
    )
    (net (code "121") (name "Net-(P117-OUT)") (class "Default")
      (node (ref "P117") (pin "1") (pinfunction "OUT_1") (pintype "passive"))
      (node (ref "P118") (pin "4") (pinfunction "IN_4") (pintype "passive"))
    )
    (net (code "122") (name "Net-(P118-OUT)") (class "Default")
      (node (ref "P118") (pin "1") (pinfunction "OUT_1") (pintype "passive"))
      (node (ref "P119") (pin "4") (pinfunction "IN_4") (pintype "passive"))
    )
    (net (code "123") (name "Net-(P119-OUT)") (class "Default")
      (node (ref "P119") (pin "1") (pinfunction "OUT_1") (pintype "passive"))
      (node (ref "P120") (pin "4") (pinfunction "IN_4") (pintype "passive"))
    )
    (net (code "124") (name "Net-(P120-OUT)") (class "Default")
      (node (ref "P120") (pin "1") (pinfunction "OUT_1") (pintype "passive"))
      (node (ref "P121") (pin "4") (pinfunction "IN_4") (pintype "passive"))
    )
    (net (code "125") (name "Net-(P121-OUT)") (class "Default")
      (node (ref "P121") (pin "1") (pinfunction "OUT_1") (pintype "passive"))
      (node (ref "P122") (pin "4") (pinfunction "IN_4") (pintype "passive"))
    )
    (net (code "126") (name "Net-(P122-OUT)") (class "Default")
      (node (ref "P122") (pin "1") (pinfunction "OUT_1") (pintype "passive"))
      (node (ref "P123") (pin "4") (pinfunction "IN_4") (pintype "passive"))
    )
    (net (code "127") (name "Net-(P123-OUT)") (class "Default")
      (node (ref "P123") (pin "1") (pinfunction "OUT_1") (pintype "passive"))
      (node (ref "P124") (pin "4") (pinfunction "IN_4") (pintype "passive"))
    )
    (net (code "128") (name "Net-(P124-OUT)") (class "Default")
      (node (ref "P124") (pin "1") (pinfunction "OUT_1") (pintype "passive"))
      (node (ref "P125") (pin "4") (pinfunction "IN_4") (pintype "passive"))
    )
    (net (code "129") (name "Net-(P125-OUT)") (class "Default")
      (node (ref "P125") (pin "1") (pinfunction "OUT_1") (pintype "passive"))
      (node (ref "P126") (pin "4") (pinfunction "IN_4") (pintype "passive"))
    )
    (net (code "130") (name "Net-(P126-OUT)") (class "Default")
      (node (ref "P126") (pin "1") (pinfunction "OUT_1") (pintype "passive"))
      (node (ref "P127") (pin "4") (pinfunction "IN_4") (pintype "passive"))
    )
    (net (code "131") (name "Net-(P127-OUT)") (class "Default")
      (node (ref "P127") (pin "1") (pinfunction "OUT_1") (pintype "passive"))
      (node (ref "P128") (pin "4") (pinfunction "IN_4") (pintype "passive"))
    )
    (net (code "132") (name "Net-(P128-OUT)") (class "Default")
      (node (ref "P128") (pin "1") (pinfunction "OUT_1") (pintype "passive"))
      (node (ref "P129") (pin "4") (pinfunction "IN_4") (pintype "passive"))
    )
    (net (code "133") (name "Net-(P129-OUT)") (class "Default")
      (node (ref "P129") (pin "1") (pinfunction "OUT_1") (pintype "passive"))
      (node (ref "P130") (pin "4") (pinfunction "IN_4") (pintype "passive"))
    )
    (net (code "134") (name "Net-(P130-OUT)") (class "Default")
      (node (ref "P130") (pin "1") (pinfunction "OUT_1") (pintype "passive"))
      (node (ref "P131") (pin "4") (pinfunction "IN_4") (pintype "passive"))
    )
    (net (code "135") (name "Net-(P131-OUT)") (class "Default")
      (node (ref "P131") (pin "1") (pinfunction "OUT_1") (pintype "passive"))
      (node (ref "P132") (pin "4") (pinfunction "IN_4") (pintype "passive"))
    )
    (net (code "136") (name "Net-(P132-OUT)") (class "Default")
      (node (ref "P132") (pin "1") (pinfunction "OUT_1") (pintype "passive"))
      (node (ref "P133") (pin "4") (pinfunction "IN_4") (pintype "passive"))
    )
    (net (code "137") (name "Net-(P133-OUT)") (class "Default")
      (node (ref "P133") (pin "1") (pinfunction "OUT_1") (pintype "passive"))
      (node (ref "P134") (pin "4") (pinfunction "IN_4") (pintype "passive"))
    )
    (net (code "138") (name "Net-(P134-OUT)") (class "Default")
      (node (ref "P134") (pin "1") (pinfunction "OUT_1") (pintype "passive"))
      (node (ref "P135") (pin "4") (pinfunction "IN_4") (pintype "passive"))
    )
    (net (code "139") (name "Net-(P135-OUT)") (class "Default")
      (node (ref "P135") (pin "1") (pinfunction "OUT_1") (pintype "passive"))
      (node (ref "P136") (pin "4") (pinfunction "IN_4") (pintype "passive"))
    )
    (net (code "140") (name "Net-(P136-OUT)") (class "Default")
      (node (ref "P136") (pin "1") (pinfunction "OUT_1") (pintype "passive"))
      (node (ref "P137") (pin "4") (pinfunction "IN_4") (pintype "passive"))
    )
    (net (code "141") (name "Net-(P137-OUT)") (class "Default")
      (node (ref "P137") (pin "1") (pinfunction "OUT_1") (pintype "passive"))
      (node (ref "P138") (pin "4") (pinfunction "IN_4") (pintype "passive"))
    )
    (net (code "142") (name "Net-(P138-OUT)") (class "Default")
      (node (ref "P138") (pin "1") (pinfunction "OUT_1") (pintype "passive"))
      (node (ref "P139") (pin "4") (pinfunction "IN_4") (pintype "passive"))
    )
    (net (code "143") (name "Net-(P139-OUT)") (class "Default")
      (node (ref "P139") (pin "1") (pinfunction "OUT_1") (pintype "passive"))
      (node (ref "P140") (pin "4") (pinfunction "IN_4") (pintype "passive"))
    )
    (net (code "144") (name "Net-(P140-OUT)") (class "Default")
      (node (ref "P140") (pin "1") (pinfunction "OUT_1") (pintype "passive"))
      (node (ref "P141") (pin "4") (pinfunction "IN_4") (pintype "passive"))
    )
    (net (code "145") (name "Net-(P141-OUT)") (class "Default")
      (node (ref "P141") (pin "1") (pinfunction "OUT_1") (pintype "passive"))
      (node (ref "P142") (pin "4") (pinfunction "IN_4") (pintype "passive"))
    )
    (net (code "146") (name "Net-(P142-OUT)") (class "Default")
      (node (ref "P142") (pin "1") (pinfunction "OUT_1") (pintype "passive"))
      (node (ref "P143") (pin "4") (pinfunction "IN_4") (pintype "passive"))
    )
    (net (code "147") (name "Net-(P143-OUT)") (class "Default")
      (node (ref "P143") (pin "1") (pinfunction "OUT_1") (pintype "passive"))
      (node (ref "P144") (pin "4") (pinfunction "IN_4") (pintype "passive"))
    )
    (net (code "148") (name "Net-(P144-OUT)") (class "Default")
      (node (ref "P144") (pin "1") (pinfunction "OUT_1") (pintype "passive"))
      (node (ref "P145") (pin "4") (pinfunction "IN_4") (pintype "passive"))
    )
    (net (code "149") (name "Net-(P145-OUT)") (class "Default")
      (node (ref "P145") (pin "1") (pinfunction "OUT_1") (pintype "passive"))
      (node (ref "P146") (pin "4") (pinfunction "IN_4") (pintype "passive"))
    )
    (net (code "150") (name "Net-(P146-OUT)") (class "Default")
      (node (ref "P146") (pin "1") (pinfunction "OUT_1") (pintype "passive"))
      (node (ref "P147") (pin "4") (pinfunction "IN_4") (pintype "passive"))
    )
    (net (code "151") (name "Net-(P147-OUT)") (class "Default")
      (node (ref "P147") (pin "1") (pinfunction "OUT_1") (pintype "passive"))
      (node (ref "P148") (pin "4") (pinfunction "IN_4") (pintype "passive"))
    )
    (net (code "152") (name "Net-(P148-OUT)") (class "Default")
      (node (ref "P148") (pin "1") (pinfunction "OUT_1") (pintype "passive"))
      (node (ref "P149") (pin "4") (pinfunction "IN_4") (pintype "passive"))
    )
    (net (code "153") (name "Net-(P149-OUT)") (class "Default")
      (node (ref "P149") (pin "1") (pinfunction "OUT_1") (pintype "passive"))
      (node (ref "P150") (pin "4") (pinfunction "IN_4") (pintype "passive"))
    )
    (net (code "154") (name "Net-(P150-OUT)") (class "Default")
      (node (ref "P150") (pin "1") (pinfunction "OUT_1") (pintype "passive"))
      (node (ref "P151") (pin "4") (pinfunction "IN_4") (pintype "passive"))
    )
    (net (code "155") (name "Net-(P151-OUT)") (class "Default")
      (node (ref "P151") (pin "1") (pinfunction "OUT_1") (pintype "passive"))
      (node (ref "P152") (pin "4") (pinfunction "IN_4") (pintype "passive"))
    )
    (net (code "156") (name "Net-(P152-OUT)") (class "Default")
      (node (ref "P152") (pin "1") (pinfunction "OUT_1") (pintype "passive"))
      (node (ref "P153") (pin "4") (pinfunction "IN_4") (pintype "passive"))
    )
    (net (code "157") (name "Net-(P153-OUT)") (class "Default")
      (node (ref "P153") (pin "1") (pinfunction "OUT_1") (pintype "passive"))
      (node (ref "P154") (pin "4") (pinfunction "IN_4") (pintype "passive"))
    )
    (net (code "158") (name "Net-(P154-OUT)") (class "Default")
      (node (ref "P154") (pin "1") (pinfunction "OUT_1") (pintype "passive"))
      (node (ref "P155") (pin "4") (pinfunction "IN_4") (pintype "passive"))
    )
    (net (code "159") (name "Net-(P155-OUT)") (class "Default")
      (node (ref "P155") (pin "1") (pinfunction "OUT_1") (pintype "passive"))
      (node (ref "P156") (pin "4") (pinfunction "IN_4") (pintype "passive"))
    )
    (net (code "160") (name "Net-(P156-OUT)") (class "Default")
      (node (ref "P156") (pin "1") (pinfunction "OUT_1") (pintype "passive"))
      (node (ref "P157") (pin "4") (pinfunction "IN_4") (pintype "passive"))
    )
    (net (code "161") (name "Net-(P157-OUT)") (class "Default")
      (node (ref "P157") (pin "1") (pinfunction "OUT_1") (pintype "passive"))
      (node (ref "P158") (pin "4") (pinfunction "IN_4") (pintype "passive"))
    )
    (net (code "162") (name "Net-(P158-OUT)") (class "Default")
      (node (ref "P158") (pin "1") (pinfunction "OUT_1") (pintype "passive"))
      (node (ref "P159") (pin "4") (pinfunction "IN_4") (pintype "passive"))
    )
    (net (code "163") (name "Net-(P159-OUT)") (class "Default")
      (node (ref "P159") (pin "1") (pinfunction "OUT_1") (pintype "passive"))
      (node (ref "P160") (pin "4") (pinfunction "IN_4") (pintype "passive"))
    )
    (net (code "164") (name "Net-(P160-OUT)") (class "Default")
      (node (ref "P160") (pin "1") (pinfunction "OUT_1") (pintype "passive"))
      (node (ref "P161") (pin "4") (pinfunction "IN_4") (pintype "passive"))
    )
    (net (code "165") (name "Net-(P161-OUT)") (class "Default")
      (node (ref "P161") (pin "1") (pinfunction "OUT_1") (pintype "passive"))
      (node (ref "P162") (pin "4") (pinfunction "IN_4") (pintype "passive"))
    )
    (net (code "166") (name "Net-(P162-OUT)") (class "Default")
      (node (ref "P162") (pin "1") (pinfunction "OUT_1") (pintype "passive"))
      (node (ref "P163") (pin "4") (pinfunction "IN_4") (pintype "passive"))
    )
    (net (code "167") (name "Net-(P163-OUT)") (class "Default")
      (node (ref "P163") (pin "1") (pinfunction "OUT_1") (pintype "passive"))
      (node (ref "P164") (pin "4") (pinfunction "IN_4") (pintype "passive"))
    )
    (net (code "168") (name "Net-(P164-OUT)") (class "Default")
      (node (ref "P164") (pin "1") (pinfunction "OUT_1") (pintype "passive"))
      (node (ref "P165") (pin "4") (pinfunction "IN_4") (pintype "passive"))
    )
    (net (code "169") (name "Net-(P165-OUT)") (class "Default")
      (node (ref "P165") (pin "1") (pinfunction "OUT_1") (pintype "passive"))
      (node (ref "P166") (pin "4") (pinfunction "IN_4") (pintype "passive"))
    )
    (net (code "170") (name "Net-(P166-OUT)") (class "Default")
      (node (ref "P166") (pin "1") (pinfunction "OUT_1") (pintype "passive"))
      (node (ref "P167") (pin "4") (pinfunction "IN_4") (pintype "passive"))
    )
    (net (code "171") (name "Net-(P167-OUT)") (class "Default")
      (node (ref "P167") (pin "1") (pinfunction "OUT_1") (pintype "passive"))
      (node (ref "P168") (pin "4") (pinfunction "IN_4") (pintype "passive"))
    )
    (net (code "172") (name "Net-(P168-OUT)") (class "Default")
      (node (ref "P168") (pin "1") (pinfunction "OUT_1") (pintype "passive"))
      (node (ref "P169") (pin "4") (pinfunction "IN_4") (pintype "passive"))
    )
    (net (code "173") (name "Net-(P169-OUT)") (class "Default")
      (node (ref "P169") (pin "1") (pinfunction "OUT_1") (pintype "passive"))
      (node (ref "P170") (pin "4") (pinfunction "IN_4") (pintype "passive"))
    )
    (net (code "174") (name "Net-(P170-OUT)") (class "Default")
      (node (ref "P170") (pin "1") (pinfunction "OUT_1") (pintype "passive"))
      (node (ref "P171") (pin "4") (pinfunction "IN_4") (pintype "passive"))
    )
    (net (code "175") (name "Net-(P171-OUT)") (class "Default")
      (node (ref "P171") (pin "1") (pinfunction "OUT_1") (pintype "passive"))
      (node (ref "P172") (pin "4") (pinfunction "IN_4") (pintype "passive"))
    )
    (net (code "176") (name "Net-(P172-OUT)") (class "Default")
      (node (ref "P172") (pin "1") (pinfunction "OUT_1") (pintype "passive"))
      (node (ref "P173") (pin "4") (pinfunction "IN_4") (pintype "passive"))
    )
    (net (code "177") (name "Net-(P173-OUT)") (class "Default")
      (node (ref "P173") (pin "1") (pinfunction "OUT_1") (pintype "passive"))
      (node (ref "P174") (pin "4") (pinfunction "IN_4") (pintype "passive"))
    )
    (net (code "178") (name "Net-(P174-OUT)") (class "Default")
      (node (ref "P174") (pin "1") (pinfunction "OUT_1") (pintype "passive"))
      (node (ref "P175") (pin "4") (pinfunction "IN_4") (pintype "passive"))
    )
    (net (code "179") (name "Net-(P175-OUT)") (class "Default")
      (node (ref "P175") (pin "1") (pinfunction "OUT_1") (pintype "passive"))
      (node (ref "P176") (pin "4") (pinfunction "IN_4") (pintype "passive"))
    )
    (net (code "180") (name "Net-(P176-OUT)") (class "Default")
      (node (ref "P176") (pin "1") (pinfunction "OUT_1") (pintype "passive"))
      (node (ref "P177") (pin "4") (pinfunction "IN_4") (pintype "passive"))
    )
    (net (code "181") (name "Net-(P177-OUT)") (class "Default")
      (node (ref "P177") (pin "1") (pinfunction "OUT_1") (pintype "passive"))
      (node (ref "P178") (pin "4") (pinfunction "IN_4") (pintype "passive"))
    )
    (net (code "182") (name "Net-(P178-OUT)") (class "Default")
      (node (ref "P178") (pin "1") (pinfunction "OUT_1") (pintype "passive"))
      (node (ref "P179") (pin "4") (pinfunction "IN_4") (pintype "passive"))
    )
    (net (code "183") (name "Net-(P179-OUT)") (class "Default")
      (node (ref "P179") (pin "1") (pinfunction "OUT_1") (pintype "passive"))
      (node (ref "P180") (pin "4") (pinfunction "IN_4") (pintype "passive"))
    )
    (net (code "184") (name "Net-(P180-OUT)") (class "Default")
      (node (ref "P180") (pin "1") (pinfunction "OUT_1") (pintype "passive"))
      (node (ref "P181") (pin "4") (pinfunction "IN_4") (pintype "passive"))
    )
    (net (code "185") (name "Net-(P181-OUT)") (class "Default")
      (node (ref "P181") (pin "1") (pinfunction "OUT_1") (pintype "passive"))
      (node (ref "P182") (pin "4") (pinfunction "IN_4") (pintype "passive"))
    )
    (net (code "186") (name "Net-(P182-OUT)") (class "Default")
      (node (ref "P182") (pin "1") (pinfunction "OUT_1") (pintype "passive"))
      (node (ref "P183") (pin "4") (pinfunction "IN_4") (pintype "passive"))
    )
    (net (code "187") (name "Net-(P183-OUT)") (class "Default")
      (node (ref "P183") (pin "1") (pinfunction "OUT_1") (pintype "passive"))
      (node (ref "P184") (pin "4") (pinfunction "IN_4") (pintype "passive"))
    )
    (net (code "188") (name "Net-(P184-OUT)") (class "Default")
      (node (ref "P184") (pin "1") (pinfunction "OUT_1") (pintype "passive"))
      (node (ref "P185") (pin "4") (pinfunction "IN_4") (pintype "passive"))
    )
    (net (code "189") (name "Net-(P185-OUT)") (class "Default")
      (node (ref "P185") (pin "1") (pinfunction "OUT_1") (pintype "passive"))
      (node (ref "P186") (pin "4") (pinfunction "IN_4") (pintype "passive"))
    )
    (net (code "190") (name "Net-(P186-OUT)") (class "Default")
      (node (ref "P186") (pin "1") (pinfunction "OUT_1") (pintype "passive"))
      (node (ref "P187") (pin "4") (pinfunction "IN_4") (pintype "passive"))
    )
    (net (code "191") (name "Net-(P187-OUT)") (class "Default")
      (node (ref "P187") (pin "1") (pinfunction "OUT_1") (pintype "passive"))
      (node (ref "P188") (pin "4") (pinfunction "IN_4") (pintype "passive"))
    )
    (net (code "192") (name "Net-(P188-OUT)") (class "Default")
      (node (ref "P188") (pin "1") (pinfunction "OUT_1") (pintype "passive"))
      (node (ref "P189") (pin "4") (pinfunction "IN_4") (pintype "passive"))
    )
    (net (code "193") (name "Net-(P189-OUT)") (class "Default")
      (node (ref "P189") (pin "1") (pinfunction "OUT_1") (pintype "passive"))
      (node (ref "P190") (pin "4") (pinfunction "IN_4") (pintype "passive"))
    )
    (net (code "194") (name "Net-(P190-OUT)") (class "Default")
      (node (ref "P190") (pin "1") (pinfunction "OUT_1") (pintype "passive"))
      (node (ref "P191") (pin "4") (pinfunction "IN_4") (pintype "passive"))
    )
    (net (code "195") (name "Net-(P191-OUT)") (class "Default")
      (node (ref "P191") (pin "1") (pinfunction "OUT_1") (pintype "passive"))
      (node (ref "P192") (pin "4") (pinfunction "IN_4") (pintype "passive"))
    )
    (net (code "196") (name "Net-(P192-OUT)") (class "Default")
      (node (ref "P192") (pin "1") (pinfunction "OUT_1") (pintype "passive"))
      (node (ref "P193") (pin "4") (pinfunction "IN_4") (pintype "passive"))
    )
    (net (code "197") (name "Net-(P193-OUT)") (class "Default")
      (node (ref "P193") (pin "1") (pinfunction "OUT_1") (pintype "passive"))
      (node (ref "P194") (pin "4") (pinfunction "IN_4") (pintype "passive"))
    )
    (net (code "198") (name "Net-(P194-OUT)") (class "Default")
      (node (ref "P194") (pin "1") (pinfunction "OUT_1") (pintype "passive"))
      (node (ref "P195") (pin "4") (pinfunction "IN_4") (pintype "passive"))
    )
    (net (code "199") (name "Net-(P195-OUT)") (class "Default")
      (node (ref "P195") (pin "1") (pinfunction "OUT_1") (pintype "passive"))
      (node (ref "P196") (pin "4") (pinfunction "IN_4") (pintype "passive"))
    )
    (net (code "200") (name "Net-(P196-OUT)") (class "Default")
      (node (ref "P196") (pin "1") (pinfunction "OUT_1") (pintype "passive"))
      (node (ref "P197") (pin "4") (pinfunction "IN_4") (pintype "passive"))
    )
    (net (code "201") (name "Net-(P197-OUT)") (class "Default")
      (node (ref "P197") (pin "1") (pinfunction "OUT_1") (pintype "passive"))
      (node (ref "P198") (pin "4") (pinfunction "IN_4") (pintype "passive"))
    )
    (net (code "202") (name "Net-(P198-OUT)") (class "Default")
      (node (ref "P198") (pin "1") (pinfunction "OUT_1") (pintype "passive"))
      (node (ref "P199") (pin "4") (pinfunction "IN_4") (pintype "passive"))
    )
    (net (code "203") (name "Net-(P199-OUT)") (class "Default")
      (node (ref "P199") (pin "1") (pinfunction "OUT_1") (pintype "passive"))
      (node (ref "P200") (pin "4") (pinfunction "IN_4") (pintype "passive"))
    )
    (net (code "204") (name "Net-(P200-OUT)") (class "Default")
      (node (ref "P200") (pin "1") (pinfunction "OUT_1") (pintype "passive"))
      (node (ref "P201") (pin "4") (pinfunction "IN_4") (pintype "passive"))
    )
    (net (code "205") (name "Net-(P201-OUT)") (class "Default")
      (node (ref "P201") (pin "1") (pinfunction "OUT_1") (pintype "passive"))
      (node (ref "P202") (pin "4") (pinfunction "IN_4") (pintype "passive"))
    )
    (net (code "206") (name "Net-(P202-OUT)") (class "Default")
      (node (ref "P202") (pin "1") (pinfunction "OUT_1") (pintype "passive"))
      (node (ref "P203") (pin "4") (pinfunction "IN_4") (pintype "passive"))
    )
    (net (code "207") (name "Net-(P203-OUT)") (class "Default")
      (node (ref "P203") (pin "1") (pinfunction "OUT_1") (pintype "passive"))
      (node (ref "P204") (pin "4") (pinfunction "IN_4") (pintype "passive"))
    )
    (net (code "208") (name "Net-(P204-OUT)") (class "Default")
      (node (ref "P204") (pin "1") (pinfunction "OUT_1") (pintype "passive"))
      (node (ref "P205") (pin "4") (pinfunction "IN_4") (pintype "passive"))
    )
    (net (code "209") (name "Net-(P205-OUT)") (class "Default")
      (node (ref "P205") (pin "1") (pinfunction "OUT_1") (pintype "passive"))
      (node (ref "P206") (pin "4") (pinfunction "IN_4") (pintype "passive"))
    )
    (net (code "210") (name "Net-(P206-OUT)") (class "Default")
      (node (ref "P206") (pin "1") (pinfunction "OUT_1") (pintype "passive"))
      (node (ref "P207") (pin "4") (pinfunction "IN_4") (pintype "passive"))
    )
    (net (code "211") (name "Net-(P207-OUT)") (class "Default")
      (node (ref "P207") (pin "1") (pinfunction "OUT_1") (pintype "passive"))
      (node (ref "P208") (pin "4") (pinfunction "IN_4") (pintype "passive"))
    )
    (net (code "212") (name "Net-(P208-OUT)") (class "Default")
      (node (ref "P208") (pin "1") (pinfunction "OUT_1") (pintype "passive"))
      (node (ref "P209") (pin "4") (pinfunction "IN_4") (pintype "passive"))
    )
    (net (code "213") (name "Net-(P209-OUT)") (class "Default")
      (node (ref "P209") (pin "1") (pinfunction "OUT_1") (pintype "passive"))
      (node (ref "P210") (pin "4") (pinfunction "IN_4") (pintype "passive"))
    )
    (net (code "214") (name "Net-(P210-OUT)") (class "Default")
      (node (ref "P210") (pin "1") (pinfunction "OUT_1") (pintype "passive"))
      (node (ref "P211") (pin "4") (pinfunction "IN_4") (pintype "passive"))
    )
    (net (code "215") (name "Net-(P211-OUT)") (class "Default")
      (node (ref "P211") (pin "1") (pinfunction "OUT_1") (pintype "passive"))
      (node (ref "P212") (pin "4") (pinfunction "IN_4") (pintype "passive"))
    )
    (net (code "216") (name "Net-(P212-OUT)") (class "Default")
      (node (ref "P212") (pin "1") (pinfunction "OUT_1") (pintype "passive"))
      (node (ref "P213") (pin "4") (pinfunction "IN_4") (pintype "passive"))
    )
    (net (code "217") (name "Net-(P213-OUT)") (class "Default")
      (node (ref "P213") (pin "1") (pinfunction "OUT_1") (pintype "passive"))
      (node (ref "P214") (pin "4") (pinfunction "IN_4") (pintype "passive"))
    )
    (net (code "218") (name "Net-(P214-OUT)") (class "Default")
      (node (ref "P214") (pin "1") (pinfunction "OUT_1") (pintype "passive"))
      (node (ref "P215") (pin "4") (pinfunction "IN_4") (pintype "passive"))
    )
    (net (code "219") (name "Net-(P215-OUT)") (class "Default")
      (node (ref "P215") (pin "1") (pinfunction "OUT_1") (pintype "passive"))
      (node (ref "P216") (pin "4") (pinfunction "IN_4") (pintype "passive"))
    )
    (net (code "220") (name "Net-(P216-OUT)") (class "Default")
      (node (ref "P216") (pin "1") (pinfunction "OUT_1") (pintype "passive"))
      (node (ref "P217") (pin "4") (pinfunction "IN_4") (pintype "passive"))
    )
    (net (code "221") (name "Net-(P217-OUT)") (class "Default")
      (node (ref "P217") (pin "1") (pinfunction "OUT_1") (pintype "passive"))
      (node (ref "P218") (pin "4") (pinfunction "IN_4") (pintype "passive"))
    )
    (net (code "222") (name "Net-(P218-OUT)") (class "Default")
      (node (ref "P218") (pin "1") (pinfunction "OUT_1") (pintype "passive"))
      (node (ref "P219") (pin "4") (pinfunction "IN_4") (pintype "passive"))
    )
    (net (code "223") (name "Net-(P219-OUT)") (class "Default")
      (node (ref "P219") (pin "1") (pinfunction "OUT_1") (pintype "passive"))
      (node (ref "P220") (pin "4") (pinfunction "IN_4") (pintype "passive"))
    )
    (net (code "224") (name "Net-(P220-OUT)") (class "Default")
      (node (ref "P220") (pin "1") (pinfunction "OUT_1") (pintype "passive"))
      (node (ref "P221") (pin "4") (pinfunction "IN_4") (pintype "passive"))
    )
    (net (code "225") (name "Net-(P221-OUT)") (class "Default")
      (node (ref "P221") (pin "1") (pinfunction "OUT_1") (pintype "passive"))
      (node (ref "P222") (pin "4") (pinfunction "IN_4") (pintype "passive"))
    )
    (net (code "226") (name "Net-(P222-OUT)") (class "Default")
      (node (ref "P222") (pin "1") (pinfunction "OUT_1") (pintype "passive"))
      (node (ref "P223") (pin "4") (pinfunction "IN_4") (pintype "passive"))
    )
    (net (code "227") (name "Net-(P223-OUT)") (class "Default")
      (node (ref "P223") (pin "1") (pinfunction "OUT_1") (pintype "passive"))
      (node (ref "P224") (pin "4") (pinfunction "IN_4") (pintype "passive"))
    )
    (net (code "228") (name "Net-(P224-OUT)") (class "Default")
      (node (ref "P224") (pin "1") (pinfunction "OUT_1") (pintype "passive"))
      (node (ref "P225") (pin "4") (pinfunction "IN_4") (pintype "passive"))
    )
    (net (code "229") (name "Net-(P225-OUT)") (class "Default")
      (node (ref "P225") (pin "1") (pinfunction "OUT_1") (pintype "passive"))
      (node (ref "P226") (pin "4") (pinfunction "IN_4") (pintype "passive"))
    )
    (net (code "230") (name "Net-(P226-OUT)") (class "Default")
      (node (ref "P226") (pin "1") (pinfunction "OUT_1") (pintype "passive"))
      (node (ref "P227") (pin "4") (pinfunction "IN_4") (pintype "passive"))
    )
    (net (code "231") (name "Net-(P227-OUT)") (class "Default")
      (node (ref "P227") (pin "1") (pinfunction "OUT_1") (pintype "passive"))
      (node (ref "P228") (pin "4") (pinfunction "IN_4") (pintype "passive"))
    )
    (net (code "232") (name "Net-(P228-OUT)") (class "Default")
      (node (ref "P228") (pin "1") (pinfunction "OUT_1") (pintype "passive"))
      (node (ref "P229") (pin "4") (pinfunction "IN_4") (pintype "passive"))
    )
    (net (code "233") (name "Net-(P229-OUT)") (class "Default")
      (node (ref "P229") (pin "1") (pinfunction "OUT_1") (pintype "passive"))
      (node (ref "P230") (pin "4") (pinfunction "IN_4") (pintype "passive"))
    )
    (net (code "234") (name "Net-(P230-OUT)") (class "Default")
      (node (ref "P230") (pin "1") (pinfunction "OUT_1") (pintype "passive"))
      (node (ref "P231") (pin "4") (pinfunction "IN_4") (pintype "passive"))
    )
    (net (code "235") (name "Net-(P231-OUT)") (class "Default")
      (node (ref "P231") (pin "1") (pinfunction "OUT_1") (pintype "passive"))
      (node (ref "P232") (pin "4") (pinfunction "IN_4") (pintype "passive"))
    )
    (net (code "236") (name "Net-(P232-OUT)") (class "Default")
      (node (ref "P232") (pin "1") (pinfunction "OUT_1") (pintype "passive"))
      (node (ref "P233") (pin "4") (pinfunction "IN_4") (pintype "passive"))
    )
    (net (code "237") (name "Net-(P233-OUT)") (class "Default")
      (node (ref "P233") (pin "1") (pinfunction "OUT_1") (pintype "passive"))
      (node (ref "P234") (pin "4") (pinfunction "IN_4") (pintype "passive"))
    )
    (net (code "238") (name "Net-(P234-OUT)") (class "Default")
      (node (ref "P234") (pin "1") (pinfunction "OUT_1") (pintype "passive"))
      (node (ref "P235") (pin "4") (pinfunction "IN_4") (pintype "passive"))
    )
    (net (code "239") (name "Net-(P235-OUT)") (class "Default")
      (node (ref "P235") (pin "1") (pinfunction "OUT_1") (pintype "passive"))
      (node (ref "P236") (pin "4") (pinfunction "IN_4") (pintype "passive"))
    )
    (net (code "240") (name "Net-(P236-OUT)") (class "Default")
      (node (ref "P236") (pin "1") (pinfunction "OUT_1") (pintype "passive"))
      (node (ref "P237") (pin "4") (pinfunction "IN_4") (pintype "passive"))
    )
    (net (code "241") (name "Net-(P237-OUT)") (class "Default")
      (node (ref "P237") (pin "1") (pinfunction "OUT_1") (pintype "passive"))
      (node (ref "P238") (pin "4") (pinfunction "IN_4") (pintype "passive"))
    )
    (net (code "242") (name "Net-(P238-OUT)") (class "Default")
      (node (ref "P238") (pin "1") (pinfunction "OUT_1") (pintype "passive"))
      (node (ref "P239") (pin "4") (pinfunction "IN_4") (pintype "passive"))
    )
    (net (code "243") (name "Net-(P239-OUT)") (class "Default")
      (node (ref "P239") (pin "1") (pinfunction "OUT_1") (pintype "passive"))
      (node (ref "P240") (pin "4") (pinfunction "IN_4") (pintype "passive"))
    )
    (net (code "244") (name "Net-(P240-OUT)") (class "Default")
      (node (ref "P240") (pin "1") (pinfunction "OUT_1") (pintype "passive"))
      (node (ref "P241") (pin "4") (pinfunction "IN_4") (pintype "passive"))
    )
    (net (code "245") (name "Net-(P241-OUT)") (class "Default")
      (node (ref "P241") (pin "1") (pinfunction "OUT_1") (pintype "passive"))
      (node (ref "P242") (pin "4") (pinfunction "IN_4") (pintype "passive"))
    )
    (net (code "246") (name "Net-(P242-OUT)") (class "Default")
      (node (ref "P242") (pin "1") (pinfunction "OUT_1") (pintype "passive"))
      (node (ref "P243") (pin "4") (pinfunction "IN_4") (pintype "passive"))
    )
    (net (code "247") (name "Net-(P243-OUT)") (class "Default")
      (node (ref "P243") (pin "1") (pinfunction "OUT_1") (pintype "passive"))
      (node (ref "P244") (pin "4") (pinfunction "IN_4") (pintype "passive"))
    )
    (net (code "248") (name "Net-(P244-OUT)") (class "Default")
      (node (ref "P244") (pin "1") (pinfunction "OUT_1") (pintype "passive"))
      (node (ref "P245") (pin "4") (pinfunction "IN_4") (pintype "passive"))
    )
    (net (code "249") (name "Net-(P245-OUT)") (class "Default")
      (node (ref "P245") (pin "1") (pinfunction "OUT_1") (pintype "passive"))
      (node (ref "P246") (pin "4") (pinfunction "IN_4") (pintype "passive"))
    )
    (net (code "250") (name "Net-(P246-OUT)") (class "Default")
      (node (ref "P246") (pin "1") (pinfunction "OUT_1") (pintype "passive"))
      (node (ref "P247") (pin "4") (pinfunction "IN_4") (pintype "passive"))
    )
    (net (code "251") (name "Net-(P247-OUT)") (class "Default")
      (node (ref "P247") (pin "1") (pinfunction "OUT_1") (pintype "passive"))
      (node (ref "P248") (pin "4") (pinfunction "IN_4") (pintype "passive"))
    )
    (net (code "252") (name "Net-(P248-OUT)") (class "Default")
      (node (ref "P248") (pin "1") (pinfunction "OUT_1") (pintype "passive"))
      (node (ref "P249") (pin "4") (pinfunction "IN_4") (pintype "passive"))
    )
    (net (code "253") (name "Net-(P249-OUT)") (class "Default")
      (node (ref "P249") (pin "1") (pinfunction "OUT_1") (pintype "passive"))
      (node (ref "P250") (pin "4") (pinfunction "IN_4") (pintype "passive"))
    )
    (net (code "254") (name "Net-(P250-OUT)") (class "Default")
      (node (ref "P250") (pin "1") (pinfunction "OUT_1") (pintype "passive"))
      (node (ref "P251") (pin "4") (pinfunction "IN_4") (pintype "passive"))
    )
    (net (code "255") (name "Net-(P251-OUT)") (class "Default")
      (node (ref "P251") (pin "1") (pinfunction "OUT_1") (pintype "passive"))
      (node (ref "P252") (pin "4") (pinfunction "IN_4") (pintype "passive"))
    )
    (net (code "256") (name "Net-(P252-OUT)") (class "Default")
      (node (ref "P252") (pin "1") (pinfunction "OUT_1") (pintype "passive"))
      (node (ref "P253") (pin "4") (pinfunction "IN_4") (pintype "passive"))
    )
    (net (code "257") (name "Net-(P253-OUT)") (class "Default")
      (node (ref "P253") (pin "1") (pinfunction "OUT_1") (pintype "passive"))
      (node (ref "P254") (pin "4") (pinfunction "IN_4") (pintype "passive"))
    )
    (net (code "258") (name "Net-(P254-OUT)") (class "Default")
      (node (ref "P254") (pin "1") (pinfunction "OUT_1") (pintype "passive"))
      (node (ref "P255") (pin "4") (pinfunction "IN_4") (pintype "passive"))
    )
    (net (code "259") (name "Net-(P255-OUT)") (class "Default")
      (node (ref "P255") (pin "1") (pinfunction "OUT_1") (pintype "passive"))
      (node (ref "P256") (pin "4") (pinfunction "IN_4") (pintype "passive"))
    )
    (net (code "260") (name "Net-(P256-OUT)") (class "Default")
      (node (ref "P256") (pin "1") (pinfunction "OUT_1") (pintype "passive"))
      (node (ref "P257") (pin "4") (pinfunction "IN_4") (pintype "passive"))
    )
    (net (code "261") (name "Net-(P257-OUT)") (class "Default")
      (node (ref "P257") (pin "1") (pinfunction "OUT_1") (pintype "passive"))
      (node (ref "P258") (pin "4") (pinfunction "IN_4") (pintype "passive"))
    )
    (net (code "262") (name "Net-(P258-OUT)") (class "Default")
      (node (ref "P258") (pin "1") (pinfunction "OUT_1") (pintype "passive"))
      (node (ref "P259") (pin "4") (pinfunction "IN_4") (pintype "passive"))
    )
    (net (code "263") (name "Net-(P259-OUT)") (class "Default")
      (node (ref "P259") (pin "1") (pinfunction "OUT_1") (pintype "passive"))
      (node (ref "P260") (pin "4") (pinfunction "IN_4") (pintype "passive"))
    )
    (net (code "264") (name "Net-(P260-OUT)") (class "Default")
      (node (ref "P260") (pin "1") (pinfunction "OUT_1") (pintype "passive"))
      (node (ref "P261") (pin "4") (pinfunction "IN_4") (pintype "passive"))
    )
    (net (code "265") (name "Net-(P261-OUT)") (class "Default")
      (node (ref "P261") (pin "1") (pinfunction "OUT_1") (pintype "passive"))
      (node (ref "P262") (pin "4") (pinfunction "IN_4") (pintype "passive"))
    )
    (net (code "266") (name "Net-(P262-OUT)") (class "Default")
      (node (ref "P262") (pin "1") (pinfunction "OUT_1") (pintype "passive"))
      (node (ref "P263") (pin "4") (pinfunction "IN_4") (pintype "passive"))
    )
    (net (code "267") (name "Net-(P263-OUT)") (class "Default")
      (node (ref "P263") (pin "1") (pinfunction "OUT_1") (pintype "passive"))
      (node (ref "P264") (pin "4") (pinfunction "IN_4") (pintype "passive"))
    )
    (net (code "268") (name "Net-(P264-OUT)") (class "Default")
      (node (ref "P264") (pin "1") (pinfunction "OUT_1") (pintype "passive"))
      (node (ref "P265") (pin "4") (pinfunction "IN_4") (pintype "passive"))
    )
    (net (code "269") (name "Net-(P265-OUT)") (class "Default")
      (node (ref "P265") (pin "1") (pinfunction "OUT_1") (pintype "passive"))
      (node (ref "P266") (pin "4") (pinfunction "IN_4") (pintype "passive"))
    )
    (net (code "270") (name "Net-(P266-OUT)") (class "Default")
      (node (ref "P266") (pin "1") (pinfunction "OUT_1") (pintype "passive"))
      (node (ref "P267") (pin "4") (pinfunction "IN_4") (pintype "passive"))
    )
    (net (code "271") (name "Net-(P267-OUT)") (class "Default")
      (node (ref "P267") (pin "1") (pinfunction "OUT_1") (pintype "passive"))
      (node (ref "P268") (pin "4") (pinfunction "IN_4") (pintype "passive"))
    )
    (net (code "272") (name "Net-(P268-OUT)") (class "Default")
      (node (ref "P268") (pin "1") (pinfunction "OUT_1") (pintype "passive"))
      (node (ref "P269") (pin "4") (pinfunction "IN_4") (pintype "passive"))
    )
    (net (code "273") (name "Net-(P269-OUT)") (class "Default")
      (node (ref "P269") (pin "1") (pinfunction "OUT_1") (pintype "passive"))
      (node (ref "P270") (pin "4") (pinfunction "IN_4") (pintype "passive"))
    )
    (net (code "274") (name "Net-(P270-OUT)") (class "Default")
      (node (ref "P270") (pin "1") (pinfunction "OUT_1") (pintype "passive"))
      (node (ref "P271") (pin "4") (pinfunction "IN_4") (pintype "passive"))
    )
    (net (code "275") (name "Net-(P271-OUT)") (class "Default")
      (node (ref "P271") (pin "1") (pinfunction "OUT_1") (pintype "passive"))
      (node (ref "P272") (pin "4") (pinfunction "IN_4") (pintype "passive"))
    )
    (net (code "276") (name "Net-(P272-OUT)") (class "Default")
      (node (ref "P272") (pin "1") (pinfunction "OUT_1") (pintype "passive"))
      (node (ref "P273") (pin "4") (pinfunction "IN_4") (pintype "passive"))
    )
    (net (code "277") (name "Net-(P273-OUT)") (class "Default")
      (node (ref "P273") (pin "1") (pinfunction "OUT_1") (pintype "passive"))
      (node (ref "P274") (pin "4") (pinfunction "IN_4") (pintype "passive"))
    )
    (net (code "278") (name "Net-(P274-OUT)") (class "Default")
      (node (ref "P274") (pin "1") (pinfunction "OUT_1") (pintype "passive"))
      (node (ref "P275") (pin "4") (pinfunction "IN_4") (pintype "passive"))
    )
    (net (code "279") (name "Net-(P275-OUT)") (class "Default")
      (node (ref "P275") (pin "1") (pinfunction "OUT_1") (pintype "passive"))
      (node (ref "P276") (pin "4") (pinfunction "IN_4") (pintype "passive"))
    )
    (net (code "280") (name "Net-(P276-OUT)") (class "Default")
      (node (ref "P276") (pin "1") (pinfunction "OUT_1") (pintype "passive"))
      (node (ref "P277") (pin "4") (pinfunction "IN_4") (pintype "passive"))
    )
    (net (code "281") (name "Net-(P277-OUT)") (class "Default")
      (node (ref "P277") (pin "1") (pinfunction "OUT_1") (pintype "passive"))
      (node (ref "P278") (pin "4") (pinfunction "IN_4") (pintype "passive"))
    )
    (net (code "282") (name "Net-(P278-OUT)") (class "Default")
      (node (ref "P278") (pin "1") (pinfunction "OUT_1") (pintype "passive"))
      (node (ref "P279") (pin "4") (pinfunction "IN_4") (pintype "passive"))
    )
    (net (code "283") (name "Net-(P279-OUT)") (class "Default")
      (node (ref "P279") (pin "1") (pinfunction "OUT_1") (pintype "passive"))
      (node (ref "P280") (pin "4") (pinfunction "IN_4") (pintype "passive"))
    )
    (net (code "284") (name "Net-(P281-OUT)") (class "Default")
      (node (ref "P281") (pin "1") (pinfunction "OUT_1") (pintype "passive"))
      (node (ref "P282") (pin "4") (pinfunction "IN_4") (pintype "passive"))
    )
    (net (code "285") (name "Net-(P282-OUT)") (class "Default")
      (node (ref "P282") (pin "1") (pinfunction "OUT_1") (pintype "passive"))
      (node (ref "P283") (pin "4") (pinfunction "IN_4") (pintype "passive"))
    )
    (net (code "286") (name "Net-(P283-OUT)") (class "Default")
      (node (ref "P283") (pin "1") (pinfunction "OUT_1") (pintype "passive"))
      (node (ref "P284") (pin "4") (pinfunction "IN_4") (pintype "passive"))
    )
    (net (code "287") (name "Net-(P284-OUT)") (class "Default")
      (node (ref "P284") (pin "1") (pinfunction "OUT_1") (pintype "passive"))
      (node (ref "P285") (pin "4") (pinfunction "IN_4") (pintype "passive"))
    )
    (net (code "288") (name "Net-(P285-OUT)") (class "Default")
      (node (ref "P285") (pin "1") (pinfunction "OUT_1") (pintype "passive"))
      (node (ref "P286") (pin "4") (pinfunction "IN_4") (pintype "passive"))
    )
    (net (code "289") (name "Net-(P286-OUT)") (class "Default")
      (node (ref "P286") (pin "1") (pinfunction "OUT_1") (pintype "passive"))
      (node (ref "P287") (pin "4") (pinfunction "IN_4") (pintype "passive"))
    )
    (net (code "290") (name "Net-(P287-OUT)") (class "Default")
      (node (ref "P287") (pin "1") (pinfunction "OUT_1") (pintype "passive"))
      (node (ref "P288") (pin "4") (pinfunction "IN_4") (pintype "passive"))
    )
    (net (code "291") (name "Net-(P288-OUT)") (class "Default")
      (node (ref "P288") (pin "1") (pinfunction "OUT_1") (pintype "passive"))
      (node (ref "P289") (pin "4") (pinfunction "IN_4") (pintype "passive"))
    )
    (net (code "292") (name "Net-(P289-OUT)") (class "Default")
      (node (ref "P289") (pin "1") (pinfunction "OUT_1") (pintype "passive"))
      (node (ref "P290") (pin "4") (pinfunction "IN_4") (pintype "passive"))
    )
    (net (code "293") (name "Net-(P290-OUT)") (class "Default")
      (node (ref "P290") (pin "1") (pinfunction "OUT_1") (pintype "passive"))
      (node (ref "P291") (pin "4") (pinfunction "IN_4") (pintype "passive"))
    )
    (net (code "294") (name "Net-(P291-OUT)") (class "Default")
      (node (ref "P291") (pin "1") (pinfunction "OUT_1") (pintype "passive"))
      (node (ref "P292") (pin "4") (pinfunction "IN_4") (pintype "passive"))
    )
    (net (code "295") (name "Net-(P292-OUT)") (class "Default")
      (node (ref "P292") (pin "1") (pinfunction "OUT_1") (pintype "passive"))
      (node (ref "P293") (pin "4") (pinfunction "IN_4") (pintype "passive"))
    )
    (net (code "296") (name "Net-(P293-OUT)") (class "Default")
      (node (ref "P293") (pin "1") (pinfunction "OUT_1") (pintype "passive"))
      (node (ref "P294") (pin "4") (pinfunction "IN_4") (pintype "passive"))
    )
    (net (code "297") (name "Net-(P294-OUT)") (class "Default")
      (node (ref "P294") (pin "1") (pinfunction "OUT_1") (pintype "passive"))
      (node (ref "P295") (pin "4") (pinfunction "IN_4") (pintype "passive"))
    )
    (net (code "298") (name "Net-(P295-OUT)") (class "Default")
      (node (ref "P295") (pin "1") (pinfunction "OUT_1") (pintype "passive"))
      (node (ref "P296") (pin "4") (pinfunction "IN_4") (pintype "passive"))
    )
    (net (code "299") (name "Net-(P296-OUT)") (class "Default")
      (node (ref "P296") (pin "1") (pinfunction "OUT_1") (pintype "passive"))
      (node (ref "P297") (pin "4") (pinfunction "IN_4") (pintype "passive"))
    )
    (net (code "300") (name "Net-(P297-OUT)") (class "Default")
      (node (ref "P297") (pin "1") (pinfunction "OUT_1") (pintype "passive"))
      (node (ref "P298") (pin "4") (pinfunction "IN_4") (pintype "passive"))
    )
    (net (code "301") (name "Net-(P298-OUT)") (class "Default")
      (node (ref "P298") (pin "1") (pinfunction "OUT_1") (pintype "passive"))
      (node (ref "P299") (pin "4") (pinfunction "IN_4") (pintype "passive"))
    )
    (net (code "302") (name "Net-(P299-OUT)") (class "Default")
      (node (ref "P299") (pin "1") (pinfunction "OUT_1") (pintype "passive"))
      (node (ref "P300") (pin "4") (pinfunction "IN_4") (pintype "passive"))
    )
    (net (code "303") (name "Net-(P300-OUT)") (class "Default")
      (node (ref "P300") (pin "1") (pinfunction "OUT_1") (pintype "passive"))
      (node (ref "P301") (pin "4") (pinfunction "IN_4") (pintype "passive"))
    )
    (net (code "304") (name "Net-(P301-OUT)") (class "Default")
      (node (ref "P301") (pin "1") (pinfunction "OUT_1") (pintype "passive"))
      (node (ref "P302") (pin "4") (pinfunction "IN_4") (pintype "passive"))
    )
    (net (code "305") (name "Net-(P302-OUT)") (class "Default")
      (node (ref "P302") (pin "1") (pinfunction "OUT_1") (pintype "passive"))
      (node (ref "P303") (pin "4") (pinfunction "IN_4") (pintype "passive"))
    )
    (net (code "306") (name "Net-(P303-OUT)") (class "Default")
      (node (ref "P303") (pin "1") (pinfunction "OUT_1") (pintype "passive"))
      (node (ref "P304") (pin "4") (pinfunction "IN_4") (pintype "passive"))
    )
    (net (code "307") (name "Net-(P304-OUT)") (class "Default")
      (node (ref "P304") (pin "1") (pinfunction "OUT_1") (pintype "passive"))
      (node (ref "P305") (pin "4") (pinfunction "IN_4") (pintype "passive"))
    )
    (net (code "308") (name "Net-(P305-OUT)") (class "Default")
      (node (ref "P305") (pin "1") (pinfunction "OUT_1") (pintype "passive"))
      (node (ref "P306") (pin "4") (pinfunction "IN_4") (pintype "passive"))
    )
    (net (code "309") (name "Net-(P306-OUT)") (class "Default")
      (node (ref "P306") (pin "1") (pinfunction "OUT_1") (pintype "passive"))
      (node (ref "P307") (pin "4") (pinfunction "IN_4") (pintype "passive"))
    )
    (net (code "310") (name "Net-(P307-OUT)") (class "Default")
      (node (ref "P307") (pin "1") (pinfunction "OUT_1") (pintype "passive"))
      (node (ref "P308") (pin "4") (pinfunction "IN_4") (pintype "passive"))
    )
    (net (code "311") (name "Net-(P308-OUT)") (class "Default")
      (node (ref "P308") (pin "1") (pinfunction "OUT_1") (pintype "passive"))
      (node (ref "P309") (pin "4") (pinfunction "IN_4") (pintype "passive"))
    )
    (net (code "312") (name "Net-(P309-OUT)") (class "Default")
      (node (ref "P309") (pin "1") (pinfunction "OUT_1") (pintype "passive"))
      (node (ref "P310") (pin "4") (pinfunction "IN_4") (pintype "passive"))
    )
    (net (code "313") (name "Net-(P310-OUT)") (class "Default")
      (node (ref "P310") (pin "1") (pinfunction "OUT_1") (pintype "passive"))
      (node (ref "P311") (pin "4") (pinfunction "IN_4") (pintype "passive"))
    )
    (net (code "314") (name "Net-(P311-OUT)") (class "Default")
      (node (ref "P311") (pin "1") (pinfunction "OUT_1") (pintype "passive"))
      (node (ref "P312") (pin "4") (pinfunction "IN_4") (pintype "passive"))
    )
    (net (code "315") (name "Net-(P312-OUT)") (class "Default")
      (node (ref "P312") (pin "1") (pinfunction "OUT_1") (pintype "passive"))
      (node (ref "P313") (pin "4") (pinfunction "IN_4") (pintype "passive"))
    )
    (net (code "316") (name "Net-(P313-OUT)") (class "Default")
      (node (ref "P313") (pin "1") (pinfunction "OUT_1") (pintype "passive"))
      (node (ref "P314") (pin "4") (pinfunction "IN_4") (pintype "passive"))
    )
    (net (code "317") (name "Net-(P314-OUT)") (class "Default")
      (node (ref "P314") (pin "1") (pinfunction "OUT_1") (pintype "passive"))
      (node (ref "P315") (pin "4") (pinfunction "IN_4") (pintype "passive"))
    )
    (net (code "318") (name "Net-(P315-OUT)") (class "Default")
      (node (ref "P315") (pin "1") (pinfunction "OUT_1") (pintype "passive"))
      (node (ref "P316") (pin "4") (pinfunction "IN_4") (pintype "passive"))
    )
    (net (code "319") (name "Net-(P316-OUT)") (class "Default")
      (node (ref "P316") (pin "1") (pinfunction "OUT_1") (pintype "passive"))
      (node (ref "P317") (pin "4") (pinfunction "IN_4") (pintype "passive"))
    )
    (net (code "320") (name "Net-(P317-OUT)") (class "Default")
      (node (ref "P317") (pin "1") (pinfunction "OUT_1") (pintype "passive"))
      (node (ref "P318") (pin "4") (pinfunction "IN_4") (pintype "passive"))
    )
    (net (code "321") (name "Net-(P318-OUT)") (class "Default")
      (node (ref "P318") (pin "1") (pinfunction "OUT_1") (pintype "passive"))
      (node (ref "P319") (pin "4") (pinfunction "IN_4") (pintype "passive"))
    )
    (net (code "322") (name "Net-(P319-OUT)") (class "Default")
      (node (ref "P319") (pin "1") (pinfunction "OUT_1") (pintype "passive"))
      (node (ref "P320") (pin "4") (pinfunction "IN_4") (pintype "passive"))
    )
    (net (code "323") (name "Net-(P320-OUT)") (class "Default")
      (node (ref "P320") (pin "1") (pinfunction "OUT_1") (pintype "passive"))
      (node (ref "P321") (pin "4") (pinfunction "IN_4") (pintype "passive"))
    )
    (net (code "324") (name "Net-(P321-OUT)") (class "Default")
      (node (ref "P321") (pin "1") (pinfunction "OUT_1") (pintype "passive"))
      (node (ref "P322") (pin "4") (pinfunction "IN_4") (pintype "passive"))
    )
    (net (code "325") (name "Net-(P322-OUT)") (class "Default")
      (node (ref "P322") (pin "1") (pinfunction "OUT_1") (pintype "passive"))
      (node (ref "P323") (pin "4") (pinfunction "IN_4") (pintype "passive"))
    )
    (net (code "326") (name "Net-(P323-OUT)") (class "Default")
      (node (ref "P323") (pin "1") (pinfunction "OUT_1") (pintype "passive"))
      (node (ref "P324") (pin "4") (pinfunction "IN_4") (pintype "passive"))
    )
    (net (code "327") (name "Net-(P324-OUT)") (class "Default")
      (node (ref "P324") (pin "1") (pinfunction "OUT_1") (pintype "passive"))
      (node (ref "P325") (pin "4") (pinfunction "IN_4") (pintype "passive"))
    )
    (net (code "328") (name "Net-(P325-OUT)") (class "Default")
      (node (ref "P325") (pin "1") (pinfunction "OUT_1") (pintype "passive"))
      (node (ref "P326") (pin "4") (pinfunction "IN_4") (pintype "passive"))
    )
    (net (code "329") (name "Net-(P326-OUT)") (class "Default")
      (node (ref "P326") (pin "1") (pinfunction "OUT_1") (pintype "passive"))
      (node (ref "P327") (pin "4") (pinfunction "IN_4") (pintype "passive"))
    )
    (net (code "330") (name "Net-(P327-OUT)") (class "Default")
      (node (ref "P327") (pin "1") (pinfunction "OUT_1") (pintype "passive"))
      (node (ref "P328") (pin "4") (pinfunction "IN_4") (pintype "passive"))
    )
    (net (code "331") (name "Net-(P328-OUT)") (class "Default")
      (node (ref "P328") (pin "1") (pinfunction "OUT_1") (pintype "passive"))
      (node (ref "P329") (pin "4") (pinfunction "IN_4") (pintype "passive"))
    )
    (net (code "332") (name "Net-(P329-OUT)") (class "Default")
      (node (ref "P329") (pin "1") (pinfunction "OUT_1") (pintype "passive"))
      (node (ref "P330") (pin "4") (pinfunction "IN_4") (pintype "passive"))
    )
    (net (code "333") (name "Net-(P330-OUT)") (class "Default")
      (node (ref "P330") (pin "1") (pinfunction "OUT_1") (pintype "passive"))
      (node (ref "P331") (pin "4") (pinfunction "IN_4") (pintype "passive"))
    )
    (net (code "334") (name "Net-(P331-OUT)") (class "Default")
      (node (ref "P331") (pin "1") (pinfunction "OUT_1") (pintype "passive"))
      (node (ref "P332") (pin "4") (pinfunction "IN_4") (pintype "passive"))
    )
    (net (code "335") (name "Net-(P332-OUT)") (class "Default")
      (node (ref "P332") (pin "1") (pinfunction "OUT_1") (pintype "passive"))
      (node (ref "P333") (pin "4") (pinfunction "IN_4") (pintype "passive"))
    )
    (net (code "336") (name "Net-(P333-OUT)") (class "Default")
      (node (ref "P333") (pin "1") (pinfunction "OUT_1") (pintype "passive"))
      (node (ref "P334") (pin "4") (pinfunction "IN_4") (pintype "passive"))
    )
    (net (code "337") (name "Net-(P334-OUT)") (class "Default")
      (node (ref "P334") (pin "1") (pinfunction "OUT_1") (pintype "passive"))
      (node (ref "P335") (pin "4") (pinfunction "IN_4") (pintype "passive"))
    )
    (net (code "338") (name "Net-(P335-OUT)") (class "Default")
      (node (ref "P335") (pin "1") (pinfunction "OUT_1") (pintype "passive"))
      (node (ref "P336") (pin "4") (pinfunction "IN_4") (pintype "passive"))
    )
    (net (code "339") (name "Net-(P336-OUT)") (class "Default")
      (node (ref "P336") (pin "1") (pinfunction "OUT_1") (pintype "passive"))
      (node (ref "P337") (pin "4") (pinfunction "IN_4") (pintype "passive"))
    )
    (net (code "340") (name "Net-(P337-OUT)") (class "Default")
      (node (ref "P337") (pin "1") (pinfunction "OUT_1") (pintype "passive"))
      (node (ref "P338") (pin "4") (pinfunction "IN_4") (pintype "passive"))
    )
    (net (code "341") (name "Net-(P338-OUT)") (class "Default")
      (node (ref "P338") (pin "1") (pinfunction "OUT_1") (pintype "passive"))
      (node (ref "P339") (pin "4") (pinfunction "IN_4") (pintype "passive"))
    )
    (net (code "342") (name "Net-(P339-OUT)") (class "Default")
      (node (ref "P339") (pin "1") (pinfunction "OUT_1") (pintype "passive"))
      (node (ref "P340") (pin "4") (pinfunction "IN_4") (pintype "passive"))
    )
    (net (code "343") (name "Net-(P340-OUT)") (class "Default")
      (node (ref "P340") (pin "1") (pinfunction "OUT_1") (pintype "passive"))
      (node (ref "P341") (pin "4") (pinfunction "IN_4") (pintype "passive"))
    )
    (net (code "344") (name "Net-(P341-OUT)") (class "Default")
      (node (ref "P341") (pin "1") (pinfunction "OUT_1") (pintype "passive"))
      (node (ref "P342") (pin "4") (pinfunction "IN_4") (pintype "passive"))
    )
    (net (code "345") (name "Net-(P342-OUT)") (class "Default")
      (node (ref "P342") (pin "1") (pinfunction "OUT_1") (pintype "passive"))
      (node (ref "P343") (pin "4") (pinfunction "IN_4") (pintype "passive"))
    )
    (net (code "346") (name "Net-(P343-OUT)") (class "Default")
      (node (ref "P343") (pin "1") (pinfunction "OUT_1") (pintype "passive"))
      (node (ref "P344") (pin "4") (pinfunction "IN_4") (pintype "passive"))
    )
    (net (code "347") (name "Net-(P344-OUT)") (class "Default")
      (node (ref "P344") (pin "1") (pinfunction "OUT_1") (pintype "passive"))
      (node (ref "P345") (pin "4") (pinfunction "IN_4") (pintype "passive"))
    )
    (net (code "348") (name "Net-(P345-OUT)") (class "Default")
      (node (ref "P345") (pin "1") (pinfunction "OUT_1") (pintype "passive"))
      (node (ref "P346") (pin "4") (pinfunction "IN_4") (pintype "passive"))
    )
    (net (code "349") (name "Net-(P346-OUT)") (class "Default")
      (node (ref "P346") (pin "1") (pinfunction "OUT_1") (pintype "passive"))
      (node (ref "P347") (pin "4") (pinfunction "IN_4") (pintype "passive"))
    )
    (net (code "350") (name "Net-(P347-OUT)") (class "Default")
      (node (ref "P347") (pin "1") (pinfunction "OUT_1") (pintype "passive"))
      (node (ref "P348") (pin "4") (pinfunction "IN_4") (pintype "passive"))
    )
    (net (code "351") (name "Net-(P348-OUT)") (class "Default")
      (node (ref "P348") (pin "1") (pinfunction "OUT_1") (pintype "passive"))
      (node (ref "P349") (pin "4") (pinfunction "IN_4") (pintype "passive"))
    )
    (net (code "352") (name "Net-(P349-OUT)") (class "Default")
      (node (ref "P349") (pin "1") (pinfunction "OUT_1") (pintype "passive"))
      (node (ref "P350") (pin "4") (pinfunction "IN_4") (pintype "passive"))
    )
    (net (code "353") (name "Net-(P350-OUT)") (class "Default")
      (node (ref "P350") (pin "1") (pinfunction "OUT_1") (pintype "passive"))
      (node (ref "P351") (pin "4") (pinfunction "IN_4") (pintype "passive"))
    )
    (net (code "354") (name "Net-(P351-OUT)") (class "Default")
      (node (ref "P351") (pin "1") (pinfunction "OUT_1") (pintype "passive"))
      (node (ref "P352") (pin "4") (pinfunction "IN_4") (pintype "passive"))
    )
    (net (code "355") (name "Net-(P352-OUT)") (class "Default")
      (node (ref "P352") (pin "1") (pinfunction "OUT_1") (pintype "passive"))
      (node (ref "P353") (pin "4") (pinfunction "IN_4") (pintype "passive"))
    )
    (net (code "356") (name "Net-(P353-OUT)") (class "Default")
      (node (ref "P353") (pin "1") (pinfunction "OUT_1") (pintype "passive"))
      (node (ref "P354") (pin "4") (pinfunction "IN_4") (pintype "passive"))
    )
    (net (code "357") (name "Net-(P354-OUT)") (class "Default")
      (node (ref "P354") (pin "1") (pinfunction "OUT_1") (pintype "passive"))
      (node (ref "P355") (pin "4") (pinfunction "IN_4") (pintype "passive"))
    )
    (net (code "358") (name "Net-(P355-OUT)") (class "Default")
      (node (ref "P355") (pin "1") (pinfunction "OUT_1") (pintype "passive"))
      (node (ref "P356") (pin "4") (pinfunction "IN_4") (pintype "passive"))
    )
    (net (code "359") (name "Net-(P356-OUT)") (class "Default")
      (node (ref "P356") (pin "1") (pinfunction "OUT_1") (pintype "passive"))
      (node (ref "P357") (pin "4") (pinfunction "IN_4") (pintype "passive"))
    )
    (net (code "360") (name "Net-(P357-OUT)") (class "Default")
      (node (ref "P357") (pin "1") (pinfunction "OUT_1") (pintype "passive"))
      (node (ref "P358") (pin "4") (pinfunction "IN_4") (pintype "passive"))
    )
    (net (code "361") (name "Net-(P358-OUT)") (class "Default")
      (node (ref "P358") (pin "1") (pinfunction "OUT_1") (pintype "passive"))
      (node (ref "P359") (pin "4") (pinfunction "IN_4") (pintype "passive"))
    )
    (net (code "362") (name "Net-(P359-OUT)") (class "Default")
      (node (ref "P359") (pin "1") (pinfunction "OUT_1") (pintype "passive"))
      (node (ref "P360") (pin "4") (pinfunction "IN_4") (pintype "passive"))
    )
    (net (code "363") (name "Net-(P360-OUT)") (class "Default")
      (node (ref "P360") (pin "1") (pinfunction "OUT_1") (pintype "passive"))
      (node (ref "P361") (pin "4") (pinfunction "IN_4") (pintype "passive"))
    )
    (net (code "364") (name "Net-(P361-OUT)") (class "Default")
      (node (ref "P361") (pin "1") (pinfunction "OUT_1") (pintype "passive"))
      (node (ref "P362") (pin "4") (pinfunction "IN_4") (pintype "passive"))
    )
    (net (code "365") (name "Net-(P362-OUT)") (class "Default")
      (node (ref "P362") (pin "1") (pinfunction "OUT_1") (pintype "passive"))
      (node (ref "P363") (pin "4") (pinfunction "IN_4") (pintype "passive"))
    )
    (net (code "366") (name "Net-(P363-OUT)") (class "Default")
      (node (ref "P363") (pin "1") (pinfunction "OUT_1") (pintype "passive"))
      (node (ref "P364") (pin "4") (pinfunction "IN_4") (pintype "passive"))
    )
    (net (code "367") (name "Net-(P364-OUT)") (class "Default")
      (node (ref "P364") (pin "1") (pinfunction "OUT_1") (pintype "passive"))
      (node (ref "P365") (pin "4") (pinfunction "IN_4") (pintype "passive"))
    )
    (net (code "368") (name "Net-(P365-OUT)") (class "Default")
      (node (ref "P365") (pin "1") (pinfunction "OUT_1") (pintype "passive"))
      (node (ref "P366") (pin "4") (pinfunction "IN_4") (pintype "passive"))
    )
    (net (code "369") (name "Net-(P366-OUT)") (class "Default")
      (node (ref "P366") (pin "1") (pinfunction "OUT_1") (pintype "passive"))
      (node (ref "P367") (pin "4") (pinfunction "IN_4") (pintype "passive"))
    )
    (net (code "370") (name "Net-(P367-OUT)") (class "Default")
      (node (ref "P367") (pin "1") (pinfunction "OUT_1") (pintype "passive"))
      (node (ref "P368") (pin "4") (pinfunction "IN_4") (pintype "passive"))
    )
    (net (code "371") (name "Net-(P368-OUT)") (class "Default")
      (node (ref "P368") (pin "1") (pinfunction "OUT_1") (pintype "passive"))
      (node (ref "P369") (pin "4") (pinfunction "IN_4") (pintype "passive"))
    )
    (net (code "372") (name "Net-(P369-OUT)") (class "Default")
      (node (ref "P369") (pin "1") (pinfunction "OUT_1") (pintype "passive"))
      (node (ref "P370") (pin "4") (pinfunction "IN_4") (pintype "passive"))
    )
    (net (code "373") (name "Net-(P370-OUT)") (class "Default")
      (node (ref "P370") (pin "1") (pinfunction "OUT_1") (pintype "passive"))
      (node (ref "P371") (pin "4") (pinfunction "IN_4") (pintype "passive"))
    )
    (net (code "374") (name "Net-(P371-OUT)") (class "Default")
      (node (ref "P371") (pin "1") (pinfunction "OUT_1") (pintype "passive"))
      (node (ref "P372") (pin "4") (pinfunction "IN_4") (pintype "passive"))
    )
    (net (code "375") (name "Net-(P372-OUT)") (class "Default")
      (node (ref "P372") (pin "1") (pinfunction "OUT_1") (pintype "passive"))
      (node (ref "P373") (pin "4") (pinfunction "IN_4") (pintype "passive"))
    )
    (net (code "376") (name "Net-(P373-OUT)") (class "Default")
      (node (ref "P373") (pin "1") (pinfunction "OUT_1") (pintype "passive"))
      (node (ref "P374") (pin "4") (pinfunction "IN_4") (pintype "passive"))
    )
    (net (code "377") (name "Net-(P374-OUT)") (class "Default")
      (node (ref "P374") (pin "1") (pinfunction "OUT_1") (pintype "passive"))
      (node (ref "P375") (pin "4") (pinfunction "IN_4") (pintype "passive"))
    )
    (net (code "378") (name "Net-(P375-OUT)") (class "Default")
      (node (ref "P375") (pin "1") (pinfunction "OUT_1") (pintype "passive"))
      (node (ref "P376") (pin "4") (pinfunction "IN_4") (pintype "passive"))
    )
    (net (code "379") (name "Net-(P376-OUT)") (class "Default")
      (node (ref "P376") (pin "1") (pinfunction "OUT_1") (pintype "passive"))
      (node (ref "P377") (pin "4") (pinfunction "IN_4") (pintype "passive"))
    )
    (net (code "380") (name "Net-(P377-OUT)") (class "Default")
      (node (ref "P377") (pin "1") (pinfunction "OUT_1") (pintype "passive"))
      (node (ref "P378") (pin "4") (pinfunction "IN_4") (pintype "passive"))
    )
    (net (code "381") (name "Net-(P378-OUT)") (class "Default")
      (node (ref "P378") (pin "1") (pinfunction "OUT_1") (pintype "passive"))
      (node (ref "P379") (pin "4") (pinfunction "IN_4") (pintype "passive"))
    )
    (net (code "382") (name "Net-(P379-OUT)") (class "Default")
      (node (ref "P379") (pin "1") (pinfunction "OUT_1") (pintype "passive"))
      (node (ref "P380") (pin "4") (pinfunction "IN_4") (pintype "passive"))
    )
    (net (code "383") (name "Net-(P380-OUT)") (class "Default")
      (node (ref "P380") (pin "1") (pinfunction "OUT_1") (pintype "passive"))
      (node (ref "P381") (pin "4") (pinfunction "IN_4") (pintype "passive"))
    )
    (net (code "384") (name "Net-(P381-OUT)") (class "Default")
      (node (ref "P381") (pin "1") (pinfunction "OUT_1") (pintype "passive"))
      (node (ref "P382") (pin "4") (pinfunction "IN_4") (pintype "passive"))
    )
    (net (code "385") (name "Net-(P382-OUT)") (class "Default")
      (node (ref "P382") (pin "1") (pinfunction "OUT_1") (pintype "passive"))
      (node (ref "P383") (pin "4") (pinfunction "IN_4") (pintype "passive"))
    )
    (net (code "386") (name "Net-(P383-OUT)") (class "Default")
      (node (ref "P383") (pin "1") (pinfunction "OUT_1") (pintype "passive"))
      (node (ref "P384") (pin "4") (pinfunction "IN_4") (pintype "passive"))
    )
    (net (code "387") (name "Net-(P384-OUT)") (class "Default")
      (node (ref "P384") (pin "1") (pinfunction "OUT_1") (pintype "passive"))
      (node (ref "P385") (pin "4") (pinfunction "IN_4") (pintype "passive"))
    )
    (net (code "388") (name "Net-(P385-OUT)") (class "Default")
      (node (ref "P385") (pin "1") (pinfunction "OUT_1") (pintype "passive"))
      (node (ref "P386") (pin "4") (pinfunction "IN_4") (pintype "passive"))
    )
    (net (code "389") (name "Net-(P386-OUT)") (class "Default")
      (node (ref "P386") (pin "1") (pinfunction "OUT_1") (pintype "passive"))
      (node (ref "P387") (pin "4") (pinfunction "IN_4") (pintype "passive"))
    )
    (net (code "390") (name "Net-(P387-OUT)") (class "Default")
      (node (ref "P387") (pin "1") (pinfunction "OUT_1") (pintype "passive"))
      (node (ref "P388") (pin "4") (pinfunction "IN_4") (pintype "passive"))
    )
    (net (code "391") (name "Net-(P388-OUT)") (class "Default")
      (node (ref "P388") (pin "1") (pinfunction "OUT_1") (pintype "passive"))
      (node (ref "P389") (pin "4") (pinfunction "IN_4") (pintype "passive"))
    )
    (net (code "392") (name "Net-(P389-OUT)") (class "Default")
      (node (ref "P389") (pin "1") (pinfunction "OUT_1") (pintype "passive"))
      (node (ref "P390") (pin "4") (pinfunction "IN_4") (pintype "passive"))
    )
    (net (code "393") (name "Net-(P390-OUT)") (class "Default")
      (node (ref "P390") (pin "1") (pinfunction "OUT_1") (pintype "passive"))
      (node (ref "P391") (pin "4") (pinfunction "IN_4") (pintype "passive"))
    )
    (net (code "394") (name "Net-(P391-OUT)") (class "Default")
      (node (ref "P391") (pin "1") (pinfunction "OUT_1") (pintype "passive"))
      (node (ref "P392") (pin "4") (pinfunction "IN_4") (pintype "passive"))
    )
    (net (code "395") (name "Net-(P392-OUT)") (class "Default")
      (node (ref "P392") (pin "1") (pinfunction "OUT_1") (pintype "passive"))
      (node (ref "P393") (pin "4") (pinfunction "IN_4") (pintype "passive"))
    )
    (net (code "396") (name "Net-(P393-OUT)") (class "Default")
      (node (ref "P393") (pin "1") (pinfunction "OUT_1") (pintype "passive"))
      (node (ref "P394") (pin "4") (pinfunction "IN_4") (pintype "passive"))
    )
    (net (code "397") (name "Net-(P394-OUT)") (class "Default")
      (node (ref "P394") (pin "1") (pinfunction "OUT_1") (pintype "passive"))
      (node (ref "P395") (pin "4") (pinfunction "IN_4") (pintype "passive"))
    )
    (net (code "398") (name "Net-(P395-OUT)") (class "Default")
      (node (ref "P395") (pin "1") (pinfunction "OUT_1") (pintype "passive"))
      (node (ref "P396") (pin "4") (pinfunction "IN_4") (pintype "passive"))
    )
    (net (code "399") (name "Net-(P396-OUT)") (class "Default")
      (node (ref "P396") (pin "1") (pinfunction "OUT_1") (pintype "passive"))
      (node (ref "P397") (pin "4") (pinfunction "IN_4") (pintype "passive"))
    )
    (net (code "400") (name "Net-(P397-OUT)") (class "Default")
      (node (ref "P397") (pin "1") (pinfunction "OUT_1") (pintype "passive"))
      (node (ref "P398") (pin "4") (pinfunction "IN_4") (pintype "passive"))
    )
    (net (code "401") (name "Net-(P398-OUT)") (class "Default")
      (node (ref "P398") (pin "1") (pinfunction "OUT_1") (pintype "passive"))
      (node (ref "P399") (pin "4") (pinfunction "IN_4") (pintype "passive"))
    )
    (net (code "402") (name "Net-(P399-OUT)") (class "Default")
      (node (ref "P399") (pin "1") (pinfunction "OUT_1") (pintype "passive"))
      (node (ref "P400") (pin "4") (pinfunction "IN_4") (pintype "passive"))
    )
    (net (code "403") (name "Net-(P400-OUT)") (class "Default")
      (node (ref "P400") (pin "1") (pinfunction "OUT_1") (pintype "passive"))
      (node (ref "P401") (pin "4") (pinfunction "IN_4") (pintype "passive"))
    )
    (net (code "404") (name "Net-(P401-OUT)") (class "Default")
      (node (ref "P401") (pin "1") (pinfunction "OUT_1") (pintype "passive"))
      (node (ref "P402") (pin "4") (pinfunction "IN_4") (pintype "passive"))
    )
    (net (code "405") (name "Net-(P402-OUT)") (class "Default")
      (node (ref "P402") (pin "1") (pinfunction "OUT_1") (pintype "passive"))
      (node (ref "P403") (pin "4") (pinfunction "IN_4") (pintype "passive"))
    )
    (net (code "406") (name "Net-(P403-OUT)") (class "Default")
      (node (ref "P403") (pin "1") (pinfunction "OUT_1") (pintype "passive"))
      (node (ref "P404") (pin "4") (pinfunction "IN_4") (pintype "passive"))
    )
    (net (code "407") (name "Net-(P404-OUT)") (class "Default")
      (node (ref "P404") (pin "1") (pinfunction "OUT_1") (pintype "passive"))
      (node (ref "P405") (pin "4") (pinfunction "IN_4") (pintype "passive"))
    )
    (net (code "408") (name "Net-(P405-OUT)") (class "Default")
      (node (ref "P405") (pin "1") (pinfunction "OUT_1") (pintype "passive"))
      (node (ref "P406") (pin "4") (pinfunction "IN_4") (pintype "passive"))
    )
    (net (code "409") (name "Net-(P406-OUT)") (class "Default")
      (node (ref "P406") (pin "1") (pinfunction "OUT_1") (pintype "passive"))
      (node (ref "P407") (pin "4") (pinfunction "IN_4") (pintype "passive"))
    )
    (net (code "410") (name "Net-(P407-OUT)") (class "Default")
      (node (ref "P407") (pin "1") (pinfunction "OUT_1") (pintype "passive"))
      (node (ref "P408") (pin "4") (pinfunction "IN_4") (pintype "passive"))
    )
    (net (code "411") (name "Net-(P408-OUT)") (class "Default")
      (node (ref "P408") (pin "1") (pinfunction "OUT_1") (pintype "passive"))
      (node (ref "P409") (pin "4") (pinfunction "IN_4") (pintype "passive"))
    )
    (net (code "412") (name "Net-(P409-OUT)") (class "Default")
      (node (ref "P409") (pin "1") (pinfunction "OUT_1") (pintype "passive"))
      (node (ref "P410") (pin "4") (pinfunction "IN_4") (pintype "passive"))
    )
    (net (code "413") (name "Net-(P410-OUT)") (class "Default")
      (node (ref "P410") (pin "1") (pinfunction "OUT_1") (pintype "passive"))
      (node (ref "P411") (pin "4") (pinfunction "IN_4") (pintype "passive"))
    )
    (net (code "414") (name "Net-(P411-OUT)") (class "Default")
      (node (ref "P411") (pin "1") (pinfunction "OUT_1") (pintype "passive"))
      (node (ref "P412") (pin "4") (pinfunction "IN_4") (pintype "passive"))
    )
    (net (code "415") (name "Net-(P412-OUT)") (class "Default")
      (node (ref "P412") (pin "1") (pinfunction "OUT_1") (pintype "passive"))
      (node (ref "P413") (pin "4") (pinfunction "IN_4") (pintype "passive"))
    )
    (net (code "416") (name "Net-(P413-OUT)") (class "Default")
      (node (ref "P413") (pin "1") (pinfunction "OUT_1") (pintype "passive"))
      (node (ref "P414") (pin "4") (pinfunction "IN_4") (pintype "passive"))
    )
    (net (code "417") (name "Net-(P414-OUT)") (class "Default")
      (node (ref "P414") (pin "1") (pinfunction "OUT_1") (pintype "passive"))
      (node (ref "P415") (pin "4") (pinfunction "IN_4") (pintype "passive"))
    )
    (net (code "418") (name "Net-(P415-OUT)") (class "Default")
      (node (ref "P415") (pin "1") (pinfunction "OUT_1") (pintype "passive"))
      (node (ref "P416") (pin "4") (pinfunction "IN_4") (pintype "passive"))
    )
    (net (code "419") (name "Net-(P416-OUT)") (class "Default")
      (node (ref "P416") (pin "1") (pinfunction "OUT_1") (pintype "passive"))
      (node (ref "P417") (pin "4") (pinfunction "IN_4") (pintype "passive"))
    )
    (net (code "420") (name "Net-(P417-OUT)") (class "Default")
      (node (ref "P417") (pin "1") (pinfunction "OUT_1") (pintype "passive"))
      (node (ref "P418") (pin "4") (pinfunction "IN_4") (pintype "passive"))
    )
    (net (code "421") (name "Net-(P418-OUT)") (class "Default")
      (node (ref "P418") (pin "1") (pinfunction "OUT_1") (pintype "passive"))
      (node (ref "P419") (pin "4") (pinfunction "IN_4") (pintype "passive"))
    )
    (net (code "422") (name "Net-(P419-OUT)") (class "Default")
      (node (ref "P419") (pin "1") (pinfunction "OUT_1") (pintype "passive"))
      (node (ref "P420") (pin "4") (pinfunction "IN_4") (pintype "passive"))
    )
    (net (code "423") (name "Net-(P420-OUT)") (class "Default")
      (node (ref "P420") (pin "1") (pinfunction "OUT_1") (pintype "passive"))
      (node (ref "P421") (pin "4") (pinfunction "IN_4") (pintype "passive"))
    )
    (net (code "424") (name "Net-(P421-OUT)") (class "Default")
      (node (ref "P421") (pin "1") (pinfunction "OUT_1") (pintype "passive"))
      (node (ref "P422") (pin "4") (pinfunction "IN_4") (pintype "passive"))
    )
    (net (code "425") (name "Net-(P422-OUT)") (class "Default")
      (node (ref "P422") (pin "1") (pinfunction "OUT_1") (pintype "passive"))
      (node (ref "P423") (pin "4") (pinfunction "IN_4") (pintype "passive"))
    )
    (net (code "426") (name "Net-(P423-OUT)") (class "Default")
      (node (ref "P423") (pin "1") (pinfunction "OUT_1") (pintype "passive"))
      (node (ref "P424") (pin "4") (pinfunction "IN_4") (pintype "passive"))
    )
    (net (code "427") (name "Net-(P424-OUT)") (class "Default")
      (node (ref "P424") (pin "1") (pinfunction "OUT_1") (pintype "passive"))
      (node (ref "P425") (pin "4") (pinfunction "IN_4") (pintype "passive"))
    )
    (net (code "428") (name "Net-(P425-OUT)") (class "Default")
      (node (ref "P425") (pin "1") (pinfunction "OUT_1") (pintype "passive"))
      (node (ref "P426") (pin "4") (pinfunction "IN_4") (pintype "passive"))
    )
    (net (code "429") (name "Net-(P426-OUT)") (class "Default")
      (node (ref "P426") (pin "1") (pinfunction "OUT_1") (pintype "passive"))
      (node (ref "P427") (pin "4") (pinfunction "IN_4") (pintype "passive"))
    )
    (net (code "430") (name "Net-(P427-OUT)") (class "Default")
      (node (ref "P427") (pin "1") (pinfunction "OUT_1") (pintype "passive"))
      (node (ref "P428") (pin "4") (pinfunction "IN_4") (pintype "passive"))
    )
    (net (code "431") (name "Net-(P428-OUT)") (class "Default")
      (node (ref "P428") (pin "1") (pinfunction "OUT_1") (pintype "passive"))
      (node (ref "P429") (pin "4") (pinfunction "IN_4") (pintype "passive"))
    )
    (net (code "432") (name "Net-(P429-OUT)") (class "Default")
      (node (ref "P429") (pin "1") (pinfunction "OUT_1") (pintype "passive"))
      (node (ref "P430") (pin "4") (pinfunction "IN_4") (pintype "passive"))
    )
    (net (code "433") (name "Net-(P430-OUT)") (class "Default")
      (node (ref "P430") (pin "1") (pinfunction "OUT_1") (pintype "passive"))
      (node (ref "P431") (pin "4") (pinfunction "IN_4") (pintype "passive"))
    )
    (net (code "434") (name "Net-(P431-OUT)") (class "Default")
      (node (ref "P431") (pin "1") (pinfunction "OUT_1") (pintype "passive"))
      (node (ref "P432") (pin "4") (pinfunction "IN_4") (pintype "passive"))
    )
    (net (code "435") (name "Net-(P432-OUT)") (class "Default")
      (node (ref "P432") (pin "1") (pinfunction "OUT_1") (pintype "passive"))
      (node (ref "P433") (pin "4") (pinfunction "IN_4") (pintype "passive"))
    )
    (net (code "436") (name "Net-(P433-OUT)") (class "Default")
      (node (ref "P433") (pin "1") (pinfunction "OUT_1") (pintype "passive"))
      (node (ref "P434") (pin "4") (pinfunction "IN_4") (pintype "passive"))
    )
    (net (code "437") (name "Net-(P434-OUT)") (class "Default")
      (node (ref "P434") (pin "1") (pinfunction "OUT_1") (pintype "passive"))
      (node (ref "P435") (pin "4") (pinfunction "IN_4") (pintype "passive"))
    )
    (net (code "438") (name "Net-(P435-OUT)") (class "Default")
      (node (ref "P435") (pin "1") (pinfunction "OUT_1") (pintype "passive"))
      (node (ref "P436") (pin "4") (pinfunction "IN_4") (pintype "passive"))
    )
    (net (code "439") (name "Net-(P436-OUT)") (class "Default")
      (node (ref "P436") (pin "1") (pinfunction "OUT_1") (pintype "passive"))
      (node (ref "P437") (pin "4") (pinfunction "IN_4") (pintype "passive"))
    )
    (net (code "440") (name "Net-(P437-OUT)") (class "Default")
      (node (ref "P437") (pin "1") (pinfunction "OUT_1") (pintype "passive"))
      (node (ref "P438") (pin "4") (pinfunction "IN_4") (pintype "passive"))
    )
    (net (code "441") (name "Net-(P438-OUT)") (class "Default")
      (node (ref "P438") (pin "1") (pinfunction "OUT_1") (pintype "passive"))
      (node (ref "P439") (pin "4") (pinfunction "IN_4") (pintype "passive"))
    )
    (net (code "442") (name "Net-(P439-OUT)") (class "Default")
      (node (ref "P439") (pin "1") (pinfunction "OUT_1") (pintype "passive"))
      (node (ref "P440") (pin "4") (pinfunction "IN_4") (pintype "passive"))
    )
    (net (code "443") (name "Net-(P440-OUT)") (class "Default")
      (node (ref "P440") (pin "1") (pinfunction "OUT_1") (pintype "passive"))
      (node (ref "P441") (pin "4") (pinfunction "IN_4") (pintype "passive"))
    )
    (net (code "444") (name "Net-(P441-OUT)") (class "Default")
      (node (ref "P441") (pin "1") (pinfunction "OUT_1") (pintype "passive"))
      (node (ref "P442") (pin "4") (pinfunction "IN_4") (pintype "passive"))
    )
    (net (code "445") (name "Net-(P442-OUT)") (class "Default")
      (node (ref "P442") (pin "1") (pinfunction "OUT_1") (pintype "passive"))
      (node (ref "P443") (pin "4") (pinfunction "IN_4") (pintype "passive"))
    )
    (net (code "446") (name "Net-(P443-OUT)") (class "Default")
      (node (ref "P443") (pin "1") (pinfunction "OUT_1") (pintype "passive"))
      (node (ref "P444") (pin "4") (pinfunction "IN_4") (pintype "passive"))
    )
    (net (code "447") (name "Net-(P444-OUT)") (class "Default")
      (node (ref "P444") (pin "1") (pinfunction "OUT_1") (pintype "passive"))
      (node (ref "P445") (pin "4") (pinfunction "IN_4") (pintype "passive"))
    )
    (net (code "448") (name "Net-(P445-OUT)") (class "Default")
      (node (ref "P445") (pin "1") (pinfunction "OUT_1") (pintype "passive"))
      (node (ref "P446") (pin "4") (pinfunction "IN_4") (pintype "passive"))
    )
    (net (code "449") (name "Net-(P446-OUT)") (class "Default")
      (node (ref "P446") (pin "1") (pinfunction "OUT_1") (pintype "passive"))
      (node (ref "P447") (pin "4") (pinfunction "IN_4") (pintype "passive"))
    )
    (net (code "450") (name "Net-(P447-OUT)") (class "Default")
      (node (ref "P447") (pin "1") (pinfunction "OUT_1") (pintype "passive"))
      (node (ref "P448") (pin "4") (pinfunction "IN_4") (pintype "passive"))
    )
    (net (code "451") (name "Net-(P448-OUT)") (class "Default")
      (node (ref "P448") (pin "1") (pinfunction "OUT_1") (pintype "passive"))
      (node (ref "P449") (pin "4") (pinfunction "IN_4") (pintype "passive"))
    )
    (net (code "452") (name "Net-(P449-OUT)") (class "Default")
      (node (ref "P449") (pin "1") (pinfunction "OUT_1") (pintype "passive"))
      (node (ref "P450") (pin "4") (pinfunction "IN_4") (pintype "passive"))
    )
    (net (code "453") (name "Net-(P450-OUT)") (class "Default")
      (node (ref "P450") (pin "1") (pinfunction "OUT_1") (pintype "passive"))
      (node (ref "P451") (pin "4") (pinfunction "IN_4") (pintype "passive"))
    )
    (net (code "454") (name "Net-(P451-OUT)") (class "Default")
      (node (ref "P451") (pin "1") (pinfunction "OUT_1") (pintype "passive"))
      (node (ref "P452") (pin "4") (pinfunction "IN_4") (pintype "passive"))
    )
    (net (code "455") (name "Net-(P452-OUT)") (class "Default")
      (node (ref "P452") (pin "1") (pinfunction "OUT_1") (pintype "passive"))
      (node (ref "P453") (pin "4") (pinfunction "IN_4") (pintype "passive"))
    )
    (net (code "456") (name "Net-(P453-OUT)") (class "Default")
      (node (ref "P453") (pin "1") (pinfunction "OUT_1") (pintype "passive"))
      (node (ref "P454") (pin "4") (pinfunction "IN_4") (pintype "passive"))
    )
    (net (code "457") (name "Net-(P454-OUT)") (class "Default")
      (node (ref "P454") (pin "1") (pinfunction "OUT_1") (pintype "passive"))
      (node (ref "P455") (pin "4") (pinfunction "IN_4") (pintype "passive"))
    )
    (net (code "458") (name "Net-(P455-OUT)") (class "Default")
      (node (ref "P455") (pin "1") (pinfunction "OUT_1") (pintype "passive"))
      (node (ref "P456") (pin "4") (pinfunction "IN_4") (pintype "passive"))
    )
    (net (code "459") (name "Net-(P456-OUT)") (class "Default")
      (node (ref "P456") (pin "1") (pinfunction "OUT_1") (pintype "passive"))
      (node (ref "P457") (pin "4") (pinfunction "IN_4") (pintype "passive"))
    )
    (net (code "460") (name "Net-(P457-OUT)") (class "Default")
      (node (ref "P457") (pin "1") (pinfunction "OUT_1") (pintype "passive"))
      (node (ref "P458") (pin "4") (pinfunction "IN_4") (pintype "passive"))
    )
    (net (code "461") (name "Net-(P458-OUT)") (class "Default")
      (node (ref "P458") (pin "1") (pinfunction "OUT_1") (pintype "passive"))
      (node (ref "P459") (pin "4") (pinfunction "IN_4") (pintype "passive"))
    )
    (net (code "462") (name "Net-(P459-OUT)") (class "Default")
      (node (ref "P459") (pin "1") (pinfunction "OUT_1") (pintype "passive"))
      (node (ref "P460") (pin "4") (pinfunction "IN_4") (pintype "passive"))
    )
    (net (code "463") (name "Net-(P460-OUT)") (class "Default")
      (node (ref "P460") (pin "1") (pinfunction "OUT_1") (pintype "passive"))
      (node (ref "P461") (pin "4") (pinfunction "IN_4") (pintype "passive"))
    )
    (net (code "464") (name "Net-(P461-OUT)") (class "Default")
      (node (ref "P461") (pin "1") (pinfunction "OUT_1") (pintype "passive"))
      (node (ref "P462") (pin "4") (pinfunction "IN_4") (pintype "passive"))
    )
    (net (code "465") (name "Net-(P462-OUT)") (class "Default")
      (node (ref "P462") (pin "1") (pinfunction "OUT_1") (pintype "passive"))
      (node (ref "P463") (pin "4") (pinfunction "IN_4") (pintype "passive"))
    )
    (net (code "466") (name "Net-(P463-OUT)") (class "Default")
      (node (ref "P463") (pin "1") (pinfunction "OUT_1") (pintype "passive"))
      (node (ref "P464") (pin "4") (pinfunction "IN_4") (pintype "passive"))
    )
    (net (code "467") (name "Net-(P464-OUT)") (class "Default")
      (node (ref "P464") (pin "1") (pinfunction "OUT_1") (pintype "passive"))
      (node (ref "P465") (pin "4") (pinfunction "IN_4") (pintype "passive"))
    )
    (net (code "468") (name "Net-(P465-OUT)") (class "Default")
      (node (ref "P465") (pin "1") (pinfunction "OUT_1") (pintype "passive"))
      (node (ref "P466") (pin "4") (pinfunction "IN_4") (pintype "passive"))
    )
    (net (code "469") (name "Net-(P466-OUT)") (class "Default")
      (node (ref "P466") (pin "1") (pinfunction "OUT_1") (pintype "passive"))
      (node (ref "P467") (pin "4") (pinfunction "IN_4") (pintype "passive"))
    )
    (net (code "470") (name "Net-(P467-OUT)") (class "Default")
      (node (ref "P467") (pin "1") (pinfunction "OUT_1") (pintype "passive"))
      (node (ref "P468") (pin "4") (pinfunction "IN_4") (pintype "passive"))
    )
    (net (code "471") (name "Net-(P468-OUT)") (class "Default")
      (node (ref "P468") (pin "1") (pinfunction "OUT_1") (pintype "passive"))
      (node (ref "P469") (pin "4") (pinfunction "IN_4") (pintype "passive"))
    )
    (net (code "472") (name "Net-(P469-OUT)") (class "Default")
      (node (ref "P469") (pin "1") (pinfunction "OUT_1") (pintype "passive"))
      (node (ref "P470") (pin "4") (pinfunction "IN_4") (pintype "passive"))
    )
    (net (code "473") (name "Net-(P470-OUT)") (class "Default")
      (node (ref "P470") (pin "1") (pinfunction "OUT_1") (pintype "passive"))
      (node (ref "P471") (pin "4") (pinfunction "IN_4") (pintype "passive"))
    )
    (net (code "474") (name "Net-(P471-OUT)") (class "Default")
      (node (ref "P471") (pin "1") (pinfunction "OUT_1") (pintype "passive"))
      (node (ref "P472") (pin "4") (pinfunction "IN_4") (pintype "passive"))
    )
    (net (code "475") (name "Net-(P472-OUT)") (class "Default")
      (node (ref "P472") (pin "1") (pinfunction "OUT_1") (pintype "passive"))
      (node (ref "P473") (pin "4") (pinfunction "IN_4") (pintype "passive"))
    )
    (net (code "476") (name "Net-(P473-OUT)") (class "Default")
      (node (ref "P473") (pin "1") (pinfunction "OUT_1") (pintype "passive"))
      (node (ref "P474") (pin "4") (pinfunction "IN_4") (pintype "passive"))
    )
    (net (code "477") (name "Net-(P474-OUT)") (class "Default")
      (node (ref "P474") (pin "1") (pinfunction "OUT_1") (pintype "passive"))
      (node (ref "P475") (pin "4") (pinfunction "IN_4") (pintype "passive"))
    )
    (net (code "478") (name "Net-(P475-OUT)") (class "Default")
      (node (ref "P475") (pin "1") (pinfunction "OUT_1") (pintype "passive"))
      (node (ref "P476") (pin "4") (pinfunction "IN_4") (pintype "passive"))
    )
    (net (code "479") (name "Net-(P476-OUT)") (class "Default")
      (node (ref "P476") (pin "1") (pinfunction "OUT_1") (pintype "passive"))
      (node (ref "P477") (pin "4") (pinfunction "IN_4") (pintype "passive"))
    )
    (net (code "480") (name "Net-(P477-OUT)") (class "Default")
      (node (ref "P477") (pin "1") (pinfunction "OUT_1") (pintype "passive"))
      (node (ref "P478") (pin "4") (pinfunction "IN_4") (pintype "passive"))
    )
    (net (code "481") (name "Net-(P478-OUT)") (class "Default")
      (node (ref "P478") (pin "1") (pinfunction "OUT_1") (pintype "passive"))
      (node (ref "P479") (pin "4") (pinfunction "IN_4") (pintype "passive"))
    )
    (net (code "482") (name "Net-(P479-OUT)") (class "Default")
      (node (ref "P479") (pin "1") (pinfunction "OUT_1") (pintype "passive"))
      (node (ref "P480") (pin "4") (pinfunction "IN_4") (pintype "passive"))
    )
    (net (code "483") (name "Net-(P480-OUT)") (class "Default")
      (node (ref "P480") (pin "1") (pinfunction "OUT_1") (pintype "passive"))
      (node (ref "P481") (pin "4") (pinfunction "IN_4") (pintype "passive"))
    )
    (net (code "484") (name "Net-(P481-OUT)") (class "Default")
      (node (ref "P481") (pin "1") (pinfunction "OUT_1") (pintype "passive"))
      (node (ref "P482") (pin "4") (pinfunction "IN_4") (pintype "passive"))
    )
    (net (code "485") (name "Net-(P482-OUT)") (class "Default")
      (node (ref "P482") (pin "1") (pinfunction "OUT_1") (pintype "passive"))
      (node (ref "P483") (pin "4") (pinfunction "IN_4") (pintype "passive"))
    )
    (net (code "486") (name "Net-(P483-OUT)") (class "Default")
      (node (ref "P483") (pin "1") (pinfunction "OUT_1") (pintype "passive"))
      (node (ref "P484") (pin "4") (pinfunction "IN_4") (pintype "passive"))
    )
    (net (code "487") (name "Net-(P484-OUT)") (class "Default")
      (node (ref "P484") (pin "1") (pinfunction "OUT_1") (pintype "passive"))
      (node (ref "P485") (pin "4") (pinfunction "IN_4") (pintype "passive"))
    )
    (net (code "488") (name "Net-(P485-OUT)") (class "Default")
      (node (ref "P485") (pin "1") (pinfunction "OUT_1") (pintype "passive"))
      (node (ref "P486") (pin "4") (pinfunction "IN_4") (pintype "passive"))
    )
    (net (code "489") (name "Net-(P486-OUT)") (class "Default")
      (node (ref "P486") (pin "1") (pinfunction "OUT_1") (pintype "passive"))
      (node (ref "P487") (pin "4") (pinfunction "IN_4") (pintype "passive"))
    )
    (net (code "490") (name "Net-(P487-OUT)") (class "Default")
      (node (ref "P487") (pin "1") (pinfunction "OUT_1") (pintype "passive"))
      (node (ref "P488") (pin "4") (pinfunction "IN_4") (pintype "passive"))
    )
    (net (code "491") (name "Net-(P488-OUT)") (class "Default")
      (node (ref "P488") (pin "1") (pinfunction "OUT_1") (pintype "passive"))
      (node (ref "P489") (pin "4") (pinfunction "IN_4") (pintype "passive"))
    )
    (net (code "492") (name "Net-(P489-OUT)") (class "Default")
      (node (ref "P489") (pin "1") (pinfunction "OUT_1") (pintype "passive"))
      (node (ref "P490") (pin "4") (pinfunction "IN_4") (pintype "passive"))
    )
    (net (code "493") (name "Net-(P490-OUT)") (class "Default")
      (node (ref "P490") (pin "1") (pinfunction "OUT_1") (pintype "passive"))
      (node (ref "P491") (pin "4") (pinfunction "IN_4") (pintype "passive"))
    )
    (net (code "494") (name "Net-(P491-OUT)") (class "Default")
      (node (ref "P491") (pin "1") (pinfunction "OUT_1") (pintype "passive"))
      (node (ref "P492") (pin "4") (pinfunction "IN_4") (pintype "passive"))
    )
    (net (code "495") (name "Net-(P492-OUT)") (class "Default")
      (node (ref "P492") (pin "1") (pinfunction "OUT_1") (pintype "passive"))
      (node (ref "P493") (pin "4") (pinfunction "IN_4") (pintype "passive"))
    )
    (net (code "496") (name "Net-(P493-OUT)") (class "Default")
      (node (ref "P493") (pin "1") (pinfunction "OUT_1") (pintype "passive"))
      (node (ref "P494") (pin "4") (pinfunction "IN_4") (pintype "passive"))
    )
    (net (code "497") (name "Net-(P494-OUT)") (class "Default")
      (node (ref "P494") (pin "1") (pinfunction "OUT_1") (pintype "passive"))
      (node (ref "P495") (pin "4") (pinfunction "IN_4") (pintype "passive"))
    )
    (net (code "498") (name "Net-(P495-OUT)") (class "Default")
      (node (ref "P495") (pin "1") (pinfunction "OUT_1") (pintype "passive"))
      (node (ref "P496") (pin "4") (pinfunction "IN_4") (pintype "passive"))
    )
    (net (code "499") (name "Net-(P496-OUT)") (class "Default")
      (node (ref "P496") (pin "1") (pinfunction "OUT_1") (pintype "passive"))
      (node (ref "P497") (pin "4") (pinfunction "IN_4") (pintype "passive"))
    )
    (net (code "500") (name "Net-(P497-OUT)") (class "Default")
      (node (ref "P497") (pin "1") (pinfunction "OUT_1") (pintype "passive"))
      (node (ref "P498") (pin "4") (pinfunction "IN_4") (pintype "passive"))
    )
    (net (code "501") (name "Net-(P498-OUT)") (class "Default")
      (node (ref "P498") (pin "1") (pinfunction "OUT_1") (pintype "passive"))
      (node (ref "P499") (pin "4") (pinfunction "IN_4") (pintype "passive"))
    )
    (net (code "502") (name "Net-(P499-OUT)") (class "Default")
      (node (ref "P499") (pin "1") (pinfunction "OUT_1") (pintype "passive"))
      (node (ref "P500") (pin "4") (pinfunction "IN_4") (pintype "passive"))
    )
    (net (code "503") (name "Net-(P500-OUT)") (class "Default")
      (node (ref "P500") (pin "1") (pinfunction "OUT_1") (pintype "passive"))
      (node (ref "P501") (pin "4") (pinfunction "IN_4") (pintype "passive"))
    )
    (net (code "504") (name "Net-(P501-OUT)") (class "Default")
      (node (ref "P501") (pin "1") (pinfunction "OUT_1") (pintype "passive"))
      (node (ref "P502") (pin "4") (pinfunction "IN_4") (pintype "passive"))
    )
    (net (code "505") (name "Net-(P502-OUT)") (class "Default")
      (node (ref "P502") (pin "1") (pinfunction "OUT_1") (pintype "passive"))
      (node (ref "P503") (pin "4") (pinfunction "IN_4") (pintype "passive"))
    )
    (net (code "506") (name "Net-(P503-OUT)") (class "Default")
      (node (ref "P503") (pin "1") (pinfunction "OUT_1") (pintype "passive"))
      (node (ref "P504") (pin "4") (pinfunction "IN_4") (pintype "passive"))
    )
    (net (code "507") (name "Net-(P504-OUT)") (class "Default")
      (node (ref "P504") (pin "1") (pinfunction "OUT_1") (pintype "passive"))
      (node (ref "P505") (pin "4") (pinfunction "IN_4") (pintype "passive"))
    )
    (net (code "508") (name "Net-(P505-OUT)") (class "Default")
      (node (ref "P505") (pin "1") (pinfunction "OUT_1") (pintype "passive"))
      (node (ref "P506") (pin "4") (pinfunction "IN_4") (pintype "passive"))
    )
    (net (code "509") (name "Net-(P506-OUT)") (class "Default")
      (node (ref "P506") (pin "1") (pinfunction "OUT_1") (pintype "passive"))
      (node (ref "P507") (pin "4") (pinfunction "IN_4") (pintype "passive"))
    )
    (net (code "510") (name "Net-(P507-OUT)") (class "Default")
      (node (ref "P507") (pin "1") (pinfunction "OUT_1") (pintype "passive"))
      (node (ref "P508") (pin "4") (pinfunction "IN_4") (pintype "passive"))
    )
    (net (code "511") (name "Net-(P508-OUT)") (class "Default")
      (node (ref "P508") (pin "1") (pinfunction "OUT_1") (pintype "passive"))
      (node (ref "P509") (pin "4") (pinfunction "IN_4") (pintype "passive"))
    )
    (net (code "512") (name "Net-(P509-OUT)") (class "Default")
      (node (ref "P509") (pin "1") (pinfunction "OUT_1") (pintype "passive"))
      (node (ref "P510") (pin "4") (pinfunction "IN_4") (pintype "passive"))
    )
    (net (code "513") (name "Net-(P510-OUT)") (class "Default")
      (node (ref "P510") (pin "1") (pinfunction "OUT_1") (pintype "passive"))
      (node (ref "P511") (pin "4") (pinfunction "IN_4") (pintype "passive"))
    )
    (net (code "514") (name "Net-(P511-OUT)") (class "Default")
      (node (ref "P511") (pin "1") (pinfunction "OUT_1") (pintype "passive"))
      (node (ref "P512") (pin "4") (pinfunction "IN_4") (pintype "passive"))
    )
    (net (code "515") (name "Net-(P512-OUT)") (class "Default")
      (node (ref "P512") (pin "1") (pinfunction "OUT_1") (pintype "passive"))
      (node (ref "P513") (pin "4") (pinfunction "IN_4") (pintype "passive"))
    )
    (net (code "516") (name "Net-(P513-OUT)") (class "Default")
      (node (ref "P513") (pin "1") (pinfunction "OUT_1") (pintype "passive"))
      (node (ref "P514") (pin "4") (pinfunction "IN_4") (pintype "passive"))
    )
    (net (code "517") (name "Net-(P514-OUT)") (class "Default")
      (node (ref "P514") (pin "1") (pinfunction "OUT_1") (pintype "passive"))
      (node (ref "P515") (pin "4") (pinfunction "IN_4") (pintype "passive"))
    )
    (net (code "518") (name "Net-(P515-OUT)") (class "Default")
      (node (ref "P515") (pin "1") (pinfunction "OUT_1") (pintype "passive"))
      (node (ref "P516") (pin "4") (pinfunction "IN_4") (pintype "passive"))
    )
    (net (code "519") (name "Net-(P516-OUT)") (class "Default")
      (node (ref "P516") (pin "1") (pinfunction "OUT_1") (pintype "passive"))
      (node (ref "P517") (pin "4") (pinfunction "IN_4") (pintype "passive"))
    )
    (net (code "520") (name "Net-(P517-OUT)") (class "Default")
      (node (ref "P517") (pin "1") (pinfunction "OUT_1") (pintype "passive"))
      (node (ref "P518") (pin "4") (pinfunction "IN_4") (pintype "passive"))
    )
    (net (code "521") (name "Net-(P518-OUT)") (class "Default")
      (node (ref "P518") (pin "1") (pinfunction "OUT_1") (pintype "passive"))
      (node (ref "P519") (pin "4") (pinfunction "IN_4") (pintype "passive"))
    )
    (net (code "522") (name "Net-(P519-OUT)") (class "Default")
      (node (ref "P519") (pin "1") (pinfunction "OUT_1") (pintype "passive"))
      (node (ref "P520") (pin "4") (pinfunction "IN_4") (pintype "passive"))
    )
    (net (code "523") (name "Net-(P520-OUT)") (class "Default")
      (node (ref "P520") (pin "1") (pinfunction "OUT_1") (pintype "passive"))
      (node (ref "P521") (pin "4") (pinfunction "IN_4") (pintype "passive"))
    )
    (net (code "524") (name "Net-(P521-OUT)") (class "Default")
      (node (ref "P521") (pin "1") (pinfunction "OUT_1") (pintype "passive"))
      (node (ref "P522") (pin "4") (pinfunction "IN_4") (pintype "passive"))
    )
    (net (code "525") (name "Net-(P522-OUT)") (class "Default")
      (node (ref "P522") (pin "1") (pinfunction "OUT_1") (pintype "passive"))
      (node (ref "P523") (pin "4") (pinfunction "IN_4") (pintype "passive"))
    )
    (net (code "526") (name "Net-(P523-OUT)") (class "Default")
      (node (ref "P523") (pin "1") (pinfunction "OUT_1") (pintype "passive"))
      (node (ref "P524") (pin "4") (pinfunction "IN_4") (pintype "passive"))
    )
    (net (code "527") (name "Net-(P524-OUT)") (class "Default")
      (node (ref "P524") (pin "1") (pinfunction "OUT_1") (pintype "passive"))
      (node (ref "P525") (pin "4") (pinfunction "IN_4") (pintype "passive"))
    )
    (net (code "528") (name "Net-(P525-OUT)") (class "Default")
      (node (ref "P525") (pin "1") (pinfunction "OUT_1") (pintype "passive"))
      (node (ref "P526") (pin "4") (pinfunction "IN_4") (pintype "passive"))
    )
    (net (code "529") (name "Net-(P526-OUT)") (class "Default")
      (node (ref "P526") (pin "1") (pinfunction "OUT_1") (pintype "passive"))
      (node (ref "P527") (pin "4") (pinfunction "IN_4") (pintype "passive"))
    )
    (net (code "530") (name "Net-(P527-OUT)") (class "Default")
      (node (ref "P527") (pin "1") (pinfunction "OUT_1") (pintype "passive"))
      (node (ref "P528") (pin "4") (pinfunction "IN_4") (pintype "passive"))
    )
    (net (code "531") (name "Net-(P528-OUT)") (class "Default")
      (node (ref "P528") (pin "1") (pinfunction "OUT_1") (pintype "passive"))
      (node (ref "P529") (pin "4") (pinfunction "IN_4") (pintype "passive"))
    )
    (net (code "532") (name "Net-(P529-OUT)") (class "Default")
      (node (ref "P529") (pin "1") (pinfunction "OUT_1") (pintype "passive"))
      (node (ref "P530") (pin "4") (pinfunction "IN_4") (pintype "passive"))
    )
    (net (code "533") (name "Net-(P530-OUT)") (class "Default")
      (node (ref "P530") (pin "1") (pinfunction "OUT_1") (pintype "passive"))
      (node (ref "P531") (pin "4") (pinfunction "IN_4") (pintype "passive"))
    )
    (net (code "534") (name "Net-(P531-OUT)") (class "Default")
      (node (ref "P531") (pin "1") (pinfunction "OUT_1") (pintype "passive"))
      (node (ref "P532") (pin "4") (pinfunction "IN_4") (pintype "passive"))
    )
    (net (code "535") (name "Net-(P532-OUT)") (class "Default")
      (node (ref "P532") (pin "1") (pinfunction "OUT_1") (pintype "passive"))
      (node (ref "P533") (pin "4") (pinfunction "IN_4") (pintype "passive"))
    )
    (net (code "536") (name "Net-(P533-OUT)") (class "Default")
      (node (ref "P533") (pin "1") (pinfunction "OUT_1") (pintype "passive"))
      (node (ref "P534") (pin "4") (pinfunction "IN_4") (pintype "passive"))
    )
    (net (code "537") (name "Net-(P534-OUT)") (class "Default")
      (node (ref "P534") (pin "1") (pinfunction "OUT_1") (pintype "passive"))
      (node (ref "P535") (pin "4") (pinfunction "IN_4") (pintype "passive"))
    )
    (net (code "538") (name "Net-(P535-OUT)") (class "Default")
      (node (ref "P535") (pin "1") (pinfunction "OUT_1") (pintype "passive"))
      (node (ref "P536") (pin "4") (pinfunction "IN_4") (pintype "passive"))
    )
    (net (code "539") (name "Net-(P536-OUT)") (class "Default")
      (node (ref "P536") (pin "1") (pinfunction "OUT_1") (pintype "passive"))
      (node (ref "P537") (pin "4") (pinfunction "IN_4") (pintype "passive"))
    )
    (net (code "540") (name "Net-(P537-OUT)") (class "Default")
      (node (ref "P537") (pin "1") (pinfunction "OUT_1") (pintype "passive"))
      (node (ref "P538") (pin "4") (pinfunction "IN_4") (pintype "passive"))
    )
    (net (code "541") (name "Net-(P538-OUT)") (class "Default")
      (node (ref "P538") (pin "1") (pinfunction "OUT_1") (pintype "passive"))
      (node (ref "P539") (pin "4") (pinfunction "IN_4") (pintype "passive"))
    )
    (net (code "542") (name "Net-(P539-OUT)") (class "Default")
      (node (ref "P539") (pin "1") (pinfunction "OUT_1") (pintype "passive"))
      (node (ref "P540") (pin "4") (pinfunction "IN_4") (pintype "passive"))
    )
    (net (code "543") (name "Net-(P540-OUT)") (class "Default")
      (node (ref "P540") (pin "1") (pinfunction "OUT_1") (pintype "passive"))
      (node (ref "P541") (pin "4") (pinfunction "IN_4") (pintype "passive"))
    )
    (net (code "544") (name "Net-(P541-OUT)") (class "Default")
      (node (ref "P541") (pin "1") (pinfunction "OUT_1") (pintype "passive"))
      (node (ref "P542") (pin "4") (pinfunction "IN_4") (pintype "passive"))
    )
    (net (code "545") (name "Net-(P542-OUT)") (class "Default")
      (node (ref "P542") (pin "1") (pinfunction "OUT_1") (pintype "passive"))
      (node (ref "P543") (pin "4") (pinfunction "IN_4") (pintype "passive"))
    )
    (net (code "546") (name "Net-(P543-OUT)") (class "Default")
      (node (ref "P543") (pin "1") (pinfunction "OUT_1") (pintype "passive"))
      (node (ref "P544") (pin "4") (pinfunction "IN_4") (pintype "passive"))
    )
    (net (code "547") (name "Net-(P544-OUT)") (class "Default")
      (node (ref "P544") (pin "1") (pinfunction "OUT_1") (pintype "passive"))
      (node (ref "P545") (pin "4") (pinfunction "IN_4") (pintype "passive"))
    )
    (net (code "548") (name "Net-(P545-OUT)") (class "Default")
      (node (ref "P545") (pin "1") (pinfunction "OUT_1") (pintype "passive"))
      (node (ref "P546") (pin "4") (pinfunction "IN_4") (pintype "passive"))
    )
    (net (code "549") (name "Net-(P546-OUT)") (class "Default")
      (node (ref "P546") (pin "1") (pinfunction "OUT_1") (pintype "passive"))
      (node (ref "P547") (pin "4") (pinfunction "IN_4") (pintype "passive"))
    )
    (net (code "550") (name "Net-(P547-OUT)") (class "Default")
      (node (ref "P547") (pin "1") (pinfunction "OUT_1") (pintype "passive"))
      (node (ref "P548") (pin "4") (pinfunction "IN_4") (pintype "passive"))
    )
    (net (code "551") (name "unconnected-(P280-OUT-Pad1)") (class "Default")
      (node (ref "P280") (pin "1") (pinfunction "OUT_1") (pintype "passive"))
    )
    (net (code "552") (name "unconnected-(P548-OUT-Pad1)") (class "Default")
      (node (ref "P548") (pin "1") (pinfunction "OUT_1") (pintype "passive"))
    )
  )
)
